# BEP33_6panel_rev1_90Grad.net
KiCad netlist of a schematic drawn in EAGLE
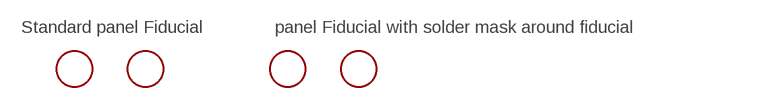
[diagram p0: schematic, sheet 1]
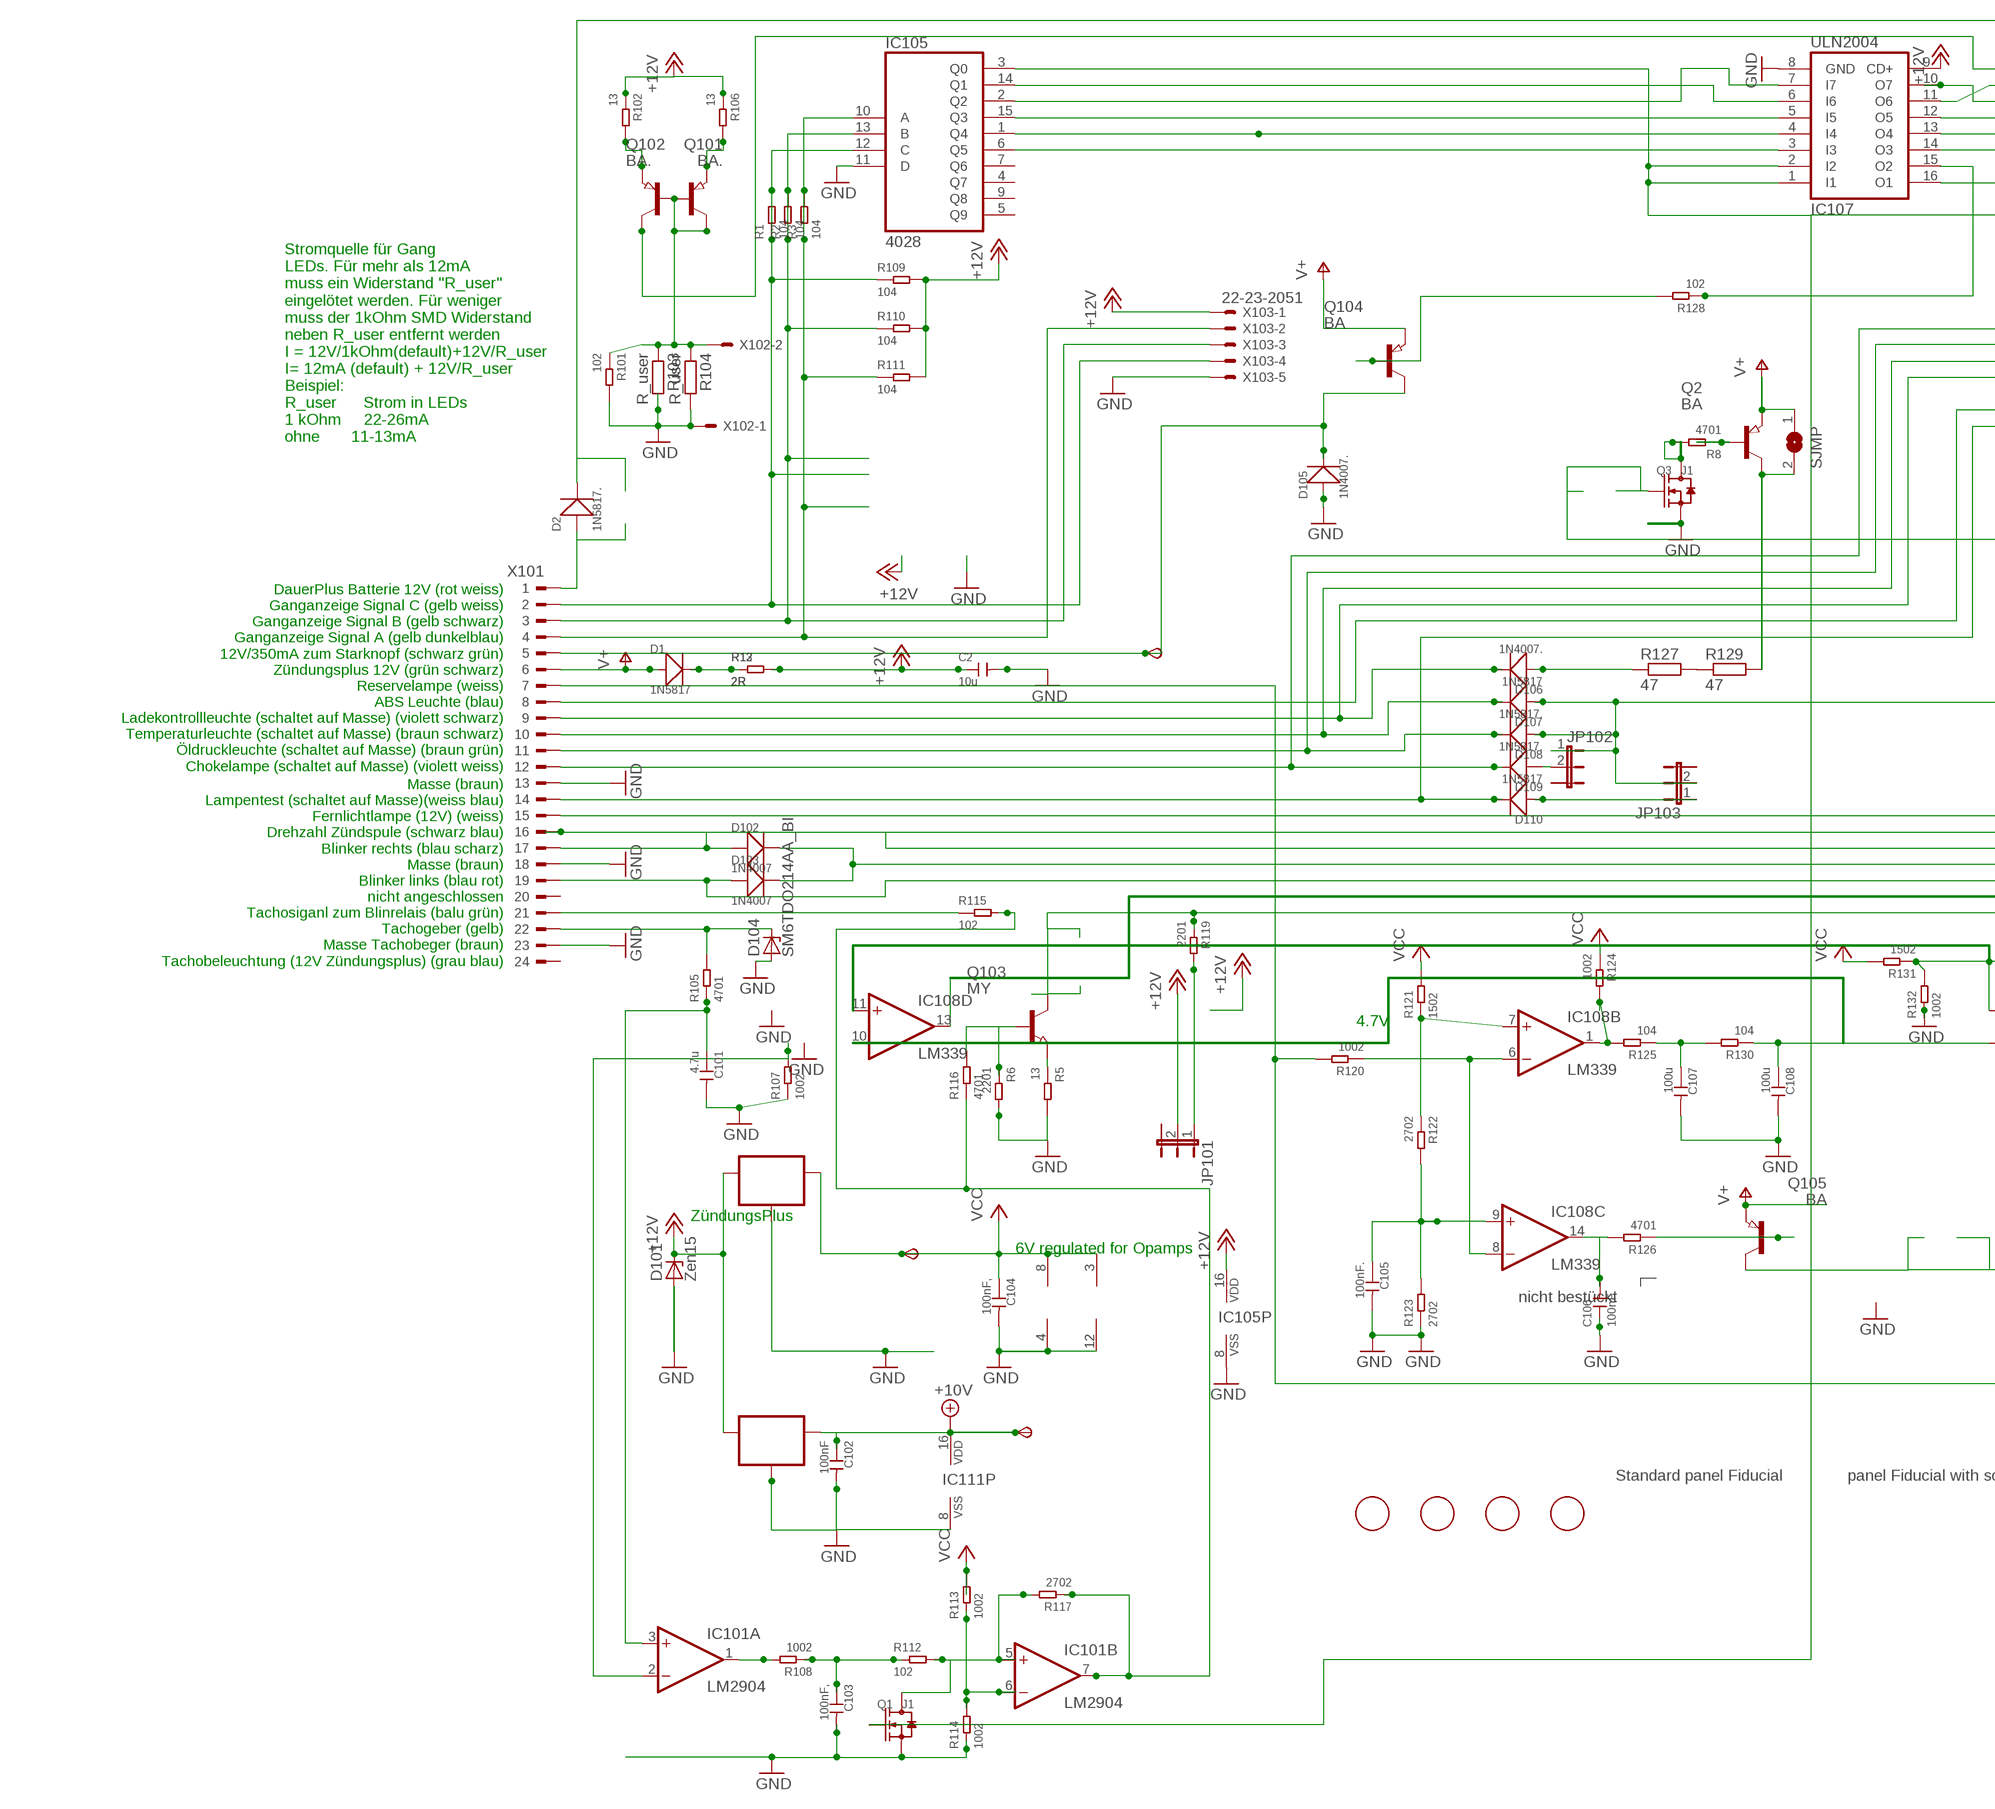
[diagram p1: schematic, sheet 2, part 1 of 2]
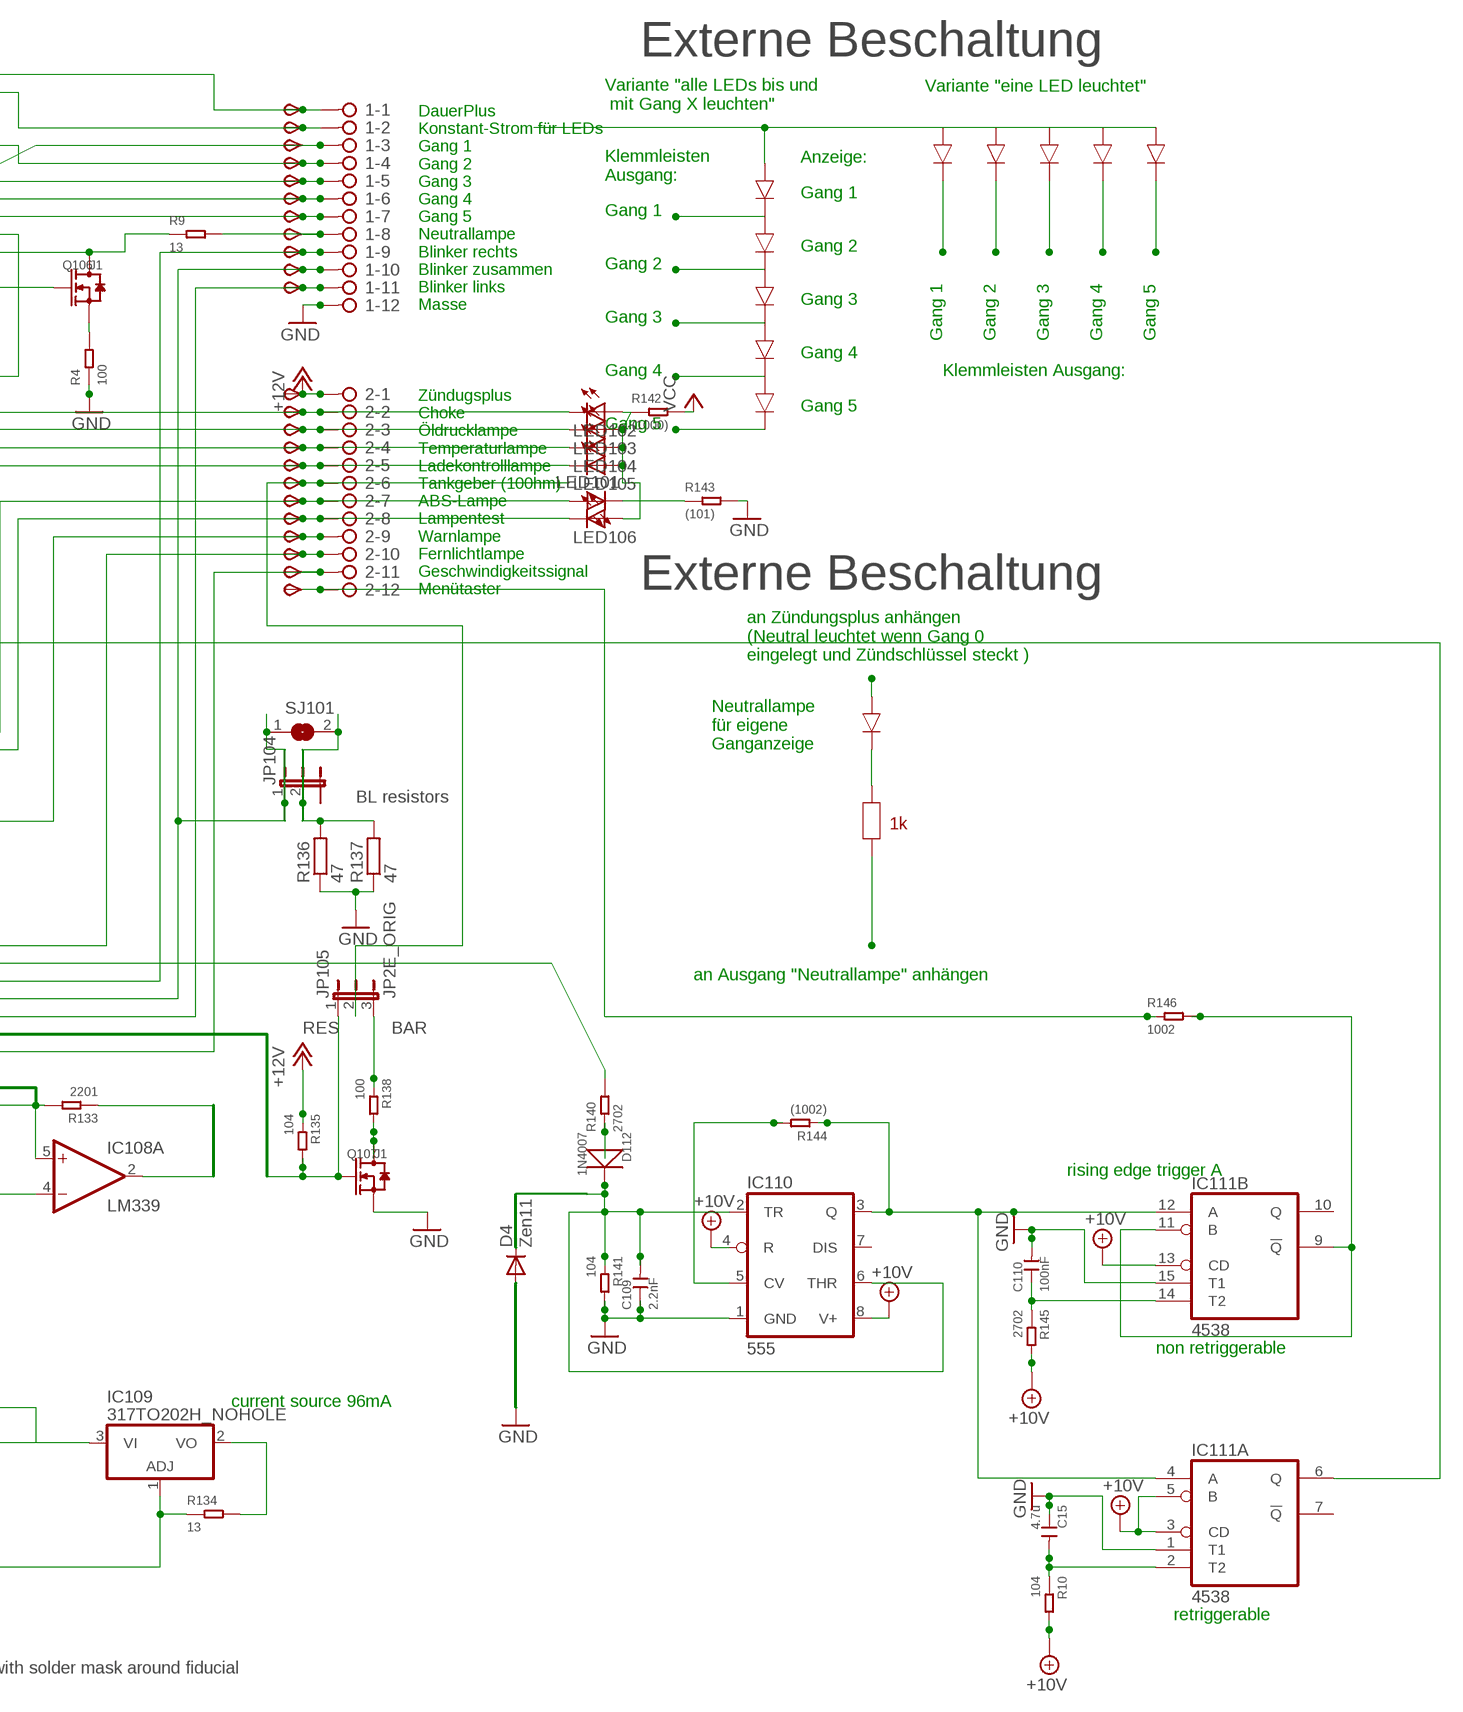
[diagram p2: schematic, sheet 2, part 2 of 2]
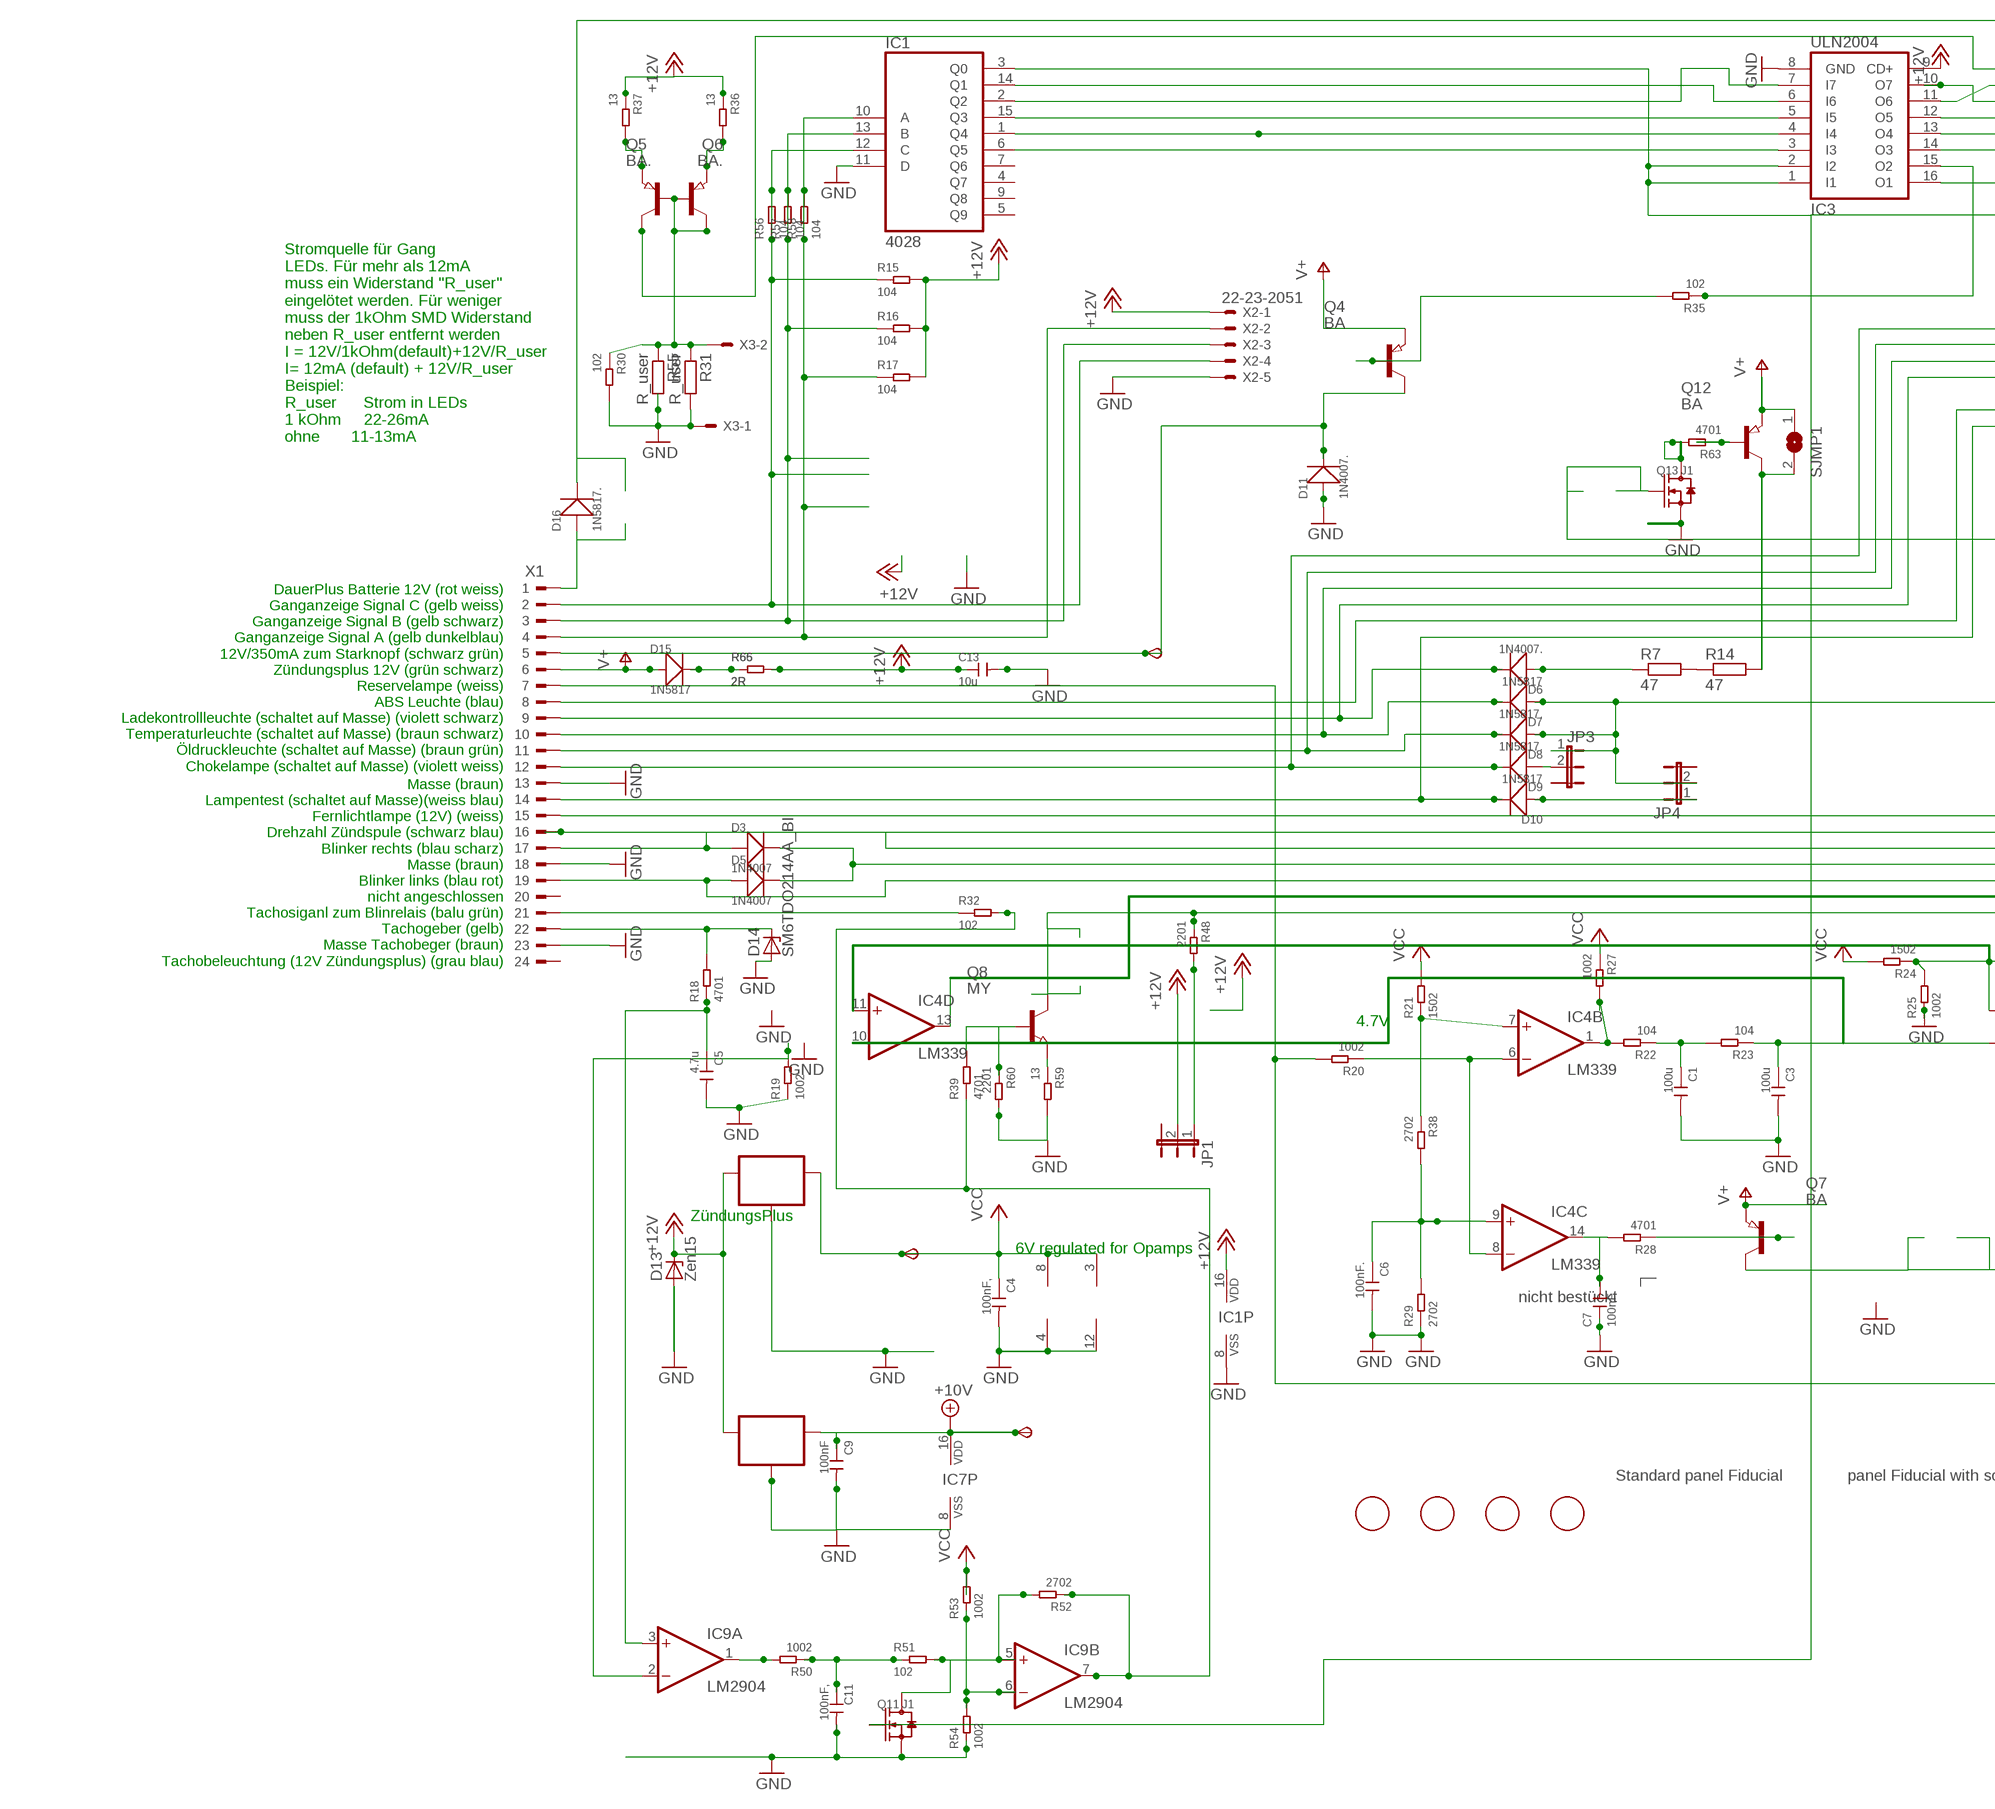
[diagram p3: schematic, sheet 3, part 1 of 2]
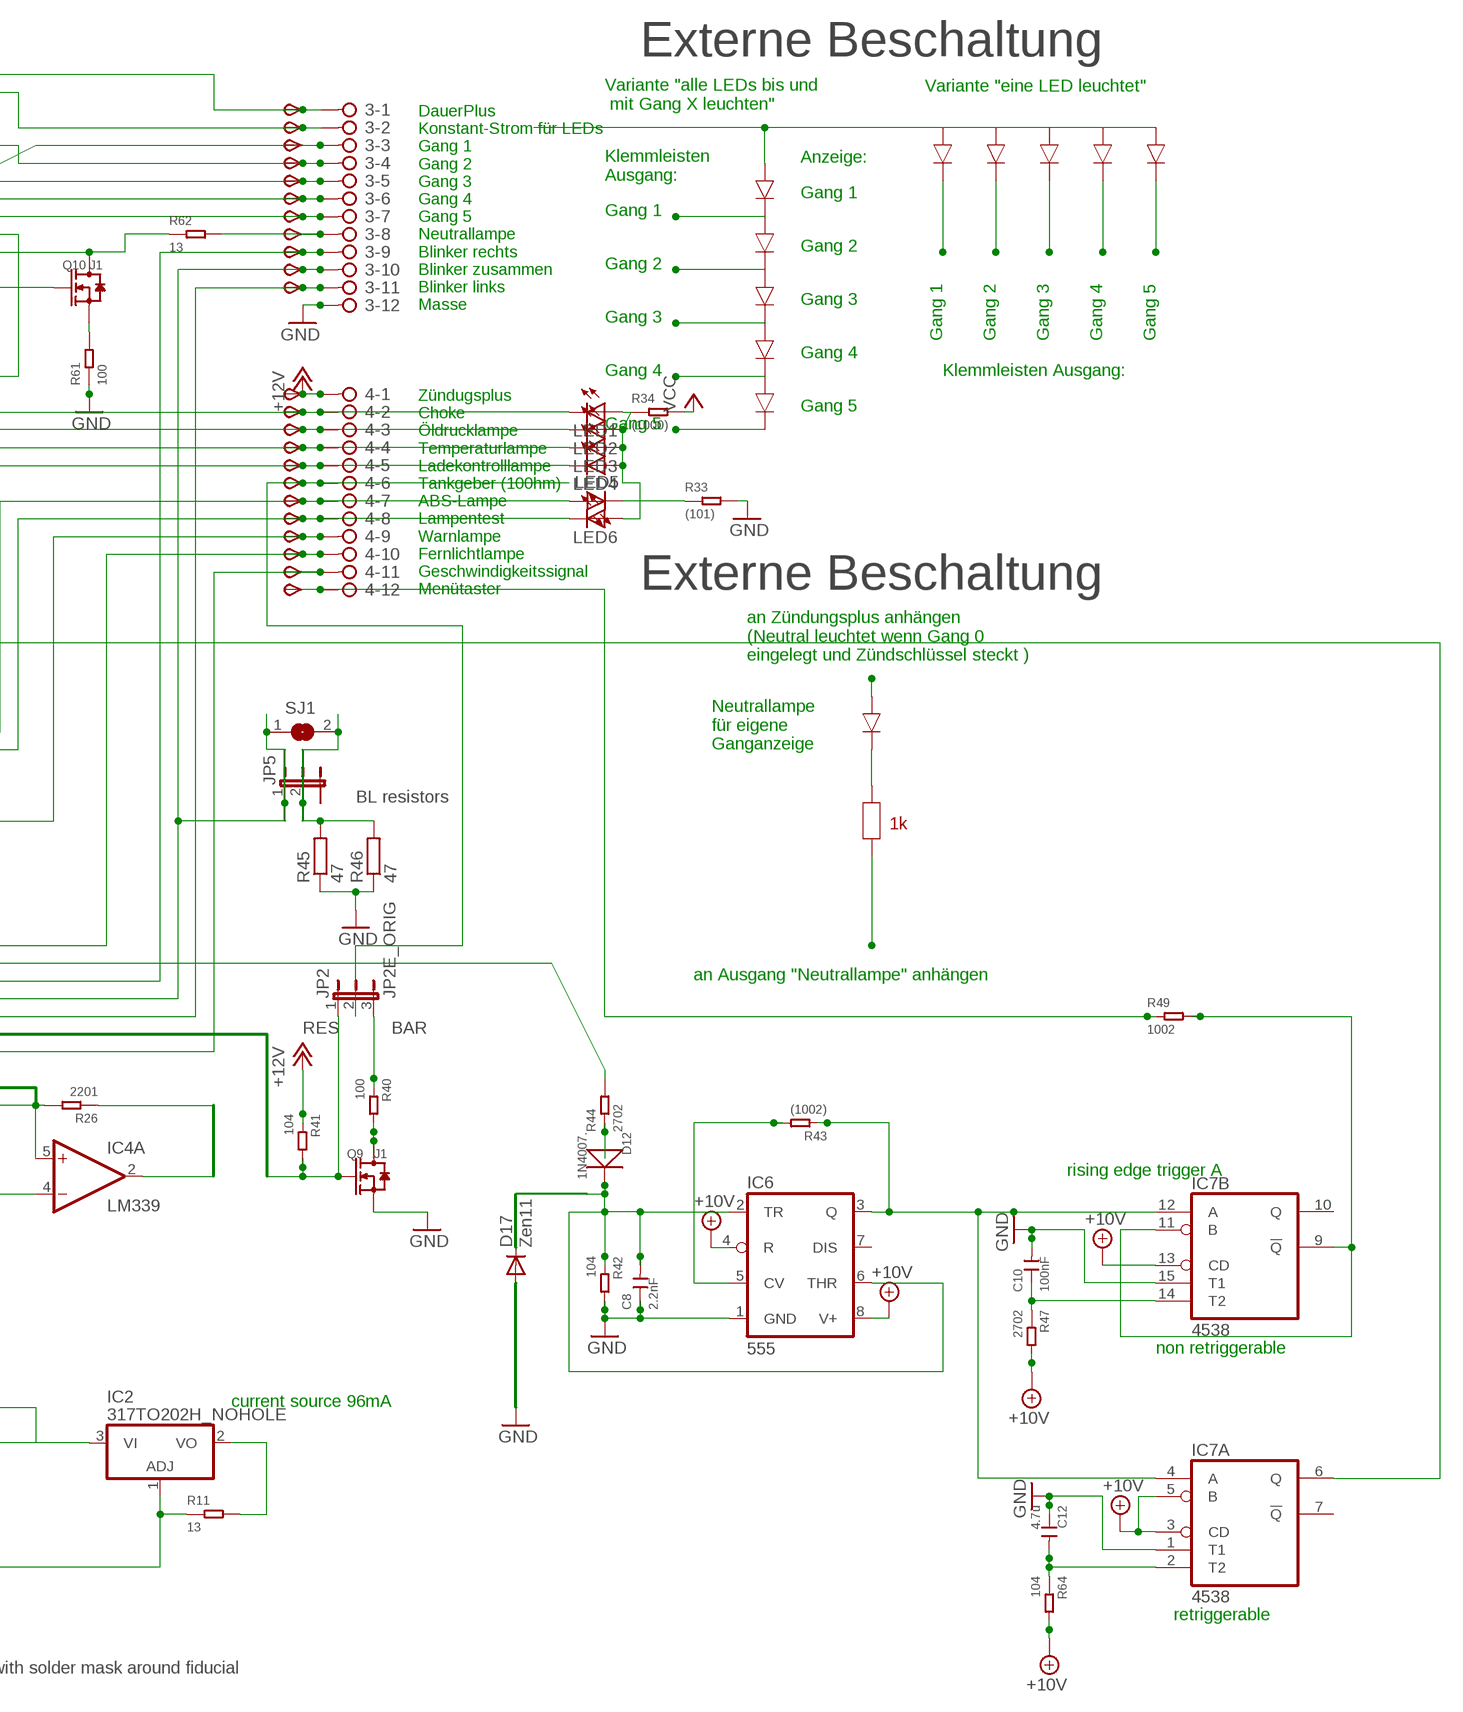
[diagram p4: schematic, sheet 3, part 2 of 2]
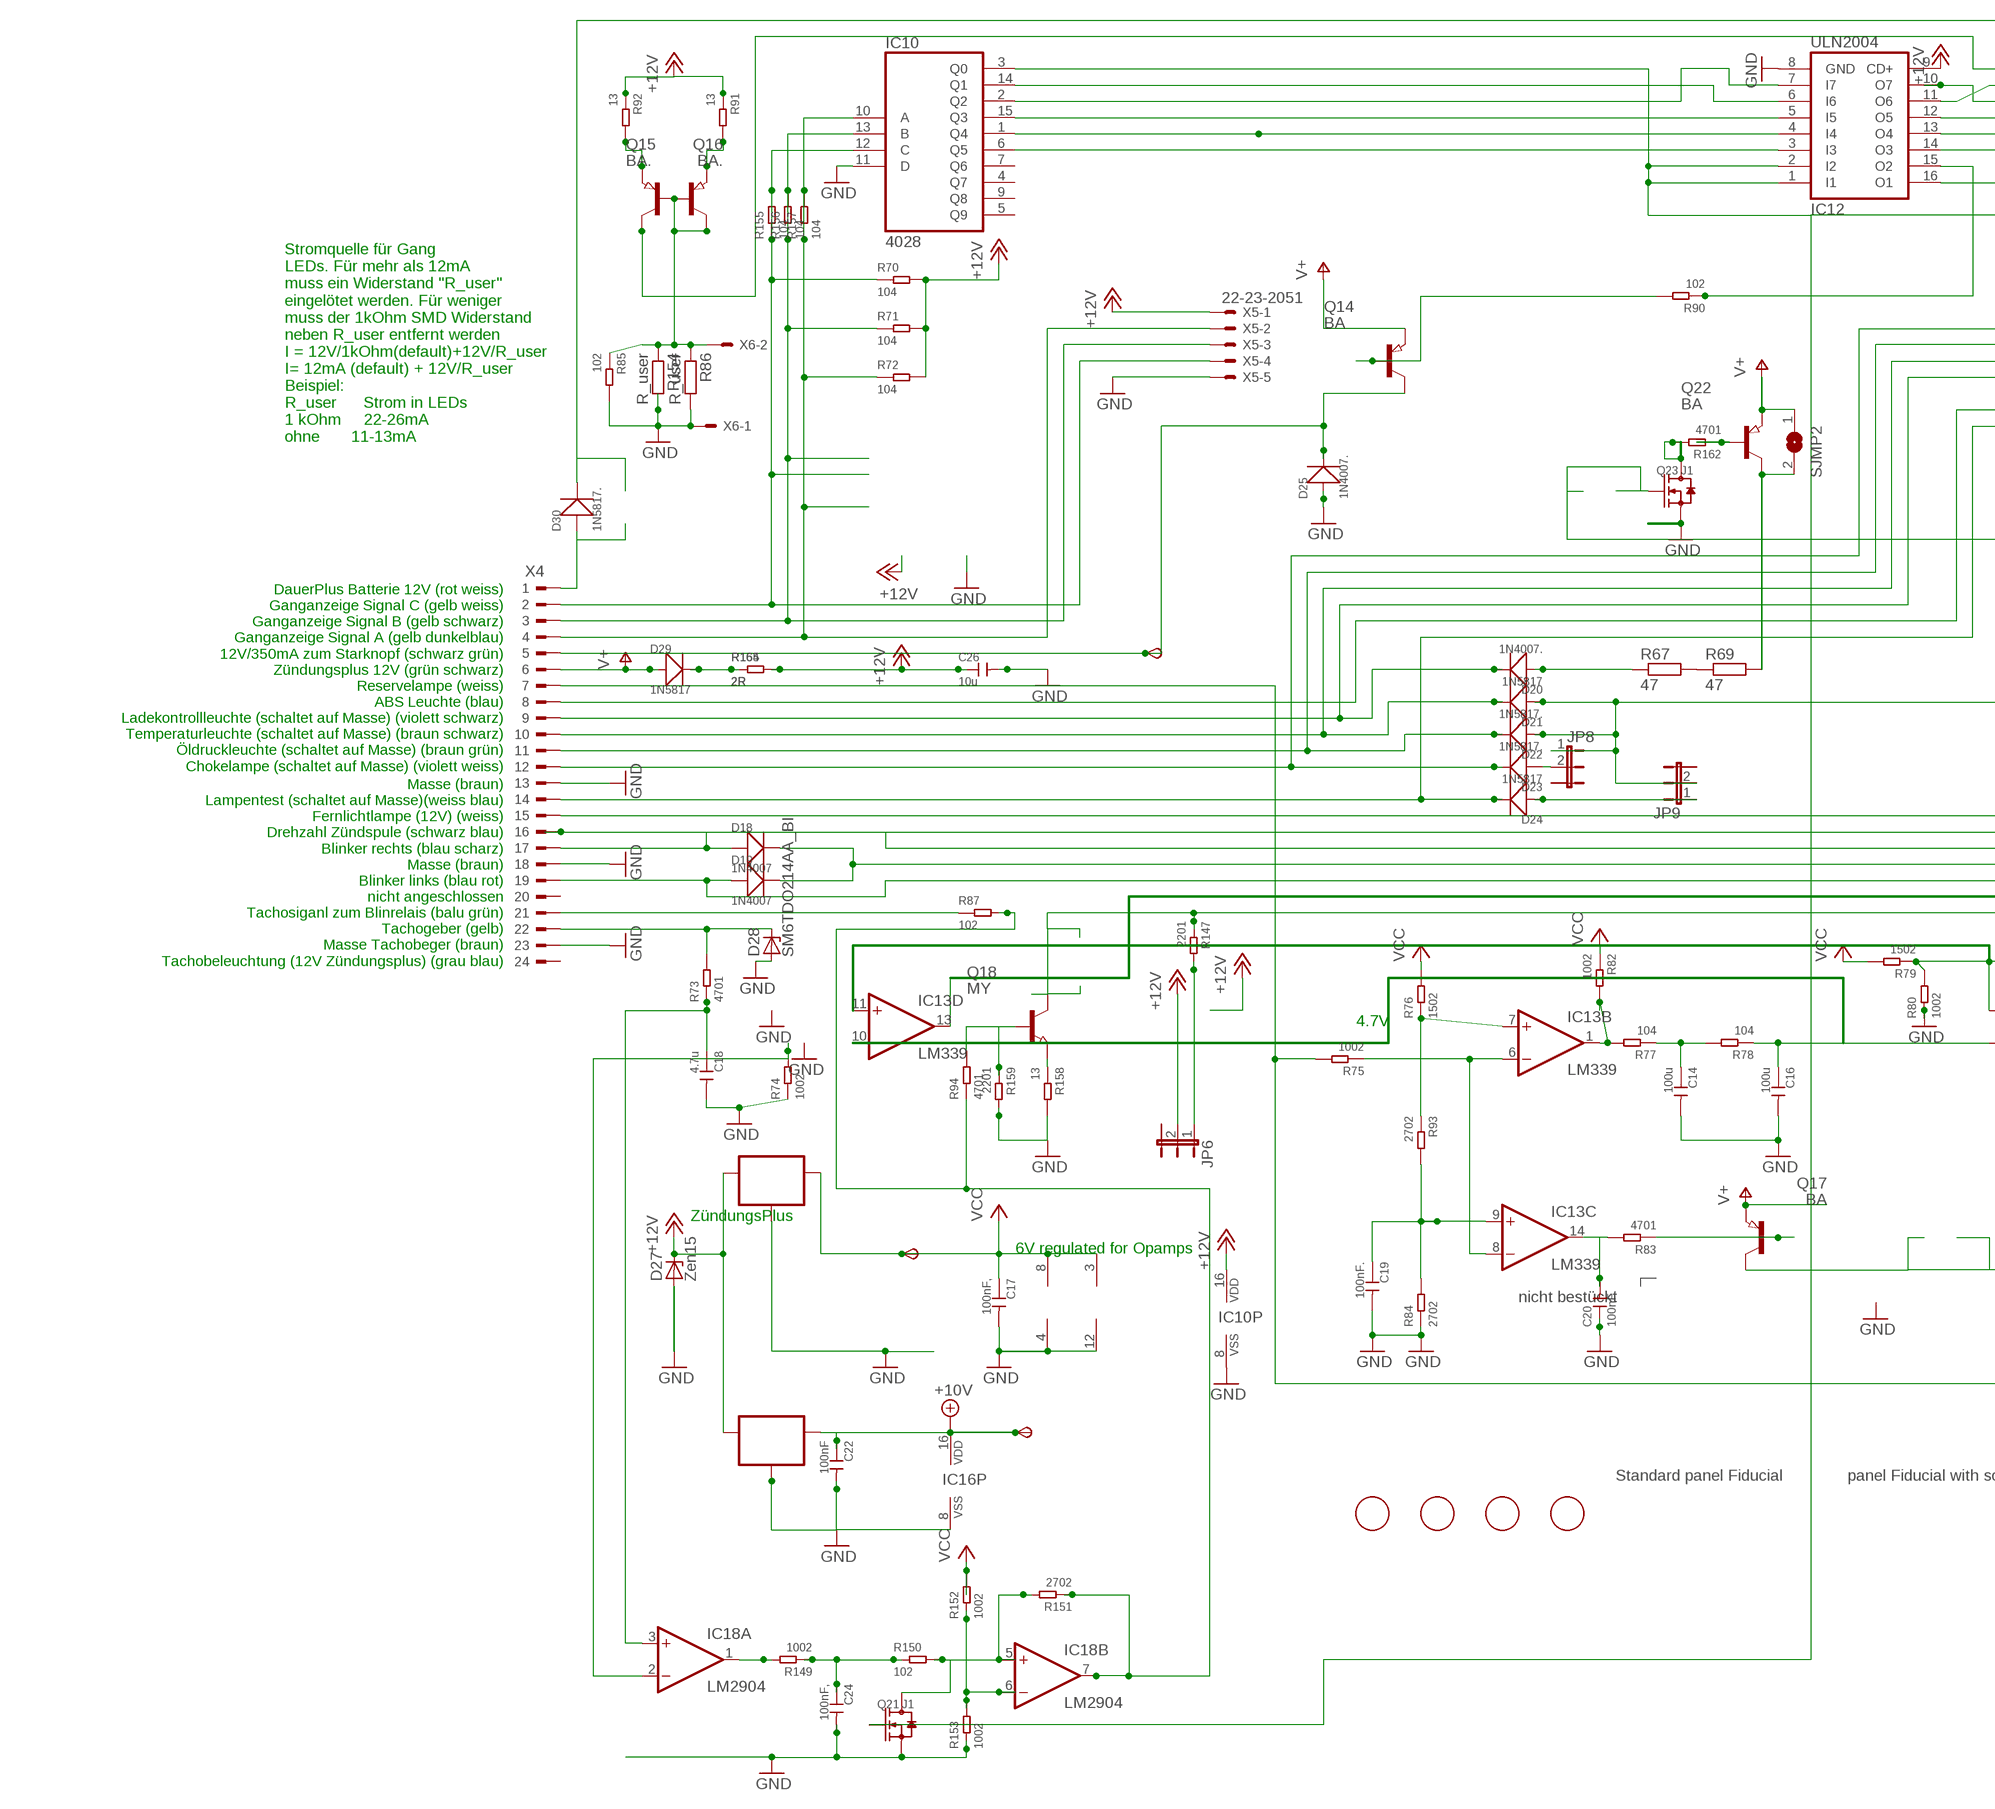
[diagram p5: schematic, sheet 4, part 1 of 2]
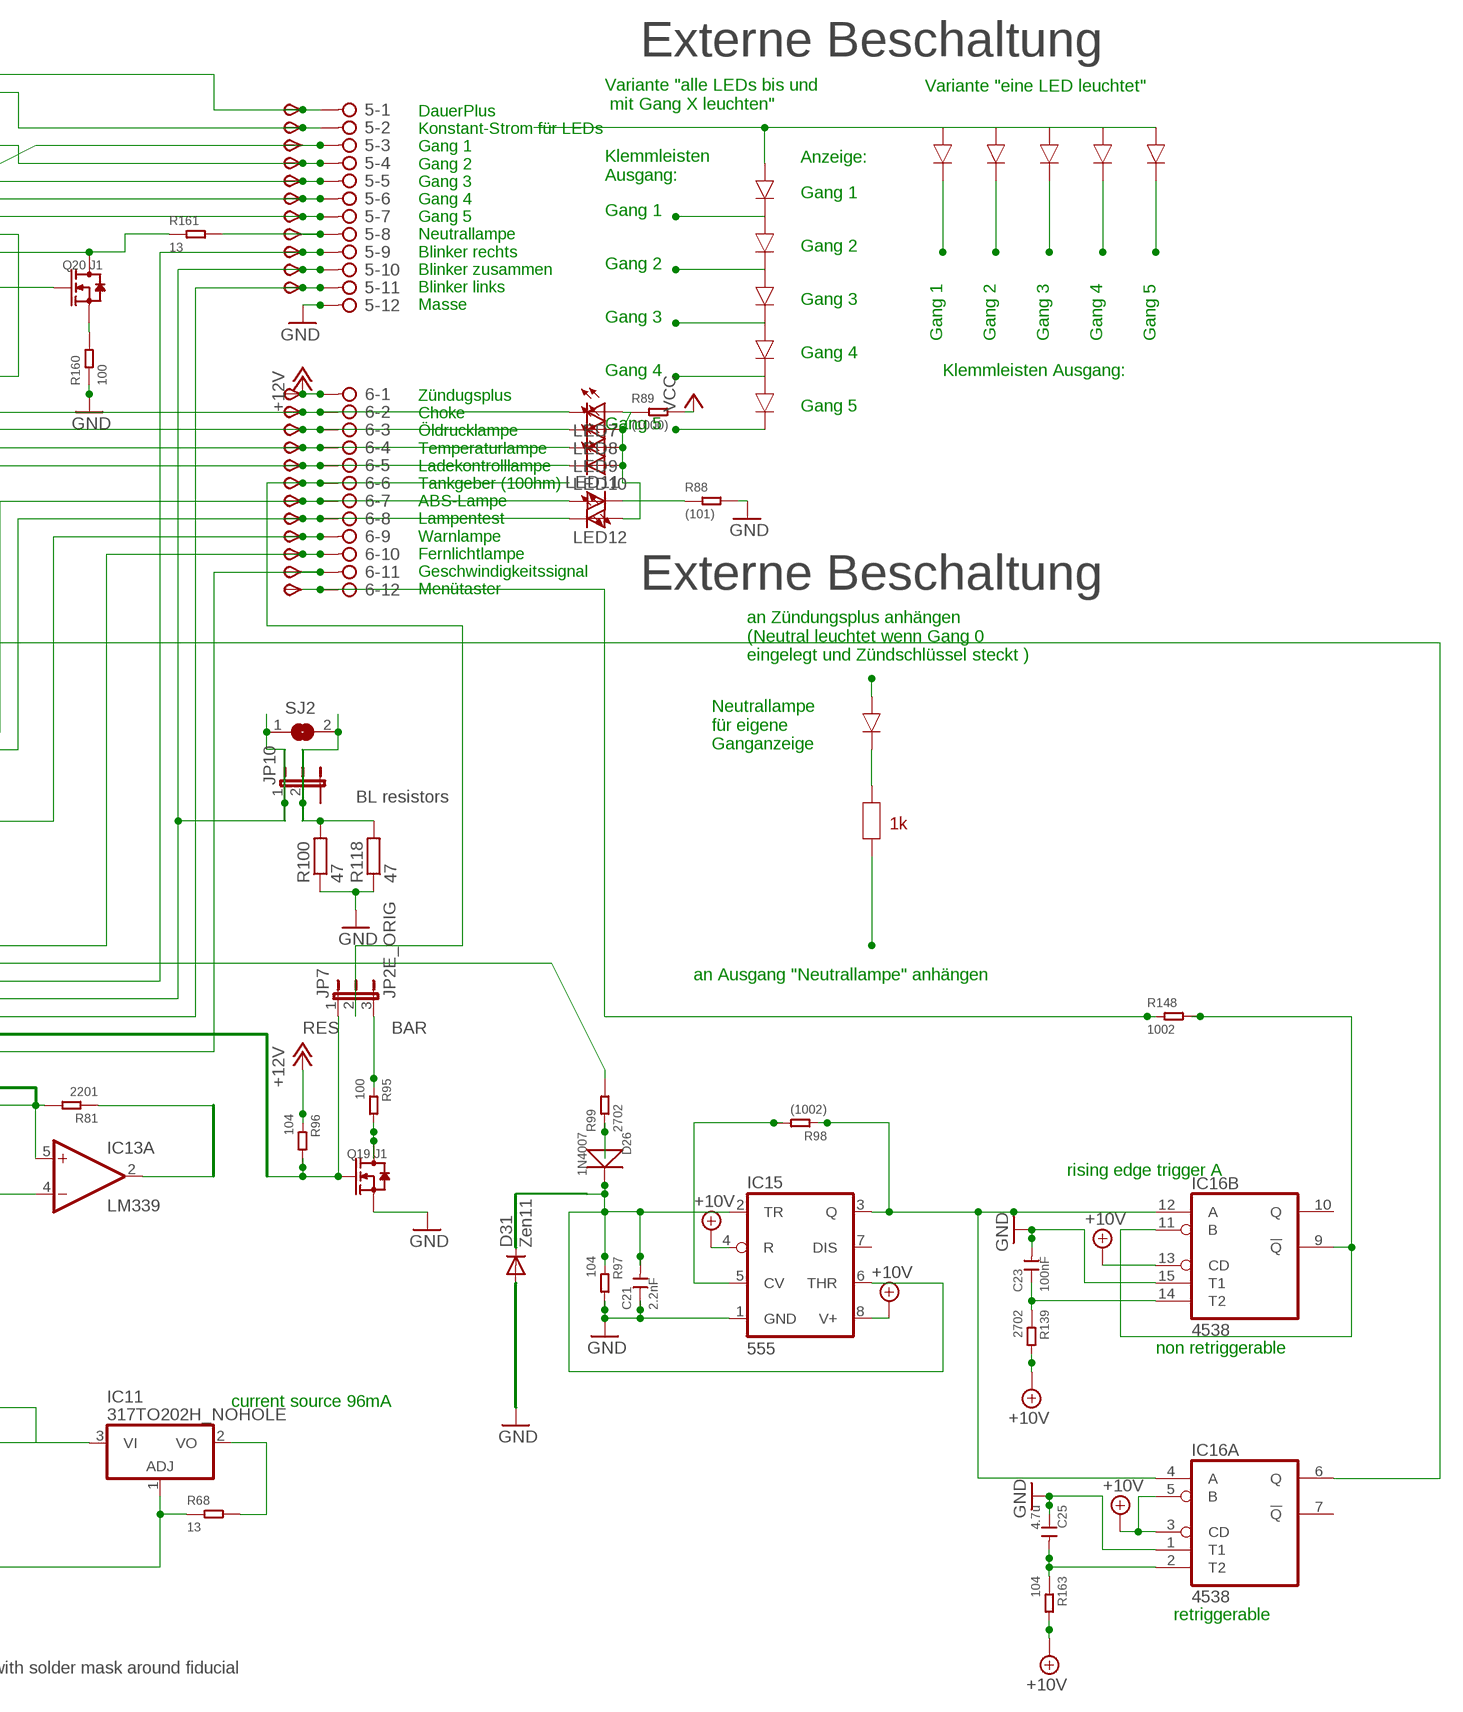
[diagram p6: schematic, sheet 4, part 2 of 2]
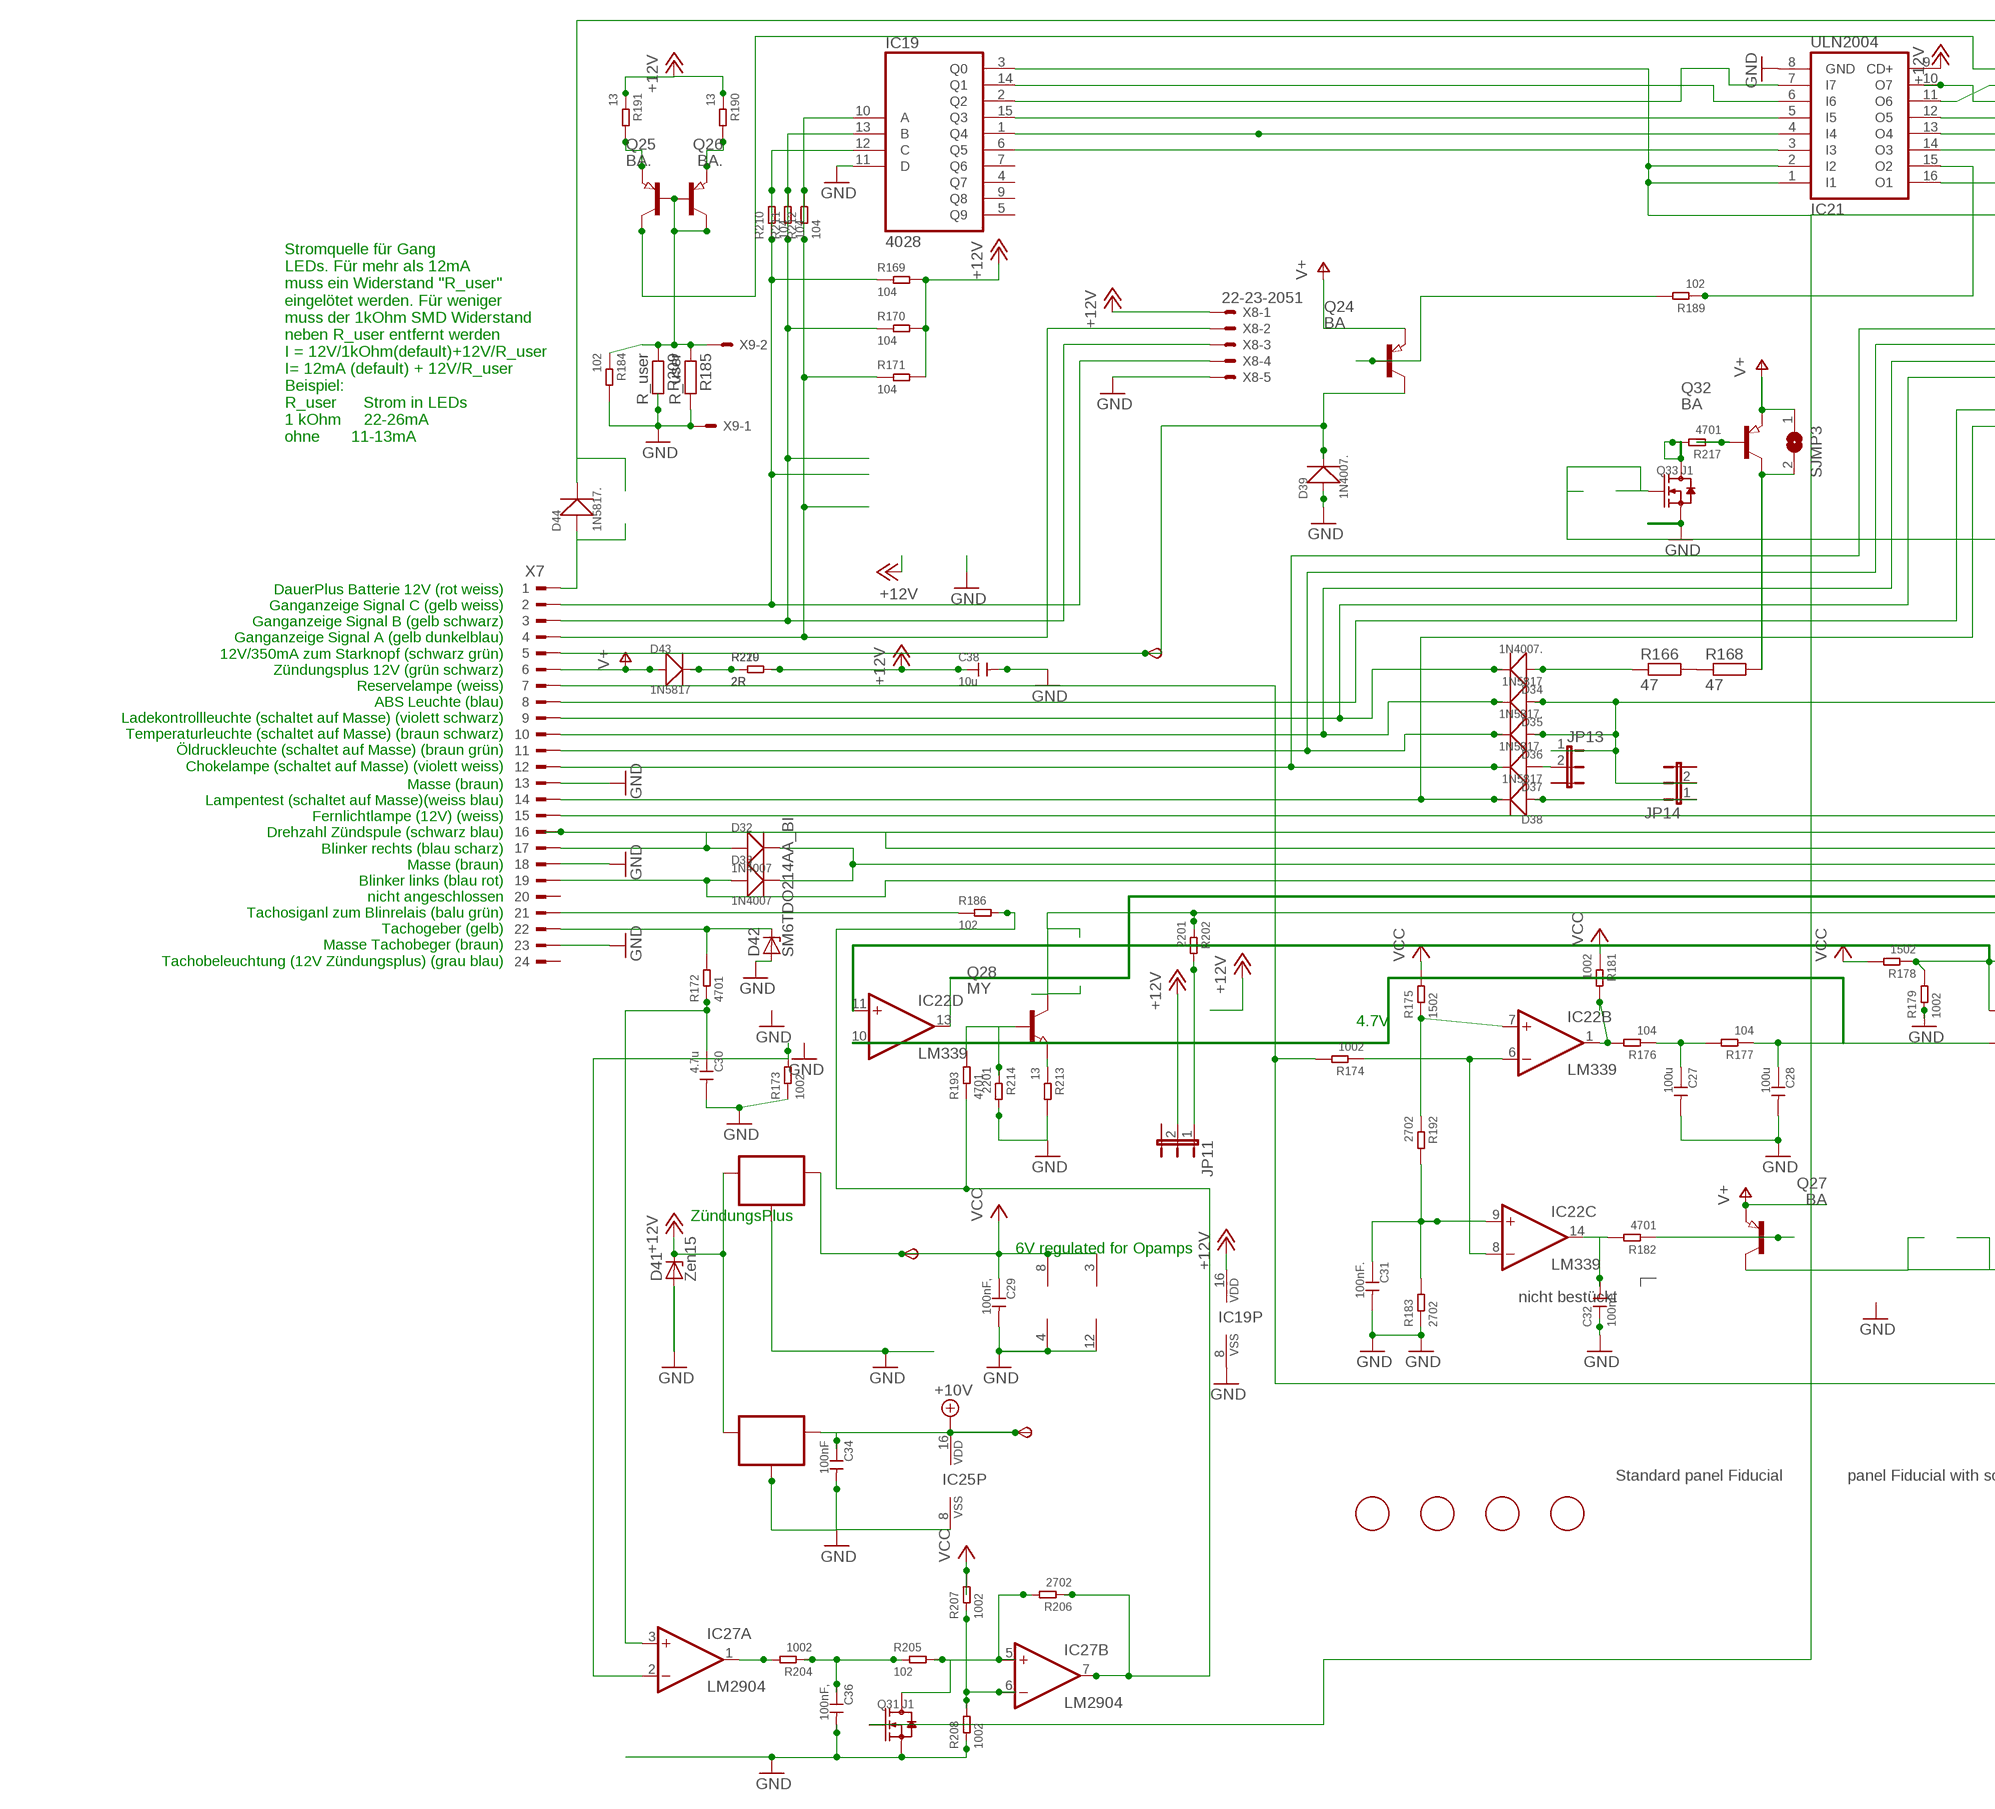
[diagram p7: schematic, sheet 5, part 1 of 2]
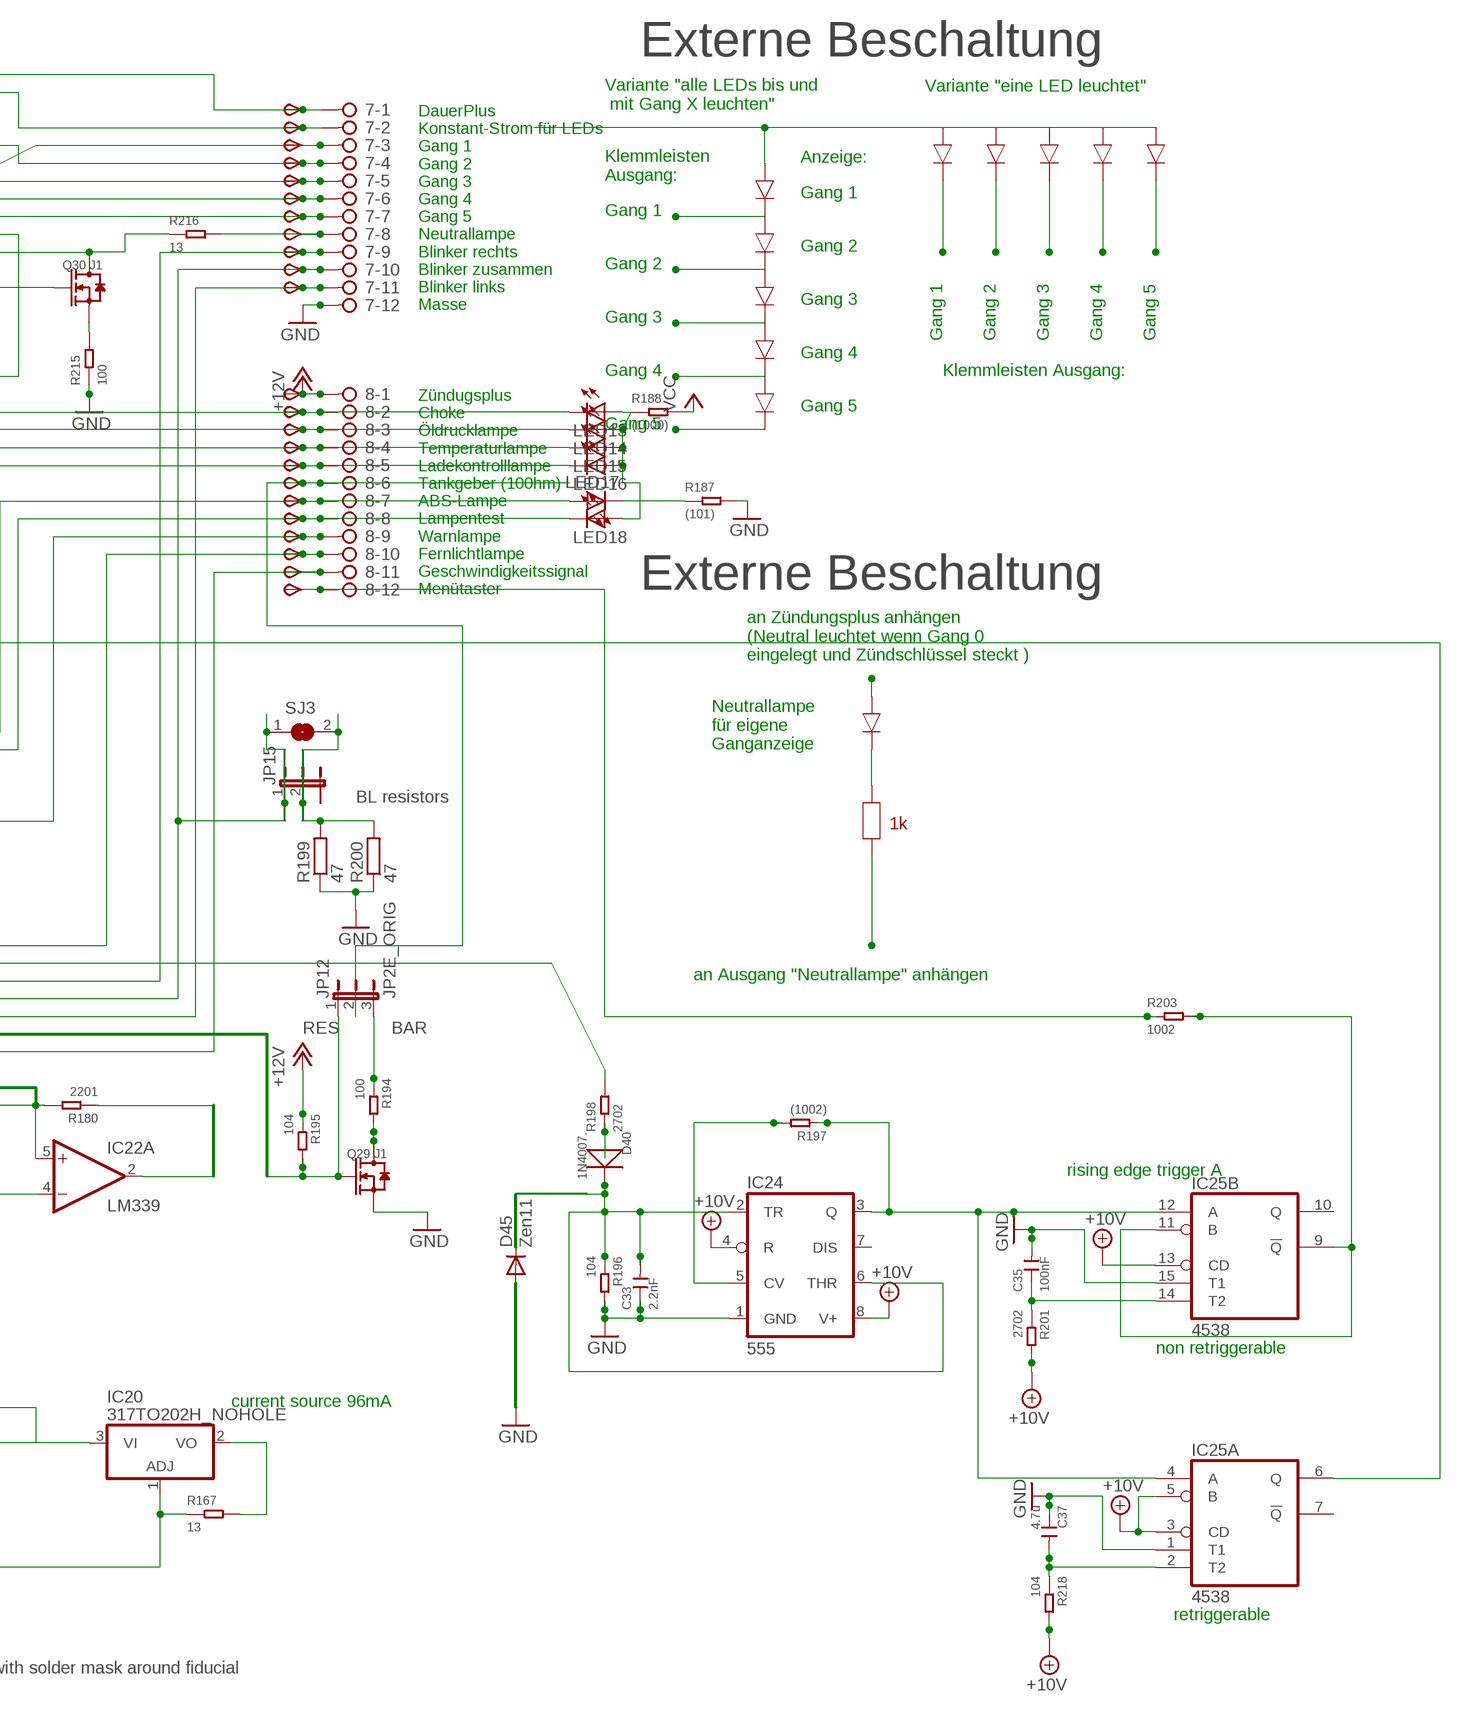
[diagram p8: schematic, sheet 5, part 2 of 2]
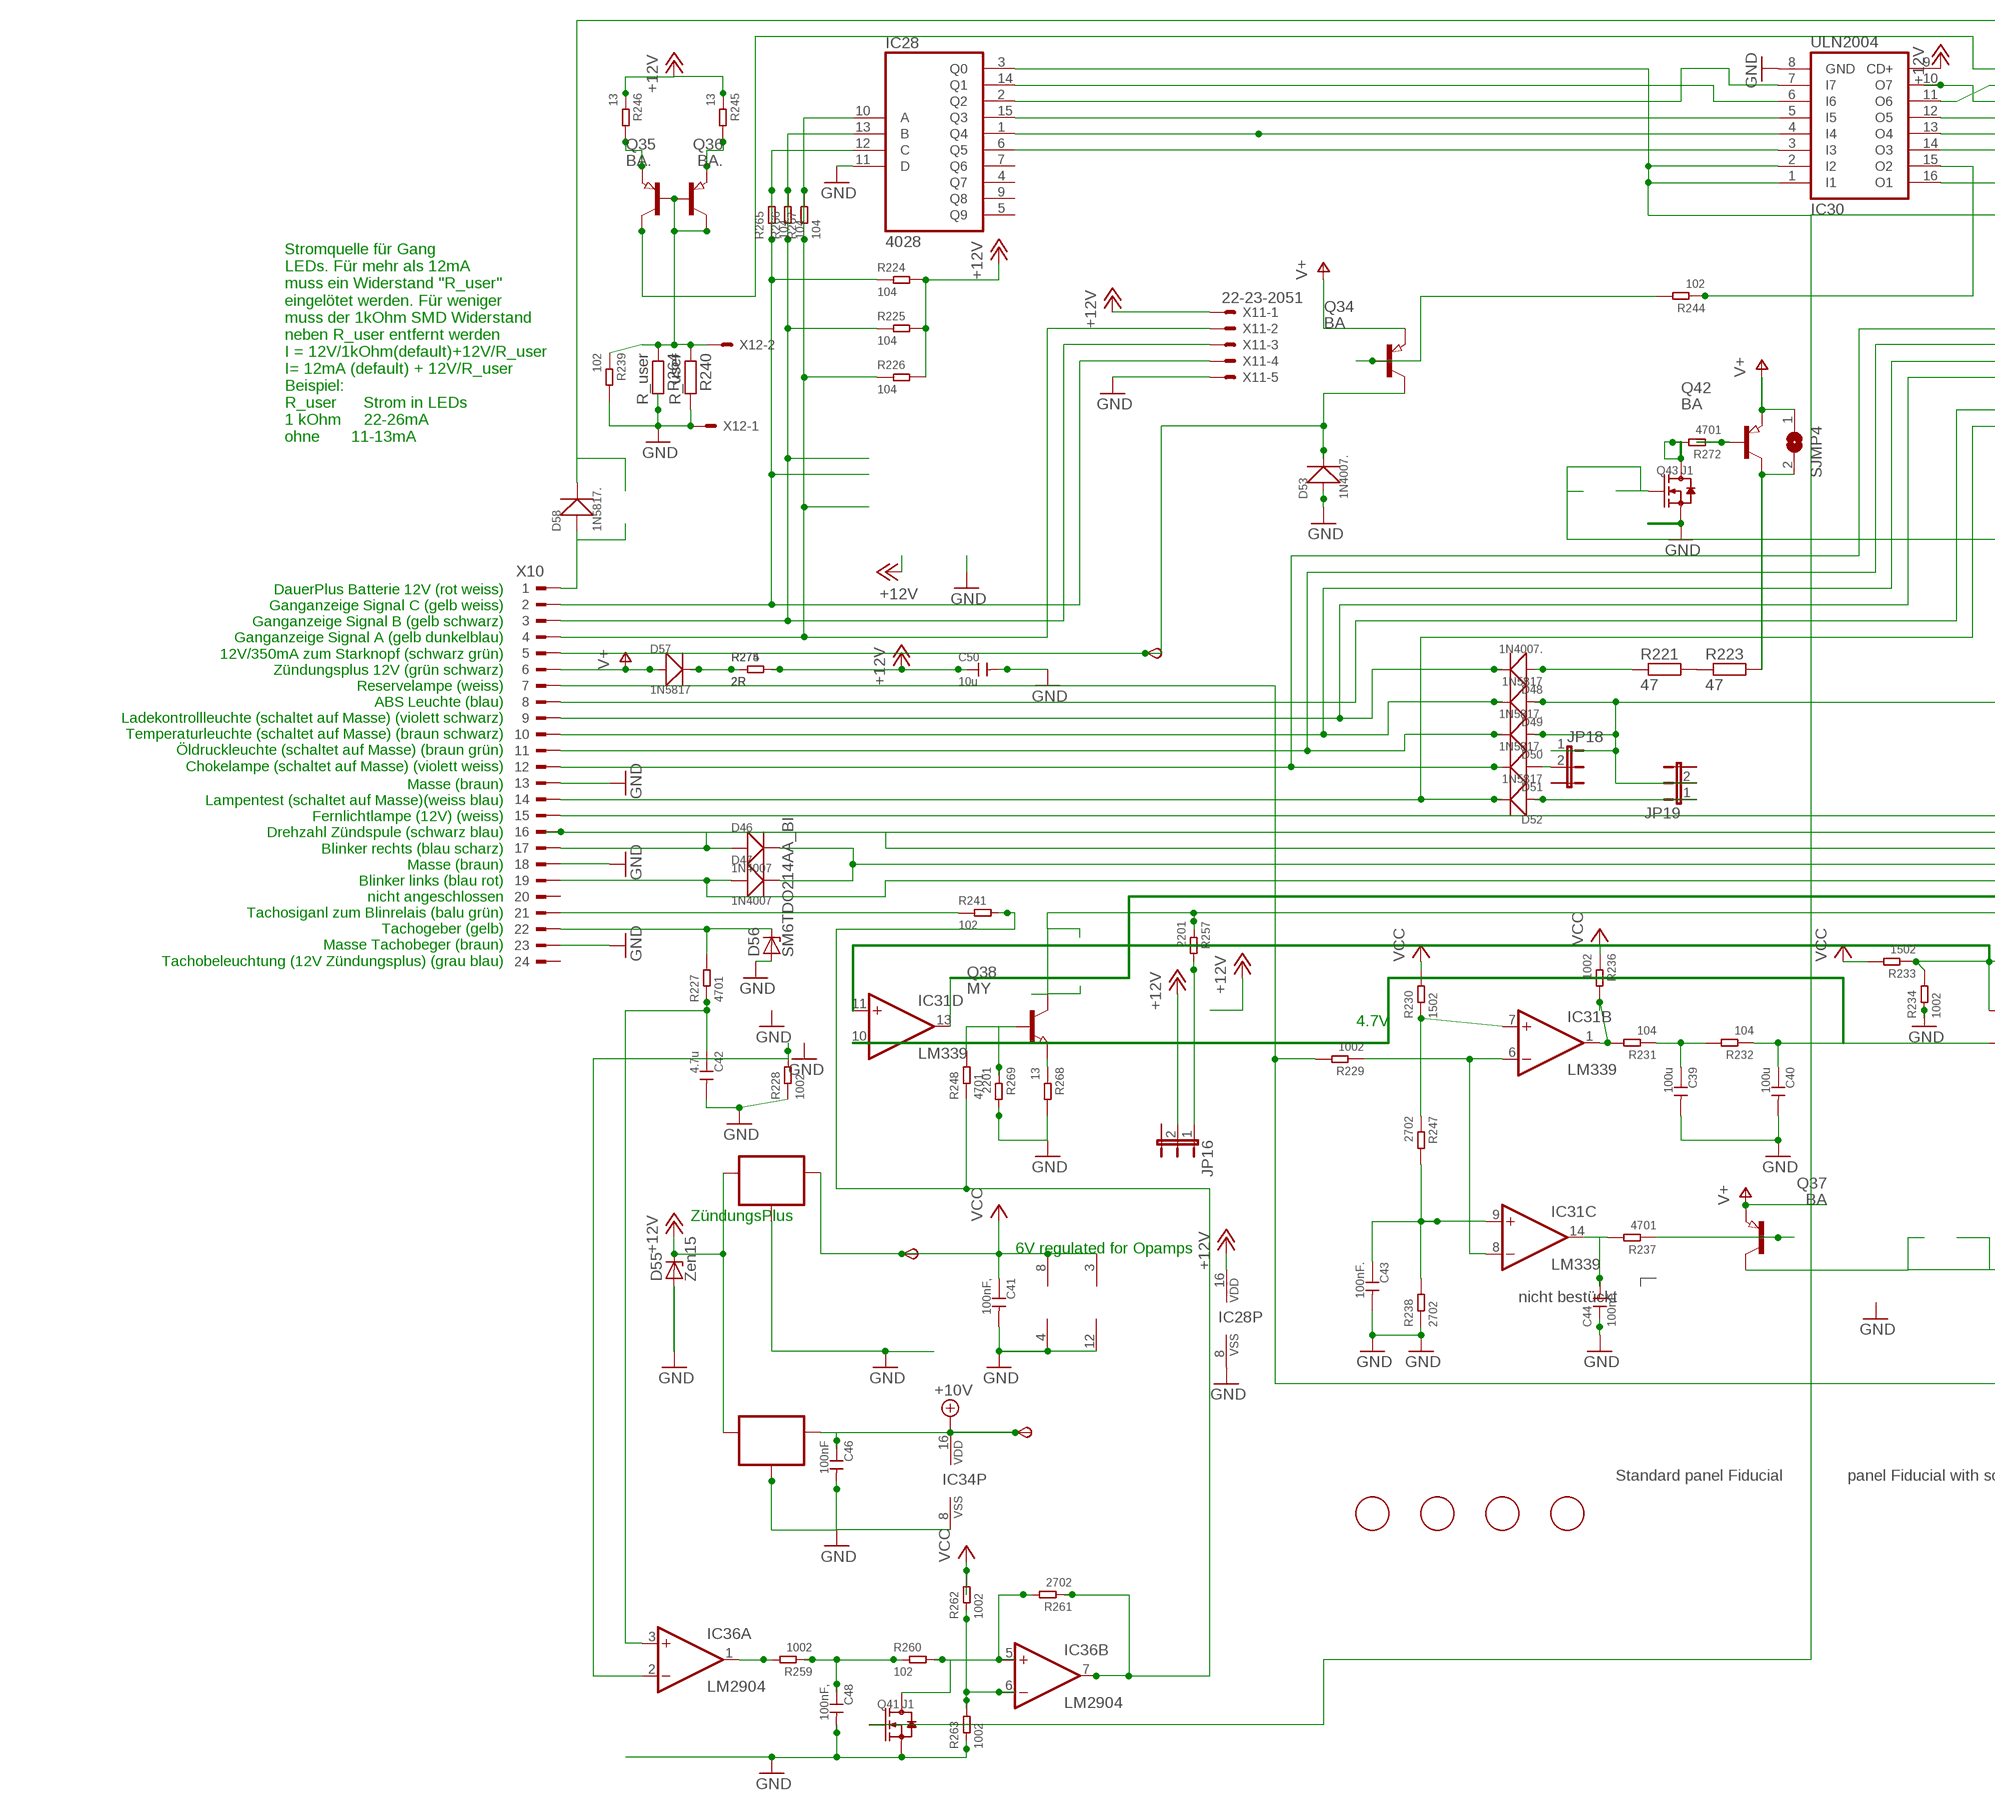
[diagram p9: schematic, sheet 6, part 1 of 2]
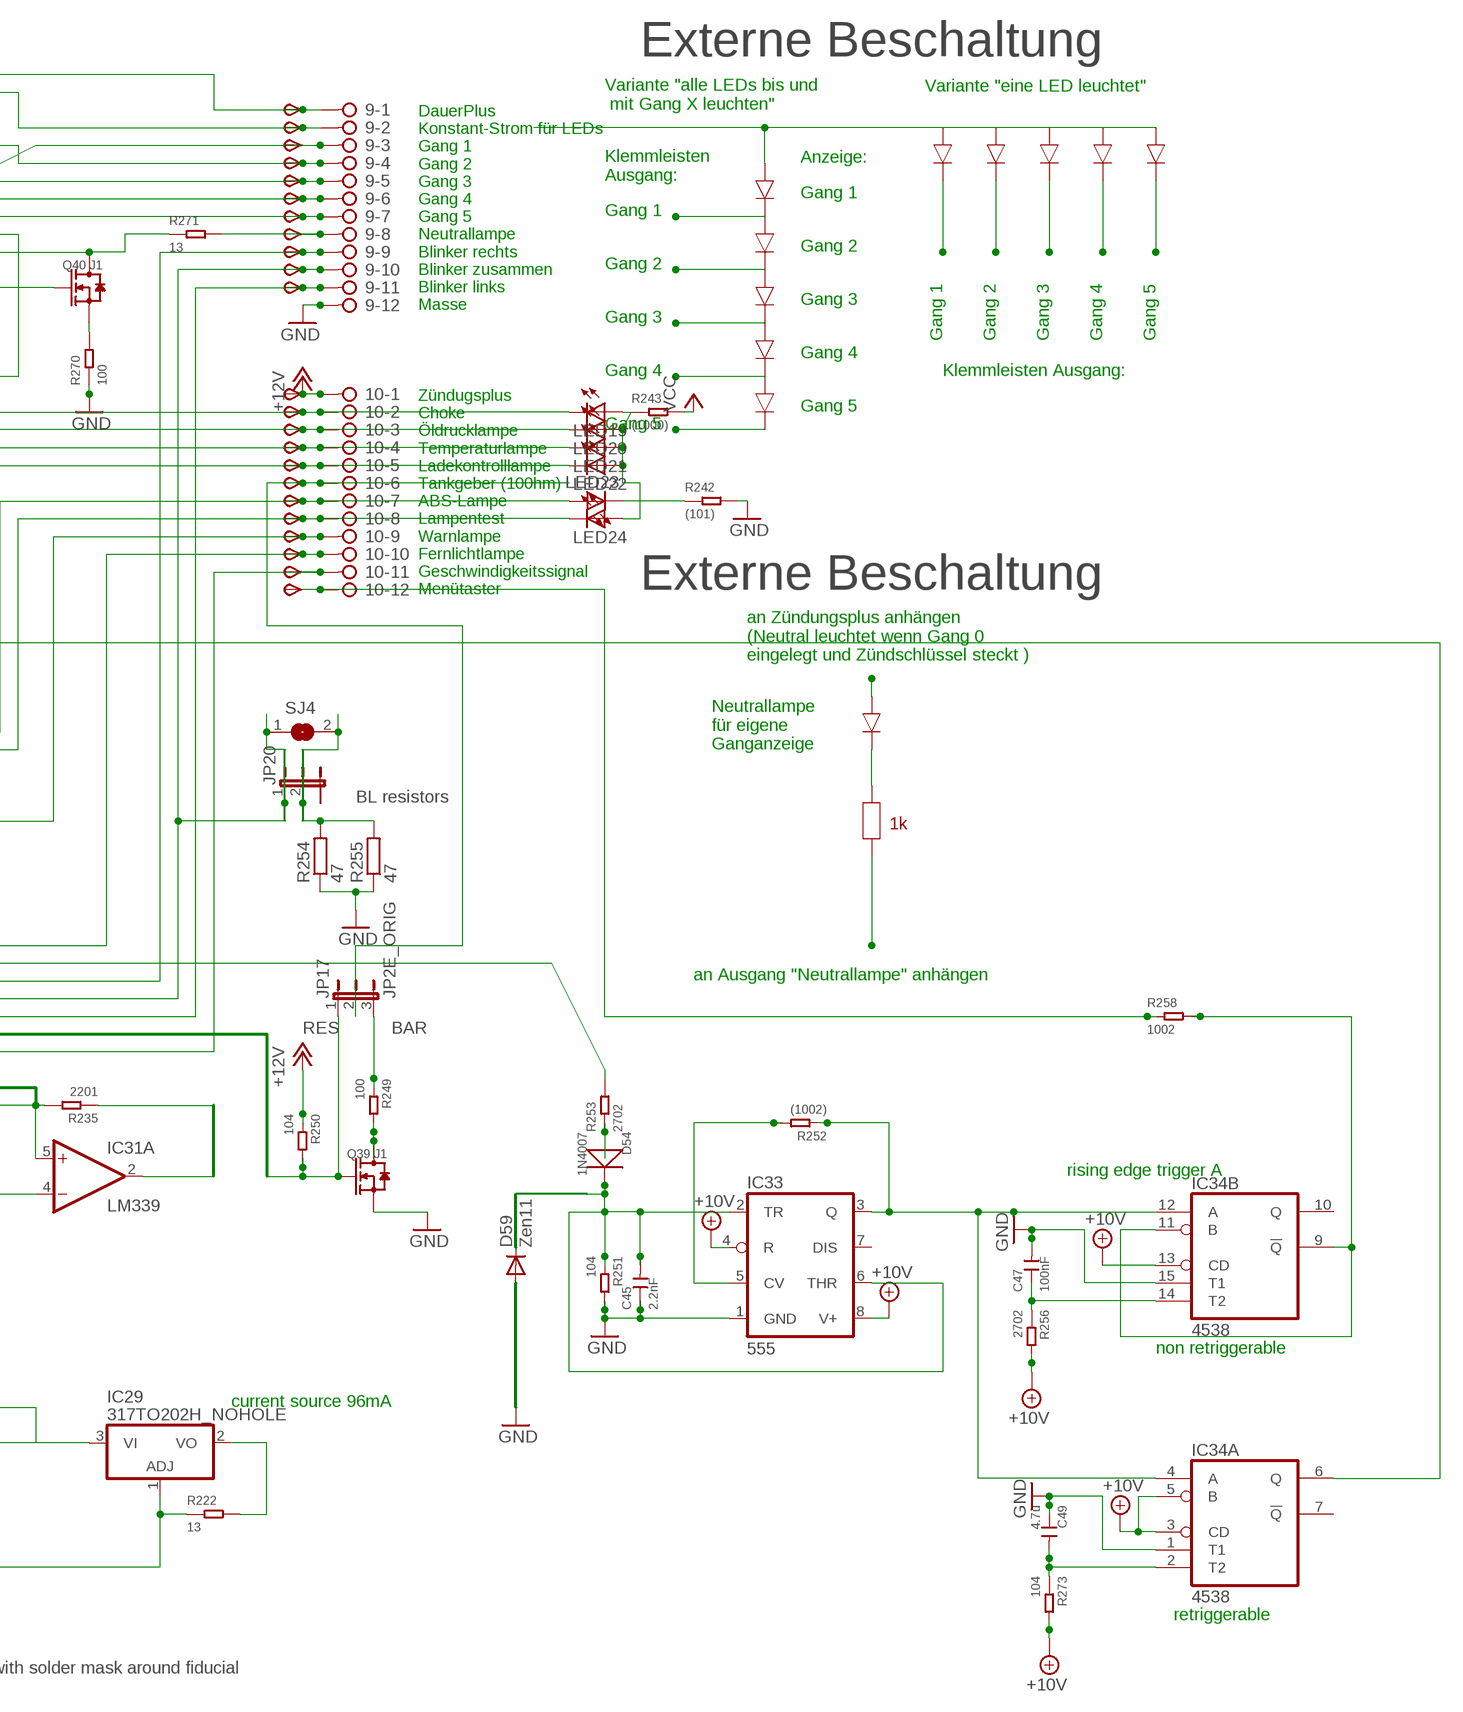
[diagram p10: schematic, sheet 6, part 2 of 2]
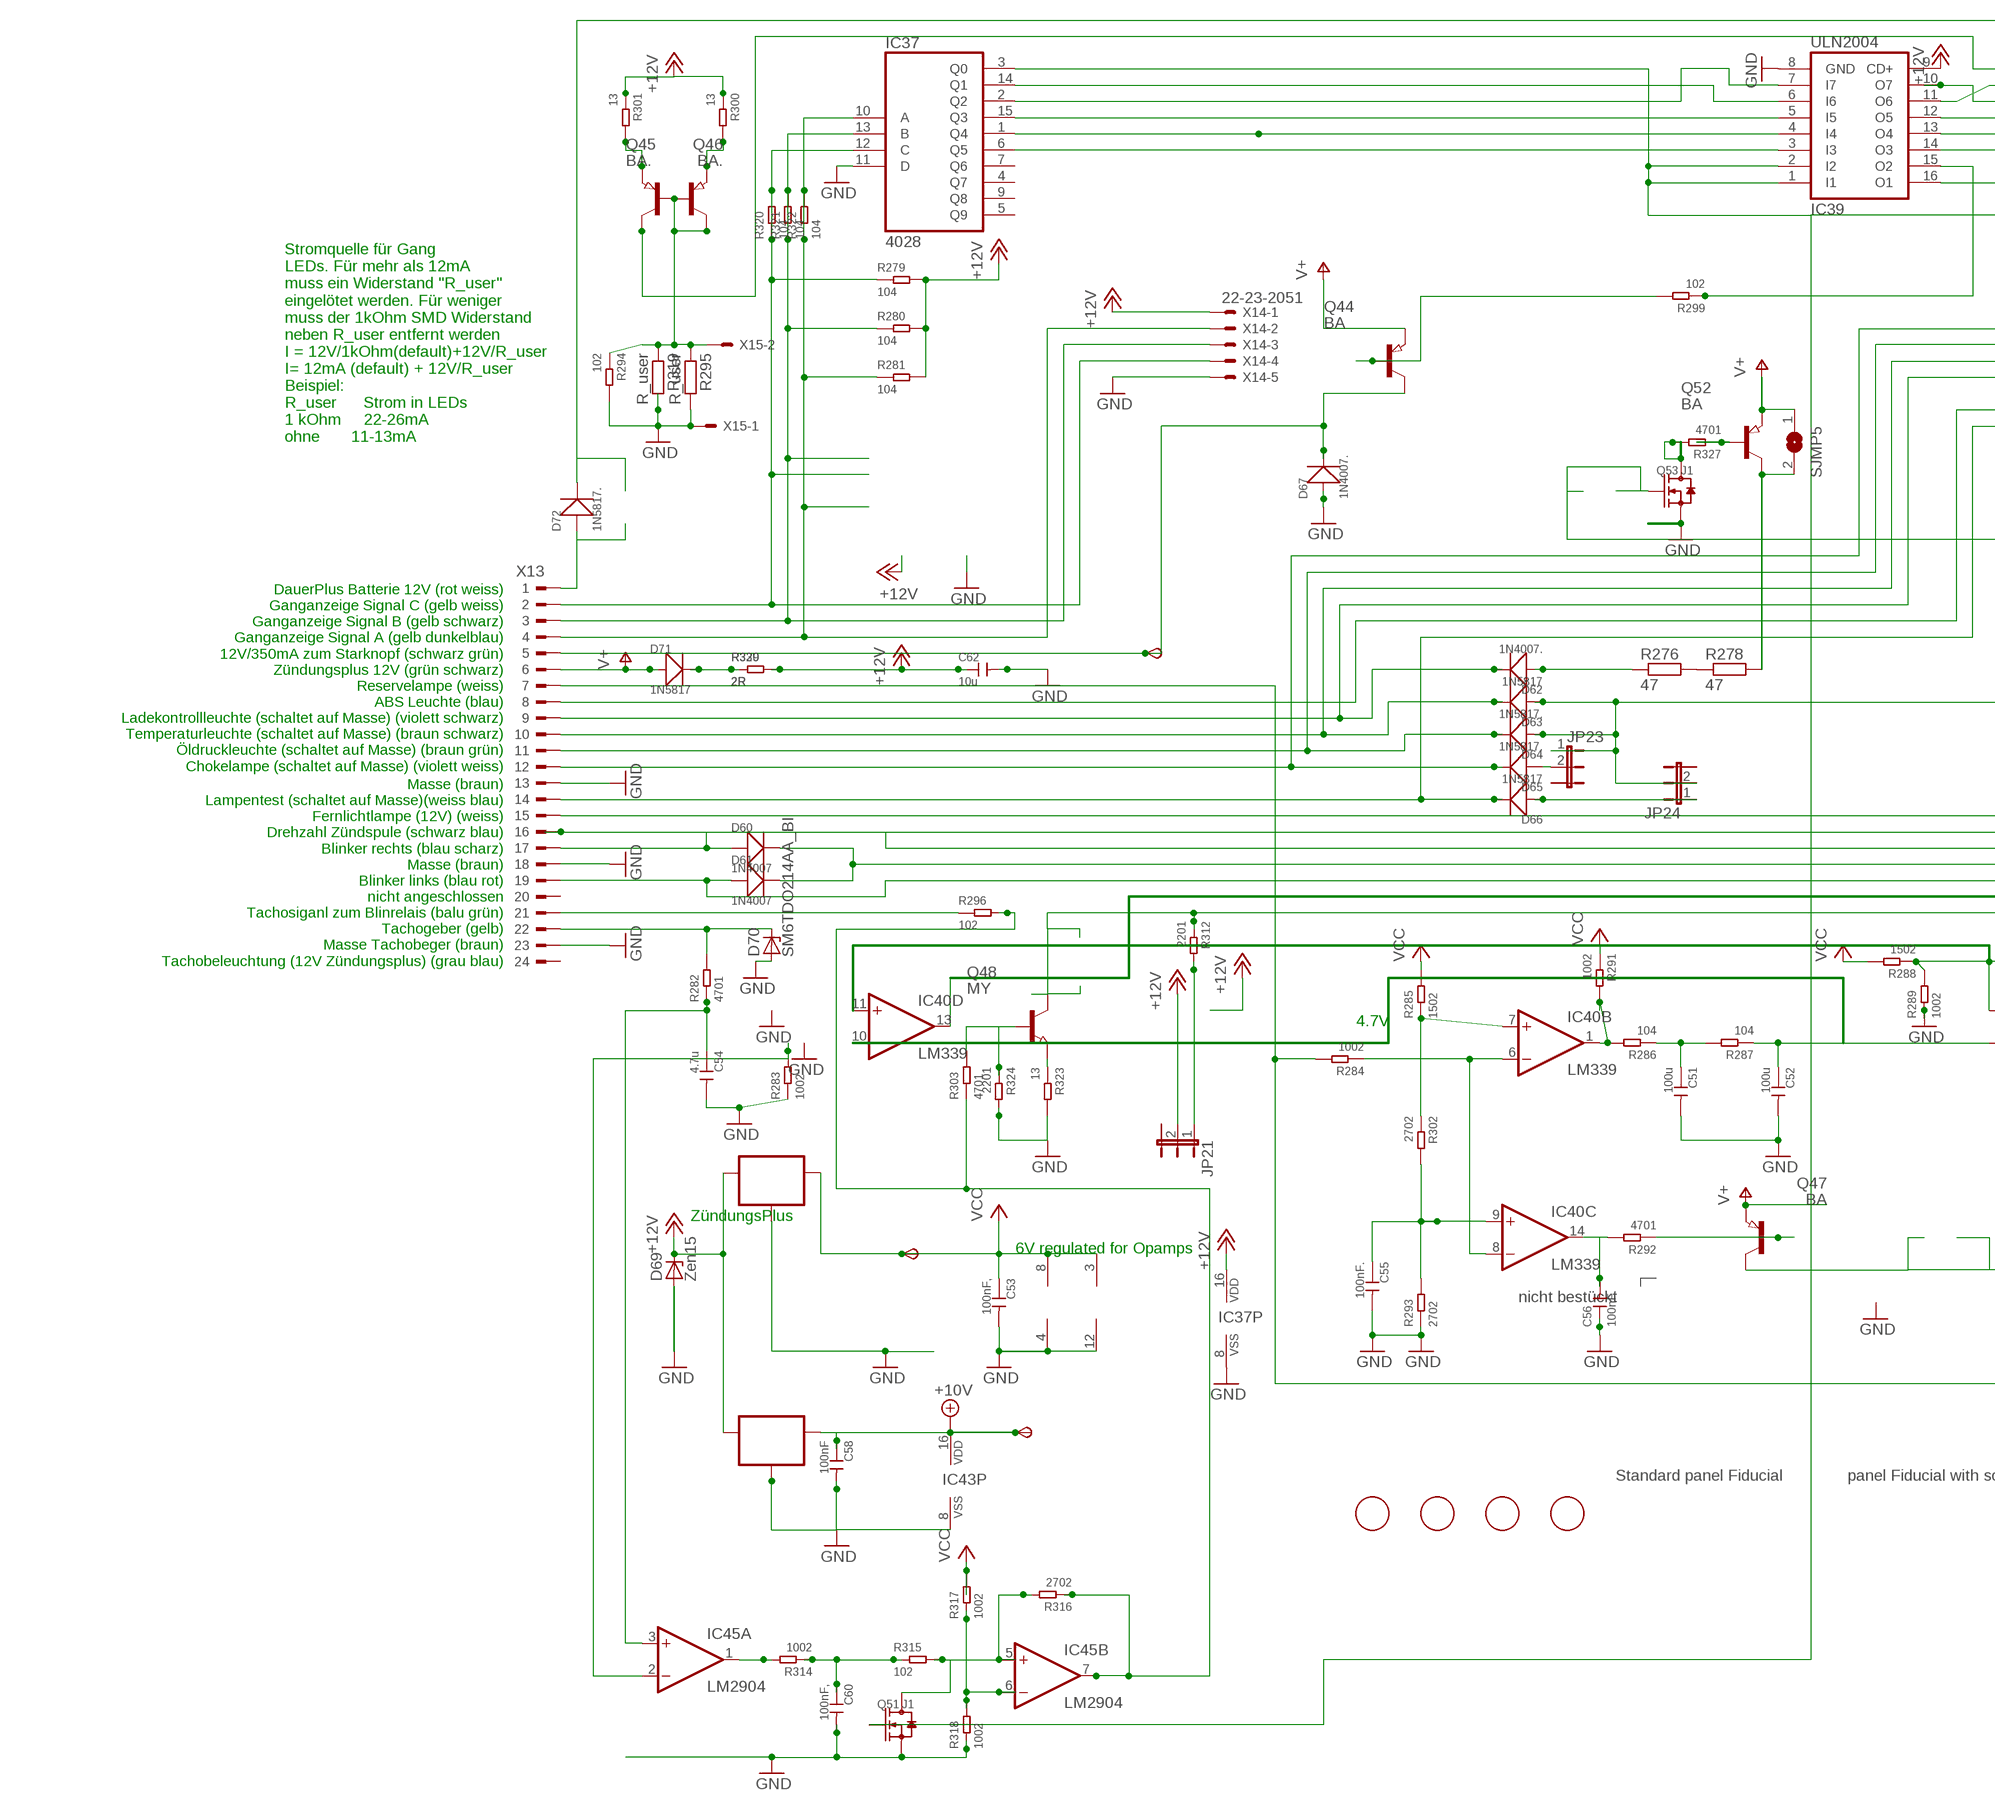
[diagram p11: schematic, sheet 7, part 1 of 2]
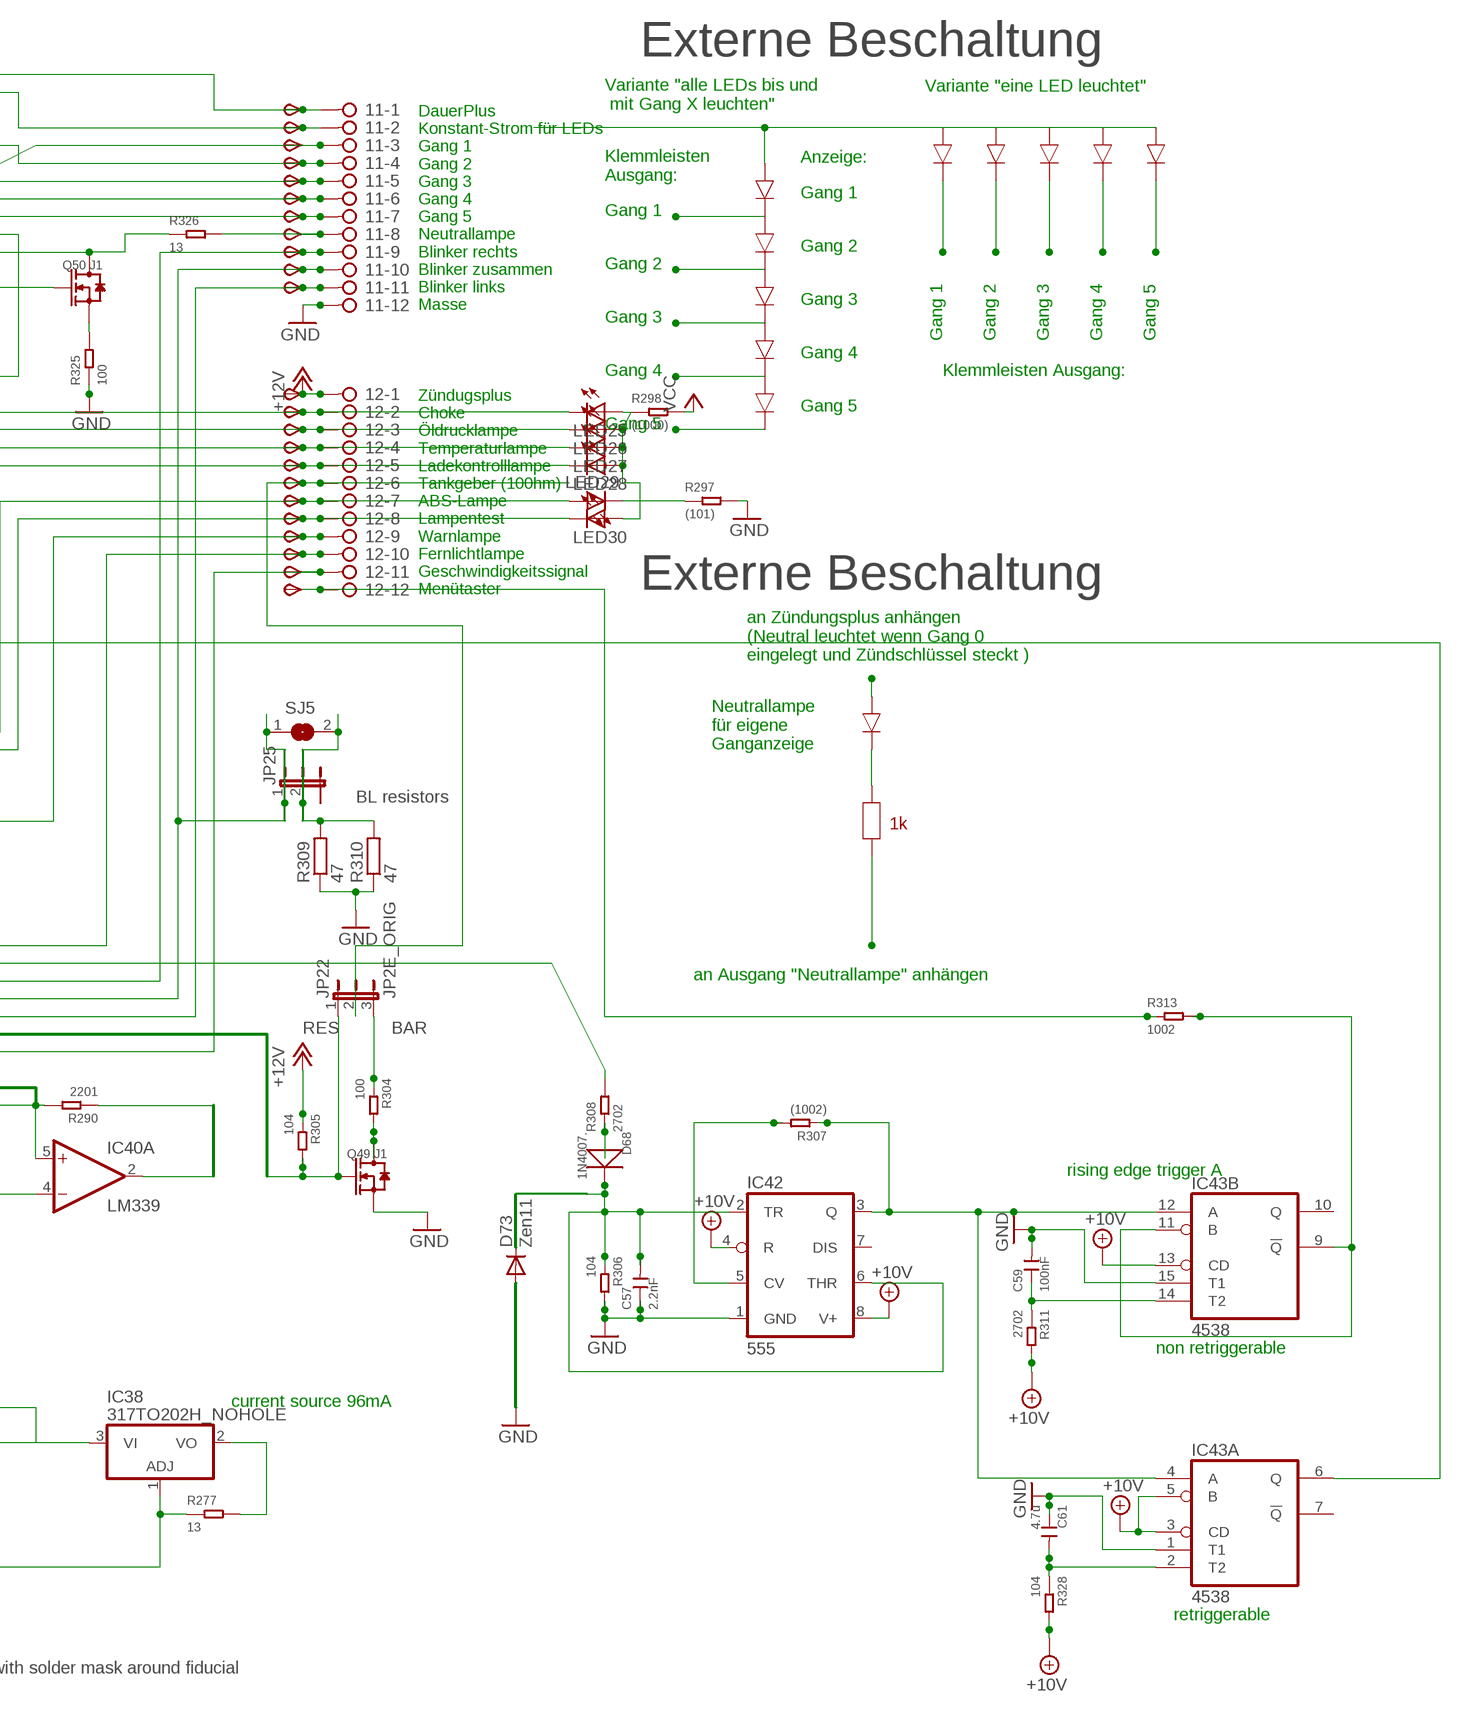
[diagram p12: schematic, sheet 7, part 2 of 2]

(export (version "E")
  (design (tool "Eeschema 10.0.6"))
  (components
    (comp (ref "5")
      (value "2081-1132")
      (footprint "eagle-import:12-PIN")
      (libsource (lib "eagle-import") (part "2081-1132"))
    )
    (comp (ref "6")
      (value "2081-1132")
      (footprint "eagle-import:12-PIN")
      (libsource (lib "eagle-import") (part "2081-1132"))
    )
    (comp (ref "6V2")
      (value "TPSB2.0")
      (footprint "eagle-import:B2.0")
      (libsource (lib "eagle-import") (part "TPSB2.0"))
    )
    (comp (ref "10V2")
      (value "TPSB2.0")
      (footprint "eagle-import:B2.0")
      (libsource (lib "eagle-import") (part "TPSB2.0"))
    )
    (comp (ref "C14")
      (value "100u")
      (footprint "eagle-import:C1206")
      (fields (field (name "MPN") "GRM31CR60J107ME39L"))
      (libsource (lib "eagle-import") (part "CERAMIC-100UF-6.3V-20%-X5R(1206)"))
    )
    (comp (ref "C16")
      (value "100u")
      (footprint "eagle-import:C1206")
      (fields (field (name "MPN") "GRM31CR60J107ME39L"))
      (libsource (lib "eagle-import") (part "CERAMIC-100UF-6.3V-20%-X5R(1206)"))
    )
    (comp (ref "C17")
      (value "100nF,")
      (footprint "eagle-import:C0805")
      (fields (field (name "MPN") "CC0805KRX7R9BB104"))
      (libsource (lib "eagle-import") (part "CERAMIC-100NF-50V-10%-X7R(0805)"))
    )
    (comp (ref "C18")
      (value "4.7u")
      (footprint "eagle-import:C0805")
      (fields (field (name "MPN") "CC0805KKX5R8BB475"))
      (libsource (lib "eagle-import") (part "CERAMIC-4.7UF-25V-10%-X5R(0805)"))
    )
    (comp (ref "C19")
      (value "100nF.")
      (footprint "eagle-import:C0805")
      (fields (field (name "MPN") "CC0805KRX7R9BB104"))
      (libsource (lib "eagle-import") (part "CERAMIC-100NF-50V-10%-X7R(0805)"))
    )
    (comp (ref "C20")
      (value "100nF.")
      (footprint "eagle-import:C0805")
      (fields (field (name "MPN") "CC0805KRX7R9BB104"))
      (libsource (lib "eagle-import") (part "CERAMIC-100NF-50V-10%-X7R(0805)"))
    )
    (comp (ref "C21")
      (value "2.2nF")
      (footprint "eagle-import:C0805")
      (fields (field (name "MPN") "CC0805KRX7R9BB104"))
      (libsource (lib "eagle-import") (part "CERAMIC-100NF-50V-10%-X7R(0805)"))
    )
    (comp (ref "C22")
      (value "100nF")
      (footprint "eagle-import:C0805")
      (fields (field (name "MPN") "CC0805KRX7R9BB104"))
      (libsource (lib "eagle-import") (part "CERAMIC-100NF-50V-10%-X7R(0805)"))
    )
    (comp (ref "C23")
      (value "100nF")
      (footprint "eagle-import:C0805")
      (fields (field (name "MPN") "CC0805KRX7R9BB104"))
      (libsource (lib "eagle-import") (part "CERAMIC-100NF-50V-10%-X7R(0805)"))
    )
    (comp (ref "C24")
      (value "100nF,")
      (footprint "eagle-import:C0805")
      (fields (field (name "MPN") "CC0805KRX7R9BB104"))
      (libsource (lib "eagle-import") (part "CERAMIC-100NF-50V-10%-X7R(0805)"))
    )
    (comp (ref "C25")
      (value "4.7u")
      (footprint "eagle-import:C0805")
      (fields (field (name "MPN") "CC0805KKX5R8BB475"))
      (libsource (lib "eagle-import") (part "CERAMIC-4.7UF-25V-10%-X5R(0805)"))
    )
    (comp (ref "C26")
      (value "10u")
      (footprint "eagle-import:C1206")
      (fields (field (name "MPN") "GRM31CR60J107ME39L"))
      (libsource (lib "eagle-import") (part "CERAMIC-100UF-6.3V-20%-X5R(1206)"))
    )
    (comp (ref "D18")
      (value "1N4007")
      (footprint "eagle-import:DO-214AC")
      (libsource (lib "eagle-import") (part "DIODE-GEN-PURPOSE-1KV-1A(DO-214AC)"))
    )
    (comp (ref "D19")
      (value "1N4007")
      (footprint "eagle-import:DO-214AC")
      (libsource (lib "eagle-import") (part "DIODE-GEN-PURPOSE-1KV-1A(DO-214AC)"))
    )
    (comp (ref "D20")
      (value "1N4007.")
      (footprint "eagle-import:DO-214AC")
      (fields (field (name "MPN") "1N4007"))
      (libsource (lib "eagle-import") (part "DIODE-GEN-PURPOSE-1KV-1A(DO-214AC)"))
    )
    (comp (ref "D21")
      (value "1N5817")
      (footprint "eagle-import:DO-214AC_SLIM")
      (libsource (lib "eagle-import") (part "DIODE-GEN-PURPOSE-1KV-1A(DO-214AC)DO-214AC/1206"))
    )
    (comp (ref "D22")
      (value "1N5817.")
      (footprint "eagle-import:DO-214AC_SLIM")
      (libsource (lib "eagle-import") (part "DIODE-GEN-PURPOSE-1KV-1A(DO-214AC)DO-214AC/1206"))
    )
    (comp (ref "D23")
      (value "1N5817.")
      (footprint "eagle-import:DO-214AC_SLIM")
      (libsource (lib "eagle-import") (part "DIODE-GEN-PURPOSE-1KV-1A(DO-214AC)DO-214AC/1206"))
    )
    (comp (ref "D24")
      (value "1N5817")
      (footprint "eagle-import:DO-214AC_SLIM")
      (libsource (lib "eagle-import") (part "DIODE-GEN-PURPOSE-1KV-1A(DO-214AC)DO-214AC/1206"))
    )
    (comp (ref "D25")
      (value "1N4007.")
      (footprint "eagle-import:DO-214AC")
      (fields (field (name "MPN") "1N4007"))
      (libsource (lib "eagle-import") (part "DIODE-GEN-PURPOSE-1KV-1A(DO-214AC)"))
    )
    (comp (ref "D26")
      (value "1N4007")
      (footprint "eagle-import:DO-214AC")
      (libsource (lib "eagle-import") (part "DIODE-GEN-PURPOSE-1KV-1A(DO-214AC)"))
    )
    (comp (ref "D27")
      (value "Zen15")
      (footprint "eagle-import:DO214AA")
      (libsource (lib "eagle-import") (part "SM6T"))
    )
    (comp (ref "D28")
      (value "SM6TDO214AA_BI")
      (footprint "eagle-import:DO214AA_BI")
      (libsource (lib "eagle-import") (part "SM6TDO214AA_BI"))
    )
    (comp (ref "D29")
      (value "1N5817")
      (footprint "eagle-import:DO-214AC_SLIM")
      (libsource (lib "eagle-import") (part "DIODE-GEN-PURPOSE-1KV-1A(DO-214AC)DO-214AC/1206"))
    )
    (comp (ref "D30")
      (value "1N5817.")
      (footprint "eagle-import:DO-214AC_SLIM")
      (libsource (lib "eagle-import") (part "DIODE-GEN-PURPOSE-1KV-1A(DO-214AC)DO-214AC/1206"))
    )
    (comp (ref "D31")
      (value "Zen11")
      (footprint "eagle-import:SOD-123_MINI-SMA")
      (libsource (lib "eagle-import") (part "CGRM400-G1"))
    )
    (comp (ref "FID7")
      (value "FIDUCIAL")
      (footprint "eagle-import:FIDUCIAL_1MM")
      (libsource (lib "eagle-import") (part "FIDUCIAL"))
    )
    (comp (ref "FID8")
      (value "FIDUCIAL")
      (footprint "eagle-import:FIDUCIAL_1MM")
      (libsource (lib "eagle-import") (part "FIDUCIAL"))
    )
    (comp (ref "FID9")
      (value "FIDUCIAL")
      (footprint "eagle-import:FIDUCIAL_1MM")
      (libsource (lib "eagle-import") (part "FIDUCIAL"))
    )
    (comp (ref "FID10")
      (value "FIDUCIAL")
      (footprint "eagle-import:FIDUCIAL_1MM")
      (libsource (lib "eagle-import") (part "FIDUCIAL"))
    )
    (comp (ref "IC10")
      (value "4028")
      (footprint "eagle-import:SO16")
      (libsource (lib "eagle-import") (part "4028D"))
    )
    (comp (ref "IC11")
      (value "317TO202H_NOHOLE")
      (footprint "eagle-import:TO220H_NOHOLE")
      (libsource (lib "eagle-import") (part "317TO202H_NOHOLE"))
    )
    (comp (ref "IC12")
      (value "ULN2004")
      (footprint "eagle-import:SO16")
      (libsource (lib "eagle-import") (part "ULN2004AD"))
    )
    (comp (ref "IC13")
      (value "LM339")
      (footprint "eagle-import:SO14")
      (libsource (lib "eagle-import") (part "LM339D"))
    )
    (comp (ref "IC14")
      (value "78L06")
      (footprint "eagle-import:SOT89_ROUND")
      (libsource (lib "eagle-import") (part "78LXXSOT89_ROUND"))
    )
    (comp (ref "IC15")
      (value "555")
      (footprint "eagle-import:SO08")
      (libsource (lib "eagle-import") (part "555DNE"))
    )
    (comp (ref "IC16")
      (value "4538")
      (footprint "eagle-import:SO16")
      (libsource (lib "eagle-import") (part "4538D"))
    )
    (comp (ref "IC17")
      (value "78L10")
      (footprint "eagle-import:SOT89_ROUND")
      (libsource (lib "eagle-import") (part "78LXXSOT89_ROUND"))
    )
    (comp (ref "IC18")
      (value "LM2904")
      (footprint "eagle-import:SO08")
      (libsource (lib "eagle-import") (part "LM358D"))
    )
    (comp (ref "JP6")
      (value "JP2EJP2_SMALLPADS")
      (footprint "eagle-import:JP2_SMALLPADS")
      (libsource (lib "eagle-import") (part "JP2EJP2_SMALLPADS"))
    )
    (comp (ref "JP7")
      (value "JP2E_ORIG")
      (footprint "eagle-import:JP2_ORIG_SMALLPADS")
      (libsource (lib "eagle-import") (part "JP2E_ORIG"))
    )
    (comp (ref "JP8")
      (value "JP2EJP2_SMALLPADS")
      (footprint "eagle-import:JP2_SMALLPADS")
      (libsource (lib "eagle-import") (part "JP2EJP2_SMALLPADS"))
    )
    (comp (ref "JP9")
      (value "JP2EJP2_SMALLPADS")
      (footprint "eagle-import:JP2_SMALLPADS")
      (libsource (lib "eagle-import") (part "JP2EJP2_SMALLPADS"))
    )
    (comp (ref "JP10")
      (value "JP2EJP2_SMALLPADS")
      (footprint "eagle-import:JP2_SMALLPADS")
      (libsource (lib "eagle-import") (part "JP2EJP2_SMALLPADS"))
    )
    (comp (ref "LED7")
      (value "LEDLD260")
      (footprint "eagle-import:LD260")
      (libsource (lib "eagle-import") (part "LEDLD260"))
    )
    (comp (ref "LED8")
      (value "LEDLD260")
      (footprint "eagle-import:LD260")
      (libsource (lib "eagle-import") (part "LEDLD260"))
    )
    (comp (ref "LED9")
      (value "LEDLD260")
      (footprint "eagle-import:LD260")
      (libsource (lib "eagle-import") (part "LEDLD260"))
    )
    (comp (ref "LED10")
      (value "LEDLD260")
      (footprint "eagle-import:LD260")
      (libsource (lib "eagle-import") (part "LEDLD260"))
    )
    (comp (ref "LED11")
      (value "LEDLD260")
      (footprint "eagle-import:LD260")
      (libsource (lib "eagle-import") (part "LEDLD260"))
    )
    (comp (ref "LED12")
      (value "LEDLD260")
      (footprint "eagle-import:LD260")
      (libsource (lib "eagle-import") (part "LEDLD260"))
    )
    (comp (ref "Q14")
      (value "BA")
      (footprint "eagle-import:SOT89")
      (libsource (lib "eagle-import") (part "PNP-TRANSISTOR_SOT89"))
    )
    (comp (ref "Q15")
      (value "BA.")
      (footprint "eagle-import:SOT89")
      (libsource (lib "eagle-import") (part "PNP-TRANSISTOR_SOT89"))
    )
    (comp (ref "Q16")
      (value "BA.")
      (footprint "eagle-import:SOT89")
      (libsource (lib "eagle-import") (part "PNP-TRANSISTOR_SOT89"))
    )
    (comp (ref "Q17")
      (value "BA")
      (footprint "eagle-import:SOT89")
      (libsource (lib "eagle-import") (part "PNP-TRANSISTOR_SOT89"))
    )
    (comp (ref "Q18")
      (value "MY")
      (footprint "eagle-import:SOT89")
      (libsource (lib "eagle-import") (part "NPN-TRANSISTOR_SOT89"))
    )
    (comp (ref "Q19")
      (value "J1")
      (footprint "eagle-import:SOT-23")
      (fields (field (name "MPN") "BSS138W-7-F"))
      (libsource (lib "eagle-import") (part "SMD-MOSFET-N-CH-50V-200MA-BSS138W-7-F(SOT-23)"))
    )
    (comp (ref "Q20")
      (value "J1")
      (footprint "eagle-import:SOT-23")
      (fields (field (name "MPN") "BSS138W-7-F"))
      (libsource (lib "eagle-import") (part "SMD-MOSFET-N-CH-50V-200MA-BSS138W-7-F(SOT-23)"))
    )
    (comp (ref "Q21")
      (value "J1")
      (footprint "eagle-import:SOT-23")
      (fields (field (name "MPN") "BSS138W-7-F"))
      (libsource (lib "eagle-import") (part "SMD-MOSFET-N-CH-50V-200MA-BSS138W-7-F(SOT-23)"))
    )
    (comp (ref "Q22")
      (value "BA")
      (footprint "eagle-import:SOT89")
      (libsource (lib "eagle-import") (part "PNP-TRANSISTOR_SOT89"))
    )
    (comp (ref "Q23")
      (value "J1")
      (footprint "eagle-import:SOT-23")
      (fields (field (name "MPN") "BSS138W-7-F"))
      (libsource (lib "eagle-import") (part "SMD-MOSFET-N-CH-50V-200MA-BSS138W-7-F(SOT-23)"))
    )
    (comp (ref "R67")
      (value "47")
      (footprint "eagle-import:V235_17_1MM")
      (libsource (lib "eagle-import") (part "R-EU_V235/17_1MM"))
    )
    (comp (ref "R68")
      (value "13")
      (footprint "eagle-import:R1206")
      (fields (field (name "MPN") "RC1206JR-0713RL"))
      (libsource (lib "eagle-import") (part "SMD-RES-13R-5%-1/4W(1206)"))
    )
    (comp (ref "R69")
      (value "47")
      (footprint "eagle-import:V235_17_1MM")
      (libsource (lib "eagle-import") (part "R-EU_V235/17_1MM"))
    )
    (comp (ref "R70")
      (value "104")
      (footprint "eagle-import:R0805")
      (fields (field (name "MPN") "RC0805FR-0710KL"))
      (libsource (lib "eagle-import") (part "SMD-RES-10K-1%-1/8W(0805)"))
    )
    (comp (ref "R71")
      (value "104")
      (footprint "eagle-import:R0805")
      (fields (field (name "MPN") "RC0805FR-0710KL"))
      (libsource (lib "eagle-import") (part "SMD-RES-10K-1%-1/8W(0805)"))
    )
    (comp (ref "R72")
      (value "104")
      (footprint "eagle-import:R0805")
      (fields (field (name "MPN") "RC0805FR-0710KL"))
      (libsource (lib "eagle-import") (part "SMD-RES-10K-1%-1/8W(0805)"))
    )
    (comp (ref "R73")
      (value "4701")
      (footprint "eagle-import:R0805")
      (fields (field (name "MPN") "RC0805JR-074K7L"))
      (libsource (lib "eagle-import") (part "SMD-RES-4.7K-5%-1/8W(0805)"))
    )
    (comp (ref "R74")
      (value "1002")
      (footprint "eagle-import:R0805")
      (fields (field (name "MPN") "RC0805FR-0710KL"))
      (libsource (lib "eagle-import") (part "SMD-RES-10K-1%-1/8W(0805)"))
    )
    (comp (ref "R75")
      (value "1002")
      (footprint "eagle-import:R0805")
      (fields (field (name "MPN") "RC0805FR-0710KL"))
      (libsource (lib "eagle-import") (part "SMD-RES-10K-1%-1/8W(0805)"))
    )
    (comp (ref "R76")
      (value "1502")
      (footprint "eagle-import:R0805")
      (fields (field (name "MPN") "RC0805FR-0710KL"))
      (libsource (lib "eagle-import") (part "SMD-RES-10K-1%-1/8W(0805)"))
    )
    (comp (ref "R77")
      (value "104")
      (footprint "eagle-import:R0805")
      (fields (field (name "MPN") "RC0805FR-0710KL"))
      (libsource (lib "eagle-import") (part "SMD-RES-10K-1%-1/8W(0805)"))
    )
    (comp (ref "R78")
      (value "104")
      (footprint "eagle-import:R0805")
      (fields (field (name "MPN") "RC0805FR-0710KL"))
      (libsource (lib "eagle-import") (part "SMD-RES-10K-1%-1/8W(0805)"))
    )
    (comp (ref "R79")
      (value "1502")
      (footprint "eagle-import:R0805")
      (fields (field (name "MPN") "RC0805FR-0710KL"))
      (libsource (lib "eagle-import") (part "SMD-RES-10K-1%-1/8W(0805)"))
    )
    (comp (ref "R80")
      (value "1002")
      (footprint "eagle-import:R0805")
      (fields (field (name "MPN") "RC0805FR-0710KL"))
      (libsource (lib "eagle-import") (part "SMD-RES-10K-1%-1/8W(0805)"))
    )
    (comp (ref "R81")
      (value "2201")
      (footprint "eagle-import:R0805")
      (fields (field (name "MPN") "RC0805JR-072K2L"))
      (libsource (lib "eagle-import") (part "SMD-RES-2.2K-5%-1/8W(0805)"))
    )
    (comp (ref "R82")
      (value "1002")
      (footprint "eagle-import:R0805")
      (fields (field (name "MPN") "RC0805FR-0710KL"))
      (libsource (lib "eagle-import") (part "SMD-RES-10K-1%-1/8W(0805)"))
    )
    (comp (ref "R83")
      (value "4701")
      (footprint "eagle-import:R0805")
      (fields (field (name "MPN") "RC0805JR-074K7L"))
      (libsource (lib "eagle-import") (part "SMD-RES-4.7K-5%-1/8W(0805)"))
    )
    (comp (ref "R84")
      (value "2702")
      (footprint "eagle-import:R0805")
      (fields (field (name "MPN") "RC0805JR-074K7L"))
      (libsource (lib "eagle-import") (part "SMD-RES-4.7K-5%-1/8W(0805)"))
    )
    (comp (ref "R85")
      (value "102")
      (footprint "eagle-import:R0805")
      (fields (field (name "MPN") "RC0805JR-071KL"))
      (libsource (lib "eagle-import") (part "SMD-RES-1K-5%-1/8W(0805)"))
    )
    (comp (ref "R86")
      (value "R_user")
      (footprint "eagle-import:R0805")
      (libsource (lib "eagle-import") (part "R-EU_R0805"))
    )
    (comp (ref "R87")
      (value "102")
      (footprint "eagle-import:R0805")
      (fields (field (name "MPN") "RC0805JR-07220RL"))
      (libsource (lib "eagle-import") (part "SMD-RES-220R-5%-1/8W(0805)"))
    )
    (comp (ref "R88")
      (value "(101)")
      (footprint "eagle-import:R0805")
      (fields (field (name "MPN") "RC0805JR-07100RL"))
      (libsource (lib "eagle-import") (part "SMD-RES-100R-5%-1/8W(0805)"))
    )
    (comp (ref "R89")
      (value "(1000)")
      (footprint "eagle-import:R0805")
      (fields (field (name "MPN") "RC0805JR-07100RL"))
      (libsource (lib "eagle-import") (part "SMD-RES-100R-5%-1/8W(0805)"))
    )
    (comp (ref "R90")
      (value "102")
      (footprint "eagle-import:R0805")
      (fields (field (name "MPN") "RC0805JR-071KL"))
      (libsource (lib "eagle-import") (part "SMD-RES-1K-5%-1/8W(0805)"))
    )
    (comp (ref "R91")
      (value "13")
      (footprint "eagle-import:R1206")
      (fields (field (name "MPN") "RC1206JR-0713RL"))
      (libsource (lib "eagle-import") (part "SMD-RES-13R-5%-1/4W(1206)"))
    )
    (comp (ref "R92")
      (value "13")
      (footprint "eagle-import:R1206")
      (fields (field (name "MPN") "RC1206JR-0713RL"))
      (libsource (lib "eagle-import") (part "SMD-RES-13R-5%-1/4W(1206)"))
    )
    (comp (ref "R93")
      (value "2702")
      (footprint "eagle-import:R0805")
      (fields (field (name "MPN") "RC0805JR-074K7L"))
      (libsource (lib "eagle-import") (part "SMD-RES-4.7K-5%-1/8W(0805)"))
    )
    (comp (ref "R94")
      (value "4701")
      (footprint "eagle-import:R0805")
      (fields (field (name "MPN") "RC0805JR-074K7L"))
      (libsource (lib "eagle-import") (part "SMD-RES-4.7K-5%-1/8W(0805)"))
    )
    (comp (ref "R95")
      (value "100")
      (footprint "eagle-import:R0805")
      (fields (field (name "MPN") "RC0805JR-072K2L"))
      (libsource (lib "eagle-import") (part "SMD-RES-2.2K-5%-1/8W(0805)"))
    )
    (comp (ref "R96")
      (value "104")
      (footprint "eagle-import:R0805")
      (fields (field (name "MPN") "RC0805FR-0710KL"))
      (libsource (lib "eagle-import") (part "SMD-RES-10K-1%-1/8W(0805)"))
    )
    (comp (ref "R97")
      (value "104")
      (footprint "eagle-import:R0805")
      (fields (field (name "MPN") "RC0805FR-0710KL"))
      (libsource (lib "eagle-import") (part "SMD-RES-10K-1%-1/8W(0805)"))
    )
    (comp (ref "R98")
      (value "(1002)")
      (footprint "eagle-import:R0805")
      (fields (field (name "MPN") "RC0805FR-0710KL"))
      (libsource (lib "eagle-import") (part "SMD-RES-10K-1%-1/8W(0805)"))
    )
    (comp (ref "R99")
      (value "2702")
      (footprint "eagle-import:R0805")
      (fields (field (name "MPN") "RC0805FR-0710KL"))
      (libsource (lib "eagle-import") (part "SMD-RES-10K-1%-1/8W(0805)"))
    )
    (comp (ref "R100")
      (value "47")
      (footprint "eagle-import:V235_17_1MM")
      (libsource (lib "eagle-import") (part "R-EU_V235/17_1MM"))
    )
    (comp (ref "R118")
      (value "47")
      (footprint "eagle-import:V235_17_1MM")
      (libsource (lib "eagle-import") (part "R-EU_V235/17_1MM"))
    )
    (comp (ref "R139")
      (value "2702")
      (footprint "eagle-import:R0805")
      (fields (field (name "MPN") "RC0805JR-074K7L"))
      (libsource (lib "eagle-import") (part "SMD-RES-4.7K-5%-1/8W(0805)"))
    )
    (comp (ref "R147")
      (value "2201")
      (footprint "eagle-import:R0805")
      (fields (field (name "MPN") "RC0805JR-072K2L"))
      (libsource (lib "eagle-import") (part "SMD-RES-2.2K-5%-1/8W(0805)"))
    )
    (comp (ref "R148")
      (value "1002")
      (footprint "eagle-import:R0805")
      (fields (field (name "MPN") "RC0805JR-074K7L"))
      (libsource (lib "eagle-import") (part "SMD-RES-4.7K-5%-1/8W(0805)"))
    )
    (comp (ref "R149")
      (value "1002")
      (footprint "eagle-import:R0805")
      (fields (field (name "MPN") "RC0805FR-0710KL"))
      (libsource (lib "eagle-import") (part "SMD-RES-10K-1%-1/8W(0805)"))
    )
    (comp (ref "R150")
      (value "102")
      (footprint "eagle-import:R0805")
      (fields (field (name "MPN") "RC0805JR-071KL"))
      (libsource (lib "eagle-import") (part "SMD-RES-1K-5%-1/8W(0805)"))
    )
    (comp (ref "R151")
      (value "2702")
      (footprint "eagle-import:R0805")
      (fields (field (name "MPN") "RC0805JR-074K7L"))
      (libsource (lib "eagle-import") (part "SMD-RES-4.7K-5%-1/8W(0805)"))
    )
    (comp (ref "R152")
      (value "1002")
      (footprint "eagle-import:R0805")
      (fields (field (name "MPN") "RC0805JR-071KL"))
      (libsource (lib "eagle-import") (part "SMD-RES-1K-5%-1/8W(0805)"))
    )
    (comp (ref "R153")
      (value "1002")
      (footprint "eagle-import:R0805")
      (fields (field (name "MPN") "RC0805JR-071KL"))
      (libsource (lib "eagle-import") (part "SMD-RES-1K-5%-1/8W(0805)"))
    )
    (comp (ref "R154")
      (value "R_user")
      (footprint "eagle-import:R0805")
      (libsource (lib "eagle-import") (part "R-EU_R0805"))
    )
    (comp (ref "R155")
      (value "104")
      (footprint "eagle-import:R0805")
      (fields (field (name "MPN") "RC0805FR-0710KL"))
      (libsource (lib "eagle-import") (part "SMD-RES-10K-1%-1/8W(0805)"))
    )
    (comp (ref "R156")
      (value "104")
      (footprint "eagle-import:R0805")
      (fields (field (name "MPN") "RC0805FR-0710KL"))
      (libsource (lib "eagle-import") (part "SMD-RES-10K-1%-1/8W(0805)"))
    )
    (comp (ref "R157")
      (value "104")
      (footprint "eagle-import:R0805")
      (fields (field (name "MPN") "RC0805FR-0710KL"))
      (libsource (lib "eagle-import") (part "SMD-RES-10K-1%-1/8W(0805)"))
    )
    (comp (ref "R158")
      (value "13")
      (footprint "eagle-import:R1206")
      (fields (field (name "MPN") "RC1206JR-0713RL"))
      (libsource (lib "eagle-import") (part "SMD-RES-13R-5%-1/4W(1206)"))
    )
    (comp (ref "R159")
      (value "2201")
      (footprint "eagle-import:R0805")
      (fields (field (name "MPN") "RC0805JR-071KL"))
      (libsource (lib "eagle-import") (part "SMD-RES-1K-5%-1/8W(0805)"))
    )
    (comp (ref "R160")
      (value "100")
      (footprint "eagle-import:R0805")
      (fields (field (name "MPN") "RC0805JR-07220RL"))
      (libsource (lib "eagle-import") (part "SMD-RES-220R-5%-1/8W(0805)"))
    )
    (comp (ref "R161")
      (value "13")
      (footprint "eagle-import:R1206")
      (fields (field (name "MPN") "RC1206JR-0713RL"))
      (libsource (lib "eagle-import") (part "SMD-RES-13R-5%-1/4W(1206)"))
    )
    (comp (ref "R162")
      (value "4701")
      (footprint "eagle-import:R0805")
      (fields (field (name "MPN") "RC0805JR-074K7L"))
      (libsource (lib "eagle-import") (part "SMD-RES-4.7K-5%-1/8W(0805)"))
    )
    (comp (ref "R163")
      (value "104")
      (footprint "eagle-import:R0805")
      (fields (field (name "MPN") "RC0805JR-074K7L"))
      (libsource (lib "eagle-import") (part "SMD-RES-4.7K-5%-1/8W(0805)"))
    )
    (comp (ref "R164")
      (value "2R")
      (footprint "eagle-import:R0805")
      (fields (field (name "MPN") "RC0805JR-072K2L"))
      (libsource (lib "eagle-import") (part "SMD-RES-2.2K-5%-1/8W(0805)"))
    )
    (comp (ref "R165")
      (value "2R")
      (footprint "eagle-import:R0805")
      (fields (field (name "MPN") "RC0805JR-072K2L"))
      (libsource (lib "eagle-import") (part "SMD-RES-2.2K-5%-1/8W(0805)"))
    )
    (comp (ref "SJ2")
      (value "SJ")
      (footprint "eagle-import:SJ")
      (libsource (lib "eagle-import") (part "solder-jumper_SJ"))
    )
    (comp (ref "SJMP2")
      (value "SJ")
      (footprint "eagle-import:SJ")
      (libsource (lib "eagle-import") (part "SJ"))
    )
    (comp (ref "START2")
      (value "TPSB2.0")
      (footprint "eagle-import:B2.0")
      (libsource (lib "eagle-import") (part "TPSB2.0"))
    )
    (comp (ref "TP47")
      (value "TPSB2.0")
      (footprint "eagle-import:B2.0")
      (libsource (lib "eagle-import") (part "TPSB2.0"))
    )
    (comp (ref "TP48")
      (value "TPSB2.0")
      (footprint "eagle-import:B2.0")
      (libsource (lib "eagle-import") (part "TPSB2.0"))
    )
    (comp (ref "TP49")
      (value "TPSB2.0")
      (footprint "eagle-import:B2.0")
      (libsource (lib "eagle-import") (part "TPSB2.0"))
    )
    (comp (ref "TP50")
      (value "TPSB2.0")
      (footprint "eagle-import:B2.0")
      (libsource (lib "eagle-import") (part "TPSB2.0"))
    )
    (comp (ref "TP51")
      (value "TPSB2.0")
      (footprint "eagle-import:B2.0")
      (libsource (lib "eagle-import") (part "TPSB2.0"))
    )
    (comp (ref "TP52")
      (value "TPSB2.0")
      (footprint "eagle-import:B2.0")
      (libsource (lib "eagle-import") (part "TPSB2.0"))
    )
    (comp (ref "TP53")
      (value "TPSB2.0")
      (footprint "eagle-import:B2.0")
      (libsource (lib "eagle-import") (part "TPSB2.0"))
    )
    (comp (ref "TP54")
      (value "TPSB2.0")
      (footprint "eagle-import:B2.0")
      (libsource (lib "eagle-import") (part "TPSB2.0"))
    )
    (comp (ref "TP55")
      (value "TPSB2.0")
      (footprint "eagle-import:B2.0")
      (libsource (lib "eagle-import") (part "TPSB2.0"))
    )
    (comp (ref "TP56")
      (value "TPSB2.0")
      (footprint "eagle-import:B2.0")
      (libsource (lib "eagle-import") (part "TPSB2.0"))
    )
    (comp (ref "TP57")
      (value "TPSB2.0")
      (footprint "eagle-import:B2.0")
      (libsource (lib "eagle-import") (part "TPSB2.0"))
    )
    (comp (ref "TP58")
      (value "TPSB2.0")
      (footprint "eagle-import:B2.0")
      (libsource (lib "eagle-import") (part "TPSB2.0"))
    )
    (comp (ref "TP59")
      (value "TPSB2.0")
      (footprint "eagle-import:B2.0")
      (libsource (lib "eagle-import") (part "TPSB2.0"))
    )
    (comp (ref "TP60")
      (value "TPSB2.0")
      (footprint "eagle-import:B2.0")
      (libsource (lib "eagle-import") (part "TPSB2.0"))
    )
    (comp (ref "TP61")
      (value "TPSB2.0")
      (footprint "eagle-import:B2.0")
      (libsource (lib "eagle-import") (part "TPSB2.0"))
    )
    (comp (ref "TP62")
      (value "TPSB2.0")
      (footprint "eagle-import:B2.0")
      (libsource (lib "eagle-import") (part "TPSB2.0"))
    )
    (comp (ref "TP63")
      (value "TPSB2.0")
      (footprint "eagle-import:B2.0")
      (libsource (lib "eagle-import") (part "TPSB2.0"))
    )
    (comp (ref "TP64")
      (value "TPSB2.0")
      (footprint "eagle-import:B2.0")
      (libsource (lib "eagle-import") (part "TPSB2.0"))
    )
    (comp (ref "TP65")
      (value "TPSB1,27")
      (footprint "eagle-import:B1,27")
      (libsource (lib "eagle-import") (part "TPSB1,27"))
    )
    (comp (ref "TP66")
      (value "TPSB2.0")
      (footprint "eagle-import:B2.0")
      (libsource (lib "eagle-import") (part "TPSB2.0"))
    )
    (comp (ref "TP67")
      (value "TPSB2.0")
      (footprint "eagle-import:B2.0")
      (libsource (lib "eagle-import") (part "TPSB2.0"))
    )
    (comp (ref "TP68")
      (value "TPSB2.0")
      (footprint "eagle-import:B2.0")
      (libsource (lib "eagle-import") (part "TPSB2.0"))
    )
    (comp (ref "TP69")
      (value "TPSB2.0")
      (footprint "eagle-import:B2.0")
      (libsource (lib "eagle-import") (part "TPSB2.0"))
    )
    (comp (ref "X4")
      (value "CON_BMWV2")
      (footprint "eagle-import:24-PIN_V2")
      (libsource (lib "eagle-import") (part "CON_BMWV2"))
    )
    (comp (ref "X5")
      (value "22-23-2051")
      (footprint "eagle-import:22-23-2051")
      (fields (field (name "MF") "MOLEX"))
      (libsource (lib "eagle-import") (part "22-23-2051"))
    )
    (comp (ref "X6")
      (value "22-23-2021")
      (footprint "eagle-import:22-23-2021")
      (fields (field (name "MF") "MOLEX"))
      (libsource (lib "eagle-import") (part "22-23-2021"))
    )
    (comp (ref "6V3")
      (value "TPSB2.0")
      (footprint "eagle-import:B2.0")
      (libsource (lib "eagle-import") (part "TPSB2.0"))
    )
    (comp (ref "7")
      (value "2081-1132")
      (footprint "eagle-import:12-PIN")
      (libsource (lib "eagle-import") (part "2081-1132"))
    )
    (comp (ref "8")
      (value "2081-1132")
      (footprint "eagle-import:12-PIN")
      (libsource (lib "eagle-import") (part "2081-1132"))
    )
    (comp (ref "10V3")
      (value "TPSB2.0")
      (footprint "eagle-import:B2.0")
      (libsource (lib "eagle-import") (part "TPSB2.0"))
    )
    (comp (ref "C27")
      (value "100u")
      (footprint "eagle-import:C1206")
      (fields (field (name "MPN") "GRM31CR60J107ME39L"))
      (libsource (lib "eagle-import") (part "CERAMIC-100UF-6.3V-20%-X5R(1206)"))
    )
    (comp (ref "C28")
      (value "100u")
      (footprint "eagle-import:C1206")
      (fields (field (name "MPN") "GRM31CR60J107ME39L"))
      (libsource (lib "eagle-import") (part "CERAMIC-100UF-6.3V-20%-X5R(1206)"))
    )
    (comp (ref "C29")
      (value "100nF,")
      (footprint "eagle-import:C0805")
      (fields (field (name "MPN") "CC0805KRX7R9BB104"))
      (libsource (lib "eagle-import") (part "CERAMIC-100NF-50V-10%-X7R(0805)"))
    )
    (comp (ref "C30")
      (value "4.7u")
      (footprint "eagle-import:C0805")
      (fields (field (name "MPN") "CC0805KKX5R8BB475"))
      (libsource (lib "eagle-import") (part "CERAMIC-4.7UF-25V-10%-X5R(0805)"))
    )
    (comp (ref "C31")
      (value "100nF.")
      (footprint "eagle-import:C0805")
      (fields (field (name "MPN") "CC0805KRX7R9BB104"))
      (libsource (lib "eagle-import") (part "CERAMIC-100NF-50V-10%-X7R(0805)"))
    )
    (comp (ref "C32")
      (value "100nF.")
      (footprint "eagle-import:C0805")
      (fields (field (name "MPN") "CC0805KRX7R9BB104"))
      (libsource (lib "eagle-import") (part "CERAMIC-100NF-50V-10%-X7R(0805)"))
    )
    (comp (ref "C33")
      (value "2.2nF")
      (footprint "eagle-import:C0805")
      (fields (field (name "MPN") "CC0805KRX7R9BB104"))
      (libsource (lib "eagle-import") (part "CERAMIC-100NF-50V-10%-X7R(0805)"))
    )
    (comp (ref "C34")
      (value "100nF")
      (footprint "eagle-import:C0805")
      (fields (field (name "MPN") "CC0805KRX7R9BB104"))
      (libsource (lib "eagle-import") (part "CERAMIC-100NF-50V-10%-X7R(0805)"))
    )
    (comp (ref "C35")
      (value "100nF")
      (footprint "eagle-import:C0805")
      (fields (field (name "MPN") "CC0805KRX7R9BB104"))
      (libsource (lib "eagle-import") (part "CERAMIC-100NF-50V-10%-X7R(0805)"))
    )
    (comp (ref "C36")
      (value "100nF,")
      (footprint "eagle-import:C0805")
      (fields (field (name "MPN") "CC0805KRX7R9BB104"))
      (libsource (lib "eagle-import") (part "CERAMIC-100NF-50V-10%-X7R(0805)"))
    )
    (comp (ref "C37")
      (value "4.7u")
      (footprint "eagle-import:C0805")
      (fields (field (name "MPN") "CC0805KKX5R8BB475"))
      (libsource (lib "eagle-import") (part "CERAMIC-4.7UF-25V-10%-X5R(0805)"))
    )
    (comp (ref "C38")
      (value "10u")
      (footprint "eagle-import:C1206")
      (fields (field (name "MPN") "GRM31CR60J107ME39L"))
      (libsource (lib "eagle-import") (part "CERAMIC-100UF-6.3V-20%-X5R(1206)"))
    )
    (comp (ref "D32")
      (value "1N4007")
      (footprint "eagle-import:DO-214AC")
      (libsource (lib "eagle-import") (part "DIODE-GEN-PURPOSE-1KV-1A(DO-214AC)"))
    )
    (comp (ref "D33")
      (value "1N4007")
      (footprint "eagle-import:DO-214AC")
      (libsource (lib "eagle-import") (part "DIODE-GEN-PURPOSE-1KV-1A(DO-214AC)"))
    )
    (comp (ref "D34")
      (value "1N4007.")
      (footprint "eagle-import:DO-214AC")
      (fields (field (name "MPN") "1N4007"))
      (libsource (lib "eagle-import") (part "DIODE-GEN-PURPOSE-1KV-1A(DO-214AC)"))
    )
    (comp (ref "D35")
      (value "1N5817")
      (footprint "eagle-import:DO-214AC_SLIM")
      (libsource (lib "eagle-import") (part "DIODE-GEN-PURPOSE-1KV-1A(DO-214AC)DO-214AC/1206"))
    )
    (comp (ref "D36")
      (value "1N5817.")
      (footprint "eagle-import:DO-214AC_SLIM")
      (libsource (lib "eagle-import") (part "DIODE-GEN-PURPOSE-1KV-1A(DO-214AC)DO-214AC/1206"))
    )
    (comp (ref "D37")
      (value "1N5817.")
      (footprint "eagle-import:DO-214AC_SLIM")
      (libsource (lib "eagle-import") (part "DIODE-GEN-PURPOSE-1KV-1A(DO-214AC)DO-214AC/1206"))
    )
    (comp (ref "D38")
      (value "1N5817")
      (footprint "eagle-import:DO-214AC_SLIM")
      (libsource (lib "eagle-import") (part "DIODE-GEN-PURPOSE-1KV-1A(DO-214AC)DO-214AC/1206"))
    )
    (comp (ref "D39")
      (value "1N4007.")
      (footprint "eagle-import:DO-214AC")
      (fields (field (name "MPN") "1N4007"))
      (libsource (lib "eagle-import") (part "DIODE-GEN-PURPOSE-1KV-1A(DO-214AC)"))
    )
    (comp (ref "D40")
      (value "1N4007.")
      (footprint "eagle-import:DO-214AC")
      (fields (field (name "MPN") "1N4007"))
      (libsource (lib "eagle-import") (part "DIODE-GEN-PURPOSE-1KV-1A(DO-214AC)"))
    )
    (comp (ref "D41")
      (value "Zen15")
      (footprint "eagle-import:DO214AA")
      (libsource (lib "eagle-import") (part "SM6T"))
    )
    (comp (ref "D42")
      (value "SM6TDO214AA_BI")
      (footprint "eagle-import:DO214AA_BI")
      (libsource (lib "eagle-import") (part "SM6TDO214AA_BI"))
    )
    (comp (ref "D43")
      (value "1N5817")
      (footprint "eagle-import:DO-214AC_SLIM")
      (libsource (lib "eagle-import") (part "DIODE-GEN-PURPOSE-1KV-1A(DO-214AC)DO-214AC/1206"))
    )
    (comp (ref "D44")
      (value "1N5817.")
      (footprint "eagle-import:DO-214AC_SLIM")
      (libsource (lib "eagle-import") (part "DIODE-GEN-PURPOSE-1KV-1A(DO-214AC)DO-214AC/1206"))
    )
    (comp (ref "D45")
      (value "Zen11")
      (footprint "eagle-import:SOD-123_MINI-SMA")
      (libsource (lib "eagle-import") (part "CGRM400-G1"))
    )
    (comp (ref "FID11")
      (value "FIDUCIAL")
      (footprint "eagle-import:FIDUCIAL_1MM")
      (libsource (lib "eagle-import") (part "FIDUCIAL"))
    )
    (comp (ref "FID12")
      (value "FIDUCIAL")
      (footprint "eagle-import:FIDUCIAL_1MM")
      (libsource (lib "eagle-import") (part "FIDUCIAL"))
    )
    (comp (ref "FID13")
      (value "FIDUCIAL")
      (footprint "eagle-import:FIDUCIAL_1MM")
      (libsource (lib "eagle-import") (part "FIDUCIAL"))
    )
    (comp (ref "FID14")
      (value "FIDUCIAL")
      (footprint "eagle-import:FIDUCIAL_1MM")
      (libsource (lib "eagle-import") (part "FIDUCIAL"))
    )
    (comp (ref "IC19")
      (value "4028")
      (footprint "eagle-import:SO16")
      (libsource (lib "eagle-import") (part "4028D"))
    )
    (comp (ref "IC20")
      (value "317TO202H_NOHOLE")
      (footprint "eagle-import:TO220H_NOHOLE")
      (libsource (lib "eagle-import") (part "317TO202H_NOHOLE"))
    )
    (comp (ref "IC21")
      (value "ULN2004")
      (footprint "eagle-import:SO16")
      (libsource (lib "eagle-import") (part "ULN2004AD"))
    )
    (comp (ref "IC22")
      (value "LM339")
      (footprint "eagle-import:SO14")
      (libsource (lib "eagle-import") (part "LM339D"))
    )
    (comp (ref "IC23")
      (value "78L06")
      (footprint "eagle-import:SOT89_ROUND")
      (libsource (lib "eagle-import") (part "78LXXSOT89_ROUND"))
    )
    (comp (ref "IC24")
      (value "555")
      (footprint "eagle-import:SO08")
      (libsource (lib "eagle-import") (part "555DNE"))
    )
    (comp (ref "IC25")
      (value "4538")
      (footprint "eagle-import:SO16")
      (libsource (lib "eagle-import") (part "4538D"))
    )
    (comp (ref "IC26")
      (value "78L10")
      (footprint "eagle-import:SOT89_ROUND")
      (libsource (lib "eagle-import") (part "78LXXSOT89_ROUND"))
    )
    (comp (ref "IC27")
      (value "LM2904")
      (footprint "eagle-import:SO08")
      (libsource (lib "eagle-import") (part "LM358D"))
    )
    (comp (ref "JP11")
      (value "JP2EJP2_SMALLPADS")
      (footprint "eagle-import:JP2_SMALLPADS")
      (libsource (lib "eagle-import") (part "JP2EJP2_SMALLPADS"))
    )
    (comp (ref "JP12")
      (value "JP2E_ORIG")
      (footprint "eagle-import:JP2_ORIG_SMALLPADS")
      (libsource (lib "eagle-import") (part "JP2E_ORIG"))
    )
    (comp (ref "JP13")
      (value "JP2EJP2_SMALLPADS")
      (footprint "eagle-import:JP2_SMALLPADS")
      (libsource (lib "eagle-import") (part "JP2EJP2_SMALLPADS"))
    )
    (comp (ref "JP14")
      (value "JP2EJP2_SMALLPADS")
      (footprint "eagle-import:JP2_SMALLPADS")
      (libsource (lib "eagle-import") (part "JP2EJP2_SMALLPADS"))
    )
    (comp (ref "JP15")
      (value "JP2EJP2_SMALLPADS")
      (footprint "eagle-import:JP2_SMALLPADS")
      (libsource (lib "eagle-import") (part "JP2EJP2_SMALLPADS"))
    )
    (comp (ref "LED13")
      (value "LEDLD260")
      (footprint "eagle-import:LD260")
      (libsource (lib "eagle-import") (part "LEDLD260"))
    )
    (comp (ref "LED14")
      (value "LEDLD260")
      (footprint "eagle-import:LD260")
      (libsource (lib "eagle-import") (part "LEDLD260"))
    )
    (comp (ref "LED15")
      (value "LEDLD260")
      (footprint "eagle-import:LD260")
      (libsource (lib "eagle-import") (part "LEDLD260"))
    )
    (comp (ref "LED16")
      (value "LEDLD260")
      (footprint "eagle-import:LD260")
      (libsource (lib "eagle-import") (part "LEDLD260"))
    )
    (comp (ref "LED17")
      (value "LEDLD260")
      (footprint "eagle-import:LD260")
      (libsource (lib "eagle-import") (part "LEDLD260"))
    )
    (comp (ref "LED18")
      (value "LEDLD260")
      (footprint "eagle-import:LD260")
      (libsource (lib "eagle-import") (part "LEDLD260"))
    )
    (comp (ref "Q24")
      (value "BA")
      (footprint "eagle-import:SOT89")
      (libsource (lib "eagle-import") (part "PNP-TRANSISTOR_SOT89"))
    )
    (comp (ref "Q25")
      (value "BA.")
      (footprint "eagle-import:SOT89")
      (libsource (lib "eagle-import") (part "PNP-TRANSISTOR_SOT89"))
    )
    (comp (ref "Q26")
      (value "BA.")
      (footprint "eagle-import:SOT89")
      (libsource (lib "eagle-import") (part "PNP-TRANSISTOR_SOT89"))
    )
    (comp (ref "Q27")
      (value "BA")
      (footprint "eagle-import:SOT89")
      (libsource (lib "eagle-import") (part "PNP-TRANSISTOR_SOT89"))
    )
    (comp (ref "Q28")
      (value "MY")
      (footprint "eagle-import:SOT89")
      (libsource (lib "eagle-import") (part "NPN-TRANSISTOR_SOT89"))
    )
    (comp (ref "Q29")
      (value "J1")
      (footprint "eagle-import:SOT-23")
      (fields (field (name "MPN") "BSS138W-7-F"))
      (libsource (lib "eagle-import") (part "SMD-MOSFET-N-CH-50V-200MA-BSS138W-7-F(SOT-23)"))
    )
    (comp (ref "Q30")
      (value "J1")
      (footprint "eagle-import:SOT-23")
      (fields (field (name "MPN") "BSS138W-7-F"))
      (libsource (lib "eagle-import") (part "SMD-MOSFET-N-CH-50V-200MA-BSS138W-7-F(SOT-23)"))
    )
    (comp (ref "Q31")
      (value "J1")
      (footprint "eagle-import:SOT-23")
      (fields (field (name "MPN") "BSS138W-7-F"))
      (libsource (lib "eagle-import") (part "SMD-MOSFET-N-CH-50V-200MA-BSS138W-7-F(SOT-23)"))
    )
    (comp (ref "Q32")
      (value "BA")
      (footprint "eagle-import:SOT89")
      (libsource (lib "eagle-import") (part "PNP-TRANSISTOR_SOT89"))
    )
    (comp (ref "Q33")
      (value "J1")
      (footprint "eagle-import:SOT-23")
      (fields (field (name "MPN") "BSS138W-7-F"))
      (libsource (lib "eagle-import") (part "SMD-MOSFET-N-CH-50V-200MA-BSS138W-7-F(SOT-23)"))
    )
    (comp (ref "R166")
      (value "47")
      (footprint "eagle-import:V235_17_1MM")
      (libsource (lib "eagle-import") (part "R-EU_V235/17_1MM"))
    )
    (comp (ref "R167")
      (value "13")
      (footprint "eagle-import:R1206")
      (fields (field (name "MPN") "RC1206JR-0713RL"))
      (libsource (lib "eagle-import") (part "SMD-RES-13R-5%-1/4W(1206)"))
    )
    (comp (ref "R168")
      (value "47")
      (footprint "eagle-import:V235_17_1MM")
      (libsource (lib "eagle-import") (part "R-EU_V235/17_1MM"))
    )
    (comp (ref "R169")
      (value "104")
      (footprint "eagle-import:R0805")
      (fields (field (name "MPN") "RC0805FR-0710KL"))
      (libsource (lib "eagle-import") (part "SMD-RES-10K-1%-1/8W(0805)"))
    )
    (comp (ref "R170")
      (value "104")
      (footprint "eagle-import:R0805")
      (fields (field (name "MPN") "RC0805FR-0710KL"))
      (libsource (lib "eagle-import") (part "SMD-RES-10K-1%-1/8W(0805)"))
    )
    (comp (ref "R171")
      (value "104")
      (footprint "eagle-import:R0805")
      (fields (field (name "MPN") "RC0805FR-0710KL"))
      (libsource (lib "eagle-import") (part "SMD-RES-10K-1%-1/8W(0805)"))
    )
    (comp (ref "R172")
      (value "4701")
      (footprint "eagle-import:R0805")
      (fields (field (name "MPN") "RC0805JR-074K7L"))
      (libsource (lib "eagle-import") (part "SMD-RES-4.7K-5%-1/8W(0805)"))
    )
    (comp (ref "R173")
      (value "1002")
      (footprint "eagle-import:R0805")
      (fields (field (name "MPN") "RC0805FR-0710KL"))
      (libsource (lib "eagle-import") (part "SMD-RES-10K-1%-1/8W(0805)"))
    )
    (comp (ref "R174")
      (value "1002")
      (footprint "eagle-import:R0805")
      (fields (field (name "MPN") "RC0805FR-0710KL"))
      (libsource (lib "eagle-import") (part "SMD-RES-10K-1%-1/8W(0805)"))
    )
    (comp (ref "R175")
      (value "1502")
      (footprint "eagle-import:R0805")
      (fields (field (name "MPN") "RC0805FR-0710KL"))
      (libsource (lib "eagle-import") (part "SMD-RES-10K-1%-1/8W(0805)"))
    )
    (comp (ref "R176")
      (value "104")
      (footprint "eagle-import:R0805")
      (fields (field (name "MPN") "RC0805FR-0710KL"))
      (libsource (lib "eagle-import") (part "SMD-RES-10K-1%-1/8W(0805)"))
    )
    (comp (ref "R177")
      (value "104")
      (footprint "eagle-import:R0805")
      (fields (field (name "MPN") "RC0805FR-0710KL"))
      (libsource (lib "eagle-import") (part "SMD-RES-10K-1%-1/8W(0805)"))
    )
    (comp (ref "R178")
      (value "1502")
      (footprint "eagle-import:R0805")
      (fields (field (name "MPN") "RC0805FR-0710KL"))
      (libsource (lib "eagle-import") (part "SMD-RES-10K-1%-1/8W(0805)"))
    )
    (comp (ref "R179")
      (value "1002")
      (footprint "eagle-import:R0805")
      (fields (field (name "MPN") "RC0805FR-0710KL"))
      (libsource (lib "eagle-import") (part "SMD-RES-10K-1%-1/8W(0805)"))
    )
    (comp (ref "R180")
      (value "2201")
      (footprint "eagle-import:R0805")
      (fields (field (name "MPN") "RC0805JR-072K2L"))
      (libsource (lib "eagle-import") (part "SMD-RES-2.2K-5%-1/8W(0805)"))
    )
    (comp (ref "R181")
      (value "1002")
      (footprint "eagle-import:R0805")
      (fields (field (name "MPN") "RC0805FR-0710KL"))
      (libsource (lib "eagle-import") (part "SMD-RES-10K-1%-1/8W(0805)"))
    )
    (comp (ref "R182")
      (value "4701")
      (footprint "eagle-import:R0805")
      (fields (field (name "MPN") "RC0805JR-074K7L"))
      (libsource (lib "eagle-import") (part "SMD-RES-4.7K-5%-1/8W(0805)"))
    )
    (comp (ref "R183")
      (value "2702")
      (footprint "eagle-import:R0805")
      (fields (field (name "MPN") "RC0805JR-074K7L"))
      (libsource (lib "eagle-import") (part "SMD-RES-4.7K-5%-1/8W(0805)"))
    )
    (comp (ref "R184")
      (value "102")
      (footprint "eagle-import:R0805")
      (fields (field (name "MPN") "RC0805JR-071KL"))
      (libsource (lib "eagle-import") (part "SMD-RES-1K-5%-1/8W(0805)"))
    )
    (comp (ref "R185")
      (value "R_user")
      (footprint "eagle-import:R0805")
      (libsource (lib "eagle-import") (part "R-EU_R0805"))
    )
    (comp (ref "R186")
      (value "102")
      (footprint "eagle-import:R0805")
      (fields (field (name "MPN") "RC0805JR-07220RL"))
      (libsource (lib "eagle-import") (part "SMD-RES-220R-5%-1/8W(0805)"))
    )
    (comp (ref "R187")
      (value "(101)")
      (footprint "eagle-import:R0805")
      (fields (field (name "MPN") "RC0805JR-07100RL"))
      (libsource (lib "eagle-import") (part "SMD-RES-100R-5%-1/8W(0805)"))
    )
    (comp (ref "R188")
      (value "(1000)")
      (footprint "eagle-import:R0805")
      (fields (field (name "MPN") "RC0805JR-07100RL"))
      (libsource (lib "eagle-import") (part "SMD-RES-100R-5%-1/8W(0805)"))
    )
    (comp (ref "R189")
      (value "102")
      (footprint "eagle-import:R0805")
      (fields (field (name "MPN") "RC0805JR-071KL"))
      (libsource (lib "eagle-import") (part "SMD-RES-1K-5%-1/8W(0805)"))
    )
    (comp (ref "R190")
      (value "13")
      (footprint "eagle-import:R1206")
      (fields (field (name "MPN") "RC1206JR-0713RL"))
      (libsource (lib "eagle-import") (part "SMD-RES-13R-5%-1/4W(1206)"))
    )
    (comp (ref "R191")
      (value "13")
      (footprint "eagle-import:R1206")
      (fields (field (name "MPN") "RC1206JR-0713RL"))
      (libsource (lib "eagle-import") (part "SMD-RES-13R-5%-1/4W(1206)"))
    )
    (comp (ref "R192")
      (value "2702")
      (footprint "eagle-import:R0805")
      (fields (field (name "MPN") "RC0805JR-074K7L"))
      (libsource (lib "eagle-import") (part "SMD-RES-4.7K-5%-1/8W(0805)"))
    )
    (comp (ref "R193")
      (value "4701")
      (footprint "eagle-import:R0805")
      (fields (field (name "MPN") "RC0805JR-074K7L"))
      (libsource (lib "eagle-import") (part "SMD-RES-4.7K-5%-1/8W(0805)"))
    )
    (comp (ref "R194")
      (value "100")
      (footprint "eagle-import:R0805")
      (fields (field (name "MPN") "RC0805JR-072K2L"))
      (libsource (lib "eagle-import") (part "SMD-RES-2.2K-5%-1/8W(0805)"))
    )
    (comp (ref "R195")
      (value "104")
      (footprint "eagle-import:R0805")
      (fields (field (name "MPN") "RC0805FR-0710KL"))
      (libsource (lib "eagle-import") (part "SMD-RES-10K-1%-1/8W(0805)"))
    )
    (comp (ref "R196")
      (value "104")
      (footprint "eagle-import:R0805")
      (fields (field (name "MPN") "RC0805FR-0710KL"))
      (libsource (lib "eagle-import") (part "SMD-RES-10K-1%-1/8W(0805)"))
    )
    (comp (ref "R197")
      (value "(1002)")
      (footprint "eagle-import:R0805")
      (fields (field (name "MPN") "RC0805FR-0710KL"))
      (libsource (lib "eagle-import") (part "SMD-RES-10K-1%-1/8W(0805)"))
    )
    (comp (ref "R198")
      (value "2702")
      (footprint "eagle-import:R0805")
      (fields (field (name "MPN") "RC0805FR-0710KL"))
      (libsource (lib "eagle-import") (part "SMD-RES-10K-1%-1/8W(0805)"))
    )
    (comp (ref "R199")
      (value "47")
      (footprint "eagle-import:V235_17_1MM")
      (libsource (lib "eagle-import") (part "R-EU_V235/17_1MM"))
    )
    (comp (ref "R200")
      (value "47")
      (footprint "eagle-import:V235_17_1MM")
      (libsource (lib "eagle-import") (part "R-EU_V235/17_1MM"))
    )
    (comp (ref "R201")
      (value "2702")
      (footprint "eagle-import:R0805")
      (fields (field (name "MPN") "RC0805JR-074K7L"))
      (libsource (lib "eagle-import") (part "SMD-RES-4.7K-5%-1/8W(0805)"))
    )
    (comp (ref "R202")
      (value "2201")
      (footprint "eagle-import:R0805")
      (fields (field (name "MPN") "RC0805JR-072K2L"))
      (libsource (lib "eagle-import") (part "SMD-RES-2.2K-5%-1/8W(0805)"))
    )
    (comp (ref "R203")
      (value "1002")
      (footprint "eagle-import:R0805")
      (fields (field (name "MPN") "RC0805JR-074K7L"))
      (libsource (lib "eagle-import") (part "SMD-RES-4.7K-5%-1/8W(0805)"))
    )
    (comp (ref "R204")
      (value "1002")
      (footprint "eagle-import:R0805")
      (fields (field (name "MPN") "RC0805FR-0710KL"))
      (libsource (lib "eagle-import") (part "SMD-RES-10K-1%-1/8W(0805)"))
    )
    (comp (ref "R205")
      (value "102")
      (footprint "eagle-import:R0805")
      (fields (field (name "MPN") "RC0805JR-071KL"))
      (libsource (lib "eagle-import") (part "SMD-RES-1K-5%-1/8W(0805)"))
    )
    (comp (ref "R206")
      (value "2702")
      (footprint "eagle-import:R0805")
      (fields (field (name "MPN") "RC0805JR-074K7L"))
      (libsource (lib "eagle-import") (part "SMD-RES-4.7K-5%-1/8W(0805)"))
    )
    (comp (ref "R207")
      (value "1002")
      (footprint "eagle-import:R0805")
      (fields (field (name "MPN") "RC0805JR-071KL"))
      (libsource (lib "eagle-import") (part "SMD-RES-1K-5%-1/8W(0805)"))
    )
    (comp (ref "R208")
      (value "1002")
      (footprint "eagle-import:R0805")
      (fields (field (name "MPN") "RC0805JR-071KL"))
      (libsource (lib "eagle-import") (part "SMD-RES-1K-5%-1/8W(0805)"))
    )
    (comp (ref "R209")
      (value "R_user")
      (footprint "eagle-import:R0805")
      (libsource (lib "eagle-import") (part "R-EU_R0805"))
    )
    (comp (ref "R210")
      (value "104")
      (footprint "eagle-import:R0805")
      (fields (field (name "MPN") "RC0805FR-0710KL"))
      (libsource (lib "eagle-import") (part "SMD-RES-10K-1%-1/8W(0805)"))
    )
    (comp (ref "R211")
      (value "104")
      (footprint "eagle-import:R0805")
      (fields (field (name "MPN") "RC0805FR-0710KL"))
      (libsource (lib "eagle-import") (part "SMD-RES-10K-1%-1/8W(0805)"))
    )
    (comp (ref "R212")
      (value "104")
      (footprint "eagle-import:R0805")
      (fields (field (name "MPN") "RC0805FR-0710KL"))
      (libsource (lib "eagle-import") (part "SMD-RES-10K-1%-1/8W(0805)"))
    )
    (comp (ref "R213")
      (value "13")
      (footprint "eagle-import:R1206")
      (fields (field (name "MPN") "RC1206JR-0713RL"))
      (libsource (lib "eagle-import") (part "SMD-RES-13R-5%-1/4W(1206)"))
    )
    (comp (ref "R214")
      (value "2201")
      (footprint "eagle-import:R0805")
      (fields (field (name "MPN") "RC0805JR-071KL"))
      (libsource (lib "eagle-import") (part "SMD-RES-1K-5%-1/8W(0805)"))
    )
    (comp (ref "R215")
      (value "100")
      (footprint "eagle-import:R0805")
      (fields (field (name "MPN") "RC0805JR-07220RL"))
      (libsource (lib "eagle-import") (part "SMD-RES-220R-5%-1/8W(0805)"))
    )
    (comp (ref "R216")
      (value "13")
      (footprint "eagle-import:R1206")
      (fields (field (name "MPN") "RC1206JR-0713RL"))
      (libsource (lib "eagle-import") (part "SMD-RES-13R-5%-1/4W(1206)"))
    )
    (comp (ref "R217")
      (value "4701")
      (footprint "eagle-import:R0805")
      (fields (field (name "MPN") "RC0805JR-074K7L"))
      (libsource (lib "eagle-import") (part "SMD-RES-4.7K-5%-1/8W(0805)"))
    )
    (comp (ref "R218")
      (value "104")
      (footprint "eagle-import:R0805")
      (fields (field (name "MPN") "RC0805JR-074K7L"))
      (libsource (lib "eagle-import") (part "SMD-RES-4.7K-5%-1/8W(0805)"))
    )
    (comp (ref "R219")
      (value "2R")
      (footprint "eagle-import:R0805")
      (fields (field (name "MPN") "RC0805JR-072K2L"))
      (libsource (lib "eagle-import") (part "SMD-RES-2.2K-5%-1/8W(0805)"))
    )
    (comp (ref "R220")
      (value "2R")
      (footprint "eagle-import:R0805")
      (fields (field (name "MPN") "RC0805JR-072K2L"))
      (libsource (lib "eagle-import") (part "SMD-RES-2.2K-5%-1/8W(0805)"))
    )
    (comp (ref "SJ3")
      (value "SJ")
      (footprint "eagle-import:SJ")
      (libsource (lib "eagle-import") (part "solder-jumper_SJ"))
    )
    (comp (ref "SJMP3")
      (value "SJ")
      (footprint "eagle-import:SJ")
      (libsource (lib "eagle-import") (part "SJ"))
    )
    (comp (ref "START3")
      (value "TPSB2.0")
      (footprint "eagle-import:B2.0")
      (libsource (lib "eagle-import") (part "TPSB2.0"))
    )
    (comp (ref "TP70")
      (value "TPSB2.0")
      (footprint "eagle-import:B2.0")
      (libsource (lib "eagle-import") (part "TPSB2.0"))
    )
    (comp (ref "TP71")
      (value "TPSB2.0")
      (footprint "eagle-import:B2.0")
      (libsource (lib "eagle-import") (part "TPSB2.0"))
    )
    (comp (ref "TP72")
      (value "TPSB2.0")
      (footprint "eagle-import:B2.0")
      (libsource (lib "eagle-import") (part "TPSB2.0"))
    )
    (comp (ref "TP73")
      (value "TPSB2.0")
      (footprint "eagle-import:B2.0")
      (libsource (lib "eagle-import") (part "TPSB2.0"))
    )
    (comp (ref "TP74")
      (value "TPSB2.0")
      (footprint "eagle-import:B2.0")
      (libsource (lib "eagle-import") (part "TPSB2.0"))
    )
    (comp (ref "TP75")
      (value "TPSB2.0")
      (footprint "eagle-import:B2.0")
      (libsource (lib "eagle-import") (part "TPSB2.0"))
    )
    (comp (ref "TP76")
      (value "TPSB2.0")
      (footprint "eagle-import:B2.0")
      (libsource (lib "eagle-import") (part "TPSB2.0"))
    )
    (comp (ref "TP77")
      (value "TPSB2.0")
      (footprint "eagle-import:B2.0")
      (libsource (lib "eagle-import") (part "TPSB2.0"))
    )
    (comp (ref "TP78")
      (value "TPSB2.0")
      (footprint "eagle-import:B2.0")
      (libsource (lib "eagle-import") (part "TPSB2.0"))
    )
    (comp (ref "TP79")
      (value "TPSB2.0")
      (footprint "eagle-import:B2.0")
      (libsource (lib "eagle-import") (part "TPSB2.0"))
    )
    (comp (ref "TP80")
      (value "TPSB2.0")
      (footprint "eagle-import:B2.0")
      (libsource (lib "eagle-import") (part "TPSB2.0"))
    )
    (comp (ref "TP81")
      (value "TPSB2.0")
      (footprint "eagle-import:B2.0")
      (libsource (lib "eagle-import") (part "TPSB2.0"))
    )
    (comp (ref "TP82")
      (value "TPSB2.0")
      (footprint "eagle-import:B2.0")
      (libsource (lib "eagle-import") (part "TPSB2.0"))
    )
    (comp (ref "TP83")
      (value "TPSB2.0")
      (footprint "eagle-import:B2.0")
      (libsource (lib "eagle-import") (part "TPSB2.0"))
    )
    (comp (ref "TP84")
      (value "TPSB2.0")
      (footprint "eagle-import:B2.0")
      (libsource (lib "eagle-import") (part "TPSB2.0"))
    )
    (comp (ref "TP85")
      (value "TPSB2.0")
      (footprint "eagle-import:B2.0")
      (libsource (lib "eagle-import") (part "TPSB2.0"))
    )
    (comp (ref "TP86")
      (value "TPSB2.0")
      (footprint "eagle-import:B2.0")
      (libsource (lib "eagle-import") (part "TPSB2.0"))
    )
    (comp (ref "TP87")
      (value "TPSB2.0")
      (footprint "eagle-import:B2.0")
      (libsource (lib "eagle-import") (part "TPSB2.0"))
    )
    (comp (ref "TP88")
      (value "TPSB1,27")
      (footprint "eagle-import:B1,27")
      (libsource (lib "eagle-import") (part "TPSB1,27"))
    )
    (comp (ref "TP89")
      (value "TPSB2.0")
      (footprint "eagle-import:B2.0")
      (libsource (lib "eagle-import") (part "TPSB2.0"))
    )
    (comp (ref "TP90")
      (value "TPSB2.0")
      (footprint "eagle-import:B2.0")
      (libsource (lib "eagle-import") (part "TPSB2.0"))
    )
    (comp (ref "TP91")
      (value "TPSB2.0")
      (footprint "eagle-import:B2.0")
      (libsource (lib "eagle-import") (part "TPSB2.0"))
    )
    (comp (ref "TP92")
      (value "TPSB2.0")
      (footprint "eagle-import:B2.0")
      (libsource (lib "eagle-import") (part "TPSB2.0"))
    )
    (comp (ref "X7")
      (value "CON_BMWV2")
      (footprint "eagle-import:24-PIN_V2")
      (libsource (lib "eagle-import") (part "CON_BMWV2"))
    )
    (comp (ref "X8")
      (value "22-23-2051")
      (footprint "eagle-import:22-23-2051")
      (fields (field (name "MF") "MOLEX"))
      (libsource (lib "eagle-import") (part "22-23-2051"))
    )
    (comp (ref "X9")
      (value "22-23-2021")
      (footprint "eagle-import:22-23-2021")
      (fields (field (name "MF") "MOLEX"))
      (libsource (lib "eagle-import") (part "22-23-2021"))
    )
    (comp (ref "6V5")
      (value "TPSB2.0")
      (footprint "eagle-import:B2.0")
      (libsource (lib "eagle-import") (part "TPSB2.0"))
    )
    (comp (ref "10V5")
      (value "TPSB2.0")
      (footprint "eagle-import:B2.0")
      (libsource (lib "eagle-import") (part "TPSB2.0"))
    )
    (comp (ref "11")
      (value "2081-1132")
      (footprint "eagle-import:12-PIN")
      (libsource (lib "eagle-import") (part "2081-1132"))
    )
    (comp (ref "12")
      (value "2081-1132")
      (footprint "eagle-import:12-PIN")
      (libsource (lib "eagle-import") (part "2081-1132"))
    )
    (comp (ref "C51")
      (value "100u")
      (footprint "eagle-import:C1206")
      (fields (field (name "MPN") "GRM31CR60J107ME39L"))
      (libsource (lib "eagle-import") (part "CERAMIC-100UF-6.3V-20%-X5R(1206)"))
    )
    (comp (ref "C52")
      (value "100u")
      (footprint "eagle-import:C1206")
      (fields (field (name "MPN") "GRM31CR60J107ME39L"))
      (libsource (lib "eagle-import") (part "CERAMIC-100UF-6.3V-20%-X5R(1206)"))
    )
    (comp (ref "C53")
      (value "100nF,")
      (footprint "eagle-import:C0805")
      (fields (field (name "MPN") "CC0805KRX7R9BB104"))
      (libsource (lib "eagle-import") (part "CERAMIC-100NF-50V-10%-X7R(0805)"))
    )
    (comp (ref "C54")
      (value "4.7u")
      (footprint "eagle-import:C0805")
      (fields (field (name "MPN") "CC0805KKX5R8BB475"))
      (libsource (lib "eagle-import") (part "CERAMIC-4.7UF-25V-10%-X5R(0805)"))
    )
    (comp (ref "C55")
      (value "100nF.")
      (footprint "eagle-import:C0805")
      (fields (field (name "MPN") "CC0805KRX7R9BB104"))
      (libsource (lib "eagle-import") (part "CERAMIC-100NF-50V-10%-X7R(0805)"))
    )
    (comp (ref "C56")
      (value "100nF.")
      (footprint "eagle-import:C0805")
      (fields (field (name "MPN") "CC0805KRX7R9BB104"))
      (libsource (lib "eagle-import") (part "CERAMIC-100NF-50V-10%-X7R(0805)"))
    )
    (comp (ref "C57")
      (value "2.2nF")
      (footprint "eagle-import:C0805")
      (fields (field (name "MPN") "CC0805KRX7R9BB104"))
      (libsource (lib "eagle-import") (part "CERAMIC-100NF-50V-10%-X7R(0805)"))
    )
    (comp (ref "C58")
      (value "100nF")
      (footprint "eagle-import:C0805")
      (fields (field (name "MPN") "CC0805KRX7R9BB104"))
      (libsource (lib "eagle-import") (part "CERAMIC-100NF-50V-10%-X7R(0805)"))
    )
    (comp (ref "C59")
      (value "100nF")
      (footprint "eagle-import:C0805")
      (fields (field (name "MPN") "CC0805KRX7R9BB104"))
      (libsource (lib "eagle-import") (part "CERAMIC-100NF-50V-10%-X7R(0805)"))
    )
    (comp (ref "C60")
      (value "100nF,")
      (footprint "eagle-import:C0805")
      (fields (field (name "MPN") "CC0805KRX7R9BB104"))
      (libsource (lib "eagle-import") (part "CERAMIC-100NF-50V-10%-X7R(0805)"))
    )
    (comp (ref "C61")
      (value "4.7u")
      (footprint "eagle-import:C0805")
      (fields (field (name "MPN") "CC0805KKX5R8BB475"))
      (libsource (lib "eagle-import") (part "CERAMIC-4.7UF-25V-10%-X5R(0805)"))
    )
    (comp (ref "C62")
      (value "10u")
      (footprint "eagle-import:C1206")
      (fields (field (name "MPN") "GRM31CR60J107ME39L"))
      (libsource (lib "eagle-import") (part "CERAMIC-100UF-6.3V-20%-X5R(1206)"))
    )
    (comp (ref "D60")
      (value "1N4007")
      (footprint "eagle-import:DO-214AC")
      (libsource (lib "eagle-import") (part "DIODE-GEN-PURPOSE-1KV-1A(DO-214AC)"))
    )
    (comp (ref "D61")
      (value "1N4007")
      (footprint "eagle-import:DO-214AC")
      (libsource (lib "eagle-import") (part "DIODE-GEN-PURPOSE-1KV-1A(DO-214AC)"))
    )
    (comp (ref "D62")
      (value "1N4007.")
      (footprint "eagle-import:DO-214AC")
      (fields (field (name "MPN") "1N4007"))
      (libsource (lib "eagle-import") (part "DIODE-GEN-PURPOSE-1KV-1A(DO-214AC)"))
    )
    (comp (ref "D63")
      (value "1N5817")
      (footprint "eagle-import:DO-214AC_SLIM")
      (libsource (lib "eagle-import") (part "DIODE-GEN-PURPOSE-1KV-1A(DO-214AC)DO-214AC/1206"))
    )
    (comp (ref "D64")
      (value "1N5817.")
      (footprint "eagle-import:DO-214AC_SLIM")
      (libsource (lib "eagle-import") (part "DIODE-GEN-PURPOSE-1KV-1A(DO-214AC)DO-214AC/1206"))
    )
    (comp (ref "D65")
      (value "1N5817.")
      (footprint "eagle-import:DO-214AC_SLIM")
      (libsource (lib "eagle-import") (part "DIODE-GEN-PURPOSE-1KV-1A(DO-214AC)DO-214AC/1206"))
    )
    (comp (ref "D66")
      (value "1N5817")
      (footprint "eagle-import:DO-214AC_SLIM")
      (libsource (lib "eagle-import") (part "DIODE-GEN-PURPOSE-1KV-1A(DO-214AC)DO-214AC/1206"))
    )
    (comp (ref "D67")
      (value "1N4007.")
      (footprint "eagle-import:DO-214AC")
      (fields (field (name "MPN") "1N4007"))
      (libsource (lib "eagle-import") (part "DIODE-GEN-PURPOSE-1KV-1A(DO-214AC)"))
    )
    (comp (ref "D68")
      (value "1N4007.")
      (footprint "eagle-import:DO-214AC")
      (fields (field (name "MPN") "1N4007"))
      (libsource (lib "eagle-import") (part "DIODE-GEN-PURPOSE-1KV-1A(DO-214AC)"))
    )
    (comp (ref "D69")
      (value "Zen15")
      (footprint "eagle-import:DO214AA")
      (libsource (lib "eagle-import") (part "SM6T"))
    )
    (comp (ref "D70")
      (value "SM6TDO214AA_BI")
      (footprint "eagle-import:DO214AA_BI")
      (libsource (lib "eagle-import") (part "SM6TDO214AA_BI"))
    )
    (comp (ref "D71")
      (value "1N5817")
      (footprint "eagle-import:DO-214AC_SLIM")
      (libsource (lib "eagle-import") (part "DIODE-GEN-PURPOSE-1KV-1A(DO-214AC)DO-214AC/1206"))
    )
    (comp (ref "D72")
      (value "1N5817.")
      (footprint "eagle-import:DO-214AC_SLIM")
      (libsource (lib "eagle-import") (part "DIODE-GEN-PURPOSE-1KV-1A(DO-214AC)DO-214AC/1206"))
    )
    (comp (ref "D73")
      (value "Zen11")
      (footprint "eagle-import:SOD-123_MINI-SMA")
      (libsource (lib "eagle-import") (part "CGRM400-G1"))
    )
    (comp (ref "FID19")
      (value "FIDUCIAL")
      (footprint "eagle-import:FIDUCIAL_1MM")
      (libsource (lib "eagle-import") (part "FIDUCIAL"))
    )
    (comp (ref "FID20")
      (value "FIDUCIAL")
      (footprint "eagle-import:FIDUCIAL_1MM")
      (libsource (lib "eagle-import") (part "FIDUCIAL"))
    )
    (comp (ref "FID21")
      (value "FIDUCIAL")
      (footprint "eagle-import:FIDUCIAL_1MM")
      (libsource (lib "eagle-import") (part "FIDUCIAL"))
    )
    (comp (ref "FID22")
      (value "FIDUCIAL")
      (footprint "eagle-import:FIDUCIAL_1MM")
      (libsource (lib "eagle-import") (part "FIDUCIAL"))
    )
    (comp (ref "IC37")
      (value "4028")
      (footprint "eagle-import:SO16")
      (libsource (lib "eagle-import") (part "4028D"))
    )
    (comp (ref "IC38")
      (value "317TO202H_NOHOLE")
      (footprint "eagle-import:TO220H_NOHOLE")
      (libsource (lib "eagle-import") (part "317TO202H_NOHOLE"))
    )
    (comp (ref "IC39")
      (value "ULN2004")
      (footprint "eagle-import:SO16")
      (libsource (lib "eagle-import") (part "ULN2004AD"))
    )
    (comp (ref "IC40")
      (value "LM339")
      (footprint "eagle-import:SO14")
      (libsource (lib "eagle-import") (part "LM339D"))
    )
    (comp (ref "IC41")
      (value "78L06")
      (footprint "eagle-import:SOT89_ROUND")
      (libsource (lib "eagle-import") (part "78LXXSOT89_ROUND"))
    )
    (comp (ref "IC42")
      (value "555")
      (footprint "eagle-import:SO08")
      (libsource (lib "eagle-import") (part "555DNE"))
    )
    (comp (ref "IC43")
      (value "4538")
      (footprint "eagle-import:SO16")
      (libsource (lib "eagle-import") (part "4538D"))
    )
    (comp (ref "IC44")
      (value "78L10")
      (footprint "eagle-import:SOT89_ROUND")
      (libsource (lib "eagle-import") (part "78LXXSOT89_ROUND"))
    )
    (comp (ref "IC45")
      (value "LM2904")
      (footprint "eagle-import:SO08")
      (libsource (lib "eagle-import") (part "LM358D"))
    )
    (comp (ref "JP21")
      (value "JP2EJP2_SMALLPADS")
      (footprint "eagle-import:JP2_SMALLPADS")
      (libsource (lib "eagle-import") (part "JP2EJP2_SMALLPADS"))
    )
    (comp (ref "JP22")
      (value "JP2E_ORIG")
      (footprint "eagle-import:JP2_ORIG_SMALLPADS")
      (libsource (lib "eagle-import") (part "JP2E_ORIG"))
    )
    (comp (ref "JP23")
      (value "JP2EJP2_SMALLPADS")
      (footprint "eagle-import:JP2_SMALLPADS")
      (libsource (lib "eagle-import") (part "JP2EJP2_SMALLPADS"))
    )
    (comp (ref "JP24")
      (value "JP2EJP2_SMALLPADS")
      (footprint "eagle-import:JP2_SMALLPADS")
      (libsource (lib "eagle-import") (part "JP2EJP2_SMALLPADS"))
    )
    (comp (ref "JP25")
      (value "JP2EJP2_SMALLPADS")
      (footprint "eagle-import:JP2_SMALLPADS")
      (libsource (lib "eagle-import") (part "JP2EJP2_SMALLPADS"))
    )
    (comp (ref "LED25")
      (value "LEDLD260")
      (footprint "eagle-import:LD260")
      (libsource (lib "eagle-import") (part "LEDLD260"))
    )
    (comp (ref "LED26")
      (value "LEDLD260")
      (footprint "eagle-import:LD260")
      (libsource (lib "eagle-import") (part "LEDLD260"))
    )
    (comp (ref "LED27")
      (value "LEDLD260")
      (footprint "eagle-import:LD260")
      (libsource (lib "eagle-import") (part "LEDLD260"))
    )
    (comp (ref "LED28")
      (value "LEDLD260")
      (footprint "eagle-import:LD260")
      (libsource (lib "eagle-import") (part "LEDLD260"))
    )
    (comp (ref "LED29")
      (value "LEDLD260")
      (footprint "eagle-import:LD260")
      (libsource (lib "eagle-import") (part "LEDLD260"))
    )
    (comp (ref "LED30")
      (value "LEDLD260")
      (footprint "eagle-import:LD260")
      (libsource (lib "eagle-import") (part "LEDLD260"))
    )
    (comp (ref "Q44")
      (value "BA")
      (footprint "eagle-import:SOT89")
      (libsource (lib "eagle-import") (part "PNP-TRANSISTOR_SOT89"))
    )
    (comp (ref "Q45")
      (value "BA.")
      (footprint "eagle-import:SOT89")
      (libsource (lib "eagle-import") (part "PNP-TRANSISTOR_SOT89"))
    )
    (comp (ref "Q46")
      (value "BA.")
      (footprint "eagle-import:SOT89")
      (libsource (lib "eagle-import") (part "PNP-TRANSISTOR_SOT89"))
    )
    (comp (ref "Q47")
      (value "BA")
      (footprint "eagle-import:SOT89")
      (libsource (lib "eagle-import") (part "PNP-TRANSISTOR_SOT89"))
    )
    (comp (ref "Q48")
      (value "MY")
      (footprint "eagle-import:SOT89")
      (libsource (lib "eagle-import") (part "NPN-TRANSISTOR_SOT89"))
    )
    (comp (ref "Q49")
      (value "J1")
      (footprint "eagle-import:SOT-23")
      (fields (field (name "MPN") "BSS138W-7-F"))
      (libsource (lib "eagle-import") (part "SMD-MOSFET-N-CH-50V-200MA-BSS138W-7-F(SOT-23)"))
    )
    (comp (ref "Q50")
      (value "J1")
      (footprint "eagle-import:SOT-23")
      (fields (field (name "MPN") "BSS138W-7-F"))
      (libsource (lib "eagle-import") (part "SMD-MOSFET-N-CH-50V-200MA-BSS138W-7-F(SOT-23)"))
    )
    (comp (ref "Q51")
      (value "J1")
      (footprint "eagle-import:SOT-23")
      (fields (field (name "MPN") "BSS138W-7-F"))
      (libsource (lib "eagle-import") (part "SMD-MOSFET-N-CH-50V-200MA-BSS138W-7-F(SOT-23)"))
    )
    (comp (ref "Q52")
      (value "BA")
      (footprint "eagle-import:SOT89")
      (libsource (lib "eagle-import") (part "PNP-TRANSISTOR_SOT89"))
    )
    (comp (ref "Q53")
      (value "J1")
      (footprint "eagle-import:SOT-23")
      (fields (field (name "MPN") "BSS138W-7-F"))
      (libsource (lib "eagle-import") (part "SMD-MOSFET-N-CH-50V-200MA-BSS138W-7-F(SOT-23)"))
    )
    (comp (ref "R276")
      (value "47")
      (footprint "eagle-import:V235_17_1MM")
      (libsource (lib "eagle-import") (part "R-EU_V235/17_1MM"))
    )
    (comp (ref "R277")
      (value "13")
      (footprint "eagle-import:R1206")
      (fields (field (name "MPN") "RC1206JR-0713RL"))
      (libsource (lib "eagle-import") (part "SMD-RES-13R-5%-1/4W(1206)"))
    )
    (comp (ref "R278")
      (value "47")
      (footprint "eagle-import:V235_17_1MM")
      (libsource (lib "eagle-import") (part "R-EU_V235/17_1MM"))
    )
    (comp (ref "R279")
      (value "104")
      (footprint "eagle-import:R0805")
      (fields (field (name "MPN") "RC0805FR-0710KL"))
      (libsource (lib "eagle-import") (part "SMD-RES-10K-1%-1/8W(0805)"))
    )
    (comp (ref "R280")
      (value "104")
      (footprint "eagle-import:R0805")
      (fields (field (name "MPN") "RC0805FR-0710KL"))
      (libsource (lib "eagle-import") (part "SMD-RES-10K-1%-1/8W(0805)"))
    )
    (comp (ref "R281")
      (value "104")
      (footprint "eagle-import:R0805")
      (fields (field (name "MPN") "RC0805FR-0710KL"))
      (libsource (lib "eagle-import") (part "SMD-RES-10K-1%-1/8W(0805)"))
    )
    (comp (ref "R282")
      (value "4701")
      (footprint "eagle-import:R0805")
      (fields (field (name "MPN") "RC0805JR-074K7L"))
      (libsource (lib "eagle-import") (part "SMD-RES-4.7K-5%-1/8W(0805)"))
    )
    (comp (ref "R283")
      (value "1002")
      (footprint "eagle-import:R0805")
      (fields (field (name "MPN") "RC0805FR-0710KL"))
      (libsource (lib "eagle-import") (part "SMD-RES-10K-1%-1/8W(0805)"))
    )
    (comp (ref "R284")
      (value "1002")
      (footprint "eagle-import:R0805")
      (fields (field (name "MPN") "RC0805FR-0710KL"))
      (libsource (lib "eagle-import") (part "SMD-RES-10K-1%-1/8W(0805)"))
    )
    (comp (ref "R285")
      (value "1502")
      (footprint "eagle-import:R0805")
      (fields (field (name "MPN") "RC0805FR-0710KL"))
      (libsource (lib "eagle-import") (part "SMD-RES-10K-1%-1/8W(0805)"))
    )
    (comp (ref "R286")
      (value "104")
      (footprint "eagle-import:R0805")
      (fields (field (name "MPN") "RC0805FR-0710KL"))
      (libsource (lib "eagle-import") (part "SMD-RES-10K-1%-1/8W(0805)"))
    )
    (comp (ref "R287")
      (value "104")
      (footprint "eagle-import:R0805")
      (fields (field (name "MPN") "RC0805FR-0710KL"))
      (libsource (lib "eagle-import") (part "SMD-RES-10K-1%-1/8W(0805)"))
    )
    (comp (ref "R288")
      (value "1502")
      (footprint "eagle-import:R0805")
      (fields (field (name "MPN") "RC0805FR-0710KL"))
      (libsource (lib "eagle-import") (part "SMD-RES-10K-1%-1/8W(0805)"))
    )
    (comp (ref "R289")
      (value "1002")
      (footprint "eagle-import:R0805")
      (fields (field (name "MPN") "RC0805FR-0710KL"))
      (libsource (lib "eagle-import") (part "SMD-RES-10K-1%-1/8W(0805)"))
    )
    (comp (ref "R290")
      (value "2201")
      (footprint "eagle-import:R0805")
      (fields (field (name "MPN") "RC0805JR-072K2L"))
      (libsource (lib "eagle-import") (part "SMD-RES-2.2K-5%-1/8W(0805)"))
    )
    (comp (ref "R291")
      (value "1002")
      (footprint "eagle-import:R0805")
      (fields (field (name "MPN") "RC0805FR-0710KL"))
      (libsource (lib "eagle-import") (part "SMD-RES-10K-1%-1/8W(0805)"))
    )
    (comp (ref "R292")
      (value "4701")
      (footprint "eagle-import:R0805")
      (fields (field (name "MPN") "RC0805JR-074K7L"))
      (libsource (lib "eagle-import") (part "SMD-RES-4.7K-5%-1/8W(0805)"))
    )
    (comp (ref "R293")
      (value "2702")
      (footprint "eagle-import:R0805")
      (fields (field (name "MPN") "RC0805JR-074K7L"))
      (libsource (lib "eagle-import") (part "SMD-RES-4.7K-5%-1/8W(0805)"))
    )
    (comp (ref "R294")
      (value "102")
      (footprint "eagle-import:R0805")
      (fields (field (name "MPN") "RC0805JR-071KL"))
      (libsource (lib "eagle-import") (part "SMD-RES-1K-5%-1/8W(0805)"))
    )
    (comp (ref "R295")
      (value "R_user")
      (footprint "eagle-import:R0805")
      (libsource (lib "eagle-import") (part "R-EU_R0805"))
    )
    (comp (ref "R296")
      (value "102")
      (footprint "eagle-import:R0805")
      (fields (field (name "MPN") "RC0805JR-07220RL"))
      (libsource (lib "eagle-import") (part "SMD-RES-220R-5%-1/8W(0805)"))
    )
    (comp (ref "R297")
      (value "(101)")
      (footprint "eagle-import:R0805")
      (fields (field (name "MPN") "RC0805JR-07100RL"))
      (libsource (lib "eagle-import") (part "SMD-RES-100R-5%-1/8W(0805)"))
    )
    (comp (ref "R298")
      (value "(1000)")
      (footprint "eagle-import:R0805")
      (fields (field (name "MPN") "RC0805JR-07100RL"))
      (libsource (lib "eagle-import") (part "SMD-RES-100R-5%-1/8W(0805)"))
    )
    (comp (ref "R299")
      (value "102")
      (footprint "eagle-import:R0805")
      (fields (field (name "MPN") "RC0805JR-071KL"))
      (libsource (lib "eagle-import") (part "SMD-RES-1K-5%-1/8W(0805)"))
    )
    (comp (ref "R300")
      (value "13")
      (footprint "eagle-import:R1206")
      (fields (field (name "MPN") "RC1206JR-0713RL"))
      (libsource (lib "eagle-import") (part "SMD-RES-13R-5%-1/4W(1206)"))
    )
    (comp (ref "R301")
      (value "13")
      (footprint "eagle-import:R1206")
      (fields (field (name "MPN") "RC1206JR-0713RL"))
      (libsource (lib "eagle-import") (part "SMD-RES-13R-5%-1/4W(1206)"))
    )
    (comp (ref "R302")
      (value "2702")
      (footprint "eagle-import:R0805")
      (fields (field (name "MPN") "RC0805JR-074K7L"))
      (libsource (lib "eagle-import") (part "SMD-RES-4.7K-5%-1/8W(0805)"))
    )
    (comp (ref "R303")
      (value "4701")
      (footprint "eagle-import:R0805")
      (fields (field (name "MPN") "RC0805JR-074K7L"))
      (libsource (lib "eagle-import") (part "SMD-RES-4.7K-5%-1/8W(0805)"))
    )
    (comp (ref "R304")
      (value "100")
      (footprint "eagle-import:R0805")
      (fields (field (name "MPN") "RC0805JR-072K2L"))
      (libsource (lib "eagle-import") (part "SMD-RES-2.2K-5%-1/8W(0805)"))
    )
    (comp (ref "R305")
      (value "104")
      (footprint "eagle-import:R0805")
      (fields (field (name "MPN") "RC0805FR-0710KL"))
      (libsource (lib "eagle-import") (part "SMD-RES-10K-1%-1/8W(0805)"))
    )
    (comp (ref "R306")
      (value "104")
      (footprint "eagle-import:R0805")
      (fields (field (name "MPN") "RC0805FR-0710KL"))
      (libsource (lib "eagle-import") (part "SMD-RES-10K-1%-1/8W(0805)"))
    )
    (comp (ref "R307")
      (value "(1002)")
      (footprint "eagle-import:R0805")
      (fields (field (name "MPN") "RC0805FR-0710KL"))
      (libsource (lib "eagle-import") (part "SMD-RES-10K-1%-1/8W(0805)"))
    )
    (comp (ref "R308")
      (value "2702")
      (footprint "eagle-import:R0805")
      (fields (field (name "MPN") "RC0805FR-0710KL"))
      (libsource (lib "eagle-import") (part "SMD-RES-10K-1%-1/8W(0805)"))
    )
    (comp (ref "R309")
      (value "47")
      (footprint "eagle-import:V235_17_1MM")
      (libsource (lib "eagle-import") (part "R-EU_V235/17_1MM"))
    )
    (comp (ref "R310")
      (value "47")
      (footprint "eagle-import:V235_17_1MM")
      (libsource (lib "eagle-import") (part "R-EU_V235/17_1MM"))
    )
    (comp (ref "R311")
      (value "2702")
      (footprint "eagle-import:R0805")
      (fields (field (name "MPN") "RC0805JR-074K7L"))
      (libsource (lib "eagle-import") (part "SMD-RES-4.7K-5%-1/8W(0805)"))
    )
    (comp (ref "R312")
      (value "2201")
      (footprint "eagle-import:R0805")
      (fields (field (name "MPN") "RC0805JR-072K2L"))
      (libsource (lib "eagle-import") (part "SMD-RES-2.2K-5%-1/8W(0805)"))
    )
    (comp (ref "R313")
      (value "1002")
      (footprint "eagle-import:R0805")
      (fields (field (name "MPN") "RC0805JR-074K7L"))
      (libsource (lib "eagle-import") (part "SMD-RES-4.7K-5%-1/8W(0805)"))
    )
    (comp (ref "R314")
      (value "1002")
      (footprint "eagle-import:R0805")
      (fields (field (name "MPN") "RC0805FR-0710KL"))
      (libsource (lib "eagle-import") (part "SMD-RES-10K-1%-1/8W(0805)"))
    )
    (comp (ref "R315")
      (value "102")
      (footprint "eagle-import:R0805")
      (fields (field (name "MPN") "RC0805JR-071KL"))
      (libsource (lib "eagle-import") (part "SMD-RES-1K-5%-1/8W(0805)"))
    )
    (comp (ref "R316")
      (value "2702")
      (footprint "eagle-import:R0805")
      (fields (field (name "MPN") "RC0805JR-074K7L"))
      (libsource (lib "eagle-import") (part "SMD-RES-4.7K-5%-1/8W(0805)"))
    )
    (comp (ref "R317")
      (value "1002")
      (footprint "eagle-import:R0805")
      (fields (field (name "MPN") "RC0805JR-071KL"))
      (libsource (lib "eagle-import") (part "SMD-RES-1K-5%-1/8W(0805)"))
    )
    (comp (ref "R318")
      (value "1002")
      (footprint "eagle-import:R0805")
      (fields (field (name "MPN") "RC0805JR-071KL"))
      (libsource (lib "eagle-import") (part "SMD-RES-1K-5%-1/8W(0805)"))
    )
    (comp (ref "R319")
      (value "R_user")
      (footprint "eagle-import:R0805")
      (libsource (lib "eagle-import") (part "R-EU_R0805"))
    )
    (comp (ref "R320")
      (value "104")
      (footprint "eagle-import:R0805")
      (fields (field (name "MPN") "RC0805FR-0710KL"))
      (libsource (lib "eagle-import") (part "SMD-RES-10K-1%-1/8W(0805)"))
    )
    (comp (ref "R321")
      (value "104")
      (footprint "eagle-import:R0805")
      (fields (field (name "MPN") "RC0805FR-0710KL"))
      (libsource (lib "eagle-import") (part "SMD-RES-10K-1%-1/8W(0805)"))
    )
    (comp (ref "R322")
      (value "104")
      (footprint "eagle-import:R0805")
      (fields (field (name "MPN") "RC0805FR-0710KL"))
      (libsource (lib "eagle-import") (part "SMD-RES-10K-1%-1/8W(0805)"))
    )
    (comp (ref "R323")
      (value "13")
      (footprint "eagle-import:R1206")
      (fields (field (name "MPN") "RC1206JR-0713RL"))
      (libsource (lib "eagle-import") (part "SMD-RES-13R-5%-1/4W(1206)"))
    )
    (comp (ref "R324")
      (value "2201")
      (footprint "eagle-import:R0805")
      (fields (field (name "MPN") "RC0805JR-071KL"))
      (libsource (lib "eagle-import") (part "SMD-RES-1K-5%-1/8W(0805)"))
    )
    (comp (ref "R325")
      (value "100")
      (footprint "eagle-import:R0805")
      (fields (field (name "MPN") "RC0805JR-07220RL"))
      (libsource (lib "eagle-import") (part "SMD-RES-220R-5%-1/8W(0805)"))
    )
    (comp (ref "R326")
      (value "13")
      (footprint "eagle-import:R1206")
      (fields (field (name "MPN") "RC1206JR-0713RL"))
      (libsource (lib "eagle-import") (part "SMD-RES-13R-5%-1/4W(1206)"))
    )
    (comp (ref "R327")
      (value "4701")
      (footprint "eagle-import:R0805")
      (fields (field (name "MPN") "RC0805JR-074K7L"))
      (libsource (lib "eagle-import") (part "SMD-RES-4.7K-5%-1/8W(0805)"))
    )
    (comp (ref "R328")
      (value "104")
      (footprint "eagle-import:R0805")
      (fields (field (name "MPN") "RC0805JR-074K7L"))
      (libsource (lib "eagle-import") (part "SMD-RES-4.7K-5%-1/8W(0805)"))
    )
    (comp (ref "R329")
      (value "2R")
      (footprint "eagle-import:R0805")
      (fields (field (name "MPN") "RC0805JR-072K2L"))
      (libsource (lib "eagle-import") (part "SMD-RES-2.2K-5%-1/8W(0805)"))
    )
    (comp (ref "R330")
      (value "2R")
      (footprint "eagle-import:R0805")
      (fields (field (name "MPN") "RC0805JR-072K2L"))
      (libsource (lib "eagle-import") (part "SMD-RES-2.2K-5%-1/8W(0805)"))
    )
    (comp (ref "SJ5")
      (value "SJ")
      (footprint "eagle-import:SJ")
      (libsource (lib "eagle-import") (part "solder-jumper_SJ"))
    )
    (comp (ref "SJMP5")
      (value "SJ")
      (footprint "eagle-import:SJ")
      (libsource (lib "eagle-import") (part "SJ"))
    )
    (comp (ref "START5")
      (value "TPSB2.0")
      (footprint "eagle-import:B2.0")
      (libsource (lib "eagle-import") (part "TPSB2.0"))
    )
    (comp (ref "TP116")
      (value "TPSB2.0")
      (footprint "eagle-import:B2.0")
      (libsource (lib "eagle-import") (part "TPSB2.0"))
    )
    (comp (ref "TP117")
      (value "TPSB2.0")
      (footprint "eagle-import:B2.0")
      (libsource (lib "eagle-import") (part "TPSB2.0"))
    )
    (comp (ref "TP118")
      (value "TPSB2.0")
      (footprint "eagle-import:B2.0")
      (libsource (lib "eagle-import") (part "TPSB2.0"))
    )
    (comp (ref "TP119")
      (value "TPSB2.0")
      (footprint "eagle-import:B2.0")
      (libsource (lib "eagle-import") (part "TPSB2.0"))
    )
    (comp (ref "TP120")
      (value "TPSB2.0")
      (footprint "eagle-import:B2.0")
      (libsource (lib "eagle-import") (part "TPSB2.0"))
    )
    (comp (ref "TP121")
      (value "TPSB2.0")
      (footprint "eagle-import:B2.0")
      (libsource (lib "eagle-import") (part "TPSB2.0"))
    )
    (comp (ref "TP122")
      (value "TPSB2.0")
      (footprint "eagle-import:B2.0")
      (libsource (lib "eagle-import") (part "TPSB2.0"))
    )
    (comp (ref "TP123")
      (value "TPSB2.0")
      (footprint "eagle-import:B2.0")
      (libsource (lib "eagle-import") (part "TPSB2.0"))
    )
    (comp (ref "TP124")
      (value "TPSB2.0")
      (footprint "eagle-import:B2.0")
      (libsource (lib "eagle-import") (part "TPSB2.0"))
    )
    (comp (ref "TP125")
      (value "TPSB2.0")
      (footprint "eagle-import:B2.0")
      (libsource (lib "eagle-import") (part "TPSB2.0"))
    )
    (comp (ref "TP126")
      (value "TPSB2.0")
      (footprint "eagle-import:B2.0")
      (libsource (lib "eagle-import") (part "TPSB2.0"))
    )
    (comp (ref "TP127")
      (value "TPSB2.0")
      (footprint "eagle-import:B2.0")
      (libsource (lib "eagle-import") (part "TPSB2.0"))
    )
    (comp (ref "TP128")
      (value "TPSB2.0")
      (footprint "eagle-import:B2.0")
      (libsource (lib "eagle-import") (part "TPSB2.0"))
    )
    (comp (ref "TP129")
      (value "TPSB2.0")
      (footprint "eagle-import:B2.0")
      (libsource (lib "eagle-import") (part "TPSB2.0"))
    )
    (comp (ref "TP130")
      (value "TPSB2.0")
      (footprint "eagle-import:B2.0")
      (libsource (lib "eagle-import") (part "TPSB2.0"))
    )
    (comp (ref "TP131")
      (value "TPSB2.0")
      (footprint "eagle-import:B2.0")
      (libsource (lib "eagle-import") (part "TPSB2.0"))
    )
    (comp (ref "TP132")
      (value "TPSB2.0")
      (footprint "eagle-import:B2.0")
      (libsource (lib "eagle-import") (part "TPSB2.0"))
    )
    (comp (ref "TP133")
      (value "TPSB2.0")
      (footprint "eagle-import:B2.0")
      (libsource (lib "eagle-import") (part "TPSB2.0"))
    )
    (comp (ref "TP134")
      (value "TPSB1,27")
      (footprint "eagle-import:B1,27")
      (libsource (lib "eagle-import") (part "TPSB1,27"))
    )
    (comp (ref "TP135")
      (value "TPSB2.0")
      (footprint "eagle-import:B2.0")
      (libsource (lib "eagle-import") (part "TPSB2.0"))
    )
    (comp (ref "TP136")
      (value "TPSB2.0")
      (footprint "eagle-import:B2.0")
      (libsource (lib "eagle-import") (part "TPSB2.0"))
    )
    (comp (ref "TP137")
      (value "TPSB2.0")
      (footprint "eagle-import:B2.0")
      (libsource (lib "eagle-import") (part "TPSB2.0"))
    )
    (comp (ref "TP138")
      (value "TPSB2.0")
      (footprint "eagle-import:B2.0")
      (libsource (lib "eagle-import") (part "TPSB2.0"))
    )
    (comp (ref "X13")
      (value "CON_BMWV2")
      (footprint "eagle-import:24-PIN_V2")
      (libsource (lib "eagle-import") (part "CON_BMWV2"))
    )
    (comp (ref "X14")
      (value "22-23-2051")
      (footprint "eagle-import:22-23-2051")
      (fields (field (name "MF") "MOLEX"))
      (libsource (lib "eagle-import") (part "22-23-2051"))
    )
    (comp (ref "X15")
      (value "22-23-2021")
      (footprint "eagle-import:22-23-2021")
      (fields (field (name "MF") "MOLEX"))
      (libsource (lib "eagle-import") (part "22-23-2021"))
    )
    (comp (ref "1")
      (value "2081-1132")
      (footprint "eagle-import:12-PIN")
      (libsource (lib "eagle-import") (part "2081-1132"))
    )
    (comp (ref "2")
      (value "2081-1132")
      (footprint "eagle-import:12-PIN")
      (libsource (lib "eagle-import") (part "2081-1132"))
    )
    (comp (ref "6V")
      (value "TPSB2.0")
      (footprint "eagle-import:B2.0")
      (libsource (lib "eagle-import") (part "TPSB2.0"))
    )
    (comp (ref "10V")
      (value "TPSB2.0")
      (footprint "eagle-import:B2.0")
      (libsource (lib "eagle-import") (part "TPSB2.0"))
    )
    (comp (ref "C2")
      (value "10u")
      (footprint "eagle-import:C1206")
      (fields (field (name "MPN") "GRM31CR60J107ME39L"))
      (libsource (lib "eagle-import") (part "CERAMIC-100UF-6.3V-20%-X5R(1206)"))
    )
    (comp (ref "C15")
      (value "4.7u")
      (footprint "eagle-import:C0805")
      (fields (field (name "MPN") "CC0805KKX5R8BB475"))
      (libsource (lib "eagle-import") (part "CERAMIC-4.7UF-25V-10%-X5R(0805)"))
    )
    (comp (ref "C101")
      (value "4.7u")
      (footprint "eagle-import:C0805")
      (fields (field (name "MPN") "CC0805KKX5R8BB475"))
      (libsource (lib "eagle-import") (part "CERAMIC-4.7UF-25V-10%-X5R(0805)"))
    )
    (comp (ref "C102")
      (value "100nF")
      (footprint "eagle-import:C0805")
      (fields (field (name "MPN") "CC0805KRX7R9BB104"))
      (libsource (lib "eagle-import") (part "CERAMIC-100NF-50V-10%-X7R(0805)"))
    )
    (comp (ref "C103")
      (value "100nF,")
      (footprint "eagle-import:C0805")
      (fields (field (name "MPN") "CC0805KRX7R9BB104"))
      (libsource (lib "eagle-import") (part "CERAMIC-100NF-50V-10%-X7R(0805)"))
    )
    (comp (ref "C104")
      (value "100nF,")
      (footprint "eagle-import:C0805")
      (fields (field (name "MPN") "CC0805KRX7R9BB104"))
      (libsource (lib "eagle-import") (part "CERAMIC-100NF-50V-10%-X7R(0805)"))
    )
    (comp (ref "C105")
      (value "100nF.")
      (footprint "eagle-import:C0805")
      (fields (field (name "MPN") "CC0805KRX7R9BB104"))
      (libsource (lib "eagle-import") (part "CERAMIC-100NF-50V-10%-X7R(0805)"))
    )
    (comp (ref "C106")
      (value "100nF.")
      (footprint "eagle-import:C0805")
      (fields (field (name "MPN") "CC0805KRX7R9BB104"))
      (libsource (lib "eagle-import") (part "CERAMIC-100NF-50V-10%-X7R(0805)"))
    )
    (comp (ref "C107")
      (value "100u")
      (footprint "eagle-import:C1206")
      (fields (field (name "MPN") "GRM31CR60J107ME39L"))
      (libsource (lib "eagle-import") (part "CERAMIC-100UF-6.3V-20%-X5R(1206)"))
    )
    (comp (ref "C108")
      (value "100u")
      (footprint "eagle-import:C1206")
      (fields (field (name "MPN") "GRM31CR60J107ME39L"))
      (libsource (lib "eagle-import") (part "CERAMIC-100UF-6.3V-20%-X5R(1206)"))
    )
    (comp (ref "C109")
      (value "2.2nF")
      (footprint "eagle-import:C0805")
      (fields (field (name "MPN") "CC0805KRX7R9BB104"))
      (libsource (lib "eagle-import") (part "CERAMIC-100NF-50V-10%-X7R(0805)"))
    )
    (comp (ref "C110")
      (value "100nF")
      (footprint "eagle-import:C0805")
      (fields (field (name "MPN") "CC0805KRX7R9BB104"))
      (libsource (lib "eagle-import") (part "CERAMIC-100NF-50V-10%-X7R(0805)"))
    )
    (comp (ref "D1")
      (value "1N5817")
      (footprint "eagle-import:DO-214AC_SLIM")
      (libsource (lib "eagle-import") (part "DIODE-GEN-PURPOSE-1KV-1A(DO-214AC)DO-214AC/1206"))
    )
    (comp (ref "D2")
      (value "1N5817.")
      (footprint "eagle-import:DO-214AC_SLIM")
      (libsource (lib "eagle-import") (part "DIODE-GEN-PURPOSE-1KV-1A(DO-214AC)DO-214AC/1206"))
    )
    (comp (ref "D4")
      (value "Zen11")
      (footprint "eagle-import:SOD-123_MINI-SMA")
      (libsource (lib "eagle-import") (part "CGRM400-G1"))
    )
    (comp (ref "D101")
      (value "Zen15")
      (footprint "eagle-import:DO214AA")
      (libsource (lib "eagle-import") (part "SM6T"))
    )
    (comp (ref "D102")
      (value "1N4007")
      (footprint "eagle-import:DO-214AC")
      (libsource (lib "eagle-import") (part "DIODE-GEN-PURPOSE-1KV-1A(DO-214AC)"))
    )
    (comp (ref "D103")
      (value "1N4007")
      (footprint "eagle-import:DO-214AC")
      (libsource (lib "eagle-import") (part "DIODE-GEN-PURPOSE-1KV-1A(DO-214AC)"))
    )
    (comp (ref "D104")
      (value "SM6TDO214AA_BI")
      (footprint "eagle-import:DO214AA_BI")
      (libsource (lib "eagle-import") (part "SM6TDO214AA_BI"))
    )
    (comp (ref "D105")
      (value "1N4007.")
      (footprint "eagle-import:DO-214AC")
      (fields (field (name "MPN") "1N4007"))
      (libsource (lib "eagle-import") (part "DIODE-GEN-PURPOSE-1KV-1A(DO-214AC)"))
    )
    (comp (ref "D106")
      (value "1N4007.")
      (footprint "eagle-import:DO-214AC")
      (fields (field (name "MPN") "1N4007"))
      (libsource (lib "eagle-import") (part "DIODE-GEN-PURPOSE-1KV-1A(DO-214AC)"))
    )
    (comp (ref "D107")
      (value "1N5817")
      (footprint "eagle-import:DO-214AC_SLIM")
      (libsource (lib "eagle-import") (part "DIODE-GEN-PURPOSE-1KV-1A(DO-214AC)DO-214AC/1206"))
    )
    (comp (ref "D108")
      (value "1N5817.")
      (footprint "eagle-import:DO-214AC_SLIM")
      (libsource (lib "eagle-import") (part "DIODE-GEN-PURPOSE-1KV-1A(DO-214AC)DO-214AC/1206"))
    )
    (comp (ref "D109")
      (value "1N5817.")
      (footprint "eagle-import:DO-214AC_SLIM")
      (libsource (lib "eagle-import") (part "DIODE-GEN-PURPOSE-1KV-1A(DO-214AC)DO-214AC/1206"))
    )
    (comp (ref "D110")
      (value "1N5817")
      (footprint "eagle-import:DO-214AC_SLIM")
      (libsource (lib "eagle-import") (part "DIODE-GEN-PURPOSE-1KV-1A(DO-214AC)DO-214AC/1206"))
    )
    (comp (ref "D112")
      (value "1N4007")
      (footprint "eagle-import:DO-214AC")
      (libsource (lib "eagle-import") (part "DIODE-GEN-PURPOSE-1KV-1A(DO-214AC)"))
    )
    (comp (ref "FID101")
      (value "FIDUCIAL")
      (footprint "eagle-import:FIDUCIAL_1MM")
      (libsource (lib "eagle-import") (part "FIDUCIAL"))
    )
    (comp (ref "FID102")
      (value "FIDUCIAL")
      (footprint "eagle-import:FIDUCIAL_1MM")
      (libsource (lib "eagle-import") (part "FIDUCIAL"))
    )
    (comp (ref "FID103")
      (value "FIDUCIAL")
      (footprint "eagle-import:FIDUCIAL_1MM")
      (libsource (lib "eagle-import") (part "FIDUCIAL"))
    )
    (comp (ref "FID104")
      (value "FIDUCIAL")
      (footprint "eagle-import:FIDUCIAL_1MM")
      (libsource (lib "eagle-import") (part "FIDUCIAL"))
    )
    (comp (ref "IC101")
      (value "LM2904")
      (footprint "eagle-import:SO08")
      (libsource (lib "eagle-import") (part "LM358D"))
    )
    (comp (ref "IC102")
      (value "78L06")
      (footprint "eagle-import:SOT89_ROUND")
      (libsource (lib "eagle-import") (part "78LXXSOT89_ROUND"))
    )
    (comp (ref "IC104")
      (value "78L10")
      (footprint "eagle-import:SOT89_ROUND")
      (libsource (lib "eagle-import") (part "78LXXSOT89_ROUND"))
    )
    (comp (ref "IC105")
      (value "4028")
      (footprint "eagle-import:SO16")
      (libsource (lib "eagle-import") (part "4028D"))
    )
    (comp (ref "IC107")
      (value "ULN2004")
      (footprint "eagle-import:SO16")
      (libsource (lib "eagle-import") (part "ULN2004AD"))
    )
    (comp (ref "IC108")
      (value "LM339")
      (footprint "eagle-import:SO14")
      (libsource (lib "eagle-import") (part "LM339D"))
    )
    (comp (ref "IC109")
      (value "317TO202H_NOHOLE")
      (footprint "eagle-import:TO220H_NOHOLE")
      (libsource (lib "eagle-import") (part "317TO202H_NOHOLE"))
    )
    (comp (ref "IC110")
      (value "555")
      (footprint "eagle-import:SO08")
      (libsource (lib "eagle-import") (part "555DNE"))
    )
    (comp (ref "IC111")
      (value "4538")
      (footprint "eagle-import:SO16")
      (libsource (lib "eagle-import") (part "4538D"))
    )
    (comp (ref "JP101")
      (value "JP2EJP2_SMALLPADS")
      (footprint "eagle-import:JP2_SMALLPADS")
      (libsource (lib "eagle-import") (part "JP2EJP2_SMALLPADS"))
    )
    (comp (ref "JP102")
      (value "JP2EJP2_SMALLPADS")
      (footprint "eagle-import:JP2_SMALLPADS")
      (libsource (lib "eagle-import") (part "JP2EJP2_SMALLPADS"))
    )
    (comp (ref "JP103")
      (value "JP2EJP2_SMALLPADS")
      (footprint "eagle-import:JP2_SMALLPADS")
      (libsource (lib "eagle-import") (part "JP2EJP2_SMALLPADS"))
    )
    (comp (ref "JP104")
      (value "JP2EJP2_SMALLPADS")
      (footprint "eagle-import:JP2_SMALLPADS")
      (libsource (lib "eagle-import") (part "JP2EJP2_SMALLPADS"))
    )
    (comp (ref "JP105")
      (value "JP2E_ORIG")
      (footprint "eagle-import:JP2_ORIG_SMALLPADS")
      (libsource (lib "eagle-import") (part "JP2E_ORIG"))
    )
    (comp (ref "LED101")
      (value "LEDLD260")
      (footprint "eagle-import:LD260")
      (libsource (lib "eagle-import") (part "LEDLD260"))
    )
    (comp (ref "LED102")
      (value "LEDLD260")
      (footprint "eagle-import:LD260")
      (libsource (lib "eagle-import") (part "LEDLD260"))
    )
    (comp (ref "LED103")
      (value "LEDLD260")
      (footprint "eagle-import:LD260")
      (libsource (lib "eagle-import") (part "LEDLD260"))
    )
    (comp (ref "LED104")
      (value "LEDLD260")
      (footprint "eagle-import:LD260")
      (libsource (lib "eagle-import") (part "LEDLD260"))
    )
    (comp (ref "LED105")
      (value "LEDLD260")
      (footprint "eagle-import:LD260")
      (libsource (lib "eagle-import") (part "LEDLD260"))
    )
    (comp (ref "LED106")
      (value "LEDLD260")
      (footprint "eagle-import:LD260")
      (libsource (lib "eagle-import") (part "LEDLD260"))
    )
    (comp (ref "Q1")
      (value "J1")
      (footprint "eagle-import:SOT-23")
      (fields (field (name "MPN") "BSS138W-7-F"))
      (libsource (lib "eagle-import") (part "SMD-MOSFET-N-CH-50V-200MA-BSS138W-7-F(SOT-23)"))
    )
    (comp (ref "Q2")
      (value "BA")
      (footprint "eagle-import:SOT89")
      (libsource (lib "eagle-import") (part "PNP-TRANSISTOR_SOT89"))
    )
    (comp (ref "Q3")
      (value "J1")
      (footprint "eagle-import:SOT-23")
      (fields (field (name "MPN") "BSS138W-7-F"))
      (libsource (lib "eagle-import") (part "SMD-MOSFET-N-CH-50V-200MA-BSS138W-7-F(SOT-23)"))
    )
    (comp (ref "Q101")
      (value "BA.")
      (footprint "eagle-import:SOT89")
      (libsource (lib "eagle-import") (part "PNP-TRANSISTOR_SOT89"))
    )
    (comp (ref "Q102")
      (value "BA.")
      (footprint "eagle-import:SOT89")
      (libsource (lib "eagle-import") (part "PNP-TRANSISTOR_SOT89"))
    )
    (comp (ref "Q103")
      (value "MY")
      (footprint "eagle-import:SOT89")
      (libsource (lib "eagle-import") (part "NPN-TRANSISTOR_SOT89"))
    )
    (comp (ref "Q104")
      (value "BA")
      (footprint "eagle-import:SOT89")
      (libsource (lib "eagle-import") (part "PNP-TRANSISTOR_SOT89"))
    )
    (comp (ref "Q105")
      (value "BA")
      (footprint "eagle-import:SOT89")
      (libsource (lib "eagle-import") (part "PNP-TRANSISTOR_SOT89"))
    )
    (comp (ref "Q106")
      (value "J1")
      (footprint "eagle-import:SOT-23")
      (fields (field (name "MPN") "BSS138W-7-F"))
      (libsource (lib "eagle-import") (part "SMD-MOSFET-N-CH-50V-200MA-BSS138W-7-F(SOT-23)"))
    )
    (comp (ref "Q107")
      (value "J1")
      (footprint "eagle-import:SOT-23")
      (fields (field (name "MPN") "BSS138W-7-F"))
      (libsource (lib "eagle-import") (part "SMD-MOSFET-N-CH-50V-200MA-BSS138W-7-F(SOT-23)"))
    )
    (comp (ref "R1")
      (value "104")
      (footprint "eagle-import:R0805")
      (fields (field (name "MPN") "RC0805FR-0710KL"))
      (libsource (lib "eagle-import") (part "SMD-RES-10K-1%-1/8W(0805)"))
    )
    (comp (ref "R2")
      (value "104")
      (footprint "eagle-import:R0805")
      (fields (field (name "MPN") "RC0805FR-0710KL"))
      (libsource (lib "eagle-import") (part "SMD-RES-10K-1%-1/8W(0805)"))
    )
    (comp (ref "R3")
      (value "104")
      (footprint "eagle-import:R0805")
      (fields (field (name "MPN") "RC0805FR-0710KL"))
      (libsource (lib "eagle-import") (part "SMD-RES-10K-1%-1/8W(0805)"))
    )
    (comp (ref "R4")
      (value "100")
      (footprint "eagle-import:R0805")
      (fields (field (name "MPN") "RC0805JR-07220RL"))
      (libsource (lib "eagle-import") (part "SMD-RES-220R-5%-1/8W(0805)"))
    )
    (comp (ref "R5")
      (value "13")
      (footprint "eagle-import:R1206")
      (fields (field (name "MPN") "RC1206JR-0713RL"))
      (libsource (lib "eagle-import") (part "SMD-RES-13R-5%-1/4W(1206)"))
    )
    (comp (ref "R6")
      (value "2201")
      (footprint "eagle-import:R0805")
      (fields (field (name "MPN") "RC0805JR-071KL"))
      (libsource (lib "eagle-import") (part "SMD-RES-1K-5%-1/8W(0805)"))
    )
    (comp (ref "R8")
      (value "4701")
      (footprint "eagle-import:R0805")
      (fields (field (name "MPN") "RC0805JR-074K7L"))
      (libsource (lib "eagle-import") (part "SMD-RES-4.7K-5%-1/8W(0805)"))
    )
    (comp (ref "R9")
      (value "13")
      (footprint "eagle-import:R1206")
      (fields (field (name "MPN") "RC1206JR-0713RL"))
      (libsource (lib "eagle-import") (part "SMD-RES-13R-5%-1/4W(1206)"))
    )
    (comp (ref "R10")
      (value "104")
      (footprint "eagle-import:R0805")
      (fields (field (name "MPN") "RC0805JR-074K7L"))
      (libsource (lib "eagle-import") (part "SMD-RES-4.7K-5%-1/8W(0805)"))
    )
    (comp (ref "R12")
      (value "2R")
      (footprint "eagle-import:R0805")
      (fields (field (name "MPN") "RC0805JR-072K2L"))
      (libsource (lib "eagle-import") (part "SMD-RES-2.2K-5%-1/8W(0805)"))
    )
    (comp (ref "R13")
      (value "2R")
      (footprint "eagle-import:R0805")
      (fields (field (name "MPN") "RC0805JR-072K2L"))
      (libsource (lib "eagle-import") (part "SMD-RES-2.2K-5%-1/8W(0805)"))
    )
    (comp (ref "R101")
      (value "102")
      (footprint "eagle-import:R0805")
      (fields (field (name "MPN") "RC0805JR-071KL"))
      (libsource (lib "eagle-import") (part "SMD-RES-1K-5%-1/8W(0805)"))
    )
    (comp (ref "R102")
      (value "13")
      (footprint "eagle-import:R1206")
      (fields (field (name "MPN") "RC1206JR-0713RL"))
      (libsource (lib "eagle-import") (part "SMD-RES-13R-5%-1/4W(1206)"))
    )
    (comp (ref "R103")
      (value "R_user")
      (footprint "eagle-import:R0805")
      (libsource (lib "eagle-import") (part "R-EU_R0805"))
    )
    (comp (ref "R104")
      (value "R_user")
      (footprint "eagle-import:R0805")
      (libsource (lib "eagle-import") (part "R-EU_R0805"))
    )
    (comp (ref "R105")
      (value "4701")
      (footprint "eagle-import:R0805")
      (fields (field (name "MPN") "RC0805JR-074K7L"))
      (libsource (lib "eagle-import") (part "SMD-RES-4.7K-5%-1/8W(0805)"))
    )
    (comp (ref "R106")
      (value "13")
      (footprint "eagle-import:R1206")
      (fields (field (name "MPN") "RC1206JR-0713RL"))
      (libsource (lib "eagle-import") (part "SMD-RES-13R-5%-1/4W(1206)"))
    )
    (comp (ref "R107")
      (value "1002")
      (footprint "eagle-import:R0805")
      (fields (field (name "MPN") "RC0805FR-0710KL"))
      (libsource (lib "eagle-import") (part "SMD-RES-10K-1%-1/8W(0805)"))
    )
    (comp (ref "R108")
      (value "1002")
      (footprint "eagle-import:R0805")
      (fields (field (name "MPN") "RC0805FR-0710KL"))
      (libsource (lib "eagle-import") (part "SMD-RES-10K-1%-1/8W(0805)"))
    )
    (comp (ref "R109")
      (value "104")
      (footprint "eagle-import:R0805")
      (fields (field (name "MPN") "RC0805FR-0710KL"))
      (libsource (lib "eagle-import") (part "SMD-RES-10K-1%-1/8W(0805)"))
    )
    (comp (ref "R110")
      (value "104")
      (footprint "eagle-import:R0805")
      (fields (field (name "MPN") "RC0805FR-0710KL"))
      (libsource (lib "eagle-import") (part "SMD-RES-10K-1%-1/8W(0805)"))
    )
    (comp (ref "R111")
      (value "104")
      (footprint "eagle-import:R0805")
      (fields (field (name "MPN") "RC0805FR-0710KL"))
      (libsource (lib "eagle-import") (part "SMD-RES-10K-1%-1/8W(0805)"))
    )
    (comp (ref "R112")
      (value "102")
      (footprint "eagle-import:R0805")
      (fields (field (name "MPN") "RC0805JR-071KL"))
      (libsource (lib "eagle-import") (part "SMD-RES-1K-5%-1/8W(0805)"))
    )
    (comp (ref "R113")
      (value "1002")
      (footprint "eagle-import:R0805")
      (fields (field (name "MPN") "RC0805JR-071KL"))
      (libsource (lib "eagle-import") (part "SMD-RES-1K-5%-1/8W(0805)"))
    )
    (comp (ref "R114")
      (value "1002")
      (footprint "eagle-import:R0805")
      (fields (field (name "MPN") "RC0805JR-071KL"))
      (libsource (lib "eagle-import") (part "SMD-RES-1K-5%-1/8W(0805)"))
    )
    (comp (ref "R115")
      (value "102")
      (footprint "eagle-import:R0805")
      (fields (field (name "MPN") "RC0805JR-07220RL"))
      (libsource (lib "eagle-import") (part "SMD-RES-220R-5%-1/8W(0805)"))
    )
    (comp (ref "R116")
      (value "4701")
      (footprint "eagle-import:R0805")
      (fields (field (name "MPN") "RC0805JR-074K7L"))
      (libsource (lib "eagle-import") (part "SMD-RES-4.7K-5%-1/8W(0805)"))
    )
    (comp (ref "R117")
      (value "2702")
      (footprint "eagle-import:R0805")
      (fields (field (name "MPN") "RC0805JR-074K7L"))
      (libsource (lib "eagle-import") (part "SMD-RES-4.7K-5%-1/8W(0805)"))
    )
    (comp (ref "R119")
      (value "2201")
      (footprint "eagle-import:R0805")
      (fields (field (name "MPN") "RC0805JR-072K2L"))
      (libsource (lib "eagle-import") (part "SMD-RES-2.2K-5%-1/8W(0805)"))
    )
    (comp (ref "R120")
      (value "1002")
      (footprint "eagle-import:R0805")
      (fields (field (name "MPN") "RC0805FR-0710KL"))
      (libsource (lib "eagle-import") (part "SMD-RES-10K-1%-1/8W(0805)"))
    )
    (comp (ref "R121")
      (value "1502")
      (footprint "eagle-import:R0805")
      (fields (field (name "MPN") "RC0805FR-0710KL"))
      (libsource (lib "eagle-import") (part "SMD-RES-10K-1%-1/8W(0805)"))
    )
    (comp (ref "R122")
      (value "2702")
      (footprint "eagle-import:R0805")
      (fields (field (name "MPN") "RC0805JR-074K7L"))
      (libsource (lib "eagle-import") (part "SMD-RES-4.7K-5%-1/8W(0805)"))
    )
    (comp (ref "R123")
      (value "2702")
      (footprint "eagle-import:R0805")
      (fields (field (name "MPN") "RC0805JR-074K7L"))
      (libsource (lib "eagle-import") (part "SMD-RES-4.7K-5%-1/8W(0805)"))
    )
    (comp (ref "R124")
      (value "1002")
      (footprint "eagle-import:R0805")
      (fields (field (name "MPN") "RC0805FR-0710KL"))
      (libsource (lib "eagle-import") (part "SMD-RES-10K-1%-1/8W(0805)"))
    )
    (comp (ref "R125")
      (value "104")
      (footprint "eagle-import:R0805")
      (fields (field (name "MPN") "RC0805FR-0710KL"))
      (libsource (lib "eagle-import") (part "SMD-RES-10K-1%-1/8W(0805)"))
    )
    (comp (ref "R126")
      (value "4701")
      (footprint "eagle-import:R0805")
      (fields (field (name "MPN") "RC0805JR-074K7L"))
      (libsource (lib "eagle-import") (part "SMD-RES-4.7K-5%-1/8W(0805)"))
    )
    (comp (ref "R127")
      (value "47")
      (footprint "eagle-import:V235_17_1MM")
      (libsource (lib "eagle-import") (part "R-EU_V235/17_1MM"))
    )
    (comp (ref "R128")
      (value "102")
      (footprint "eagle-import:R0805")
      (fields (field (name "MPN") "RC0805JR-071KL"))
      (libsource (lib "eagle-import") (part "SMD-RES-1K-5%-1/8W(0805)"))
    )
    (comp (ref "R129")
      (value "47")
      (footprint "eagle-import:V235_17_1MM")
      (libsource (lib "eagle-import") (part "R-EU_V235/17_1MM"))
    )
    (comp (ref "R130")
      (value "104")
      (footprint "eagle-import:R0805")
      (fields (field (name "MPN") "RC0805FR-0710KL"))
      (libsource (lib "eagle-import") (part "SMD-RES-10K-1%-1/8W(0805)"))
    )
    (comp (ref "R131")
      (value "1502")
      (footprint "eagle-import:R0805")
      (fields (field (name "MPN") "RC0805FR-0710KL"))
      (libsource (lib "eagle-import") (part "SMD-RES-10K-1%-1/8W(0805)"))
    )
    (comp (ref "R132")
      (value "1002")
      (footprint "eagle-import:R0805")
      (fields (field (name "MPN") "RC0805FR-0710KL"))
      (libsource (lib "eagle-import") (part "SMD-RES-10K-1%-1/8W(0805)"))
    )
    (comp (ref "R133")
      (value "2201")
      (footprint "eagle-import:R0805")
      (fields (field (name "MPN") "RC0805JR-072K2L"))
      (libsource (lib "eagle-import") (part "SMD-RES-2.2K-5%-1/8W(0805)"))
    )
    (comp (ref "R134")
      (value "13")
      (footprint "eagle-import:R1206")
      (fields (field (name "MPN") "RC1206JR-0713RL"))
      (libsource (lib "eagle-import") (part "SMD-RES-13R-5%-1/4W(1206)"))
    )
    (comp (ref "R135")
      (value "104")
      (footprint "eagle-import:R0805")
      (fields (field (name "MPN") "RC0805FR-0710KL"))
      (libsource (lib "eagle-import") (part "SMD-RES-10K-1%-1/8W(0805)"))
    )
    (comp (ref "R136")
      (value "47")
      (footprint "eagle-import:V235_17_1MM")
      (libsource (lib "eagle-import") (part "R-EU_V235/17_1MM"))
    )
    (comp (ref "R137")
      (value "47")
      (footprint "eagle-import:V235_17_1MM")
      (libsource (lib "eagle-import") (part "R-EU_V235/17_1MM"))
    )
    (comp (ref "R138")
      (value "100")
      (footprint "eagle-import:R0805")
      (fields (field (name "MPN") "RC0805JR-072K2L"))
      (libsource (lib "eagle-import") (part "SMD-RES-2.2K-5%-1/8W(0805)"))
    )
    (comp (ref "R140")
      (value "2702")
      (footprint "eagle-import:R0805")
      (fields (field (name "MPN") "RC0805FR-0710KL"))
      (libsource (lib "eagle-import") (part "SMD-RES-10K-1%-1/8W(0805)"))
    )
    (comp (ref "R141")
      (value "104")
      (footprint "eagle-import:R0805")
      (fields (field (name "MPN") "RC0805FR-0710KL"))
      (libsource (lib "eagle-import") (part "SMD-RES-10K-1%-1/8W(0805)"))
    )
    (comp (ref "R142")
      (value "(1000)")
      (footprint "eagle-import:R0805")
      (fields (field (name "MPN") "RC0805JR-07100RL"))
      (libsource (lib "eagle-import") (part "SMD-RES-100R-5%-1/8W(0805)"))
    )
    (comp (ref "R143")
      (value "(101)")
      (footprint "eagle-import:R0805")
      (fields (field (name "MPN") "RC0805JR-07100RL"))
      (libsource (lib "eagle-import") (part "SMD-RES-100R-5%-1/8W(0805)"))
    )
    (comp (ref "R144")
      (value "(1002)")
      (footprint "eagle-import:R0805")
      (fields (field (name "MPN") "RC0805FR-0710KL"))
      (libsource (lib "eagle-import") (part "SMD-RES-10K-1%-1/8W(0805)"))
    )
    (comp (ref "R145")
      (value "2702")
      (footprint "eagle-import:R0805")
      (fields (field (name "MPN") "RC0805JR-074K7L"))
      (libsource (lib "eagle-import") (part "SMD-RES-4.7K-5%-1/8W(0805)"))
    )
    (comp (ref "R146")
      (value "1002")
      (footprint "eagle-import:R0805")
      (fields (field (name "MPN") "RC0805JR-074K7L"))
      (libsource (lib "eagle-import") (part "SMD-RES-4.7K-5%-1/8W(0805)"))
    )
    (comp (ref "SJ101")
      (value "SJ")
      (footprint "eagle-import:SJ")
      (libsource (lib "eagle-import") (part "solder-jumper_SJ"))
    )
    (comp (ref "SJMP")
      (value "SJ")
      (footprint "eagle-import:SJ")
      (libsource (lib "eagle-import") (part "SJ"))
    )
    (comp (ref "START")
      (value "TPSB2.0")
      (footprint "eagle-import:B2.0")
      (libsource (lib "eagle-import") (part "TPSB2.0"))
    )
    (comp (ref "TP1")
      (value "TPSB2.0")
      (footprint "eagle-import:B2.0")
      (libsource (lib "eagle-import") (part "TPSB2.0"))
    )
    (comp (ref "TP2")
      (value "TPSB2.0")
      (footprint "eagle-import:B2.0")
      (libsource (lib "eagle-import") (part "TPSB2.0"))
    )
    (comp (ref "TP3")
      (value "TPSB2.0")
      (footprint "eagle-import:B2.0")
      (libsource (lib "eagle-import") (part "TPSB2.0"))
    )
    (comp (ref "TP4")
      (value "TPSB2.0")
      (footprint "eagle-import:B2.0")
      (libsource (lib "eagle-import") (part "TPSB2.0"))
    )
    (comp (ref "TP5")
      (value "TPSB2.0")
      (footprint "eagle-import:B2.0")
      (libsource (lib "eagle-import") (part "TPSB2.0"))
    )
    (comp (ref "TP6")
      (value "TPSB2.0")
      (footprint "eagle-import:B2.0")
      (libsource (lib "eagle-import") (part "TPSB2.0"))
    )
    (comp (ref "TP7")
      (value "TPSB2.0")
      (footprint "eagle-import:B2.0")
      (libsource (lib "eagle-import") (part "TPSB2.0"))
    )
    (comp (ref "TP8")
      (value "TPSB2.0")
      (footprint "eagle-import:B2.0")
      (libsource (lib "eagle-import") (part "TPSB2.0"))
    )
    (comp (ref "TP9")
      (value "TPSB2.0")
      (footprint "eagle-import:B2.0")
      (libsource (lib "eagle-import") (part "TPSB2.0"))
    )
    (comp (ref "TP10")
      (value "TPSB2.0")
      (footprint "eagle-import:B2.0")
      (libsource (lib "eagle-import") (part "TPSB2.0"))
    )
    (comp (ref "TP11")
      (value "TPSB2.0")
      (footprint "eagle-import:B2.0")
      (libsource (lib "eagle-import") (part "TPSB2.0"))
    )
    (comp (ref "TP12")
      (value "TPSB2.0")
      (footprint "eagle-import:B2.0")
      (libsource (lib "eagle-import") (part "TPSB2.0"))
    )
    (comp (ref "TP13")
      (value "TPSB2.0")
      (footprint "eagle-import:B2.0")
      (libsource (lib "eagle-import") (part "TPSB2.0"))
    )
    (comp (ref "TP16")
      (value "TPSB2.0")
      (footprint "eagle-import:B2.0")
      (libsource (lib "eagle-import") (part "TPSB2.0"))
    )
    (comp (ref "TP17")
      (value "TPSB2.0")
      (footprint "eagle-import:B2.0")
      (libsource (lib "eagle-import") (part "TPSB2.0"))
    )
    (comp (ref "TP18")
      (value "TPSB2.0")
      (footprint "eagle-import:B2.0")
      (libsource (lib "eagle-import") (part "TPSB2.0"))
    )
    (comp (ref "TP19")
      (value "TPSB2.0")
      (footprint "eagle-import:B2.0")
      (libsource (lib "eagle-import") (part "TPSB2.0"))
    )
    (comp (ref "TP21")
      (value "TPSB2.0")
      (footprint "eagle-import:B2.0")
      (libsource (lib "eagle-import") (part "TPSB2.0"))
    )
    (comp (ref "TP22")
      (value "TPSB2.0")
      (footprint "eagle-import:B2.0")
      (libsource (lib "eagle-import") (part "TPSB2.0"))
    )
    (comp (ref "TP23")
      (value "TPSB2.0")
      (footprint "eagle-import:B2.0")
      (libsource (lib "eagle-import") (part "TPSB2.0"))
    )
    (comp (ref "TP24")
      (value "TPSB1,27")
      (footprint "eagle-import:B1,27")
      (libsource (lib "eagle-import") (part "TPSB1,27"))
    )
    (comp (ref "TP25")
      (value "TPSB2.0")
      (footprint "eagle-import:B2.0")
      (libsource (lib "eagle-import") (part "TPSB2.0"))
    )
    (comp (ref "TP26")
      (value "TPSB2.0")
      (footprint "eagle-import:B2.0")
      (libsource (lib "eagle-import") (part "TPSB2.0"))
    )
    (comp (ref "X101")
      (value "CON_BMWV2")
      (footprint "eagle-import:24-PIN_V2")
      (libsource (lib "eagle-import") (part "CON_BMWV2"))
    )
    (comp (ref "X102")
      (value "22-23-2021")
      (footprint "eagle-import:22-23-2021")
      (fields (field (name "MF") "MOLEX"))
      (libsource (lib "eagle-import") (part "22-23-2021"))
    )
    (comp (ref "X103")
      (value "22-23-2051")
      (footprint "eagle-import:22-23-2051")
      (fields (field (name "MF") "MOLEX"))
      (libsource (lib "eagle-import") (part "22-23-2051"))
    )
    (comp (ref "3")
      (value "2081-1132")
      (footprint "eagle-import:12-PIN")
      (libsource (lib "eagle-import") (part "2081-1132"))
    )
    (comp (ref "4")
      (value "2081-1132")
      (footprint "eagle-import:12-PIN")
      (libsource (lib "eagle-import") (part "2081-1132"))
    )
    (comp (ref "6V1")
      (value "TPSB2.0")
      (footprint "eagle-import:B2.0")
      (libsource (lib "eagle-import") (part "TPSB2.0"))
    )
    (comp (ref "10V1")
      (value "TPSB2.0")
      (footprint "eagle-import:B2.0")
      (libsource (lib "eagle-import") (part "TPSB2.0"))
    )
    (comp (ref "C1")
      (value "100u")
      (footprint "eagle-import:C1206")
      (fields (field (name "MPN") "GRM31CR60J107ME39L"))
      (libsource (lib "eagle-import") (part "CERAMIC-100UF-6.3V-20%-X5R(1206)"))
    )
    (comp (ref "C3")
      (value "100u")
      (footprint "eagle-import:C1206")
      (fields (field (name "MPN") "GRM31CR60J107ME39L"))
      (libsource (lib "eagle-import") (part "CERAMIC-100UF-6.3V-20%-X5R(1206)"))
    )
    (comp (ref "C4")
      (value "100nF,")
      (footprint "eagle-import:C0805")
      (fields (field (name "MPN") "CC0805KRX7R9BB104"))
      (libsource (lib "eagle-import") (part "CERAMIC-100NF-50V-10%-X7R(0805)"))
    )
    (comp (ref "C5")
      (value "4.7u")
      (footprint "eagle-import:C0805")
      (fields (field (name "MPN") "CC0805KKX5R8BB475"))
      (libsource (lib "eagle-import") (part "CERAMIC-4.7UF-25V-10%-X5R(0805)"))
    )
    (comp (ref "C6")
      (value "100nF.")
      (footprint "eagle-import:C0805")
      (fields (field (name "MPN") "CC0805KRX7R9BB104"))
      (libsource (lib "eagle-import") (part "CERAMIC-100NF-50V-10%-X7R(0805)"))
    )
    (comp (ref "C7")
      (value "100nF.")
      (footprint "eagle-import:C0805")
      (fields (field (name "MPN") "CC0805KRX7R9BB104"))
      (libsource (lib "eagle-import") (part "CERAMIC-100NF-50V-10%-X7R(0805)"))
    )
    (comp (ref "C8")
      (value "2.2nF")
      (footprint "eagle-import:C0805")
      (fields (field (name "MPN") "CC0805KRX7R9BB104"))
      (libsource (lib "eagle-import") (part "CERAMIC-100NF-50V-10%-X7R(0805)"))
    )
    (comp (ref "C9")
      (value "100nF")
      (footprint "eagle-import:C0805")
      (fields (field (name "MPN") "CC0805KRX7R9BB104"))
      (libsource (lib "eagle-import") (part "CERAMIC-100NF-50V-10%-X7R(0805)"))
    )
    (comp (ref "C10")
      (value "100nF")
      (footprint "eagle-import:C0805")
      (fields (field (name "MPN") "CC0805KRX7R9BB104"))
      (libsource (lib "eagle-import") (part "CERAMIC-100NF-50V-10%-X7R(0805)"))
    )
    (comp (ref "C11")
      (value "100nF,")
      (footprint "eagle-import:C0805")
      (fields (field (name "MPN") "CC0805KRX7R9BB104"))
      (libsource (lib "eagle-import") (part "CERAMIC-100NF-50V-10%-X7R(0805)"))
    )
    (comp (ref "C12")
      (value "4.7u")
      (footprint "eagle-import:C0805")
      (fields (field (name "MPN") "CC0805KKX5R8BB475"))
      (libsource (lib "eagle-import") (part "CERAMIC-4.7UF-25V-10%-X5R(0805)"))
    )
    (comp (ref "C13")
      (value "10u")
      (footprint "eagle-import:C1206")
      (fields (field (name "MPN") "GRM31CR60J107ME39L"))
      (libsource (lib "eagle-import") (part "CERAMIC-100UF-6.3V-20%-X5R(1206)"))
    )
    (comp (ref "D3")
      (value "1N4007")
      (footprint "eagle-import:DO-214AC")
      (libsource (lib "eagle-import") (part "DIODE-GEN-PURPOSE-1KV-1A(DO-214AC)"))
    )
    (comp (ref "D5")
      (value "1N4007")
      (footprint "eagle-import:DO-214AC")
      (libsource (lib "eagle-import") (part "DIODE-GEN-PURPOSE-1KV-1A(DO-214AC)"))
    )
    (comp (ref "D6")
      (value "1N4007.")
      (footprint "eagle-import:DO-214AC")
      (fields (field (name "MPN") "1N4007"))
      (libsource (lib "eagle-import") (part "DIODE-GEN-PURPOSE-1KV-1A(DO-214AC)"))
    )
    (comp (ref "D7")
      (value "1N5817")
      (footprint "eagle-import:DO-214AC_SLIM")
      (libsource (lib "eagle-import") (part "DIODE-GEN-PURPOSE-1KV-1A(DO-214AC)DO-214AC/1206"))
    )
    (comp (ref "D8")
      (value "1N5817.")
      (footprint "eagle-import:DO-214AC_SLIM")
      (libsource (lib "eagle-import") (part "DIODE-GEN-PURPOSE-1KV-1A(DO-214AC)DO-214AC/1206"))
    )
    (comp (ref "D9")
      (value "1N5817.")
      (footprint "eagle-import:DO-214AC_SLIM")
      (libsource (lib "eagle-import") (part "DIODE-GEN-PURPOSE-1KV-1A(DO-214AC)DO-214AC/1206"))
    )
    (comp (ref "D10")
      (value "1N5817")
      (footprint "eagle-import:DO-214AC_SLIM")
      (libsource (lib "eagle-import") (part "DIODE-GEN-PURPOSE-1KV-1A(DO-214AC)DO-214AC/1206"))
    )
    (comp (ref "D11")
      (value "1N4007.")
      (footprint "eagle-import:DO-214AC")
      (fields (field (name "MPN") "1N4007"))
      (libsource (lib "eagle-import") (part "DIODE-GEN-PURPOSE-1KV-1A(DO-214AC)"))
    )
    (comp (ref "D12")
      (value "1N4007.")
      (footprint "eagle-import:DO-214AC")
      (fields (field (name "MPN") "1N4007"))
      (libsource (lib "eagle-import") (part "DIODE-GEN-PURPOSE-1KV-1A(DO-214AC)"))
    )
    (comp (ref "D13")
      (value "Zen15")
      (footprint "eagle-import:DO214AA")
      (libsource (lib "eagle-import") (part "SM6T"))
    )
    (comp (ref "D14")
      (value "SM6TDO214AA_BI")
      (footprint "eagle-import:DO214AA_BI")
      (libsource (lib "eagle-import") (part "SM6TDO214AA_BI"))
    )
    (comp (ref "D15")
      (value "1N5817")
      (footprint "eagle-import:DO-214AC_SLIM")
      (libsource (lib "eagle-import") (part "DIODE-GEN-PURPOSE-1KV-1A(DO-214AC)DO-214AC/1206"))
    )
    (comp (ref "D16")
      (value "1N5817.")
      (footprint "eagle-import:DO-214AC_SLIM")
      (libsource (lib "eagle-import") (part "DIODE-GEN-PURPOSE-1KV-1A(DO-214AC)DO-214AC/1206"))
    )
    (comp (ref "D17")
      (value "Zen11")
      (footprint "eagle-import:SOD-123_MINI-SMA")
      (libsource (lib "eagle-import") (part "CGRM400-G1"))
    )
    (comp (ref "FID3")
      (value "FIDUCIAL")
      (footprint "eagle-import:FIDUCIAL_1MM")
      (libsource (lib "eagle-import") (part "FIDUCIAL"))
    )
    (comp (ref "FID4")
      (value "FIDUCIAL")
      (footprint "eagle-import:FIDUCIAL_1MM")
      (libsource (lib "eagle-import") (part "FIDUCIAL"))
    )
    (comp (ref "FID5")
      (value "FIDUCIAL")
      (footprint "eagle-import:FIDUCIAL_1MM")
      (libsource (lib "eagle-import") (part "FIDUCIAL"))
    )
    (comp (ref "FID6")
      (value "FIDUCIAL")
      (footprint "eagle-import:FIDUCIAL_1MM")
      (libsource (lib "eagle-import") (part "FIDUCIAL"))
    )
    (comp (ref "IC1")
      (value "4028")
      (footprint "eagle-import:SO16")
      (libsource (lib "eagle-import") (part "4028D"))
    )
    (comp (ref "IC2")
      (value "317TO202H_NOHOLE")
      (footprint "eagle-import:TO220H_NOHOLE")
      (libsource (lib "eagle-import") (part "317TO202H_NOHOLE"))
    )
    (comp (ref "IC3")
      (value "ULN2004")
      (footprint "eagle-import:SO16")
      (libsource (lib "eagle-import") (part "ULN2004AD"))
    )
    (comp (ref "IC4")
      (value "LM339")
      (footprint "eagle-import:SO14")
      (libsource (lib "eagle-import") (part "LM339D"))
    )
    (comp (ref "IC5")
      (value "78L06")
      (footprint "eagle-import:SOT89_ROUND")
      (libsource (lib "eagle-import") (part "78LXXSOT89_ROUND"))
    )
    (comp (ref "IC6")
      (value "555")
      (footprint "eagle-import:SO08")
      (libsource (lib "eagle-import") (part "555DNE"))
    )
    (comp (ref "IC7")
      (value "4538")
      (footprint "eagle-import:SO16")
      (libsource (lib "eagle-import") (part "4538D"))
    )
    (comp (ref "IC8")
      (value "78L10")
      (footprint "eagle-import:SOT89_ROUND")
      (libsource (lib "eagle-import") (part "78LXXSOT89_ROUND"))
    )
    (comp (ref "IC9")
      (value "LM2904")
      (footprint "eagle-import:SO08")
      (libsource (lib "eagle-import") (part "LM358D"))
    )
    (comp (ref "JP1")
      (value "JP2EJP2_SMALLPADS")
      (footprint "eagle-import:JP2_SMALLPADS")
      (libsource (lib "eagle-import") (part "JP2EJP2_SMALLPADS"))
    )
    (comp (ref "JP2")
      (value "JP2E_ORIG")
      (footprint "eagle-import:JP2_ORIG_SMALLPADS")
      (libsource (lib "eagle-import") (part "JP2E_ORIG"))
    )
    (comp (ref "JP3")
      (value "JP2EJP2_SMALLPADS")
      (footprint "eagle-import:JP2_SMALLPADS")
      (libsource (lib "eagle-import") (part "JP2EJP2_SMALLPADS"))
    )
    (comp (ref "JP4")
      (value "JP2EJP2_SMALLPADS")
      (footprint "eagle-import:JP2_SMALLPADS")
      (libsource (lib "eagle-import") (part "JP2EJP2_SMALLPADS"))
    )
    (comp (ref "JP5")
      (value "JP2EJP2_SMALLPADS")
      (footprint "eagle-import:JP2_SMALLPADS")
      (libsource (lib "eagle-import") (part "JP2EJP2_SMALLPADS"))
    )
    (comp (ref "LED1")
      (value "LEDLD260")
      (footprint "eagle-import:LD260")
      (libsource (lib "eagle-import") (part "LEDLD260"))
    )
    (comp (ref "LED2")
      (value "LEDLD260")
      (footprint "eagle-import:LD260")
      (libsource (lib "eagle-import") (part "LEDLD260"))
    )
    (comp (ref "LED3")
      (value "LEDLD260")
      (footprint "eagle-import:LD260")
      (libsource (lib "eagle-import") (part "LEDLD260"))
    )
    (comp (ref "LED4")
      (value "LEDLD260")
      (footprint "eagle-import:LD260")
      (libsource (lib "eagle-import") (part "LEDLD260"))
    )
    (comp (ref "LED5")
      (value "LEDLD260")
      (footprint "eagle-import:LD260")
      (libsource (lib "eagle-import") (part "LEDLD260"))
    )
    (comp (ref "LED6")
      (value "LEDLD260")
      (footprint "eagle-import:LD260")
      (libsource (lib "eagle-import") (part "LEDLD260"))
    )
    (comp (ref "Q4")
      (value "BA")
      (footprint "eagle-import:SOT89")
      (libsource (lib "eagle-import") (part "PNP-TRANSISTOR_SOT89"))
    )
    (comp (ref "Q5")
      (value "BA.")
      (footprint "eagle-import:SOT89")
      (libsource (lib "eagle-import") (part "PNP-TRANSISTOR_SOT89"))
    )
    (comp (ref "Q6")
      (value "BA.")
      (footprint "eagle-import:SOT89")
      (libsource (lib "eagle-import") (part "PNP-TRANSISTOR_SOT89"))
    )
    (comp (ref "Q7")
      (value "BA")
      (footprint "eagle-import:SOT89")
      (libsource (lib "eagle-import") (part "PNP-TRANSISTOR_SOT89"))
    )
    (comp (ref "Q8")
      (value "MY")
      (footprint "eagle-import:SOT89")
      (libsource (lib "eagle-import") (part "NPN-TRANSISTOR_SOT89"))
    )
    (comp (ref "Q9")
      (value "J1")
      (footprint "eagle-import:SOT-23")
      (fields (field (name "MPN") "BSS138W-7-F"))
      (libsource (lib "eagle-import") (part "SMD-MOSFET-N-CH-50V-200MA-BSS138W-7-F(SOT-23)"))
    )
    (comp (ref "Q10")
      (value "J1")
      (footprint "eagle-import:SOT-23")
      (fields (field (name "MPN") "BSS138W-7-F"))
      (libsource (lib "eagle-import") (part "SMD-MOSFET-N-CH-50V-200MA-BSS138W-7-F(SOT-23)"))
    )
    (comp (ref "Q11")
      (value "J1")
      (footprint "eagle-import:SOT-23")
      (fields (field (name "MPN") "BSS138W-7-F"))
      (libsource (lib "eagle-import") (part "SMD-MOSFET-N-CH-50V-200MA-BSS138W-7-F(SOT-23)"))
    )
    (comp (ref "Q12")
      (value "BA")
      (footprint "eagle-import:SOT89")
      (libsource (lib "eagle-import") (part "PNP-TRANSISTOR_SOT89"))
    )
    (comp (ref "Q13")
      (value "J1")
      (footprint "eagle-import:SOT-23")
      (fields (field (name "MPN") "BSS138W-7-F"))
      (libsource (lib "eagle-import") (part "SMD-MOSFET-N-CH-50V-200MA-BSS138W-7-F(SOT-23)"))
    )
    (comp (ref "R7")
      (value "47")
      (footprint "eagle-import:V235_17_1MM")
      (libsource (lib "eagle-import") (part "R-EU_V235/17_1MM"))
    )
    (comp (ref "R11")
      (value "13")
      (footprint "eagle-import:R1206")
      (fields (field (name "MPN") "RC1206JR-0713RL"))
      (libsource (lib "eagle-import") (part "SMD-RES-13R-5%-1/4W(1206)"))
    )
    (comp (ref "R14")
      (value "47")
      (footprint "eagle-import:V235_17_1MM")
      (libsource (lib "eagle-import") (part "R-EU_V235/17_1MM"))
    )
    (comp (ref "R15")
      (value "104")
      (footprint "eagle-import:R0805")
      (fields (field (name "MPN") "RC0805FR-0710KL"))
      (libsource (lib "eagle-import") (part "SMD-RES-10K-1%-1/8W(0805)"))
    )
    (comp (ref "R16")
      (value "104")
      (footprint "eagle-import:R0805")
      (fields (field (name "MPN") "RC0805FR-0710KL"))
      (libsource (lib "eagle-import") (part "SMD-RES-10K-1%-1/8W(0805)"))
    )
    (comp (ref "R17")
      (value "104")
      (footprint "eagle-import:R0805")
      (fields (field (name "MPN") "RC0805FR-0710KL"))
      (libsource (lib "eagle-import") (part "SMD-RES-10K-1%-1/8W(0805)"))
    )
    (comp (ref "R18")
      (value "4701")
      (footprint "eagle-import:R0805")
      (fields (field (name "MPN") "RC0805JR-074K7L"))
      (libsource (lib "eagle-import") (part "SMD-RES-4.7K-5%-1/8W(0805)"))
    )
    (comp (ref "R19")
      (value "1002")
      (footprint "eagle-import:R0805")
      (fields (field (name "MPN") "RC0805FR-0710KL"))
      (libsource (lib "eagle-import") (part "SMD-RES-10K-1%-1/8W(0805)"))
    )
    (comp (ref "R20")
      (value "1002")
      (footprint "eagle-import:R0805")
      (fields (field (name "MPN") "RC0805FR-0710KL"))
      (libsource (lib "eagle-import") (part "SMD-RES-10K-1%-1/8W(0805)"))
    )
    (comp (ref "R21")
      (value "1502")
      (footprint "eagle-import:R0805")
      (fields (field (name "MPN") "RC0805FR-0710KL"))
      (libsource (lib "eagle-import") (part "SMD-RES-10K-1%-1/8W(0805)"))
    )
    (comp (ref "R22")
      (value "104")
      (footprint "eagle-import:R0805")
      (fields (field (name "MPN") "RC0805FR-0710KL"))
      (libsource (lib "eagle-import") (part "SMD-RES-10K-1%-1/8W(0805)"))
    )
    (comp (ref "R23")
      (value "104")
      (footprint "eagle-import:R0805")
      (fields (field (name "MPN") "RC0805FR-0710KL"))
      (libsource (lib "eagle-import") (part "SMD-RES-10K-1%-1/8W(0805)"))
    )
    (comp (ref "R24")
      (value "1502")
      (footprint "eagle-import:R0805")
      (fields (field (name "MPN") "RC0805FR-0710KL"))
      (libsource (lib "eagle-import") (part "SMD-RES-10K-1%-1/8W(0805)"))
    )
    (comp (ref "R25")
      (value "1002")
      (footprint "eagle-import:R0805")
      (fields (field (name "MPN") "RC0805FR-0710KL"))
      (libsource (lib "eagle-import") (part "SMD-RES-10K-1%-1/8W(0805)"))
    )
    (comp (ref "R26")
      (value "2201")
      (footprint "eagle-import:R0805")
      (fields (field (name "MPN") "RC0805JR-072K2L"))
      (libsource (lib "eagle-import") (part "SMD-RES-2.2K-5%-1/8W(0805)"))
    )
    (comp (ref "R27")
      (value "1002")
      (footprint "eagle-import:R0805")
      (fields (field (name "MPN") "RC0805FR-0710KL"))
      (libsource (lib "eagle-import") (part "SMD-RES-10K-1%-1/8W(0805)"))
    )
    (comp (ref "R28")
      (value "4701")
      (footprint "eagle-import:R0805")
      (fields (field (name "MPN") "RC0805JR-074K7L"))
      (libsource (lib "eagle-import") (part "SMD-RES-4.7K-5%-1/8W(0805)"))
    )
    (comp (ref "R29")
      (value "2702")
      (footprint "eagle-import:R0805")
      (fields (field (name "MPN") "RC0805JR-074K7L"))
      (libsource (lib "eagle-import") (part "SMD-RES-4.7K-5%-1/8W(0805)"))
    )
    (comp (ref "R30")
      (value "102")
      (footprint "eagle-import:R0805")
      (fields (field (name "MPN") "RC0805JR-071KL"))
      (libsource (lib "eagle-import") (part "SMD-RES-1K-5%-1/8W(0805)"))
    )
    (comp (ref "R31")
      (value "R_user")
      (footprint "eagle-import:R0805")
      (libsource (lib "eagle-import") (part "R-EU_R0805"))
    )
    (comp (ref "R32")
      (value "102")
      (footprint "eagle-import:R0805")
      (fields (field (name "MPN") "RC0805JR-07220RL"))
      (libsource (lib "eagle-import") (part "SMD-RES-220R-5%-1/8W(0805)"))
    )
    (comp (ref "R33")
      (value "(101)")
      (footprint "eagle-import:R0805")
      (fields (field (name "MPN") "RC0805JR-07100RL"))
      (libsource (lib "eagle-import") (part "SMD-RES-100R-5%-1/8W(0805)"))
    )
    (comp (ref "R34")
      (value "(1000)")
      (footprint "eagle-import:R0805")
      (fields (field (name "MPN") "RC0805JR-07100RL"))
      (libsource (lib "eagle-import") (part "SMD-RES-100R-5%-1/8W(0805)"))
    )
    (comp (ref "R35")
      (value "102")
      (footprint "eagle-import:R0805")
      (fields (field (name "MPN") "RC0805JR-071KL"))
      (libsource (lib "eagle-import") (part "SMD-RES-1K-5%-1/8W(0805)"))
    )
    (comp (ref "R36")
      (value "13")
      (footprint "eagle-import:R1206")
      (fields (field (name "MPN") "RC1206JR-0713RL"))
      (libsource (lib "eagle-import") (part "SMD-RES-13R-5%-1/4W(1206)"))
    )
    (comp (ref "R37")
      (value "13")
      (footprint "eagle-import:R1206")
      (fields (field (name "MPN") "RC1206JR-0713RL"))
      (libsource (lib "eagle-import") (part "SMD-RES-13R-5%-1/4W(1206)"))
    )
    (comp (ref "R38")
      (value "2702")
      (footprint "eagle-import:R0805")
      (fields (field (name "MPN") "RC0805JR-074K7L"))
      (libsource (lib "eagle-import") (part "SMD-RES-4.7K-5%-1/8W(0805)"))
    )
    (comp (ref "R39")
      (value "4701")
      (footprint "eagle-import:R0805")
      (fields (field (name "MPN") "RC0805JR-074K7L"))
      (libsource (lib "eagle-import") (part "SMD-RES-4.7K-5%-1/8W(0805)"))
    )
    (comp (ref "R40")
      (value "100")
      (footprint "eagle-import:R0805")
      (fields (field (name "MPN") "RC0805JR-072K2L"))
      (libsource (lib "eagle-import") (part "SMD-RES-2.2K-5%-1/8W(0805)"))
    )
    (comp (ref "R41")
      (value "104")
      (footprint "eagle-import:R0805")
      (fields (field (name "MPN") "RC0805FR-0710KL"))
      (libsource (lib "eagle-import") (part "SMD-RES-10K-1%-1/8W(0805)"))
    )
    (comp (ref "R42")
      (value "104")
      (footprint "eagle-import:R0805")
      (fields (field (name "MPN") "RC0805FR-0710KL"))
      (libsource (lib "eagle-import") (part "SMD-RES-10K-1%-1/8W(0805)"))
    )
    (comp (ref "R43")
      (value "(1002)")
      (footprint "eagle-import:R0805")
      (fields (field (name "MPN") "RC0805FR-0710KL"))
      (libsource (lib "eagle-import") (part "SMD-RES-10K-1%-1/8W(0805)"))
    )
    (comp (ref "R44")
      (value "2702")
      (footprint "eagle-import:R0805")
      (fields (field (name "MPN") "RC0805FR-0710KL"))
      (libsource (lib "eagle-import") (part "SMD-RES-10K-1%-1/8W(0805)"))
    )
    (comp (ref "R45")
      (value "47")
      (footprint "eagle-import:V235_17_1MM")
      (libsource (lib "eagle-import") (part "R-EU_V235/17_1MM"))
    )
    (comp (ref "R46")
      (value "47")
      (footprint "eagle-import:V235_17_1MM")
      (libsource (lib "eagle-import") (part "R-EU_V235/17_1MM"))
    )
    (comp (ref "R47")
      (value "2702")
      (footprint "eagle-import:R0805")
      (fields (field (name "MPN") "RC0805JR-074K7L"))
      (libsource (lib "eagle-import") (part "SMD-RES-4.7K-5%-1/8W(0805)"))
    )
    (comp (ref "R48")
      (value "2201")
      (footprint "eagle-import:R0805")
      (fields (field (name "MPN") "RC0805JR-072K2L"))
      (libsource (lib "eagle-import") (part "SMD-RES-2.2K-5%-1/8W(0805)"))
    )
    (comp (ref "R49")
      (value "1002")
      (footprint "eagle-import:R0805")
      (fields (field (name "MPN") "RC0805JR-074K7L"))
      (libsource (lib "eagle-import") (part "SMD-RES-4.7K-5%-1/8W(0805)"))
    )
    (comp (ref "R50")
      (value "1002")
      (footprint "eagle-import:R0805")
      (fields (field (name "MPN") "RC0805FR-0710KL"))
      (libsource (lib "eagle-import") (part "SMD-RES-10K-1%-1/8W(0805)"))
    )
    (comp (ref "R51")
      (value "102")
      (footprint "eagle-import:R0805")
      (fields (field (name "MPN") "RC0805JR-071KL"))
      (libsource (lib "eagle-import") (part "SMD-RES-1K-5%-1/8W(0805)"))
    )
    (comp (ref "R52")
      (value "2702")
      (footprint "eagle-import:R0805")
      (fields (field (name "MPN") "RC0805JR-074K7L"))
      (libsource (lib "eagle-import") (part "SMD-RES-4.7K-5%-1/8W(0805)"))
    )
    (comp (ref "R53")
      (value "1002")
      (footprint "eagle-import:R0805")
      (fields (field (name "MPN") "RC0805JR-071KL"))
      (libsource (lib "eagle-import") (part "SMD-RES-1K-5%-1/8W(0805)"))
    )
    (comp (ref "R54")
      (value "1002")
      (footprint "eagle-import:R0805")
      (fields (field (name "MPN") "RC0805JR-071KL"))
      (libsource (lib "eagle-import") (part "SMD-RES-1K-5%-1/8W(0805)"))
    )
    (comp (ref "R55")
      (value "R_user")
      (footprint "eagle-import:R0805")
      (libsource (lib "eagle-import") (part "R-EU_R0805"))
    )
    (comp (ref "R56")
      (value "104")
      (footprint "eagle-import:R0805")
      (fields (field (name "MPN") "RC0805FR-0710KL"))
      (libsource (lib "eagle-import") (part "SMD-RES-10K-1%-1/8W(0805)"))
    )
    (comp (ref "R57")
      (value "104")
      (footprint "eagle-import:R0805")
      (fields (field (name "MPN") "RC0805FR-0710KL"))
      (libsource (lib "eagle-import") (part "SMD-RES-10K-1%-1/8W(0805)"))
    )
    (comp (ref "R58")
      (value "104")
      (footprint "eagle-import:R0805")
      (fields (field (name "MPN") "RC0805FR-0710KL"))
      (libsource (lib "eagle-import") (part "SMD-RES-10K-1%-1/8W(0805)"))
    )
    (comp (ref "R59")
      (value "13")
      (footprint "eagle-import:R1206")
      (fields (field (name "MPN") "RC1206JR-0713RL"))
      (libsource (lib "eagle-import") (part "SMD-RES-13R-5%-1/4W(1206)"))
    )
    (comp (ref "R60")
      (value "2201")
      (footprint "eagle-import:R0805")
      (fields (field (name "MPN") "RC0805JR-071KL"))
      (libsource (lib "eagle-import") (part "SMD-RES-1K-5%-1/8W(0805)"))
    )
    (comp (ref "R61")
      (value "100")
      (footprint "eagle-import:R0805")
      (fields (field (name "MPN") "RC0805JR-07220RL"))
      (libsource (lib "eagle-import") (part "SMD-RES-220R-5%-1/8W(0805)"))
    )
    (comp (ref "R62")
      (value "13")
      (footprint "eagle-import:R1206")
      (fields (field (name "MPN") "RC1206JR-0713RL"))
      (libsource (lib "eagle-import") (part "SMD-RES-13R-5%-1/4W(1206)"))
    )
    (comp (ref "R63")
      (value "4701")
      (footprint "eagle-import:R0805")
      (fields (field (name "MPN") "RC0805JR-074K7L"))
      (libsource (lib "eagle-import") (part "SMD-RES-4.7K-5%-1/8W(0805)"))
    )
    (comp (ref "R64")
      (value "104")
      (footprint "eagle-import:R0805")
      (fields (field (name "MPN") "RC0805JR-074K7L"))
      (libsource (lib "eagle-import") (part "SMD-RES-4.7K-5%-1/8W(0805)"))
    )
    (comp (ref "R65")
      (value "2R")
      (footprint "eagle-import:R0805")
      (fields (field (name "MPN") "RC0805JR-072K2L"))
      (libsource (lib "eagle-import") (part "SMD-RES-2.2K-5%-1/8W(0805)"))
    )
    (comp (ref "R66")
      (value "2R")
      (footprint "eagle-import:R0805")
      (fields (field (name "MPN") "RC0805JR-072K2L"))
      (libsource (lib "eagle-import") (part "SMD-RES-2.2K-5%-1/8W(0805)"))
    )
    (comp (ref "SJ1")
      (value "SJ")
      (footprint "eagle-import:SJ")
      (libsource (lib "eagle-import") (part "solder-jumper_SJ"))
    )
    (comp (ref "SJMP1")
      (value "SJ")
      (footprint "eagle-import:SJ")
      (libsource (lib "eagle-import") (part "SJ"))
    )
    (comp (ref "START1")
      (value "TPSB2.0")
      (footprint "eagle-import:B2.0")
      (libsource (lib "eagle-import") (part "TPSB2.0"))
    )
    (comp (ref "TP14")
      (value "TPSB2.0")
      (footprint "eagle-import:B2.0")
      (libsource (lib "eagle-import") (part "TPSB2.0"))
    )
    (comp (ref "TP15")
      (value "TPSB2.0")
      (footprint "eagle-import:B2.0")
      (libsource (lib "eagle-import") (part "TPSB2.0"))
    )
    (comp (ref "TP20")
      (value "TPSB2.0")
      (footprint "eagle-import:B2.0")
      (libsource (lib "eagle-import") (part "TPSB2.0"))
    )
    (comp (ref "TP27")
      (value "TPSB2.0")
      (footprint "eagle-import:B2.0")
      (libsource (lib "eagle-import") (part "TPSB2.0"))
    )
    (comp (ref "TP28")
      (value "TPSB2.0")
      (footprint "eagle-import:B2.0")
      (libsource (lib "eagle-import") (part "TPSB2.0"))
    )
    (comp (ref "TP29")
      (value "TPSB2.0")
      (footprint "eagle-import:B2.0")
      (libsource (lib "eagle-import") (part "TPSB2.0"))
    )
    (comp (ref "TP30")
      (value "TPSB2.0")
      (footprint "eagle-import:B2.0")
      (libsource (lib "eagle-import") (part "TPSB2.0"))
    )
    (comp (ref "TP31")
      (value "TPSB2.0")
      (footprint "eagle-import:B2.0")
      (libsource (lib "eagle-import") (part "TPSB2.0"))
    )
    (comp (ref "TP32")
      (value "TPSB2.0")
      (footprint "eagle-import:B2.0")
      (libsource (lib "eagle-import") (part "TPSB2.0"))
    )
    (comp (ref "TP33")
      (value "TPSB2.0")
      (footprint "eagle-import:B2.0")
      (libsource (lib "eagle-import") (part "TPSB2.0"))
    )
    (comp (ref "TP34")
      (value "TPSB2.0")
      (footprint "eagle-import:B2.0")
      (libsource (lib "eagle-import") (part "TPSB2.0"))
    )
    (comp (ref "TP35")
      (value "TPSB2.0")
      (footprint "eagle-import:B2.0")
      (libsource (lib "eagle-import") (part "TPSB2.0"))
    )
    (comp (ref "TP36")
      (value "TPSB2.0")
      (footprint "eagle-import:B2.0")
      (libsource (lib "eagle-import") (part "TPSB2.0"))
    )
    (comp (ref "TP37")
      (value "TPSB2.0")
      (footprint "eagle-import:B2.0")
      (libsource (lib "eagle-import") (part "TPSB2.0"))
    )
    (comp (ref "TP38")
      (value "TPSB2.0")
      (footprint "eagle-import:B2.0")
      (libsource (lib "eagle-import") (part "TPSB2.0"))
    )
    (comp (ref "TP39")
      (value "TPSB2.0")
      (footprint "eagle-import:B2.0")
      (libsource (lib "eagle-import") (part "TPSB2.0"))
    )
    (comp (ref "TP40")
      (value "TPSB2.0")
      (footprint "eagle-import:B2.0")
      (libsource (lib "eagle-import") (part "TPSB2.0"))
    )
    (comp (ref "TP41")
      (value "TPSB2.0")
      (footprint "eagle-import:B2.0")
      (libsource (lib "eagle-import") (part "TPSB2.0"))
    )
    (comp (ref "TP42")
      (value "TPSB1,27")
      (footprint "eagle-import:B1,27")
      (libsource (lib "eagle-import") (part "TPSB1,27"))
    )
    (comp (ref "TP43")
      (value "TPSB2.0")
      (footprint "eagle-import:B2.0")
      (libsource (lib "eagle-import") (part "TPSB2.0"))
    )
    (comp (ref "TP44")
      (value "TPSB2.0")
      (footprint "eagle-import:B2.0")
      (libsource (lib "eagle-import") (part "TPSB2.0"))
    )
    (comp (ref "TP45")
      (value "TPSB2.0")
      (footprint "eagle-import:B2.0")
      (libsource (lib "eagle-import") (part "TPSB2.0"))
    )
    (comp (ref "TP46")
      (value "TPSB2.0")
      (footprint "eagle-import:B2.0")
      (libsource (lib "eagle-import") (part "TPSB2.0"))
    )
    (comp (ref "X1")
      (value "CON_BMWV2")
      (footprint "eagle-import:24-PIN_V2")
      (libsource (lib "eagle-import") (part "CON_BMWV2"))
    )
    (comp (ref "X2")
      (value "22-23-2051")
      (footprint "eagle-import:22-23-2051")
      (fields (field (name "MF") "MOLEX"))
      (libsource (lib "eagle-import") (part "22-23-2051"))
    )
    (comp (ref "X3")
      (value "22-23-2021")
      (footprint "eagle-import:22-23-2021")
      (fields (field (name "MF") "MOLEX"))
      (libsource (lib "eagle-import") (part "22-23-2021"))
    )
    (comp (ref "FID1")
      (value "FIDUCIAL")
      (footprint "eagle-import:FIDUCIAL_1MM")
      (libsource (lib "eagle-import") (part "FIDUCIAL"))
    )
    (comp (ref "FID1B")
      (value "FIDUCIALFIDUCIAL_1MM_WITH_SOLDERMASK")
      (footprint "eagle-import:FIDUCIAL_1MM_WITH_SOLDERMASK")
      (libsource (lib "eagle-import") (part "FIDUCIALFIDUCIAL_1MM_WITH_SOLDERMASK"))
    )
    (comp (ref "FID2")
      (value "FIDUCIAL")
      (footprint "eagle-import:FIDUCIAL_1MM")
      (libsource (lib "eagle-import") (part "FIDUCIAL"))
    )
    (comp (ref "FID2B")
      (value "FIDUCIALFIDUCIAL_1MM_WITH_SOLDERMASK")
      (footprint "eagle-import:FIDUCIAL_1MM_WITH_SOLDERMASK")
      (libsource (lib "eagle-import") (part "FIDUCIALFIDUCIAL_1MM_WITH_SOLDERMASK"))
    )
    (comp (ref "6V4")
      (value "TPSB2.0")
      (footprint "eagle-import:B2.0")
      (libsource (lib "eagle-import") (part "TPSB2.0"))
    )
    (comp (ref "9")
      (value "2081-1132")
      (footprint "eagle-import:12-PIN")
      (libsource (lib "eagle-import") (part "2081-1132"))
    )
    (comp (ref "10")
      (value "2081-1132")
      (footprint "eagle-import:12-PIN")
      (libsource (lib "eagle-import") (part "2081-1132"))
    )
    (comp (ref "10V4")
      (value "TPSB2.0")
      (footprint "eagle-import:B2.0")
      (libsource (lib "eagle-import") (part "TPSB2.0"))
    )
    (comp (ref "C39")
      (value "100u")
      (footprint "eagle-import:C1206")
      (fields (field (name "MPN") "GRM31CR60J107ME39L"))
      (libsource (lib "eagle-import") (part "CERAMIC-100UF-6.3V-20%-X5R(1206)"))
    )
    (comp (ref "C40")
      (value "100u")
      (footprint "eagle-import:C1206")
      (fields (field (name "MPN") "GRM31CR60J107ME39L"))
      (libsource (lib "eagle-import") (part "CERAMIC-100UF-6.3V-20%-X5R(1206)"))
    )
    (comp (ref "C41")
      (value "100nF,")
      (footprint "eagle-import:C0805")
      (fields (field (name "MPN") "CC0805KRX7R9BB104"))
      (libsource (lib "eagle-import") (part "CERAMIC-100NF-50V-10%-X7R(0805)"))
    )
    (comp (ref "C42")
      (value "4.7u")
      (footprint "eagle-import:C0805")
      (fields (field (name "MPN") "CC0805KKX5R8BB475"))
      (libsource (lib "eagle-import") (part "CERAMIC-4.7UF-25V-10%-X5R(0805)"))
    )
    (comp (ref "C43")
      (value "100nF.")
      (footprint "eagle-import:C0805")
      (fields (field (name "MPN") "CC0805KRX7R9BB104"))
      (libsource (lib "eagle-import") (part "CERAMIC-100NF-50V-10%-X7R(0805)"))
    )
    (comp (ref "C44")
      (value "100nF.")
      (footprint "eagle-import:C0805")
      (fields (field (name "MPN") "CC0805KRX7R9BB104"))
      (libsource (lib "eagle-import") (part "CERAMIC-100NF-50V-10%-X7R(0805)"))
    )
    (comp (ref "C45")
      (value "2.2nF")
      (footprint "eagle-import:C0805")
      (fields (field (name "MPN") "CC0805KRX7R9BB104"))
      (libsource (lib "eagle-import") (part "CERAMIC-100NF-50V-10%-X7R(0805)"))
    )
    (comp (ref "C46")
      (value "100nF")
      (footprint "eagle-import:C0805")
      (fields (field (name "MPN") "CC0805KRX7R9BB104"))
      (libsource (lib "eagle-import") (part "CERAMIC-100NF-50V-10%-X7R(0805)"))
    )
    (comp (ref "C47")
      (value "100nF")
      (footprint "eagle-import:C0805")
      (fields (field (name "MPN") "CC0805KRX7R9BB104"))
      (libsource (lib "eagle-import") (part "CERAMIC-100NF-50V-10%-X7R(0805)"))
    )
    (comp (ref "C48")
      (value "100nF,")
      (footprint "eagle-import:C0805")
      (fields (field (name "MPN") "CC0805KRX7R9BB104"))
      (libsource (lib "eagle-import") (part "CERAMIC-100NF-50V-10%-X7R(0805)"))
    )
    (comp (ref "C49")
      (value "4.7u")
      (footprint "eagle-import:C0805")
      (fields (field (name "MPN") "CC0805KKX5R8BB475"))
      (libsource (lib "eagle-import") (part "CERAMIC-4.7UF-25V-10%-X5R(0805)"))
    )
    (comp (ref "C50")
      (value "10u")
      (footprint "eagle-import:C1206")
      (fields (field (name "MPN") "GRM31CR60J107ME39L"))
      (libsource (lib "eagle-import") (part "CERAMIC-100UF-6.3V-20%-X5R(1206)"))
    )
    (comp (ref "D46")
      (value "1N4007")
      (footprint "eagle-import:DO-214AC")
      (libsource (lib "eagle-import") (part "DIODE-GEN-PURPOSE-1KV-1A(DO-214AC)"))
    )
    (comp (ref "D47")
      (value "1N4007")
      (footprint "eagle-import:DO-214AC")
      (libsource (lib "eagle-import") (part "DIODE-GEN-PURPOSE-1KV-1A(DO-214AC)"))
    )
    (comp (ref "D48")
      (value "1N4007.")
      (footprint "eagle-import:DO-214AC")
      (fields (field (name "MPN") "1N4007"))
      (libsource (lib "eagle-import") (part "DIODE-GEN-PURPOSE-1KV-1A(DO-214AC)"))
    )
    (comp (ref "D49")
      (value "1N5817")
      (footprint "eagle-import:DO-214AC_SLIM")
      (libsource (lib "eagle-import") (part "DIODE-GEN-PURPOSE-1KV-1A(DO-214AC)DO-214AC/1206"))
    )
    (comp (ref "D50")
      (value "1N5817.")
      (footprint "eagle-import:DO-214AC_SLIM")
      (libsource (lib "eagle-import") (part "DIODE-GEN-PURPOSE-1KV-1A(DO-214AC)DO-214AC/1206"))
    )
    (comp (ref "D51")
      (value "1N5817.")
      (footprint "eagle-import:DO-214AC_SLIM")
      (libsource (lib "eagle-import") (part "DIODE-GEN-PURPOSE-1KV-1A(DO-214AC)DO-214AC/1206"))
    )
    (comp (ref "D52")
      (value "1N5817")
      (footprint "eagle-import:DO-214AC_SLIM")
      (libsource (lib "eagle-import") (part "DIODE-GEN-PURPOSE-1KV-1A(DO-214AC)DO-214AC/1206"))
    )
    (comp (ref "D53")
      (value "1N4007.")
      (footprint "eagle-import:DO-214AC")
      (fields (field (name "MPN") "1N4007"))
      (libsource (lib "eagle-import") (part "DIODE-GEN-PURPOSE-1KV-1A(DO-214AC)"))
    )
    (comp (ref "D54")
      (value "1N4007")
      (footprint "eagle-import:DO-214AC")
      (libsource (lib "eagle-import") (part "DIODE-GEN-PURPOSE-1KV-1A(DO-214AC)"))
    )
    (comp (ref "D55")
      (value "Zen15")
      (footprint "eagle-import:DO214AA")
      (libsource (lib "eagle-import") (part "SM6T"))
    )
    (comp (ref "D56")
      (value "SM6TDO214AA_BI")
      (footprint "eagle-import:DO214AA_BI")
      (libsource (lib "eagle-import") (part "SM6TDO214AA_BI"))
    )
    (comp (ref "D57")
      (value "1N5817")
      (footprint "eagle-import:DO-214AC_SLIM")
      (libsource (lib "eagle-import") (part "DIODE-GEN-PURPOSE-1KV-1A(DO-214AC)DO-214AC/1206"))
    )
    (comp (ref "D58")
      (value "1N5817.")
      (footprint "eagle-import:DO-214AC_SLIM")
      (libsource (lib "eagle-import") (part "DIODE-GEN-PURPOSE-1KV-1A(DO-214AC)DO-214AC/1206"))
    )
    (comp (ref "D59")
      (value "Zen11")
      (footprint "eagle-import:SOD-123_MINI-SMA")
      (libsource (lib "eagle-import") (part "CGRM400-G1"))
    )
    (comp (ref "FID15")
      (value "FIDUCIAL")
      (footprint "eagle-import:FIDUCIAL_1MM")
      (libsource (lib "eagle-import") (part "FIDUCIAL"))
    )
    (comp (ref "FID16")
      (value "FIDUCIAL")
      (footprint "eagle-import:FIDUCIAL_1MM")
      (libsource (lib "eagle-import") (part "FIDUCIAL"))
    )
    (comp (ref "FID17")
      (value "FIDUCIAL")
      (footprint "eagle-import:FIDUCIAL_1MM")
      (libsource (lib "eagle-import") (part "FIDUCIAL"))
    )
    (comp (ref "FID18")
      (value "FIDUCIAL")
      (footprint "eagle-import:FIDUCIAL_1MM")
      (libsource (lib "eagle-import") (part "FIDUCIAL"))
    )
    (comp (ref "IC28")
      (value "4028")
      (footprint "eagle-import:SO16")
      (libsource (lib "eagle-import") (part "4028D"))
    )
    (comp (ref "IC29")
      (value "317TO202H_NOHOLE")
      (footprint "eagle-import:TO220H_NOHOLE")
      (libsource (lib "eagle-import") (part "317TO202H_NOHOLE"))
    )
    (comp (ref "IC30")
      (value "ULN2004")
      (footprint "eagle-import:SO16")
      (libsource (lib "eagle-import") (part "ULN2004AD"))
    )
    (comp (ref "IC31")
      (value "LM339")
      (footprint "eagle-import:SO14")
      (libsource (lib "eagle-import") (part "LM339D"))
    )
    (comp (ref "IC32")
      (value "78L06")
      (footprint "eagle-import:SOT89_ROUND")
      (libsource (lib "eagle-import") (part "78LXXSOT89_ROUND"))
    )
    (comp (ref "IC33")
      (value "555")
      (footprint "eagle-import:SO08")
      (libsource (lib "eagle-import") (part "555DNE"))
    )
    (comp (ref "IC34")
      (value "4538")
      (footprint "eagle-import:SO16")
      (libsource (lib "eagle-import") (part "4538D"))
    )
    (comp (ref "IC35")
      (value "78L10")
      (footprint "eagle-import:SOT89_ROUND")
      (libsource (lib "eagle-import") (part "78LXXSOT89_ROUND"))
    )
    (comp (ref "IC36")
      (value "LM2904")
      (footprint "eagle-import:SO08")
      (libsource (lib "eagle-import") (part "LM358D"))
    )
    (comp (ref "JP16")
      (value "JP2EJP2_SMALLPADS")
      (footprint "eagle-import:JP2_SMALLPADS")
      (libsource (lib "eagle-import") (part "JP2EJP2_SMALLPADS"))
    )
    (comp (ref "JP17")
      (value "JP2E_ORIG")
      (footprint "eagle-import:JP2_ORIG_SMALLPADS")
      (libsource (lib "eagle-import") (part "JP2E_ORIG"))
    )
    (comp (ref "JP18")
      (value "JP2EJP2_SMALLPADS")
      (footprint "eagle-import:JP2_SMALLPADS")
      (libsource (lib "eagle-import") (part "JP2EJP2_SMALLPADS"))
    )
    (comp (ref "JP19")
      (value "JP2EJP2_SMALLPADS")
      (footprint "eagle-import:JP2_SMALLPADS")
      (libsource (lib "eagle-import") (part "JP2EJP2_SMALLPADS"))
    )
    (comp (ref "JP20")
      (value "JP2EJP2_SMALLPADS")
      (footprint "eagle-import:JP2_SMALLPADS")
      (libsource (lib "eagle-import") (part "JP2EJP2_SMALLPADS"))
    )
    (comp (ref "LED19")
      (value "LEDLD260")
      (footprint "eagle-import:LD260")
      (libsource (lib "eagle-import") (part "LEDLD260"))
    )
    (comp (ref "LED20")
      (value "LEDLD260")
      (footprint "eagle-import:LD260")
      (libsource (lib "eagle-import") (part "LEDLD260"))
    )
    (comp (ref "LED21")
      (value "LEDLD260")
      (footprint "eagle-import:LD260")
      (libsource (lib "eagle-import") (part "LEDLD260"))
    )
    (comp (ref "LED22")
      (value "LEDLD260")
      (footprint "eagle-import:LD260")
      (libsource (lib "eagle-import") (part "LEDLD260"))
    )
    (comp (ref "LED23")
      (value "LEDLD260")
      (footprint "eagle-import:LD260")
      (libsource (lib "eagle-import") (part "LEDLD260"))
    )
    (comp (ref "LED24")
      (value "LEDLD260")
      (footprint "eagle-import:LD260")
      (libsource (lib "eagle-import") (part "LEDLD260"))
    )
    (comp (ref "Q34")
      (value "BA")
      (footprint "eagle-import:SOT89")
      (libsource (lib "eagle-import") (part "PNP-TRANSISTOR_SOT89"))
    )
    (comp (ref "Q35")
      (value "BA.")
      (footprint "eagle-import:SOT89")
      (libsource (lib "eagle-import") (part "PNP-TRANSISTOR_SOT89"))
    )
    (comp (ref "Q36")
      (value "BA.")
      (footprint "eagle-import:SOT89")
      (libsource (lib "eagle-import") (part "PNP-TRANSISTOR_SOT89"))
    )
    (comp (ref "Q37")
      (value "BA")
      (footprint "eagle-import:SOT89")
      (libsource (lib "eagle-import") (part "PNP-TRANSISTOR_SOT89"))
    )
    (comp (ref "Q38")
      (value "MY")
      (footprint "eagle-import:SOT89")
      (libsource (lib "eagle-import") (part "NPN-TRANSISTOR_SOT89"))
    )
    (comp (ref "Q39")
      (value "J1")
      (footprint "eagle-import:SOT-23")
      (fields (field (name "MPN") "BSS138W-7-F"))
      (libsource (lib "eagle-import") (part "SMD-MOSFET-N-CH-50V-200MA-BSS138W-7-F(SOT-23)"))
    )
    (comp (ref "Q40")
      (value "J1")
      (footprint "eagle-import:SOT-23")
      (fields (field (name "MPN") "BSS138W-7-F"))
      (libsource (lib "eagle-import") (part "SMD-MOSFET-N-CH-50V-200MA-BSS138W-7-F(SOT-23)"))
    )
    (comp (ref "Q41")
      (value "J1")
      (footprint "eagle-import:SOT-23")
      (fields (field (name "MPN") "BSS138W-7-F"))
      (libsource (lib "eagle-import") (part "SMD-MOSFET-N-CH-50V-200MA-BSS138W-7-F(SOT-23)"))
    )
    (comp (ref "Q42")
      (value "BA")
      (footprint "eagle-import:SOT89")
      (libsource (lib "eagle-import") (part "PNP-TRANSISTOR_SOT89"))
    )
    (comp (ref "Q43")
      (value "J1")
      (footprint "eagle-import:SOT-23")
      (fields (field (name "MPN") "BSS138W-7-F"))
      (libsource (lib "eagle-import") (part "SMD-MOSFET-N-CH-50V-200MA-BSS138W-7-F(SOT-23)"))
    )
    (comp (ref "R221")
      (value "47")
      (footprint "eagle-import:V235_17_1MM")
      (libsource (lib "eagle-import") (part "R-EU_V235/17_1MM"))
    )
    (comp (ref "R222")
      (value "13")
      (footprint "eagle-import:R1206")
      (fields (field (name "MPN") "RC1206JR-0713RL"))
      (libsource (lib "eagle-import") (part "SMD-RES-13R-5%-1/4W(1206)"))
    )
    (comp (ref "R223")
      (value "47")
      (footprint "eagle-import:V235_17_1MM")
      (libsource (lib "eagle-import") (part "R-EU_V235/17_1MM"))
    )
    (comp (ref "R224")
      (value "104")
      (footprint "eagle-import:R0805")
      (fields (field (name "MPN") "RC0805FR-0710KL"))
      (libsource (lib "eagle-import") (part "SMD-RES-10K-1%-1/8W(0805)"))
    )
    (comp (ref "R225")
      (value "104")
      (footprint "eagle-import:R0805")
      (fields (field (name "MPN") "RC0805FR-0710KL"))
      (libsource (lib "eagle-import") (part "SMD-RES-10K-1%-1/8W(0805)"))
    )
    (comp (ref "R226")
      (value "104")
      (footprint "eagle-import:R0805")
      (fields (field (name "MPN") "RC0805FR-0710KL"))
      (libsource (lib "eagle-import") (part "SMD-RES-10K-1%-1/8W(0805)"))
    )
    (comp (ref "R227")
      (value "4701")
      (footprint "eagle-import:R0805")
      (fields (field (name "MPN") "RC0805JR-074K7L"))
      (libsource (lib "eagle-import") (part "SMD-RES-4.7K-5%-1/8W(0805)"))
    )
    (comp (ref "R228")
      (value "1002")
      (footprint "eagle-import:R0805")
      (fields (field (name "MPN") "RC0805FR-0710KL"))
      (libsource (lib "eagle-import") (part "SMD-RES-10K-1%-1/8W(0805)"))
    )
    (comp (ref "R229")
      (value "1002")
      (footprint "eagle-import:R0805")
      (fields (field (name "MPN") "RC0805FR-0710KL"))
      (libsource (lib "eagle-import") (part "SMD-RES-10K-1%-1/8W(0805)"))
    )
    (comp (ref "R230")
      (value "1502")
      (footprint "eagle-import:R0805")
      (fields (field (name "MPN") "RC0805FR-0710KL"))
      (libsource (lib "eagle-import") (part "SMD-RES-10K-1%-1/8W(0805)"))
    )
    (comp (ref "R231")
      (value "104")
      (footprint "eagle-import:R0805")
      (fields (field (name "MPN") "RC0805FR-0710KL"))
      (libsource (lib "eagle-import") (part "SMD-RES-10K-1%-1/8W(0805)"))
    )
    (comp (ref "R232")
      (value "104")
      (footprint "eagle-import:R0805")
      (fields (field (name "MPN") "RC0805FR-0710KL"))
      (libsource (lib "eagle-import") (part "SMD-RES-10K-1%-1/8W(0805)"))
    )
    (comp (ref "R233")
      (value "1502")
      (footprint "eagle-import:R0805")
      (fields (field (name "MPN") "RC0805FR-0710KL"))
      (libsource (lib "eagle-import") (part "SMD-RES-10K-1%-1/8W(0805)"))
    )
    (comp (ref "R234")
      (value "1002")
      (footprint "eagle-import:R0805")
      (fields (field (name "MPN") "RC0805FR-0710KL"))
      (libsource (lib "eagle-import") (part "SMD-RES-10K-1%-1/8W(0805)"))
    )
    (comp (ref "R235")
      (value "2201")
      (footprint "eagle-import:R0805")
      (fields (field (name "MPN") "RC0805JR-072K2L"))
      (libsource (lib "eagle-import") (part "SMD-RES-2.2K-5%-1/8W(0805)"))
    )
    (comp (ref "R236")
      (value "1002")
      (footprint "eagle-import:R0805")
      (fields (field (name "MPN") "RC0805FR-0710KL"))
      (libsource (lib "eagle-import") (part "SMD-RES-10K-1%-1/8W(0805)"))
    )
    (comp (ref "R237")
      (value "4701")
      (footprint "eagle-import:R0805")
      (fields (field (name "MPN") "RC0805JR-074K7L"))
      (libsource (lib "eagle-import") (part "SMD-RES-4.7K-5%-1/8W(0805)"))
    )
    (comp (ref "R238")
      (value "2702")
      (footprint "eagle-import:R0805")
      (fields (field (name "MPN") "RC0805JR-074K7L"))
      (libsource (lib "eagle-import") (part "SMD-RES-4.7K-5%-1/8W(0805)"))
    )
    (comp (ref "R239")
      (value "102")
      (footprint "eagle-import:R0805")
      (fields (field (name "MPN") "RC0805JR-071KL"))
      (libsource (lib "eagle-import") (part "SMD-RES-1K-5%-1/8W(0805)"))
    )
    (comp (ref "R240")
      (value "R_user")
      (footprint "eagle-import:R0805")
      (libsource (lib "eagle-import") (part "R-EU_R0805"))
    )
    (comp (ref "R241")
      (value "102")
      (footprint "eagle-import:R0805")
      (fields (field (name "MPN") "RC0805JR-07220RL"))
      (libsource (lib "eagle-import") (part "SMD-RES-220R-5%-1/8W(0805)"))
    )
    (comp (ref "R242")
      (value "(101)")
      (footprint "eagle-import:R0805")
      (fields (field (name "MPN") "RC0805JR-07100RL"))
      (libsource (lib "eagle-import") (part "SMD-RES-100R-5%-1/8W(0805)"))
    )
    (comp (ref "R243")
      (value "(1000)")
      (footprint "eagle-import:R0805")
      (fields (field (name "MPN") "RC0805JR-07100RL"))
      (libsource (lib "eagle-import") (part "SMD-RES-100R-5%-1/8W(0805)"))
    )
    (comp (ref "R244")
      (value "102")
      (footprint "eagle-import:R0805")
      (fields (field (name "MPN") "RC0805JR-071KL"))
      (libsource (lib "eagle-import") (part "SMD-RES-1K-5%-1/8W(0805)"))
    )
    (comp (ref "R245")
      (value "13")
      (footprint "eagle-import:R1206")
      (fields (field (name "MPN") "RC1206JR-0713RL"))
      (libsource (lib "eagle-import") (part "SMD-RES-13R-5%-1/4W(1206)"))
    )
    (comp (ref "R246")
      (value "13")
      (footprint "eagle-import:R1206")
      (fields (field (name "MPN") "RC1206JR-0713RL"))
      (libsource (lib "eagle-import") (part "SMD-RES-13R-5%-1/4W(1206)"))
    )
    (comp (ref "R247")
      (value "2702")
      (footprint "eagle-import:R0805")
      (fields (field (name "MPN") "RC0805JR-074K7L"))
      (libsource (lib "eagle-import") (part "SMD-RES-4.7K-5%-1/8W(0805)"))
    )
    (comp (ref "R248")
      (value "4701")
      (footprint "eagle-import:R0805")
      (fields (field (name "MPN") "RC0805JR-074K7L"))
      (libsource (lib "eagle-import") (part "SMD-RES-4.7K-5%-1/8W(0805)"))
    )
    (comp (ref "R249")
      (value "100")
      (footprint "eagle-import:R0805")
      (fields (field (name "MPN") "RC0805JR-072K2L"))
      (libsource (lib "eagle-import") (part "SMD-RES-2.2K-5%-1/8W(0805)"))
    )
    (comp (ref "R250")
      (value "104")
      (footprint "eagle-import:R0805")
      (fields (field (name "MPN") "RC0805FR-0710KL"))
      (libsource (lib "eagle-import") (part "SMD-RES-10K-1%-1/8W(0805)"))
    )
    (comp (ref "R251")
      (value "104")
      (footprint "eagle-import:R0805")
      (fields (field (name "MPN") "RC0805FR-0710KL"))
      (libsource (lib "eagle-import") (part "SMD-RES-10K-1%-1/8W(0805)"))
    )
    (comp (ref "R252")
      (value "(1002)")
      (footprint "eagle-import:R0805")
      (fields (field (name "MPN") "RC0805FR-0710KL"))
      (libsource (lib "eagle-import") (part "SMD-RES-10K-1%-1/8W(0805)"))
    )
    (comp (ref "R253")
      (value "2702")
      (footprint "eagle-import:R0805")
      (fields (field (name "MPN") "RC0805FR-0710KL"))
      (libsource (lib "eagle-import") (part "SMD-RES-10K-1%-1/8W(0805)"))
    )
    (comp (ref "R254")
      (value "47")
      (footprint "eagle-import:V235_17_1MM")
      (libsource (lib "eagle-import") (part "R-EU_V235/17_1MM"))
    )
    (comp (ref "R255")
      (value "47")
      (footprint "eagle-import:V235_17_1MM")
      (libsource (lib "eagle-import") (part "R-EU_V235/17_1MM"))
    )
    (comp (ref "R256")
      (value "2702")
      (footprint "eagle-import:R0805")
      (fields (field (name "MPN") "RC0805JR-074K7L"))
      (libsource (lib "eagle-import") (part "SMD-RES-4.7K-5%-1/8W(0805)"))
    )
    (comp (ref "R257")
      (value "2201")
      (footprint "eagle-import:R0805")
      (fields (field (name "MPN") "RC0805JR-072K2L"))
      (libsource (lib "eagle-import") (part "SMD-RES-2.2K-5%-1/8W(0805)"))
    )
    (comp (ref "R258")
      (value "1002")
      (footprint "eagle-import:R0805")
      (fields (field (name "MPN") "RC0805JR-074K7L"))
      (libsource (lib "eagle-import") (part "SMD-RES-4.7K-5%-1/8W(0805)"))
    )
    (comp (ref "R259")
      (value "1002")
      (footprint "eagle-import:R0805")
      (fields (field (name "MPN") "RC0805FR-0710KL"))
      (libsource (lib "eagle-import") (part "SMD-RES-10K-1%-1/8W(0805)"))
    )
    (comp (ref "R260")
      (value "102")
      (footprint "eagle-import:R0805")
      (fields (field (name "MPN") "RC0805JR-071KL"))
      (libsource (lib "eagle-import") (part "SMD-RES-1K-5%-1/8W(0805)"))
    )
    (comp (ref "R261")
      (value "2702")
      (footprint "eagle-import:R0805")
      (fields (field (name "MPN") "RC0805JR-074K7L"))
      (libsource (lib "eagle-import") (part "SMD-RES-4.7K-5%-1/8W(0805)"))
    )
    (comp (ref "R262")
      (value "1002")
      (footprint "eagle-import:R0805")
      (fields (field (name "MPN") "RC0805JR-071KL"))
      (libsource (lib "eagle-import") (part "SMD-RES-1K-5%-1/8W(0805)"))
    )
    (comp (ref "R263")
      (value "1002")
      (footprint "eagle-import:R0805")
      (fields (field (name "MPN") "RC0805JR-071KL"))
      (libsource (lib "eagle-import") (part "SMD-RES-1K-5%-1/8W(0805)"))
    )
    (comp (ref "R264")
      (value "R_user")
      (footprint "eagle-import:R0805")
      (libsource (lib "eagle-import") (part "R-EU_R0805"))
    )
    (comp (ref "R265")
      (value "104")
      (footprint "eagle-import:R0805")
      (fields (field (name "MPN") "RC0805FR-0710KL"))
      (libsource (lib "eagle-import") (part "SMD-RES-10K-1%-1/8W(0805)"))
    )
    (comp (ref "R266")
      (value "104")
      (footprint "eagle-import:R0805")
      (fields (field (name "MPN") "RC0805FR-0710KL"))
      (libsource (lib "eagle-import") (part "SMD-RES-10K-1%-1/8W(0805)"))
    )
    (comp (ref "R267")
      (value "104")
      (footprint "eagle-import:R0805")
      (fields (field (name "MPN") "RC0805FR-0710KL"))
      (libsource (lib "eagle-import") (part "SMD-RES-10K-1%-1/8W(0805)"))
    )
    (comp (ref "R268")
      (value "13")
      (footprint "eagle-import:R1206")
      (fields (field (name "MPN") "RC1206JR-0713RL"))
      (libsource (lib "eagle-import") (part "SMD-RES-13R-5%-1/4W(1206)"))
    )
    (comp (ref "R269")
      (value "2201")
      (footprint "eagle-import:R0805")
      (fields (field (name "MPN") "RC0805JR-071KL"))
      (libsource (lib "eagle-import") (part "SMD-RES-1K-5%-1/8W(0805)"))
    )
    (comp (ref "R270")
      (value "100")
      (footprint "eagle-import:R0805")
      (fields (field (name "MPN") "RC0805JR-07220RL"))
      (libsource (lib "eagle-import") (part "SMD-RES-220R-5%-1/8W(0805)"))
    )
    (comp (ref "R271")
      (value "13")
      (footprint "eagle-import:R1206")
      (fields (field (name "MPN") "RC1206JR-0713RL"))
      (libsource (lib "eagle-import") (part "SMD-RES-13R-5%-1/4W(1206)"))
    )
    (comp (ref "R272")
      (value "4701")
      (footprint "eagle-import:R0805")
      (fields (field (name "MPN") "RC0805JR-074K7L"))
      (libsource (lib "eagle-import") (part "SMD-RES-4.7K-5%-1/8W(0805)"))
    )
    (comp (ref "R273")
      (value "104")
      (footprint "eagle-import:R0805")
      (fields (field (name "MPN") "RC0805JR-074K7L"))
      (libsource (lib "eagle-import") (part "SMD-RES-4.7K-5%-1/8W(0805)"))
    )
    (comp (ref "R274")
      (value "2R")
      (footprint "eagle-import:R0805")
      (fields (field (name "MPN") "RC0805JR-072K2L"))
      (libsource (lib "eagle-import") (part "SMD-RES-2.2K-5%-1/8W(0805)"))
    )
    (comp (ref "R275")
      (value "2R")
      (footprint "eagle-import:R0805")
      (fields (field (name "MPN") "RC0805JR-072K2L"))
      (libsource (lib "eagle-import") (part "SMD-RES-2.2K-5%-1/8W(0805)"))
    )
    (comp (ref "SJ4")
      (value "SJ")
      (footprint "eagle-import:SJ")
      (libsource (lib "eagle-import") (part "solder-jumper_SJ"))
    )
    (comp (ref "SJMP4")
      (value "SJ")
      (footprint "eagle-import:SJ")
      (libsource (lib "eagle-import") (part "SJ"))
    )
    (comp (ref "START4")
      (value "TPSB2.0")
      (footprint "eagle-import:B2.0")
      (libsource (lib "eagle-import") (part "TPSB2.0"))
    )
    (comp (ref "TP93")
      (value "TPSB2.0")
      (footprint "eagle-import:B2.0")
      (libsource (lib "eagle-import") (part "TPSB2.0"))
    )
    (comp (ref "TP94")
      (value "TPSB2.0")
      (footprint "eagle-import:B2.0")
      (libsource (lib "eagle-import") (part "TPSB2.0"))
    )
    (comp (ref "TP95")
      (value "TPSB2.0")
      (footprint "eagle-import:B2.0")
      (libsource (lib "eagle-import") (part "TPSB2.0"))
    )
    (comp (ref "TP96")
      (value "TPSB2.0")
      (footprint "eagle-import:B2.0")
      (libsource (lib "eagle-import") (part "TPSB2.0"))
    )
    (comp (ref "TP97")
      (value "TPSB2.0")
      (footprint "eagle-import:B2.0")
      (libsource (lib "eagle-import") (part "TPSB2.0"))
    )
    (comp (ref "TP98")
      (value "TPSB2.0")
      (footprint "eagle-import:B2.0")
      (libsource (lib "eagle-import") (part "TPSB2.0"))
    )
    (comp (ref "TP99")
      (value "TPSB2.0")
      (footprint "eagle-import:B2.0")
      (libsource (lib "eagle-import") (part "TPSB2.0"))
    )
    (comp (ref "TP100")
      (value "TPSB2.0")
      (footprint "eagle-import:B2.0")
      (libsource (lib "eagle-import") (part "TPSB2.0"))
    )
    (comp (ref "TP101")
      (value "TPSB2.0")
      (footprint "eagle-import:B2.0")
      (libsource (lib "eagle-import") (part "TPSB2.0"))
    )
    (comp (ref "TP102")
      (value "TPSB2.0")
      (footprint "eagle-import:B2.0")
      (libsource (lib "eagle-import") (part "TPSB2.0"))
    )
    (comp (ref "TP103")
      (value "TPSB2.0")
      (footprint "eagle-import:B2.0")
      (libsource (lib "eagle-import") (part "TPSB2.0"))
    )
    (comp (ref "TP104")
      (value "TPSB2.0")
      (footprint "eagle-import:B2.0")
      (libsource (lib "eagle-import") (part "TPSB2.0"))
    )
    (comp (ref "TP105")
      (value "TPSB2.0")
      (footprint "eagle-import:B2.0")
      (libsource (lib "eagle-import") (part "TPSB2.0"))
    )
    (comp (ref "TP106")
      (value "TPSB2.0")
      (footprint "eagle-import:B2.0")
      (libsource (lib "eagle-import") (part "TPSB2.0"))
    )
    (comp (ref "TP107")
      (value "TPSB2.0")
      (footprint "eagle-import:B2.0")
      (libsource (lib "eagle-import") (part "TPSB2.0"))
    )
    (comp (ref "TP108")
      (value "TPSB2.0")
      (footprint "eagle-import:B2.0")
      (libsource (lib "eagle-import") (part "TPSB2.0"))
    )
    (comp (ref "TP109")
      (value "TPSB2.0")
      (footprint "eagle-import:B2.0")
      (libsource (lib "eagle-import") (part "TPSB2.0"))
    )
    (comp (ref "TP110")
      (value "TPSB2.0")
      (footprint "eagle-import:B2.0")
      (libsource (lib "eagle-import") (part "TPSB2.0"))
    )
    (comp (ref "TP111")
      (value "TPSB1,27")
      (footprint "eagle-import:B1,27")
      (libsource (lib "eagle-import") (part "TPSB1,27"))
    )
    (comp (ref "TP112")
      (value "TPSB2.0")
      (footprint "eagle-import:B2.0")
      (libsource (lib "eagle-import") (part "TPSB2.0"))
    )
    (comp (ref "TP113")
      (value "TPSB2.0")
      (footprint "eagle-import:B2.0")
      (libsource (lib "eagle-import") (part "TPSB2.0"))
    )
    (comp (ref "TP114")
      (value "TPSB2.0")
      (footprint "eagle-import:B2.0")
      (libsource (lib "eagle-import") (part "TPSB2.0"))
    )
    (comp (ref "TP115")
      (value "TPSB2.0")
      (footprint "eagle-import:B2.0")
      (libsource (lib "eagle-import") (part "TPSB2.0"))
    )
    (comp (ref "X10")
      (value "CON_BMWV2")
      (footprint "eagle-import:24-PIN_V2")
      (libsource (lib "eagle-import") (part "CON_BMWV2"))
    )
    (comp (ref "X11")
      (value "22-23-2051")
      (footprint "eagle-import:22-23-2051")
      (fields (field (name "MF") "MOLEX"))
      (libsource (lib "eagle-import") (part "22-23-2051"))
    )
    (comp (ref "X12")
      (value "22-23-2021")
      (footprint "eagle-import:22-23-2021")
      (fields (field (name "MF") "MOLEX"))
      (libsource (lib "eagle-import") (part "22-23-2021"))
    )
  )
  (nets
    (net (code "1") (name "+10V") (class "Default")
      (node (ref "10V") (pin "TP") (pinfunction "PP_TP") (pintype "input"))
      (node (ref "10V1") (pin "TP") (pinfunction "PP_TP") (pintype "input"))
      (node (ref "10V2") (pin "TP") (pinfunction "PP_TP") (pintype "input"))
      (node (ref "10V3") (pin "TP") (pinfunction "PP_TP") (pintype "input"))
      (node (ref "10V4") (pin "TP") (pinfunction "PP_TP") (pintype "input"))
      (node (ref "10V5") (pin "TP") (pinfunction "PP_TP") (pintype "input"))
      (node (ref "C102") (pin "1") (pinfunction "1_1") (pintype "passive"))
      (node (ref "C22") (pin "1") (pinfunction "1_1") (pintype "passive"))
      (node (ref "C34") (pin "1") (pinfunction "1_1") (pintype "passive"))
      (node (ref "C46") (pin "1") (pinfunction "1_1") (pintype "passive"))
      (node (ref "C58") (pin "1") (pinfunction "1_1") (pintype "passive"))
      (node (ref "C9") (pin "1") (pinfunction "1_1") (pintype "passive"))
      (node (ref "IC104") (pin "1") (pinfunction "OUT_1") (pintype "passive"))
      (node (ref "IC110") (pin "4") (pinfunction "R_4") (pintype "input"))
      (node (ref "IC110") (pin "8") (pinfunction "V+_8") (pintype "power_in"))
      (node (ref "IC111") (pin "13") (pinfunction "CD_13") (pintype "input"))
      (node (ref "IC111") (pin "16") (pinfunction "VDD_16") (pintype "power_in"))
      (node (ref "IC111") (pin "3") (pinfunction "CD_3") (pintype "input"))
      (node (ref "IC111") (pin "5") (pinfunction "B_5") (pintype "input"))
      (node (ref "IC15") (pin "4") (pinfunction "R_4") (pintype "input"))
      (node (ref "IC15") (pin "8") (pinfunction "V+_8") (pintype "power_in"))
      (node (ref "IC16") (pin "13") (pinfunction "CD_13") (pintype "input"))
      (node (ref "IC16") (pin "16") (pinfunction "VDD_16") (pintype "power_in"))
      (node (ref "IC16") (pin "3") (pinfunction "CD_3") (pintype "input"))
      (node (ref "IC16") (pin "5") (pinfunction "B_5") (pintype "input"))
      (node (ref "IC17") (pin "1") (pinfunction "OUT_1") (pintype "passive"))
      (node (ref "IC24") (pin "4") (pinfunction "R_4") (pintype "input"))
      (node (ref "IC24") (pin "8") (pinfunction "V+_8") (pintype "power_in"))
      (node (ref "IC25") (pin "13") (pinfunction "CD_13") (pintype "input"))
      (node (ref "IC25") (pin "16") (pinfunction "VDD_16") (pintype "power_in"))
      (node (ref "IC25") (pin "3") (pinfunction "CD_3") (pintype "input"))
      (node (ref "IC25") (pin "5") (pinfunction "B_5") (pintype "input"))
      (node (ref "IC26") (pin "1") (pinfunction "OUT_1") (pintype "passive"))
      (node (ref "IC33") (pin "4") (pinfunction "R_4") (pintype "input"))
      (node (ref "IC33") (pin "8") (pinfunction "V+_8") (pintype "power_in"))
      (node (ref "IC34") (pin "13") (pinfunction "CD_13") (pintype "input"))
      (node (ref "IC34") (pin "16") (pinfunction "VDD_16") (pintype "power_in"))
      (node (ref "IC34") (pin "3") (pinfunction "CD_3") (pintype "input"))
      (node (ref "IC34") (pin "5") (pinfunction "B_5") (pintype "input"))
      (node (ref "IC35") (pin "1") (pinfunction "OUT_1") (pintype "passive"))
      (node (ref "IC42") (pin "4") (pinfunction "R_4") (pintype "input"))
      (node (ref "IC42") (pin "8") (pinfunction "V+_8") (pintype "power_in"))
      (node (ref "IC43") (pin "13") (pinfunction "CD_13") (pintype "input"))
      (node (ref "IC43") (pin "16") (pinfunction "VDD_16") (pintype "power_in"))
      (node (ref "IC43") (pin "3") (pinfunction "CD_3") (pintype "input"))
      (node (ref "IC43") (pin "5") (pinfunction "B_5") (pintype "input"))
      (node (ref "IC44") (pin "1") (pinfunction "OUT_1") (pintype "passive"))
      (node (ref "IC6") (pin "4") (pinfunction "R_4") (pintype "input"))
      (node (ref "IC6") (pin "8") (pinfunction "V+_8") (pintype "power_in"))
      (node (ref "IC7") (pin "13") (pinfunction "CD_13") (pintype "input"))
      (node (ref "IC7") (pin "16") (pinfunction "VDD_16") (pintype "power_in"))
      (node (ref "IC7") (pin "3") (pinfunction "CD_3") (pintype "input"))
      (node (ref "IC7") (pin "5") (pinfunction "B_5") (pintype "input"))
      (node (ref "IC8") (pin "1") (pinfunction "OUT_1") (pintype "passive"))
      (node (ref "R10") (pin "2") (pinfunction "2_2") (pintype "passive"))
      (node (ref "R139") (pin "2") (pinfunction "2_2") (pintype "passive"))
      (node (ref "R145") (pin "2") (pinfunction "2_2") (pintype "passive"))
      (node (ref "R163") (pin "2") (pinfunction "2_2") (pintype "passive"))
      (node (ref "R201") (pin "2") (pinfunction "2_2") (pintype "passive"))
      (node (ref "R218") (pin "2") (pinfunction "2_2") (pintype "passive"))
      (node (ref "R256") (pin "2") (pinfunction "2_2") (pintype "passive"))
      (node (ref "R273") (pin "2") (pinfunction "2_2") (pintype "passive"))
      (node (ref "R311") (pin "2") (pinfunction "2_2") (pintype "passive"))
      (node (ref "R328") (pin "2") (pinfunction "2_2") (pintype "passive"))
      (node (ref "R47") (pin "2") (pinfunction "2_2") (pintype "passive"))
      (node (ref "R64") (pin "2") (pinfunction "2_2") (pintype "passive"))
    )
    (net (code "2") (name "+12V") (class "Default")
      (node (ref "10") (pin "1") (pinfunction "KL_1") (pintype "passive"))
      (node (ref "12") (pin "1") (pinfunction "KL_1") (pintype "passive"))
      (node (ref "2") (pin "1") (pinfunction "KL_1") (pintype "passive"))
      (node (ref "4") (pin "1") (pinfunction "KL_1") (pintype "passive"))
      (node (ref "6") (pin "1") (pinfunction "KL_1") (pintype "passive"))
      (node (ref "8") (pin "1") (pinfunction "KL_1") (pintype "passive"))
      (node (ref "C13") (pin "1") (pinfunction "1_1") (pintype "passive"))
      (node (ref "C2") (pin "1") (pinfunction "1_1") (pintype "passive"))
      (node (ref "C26") (pin "1") (pinfunction "1_1") (pintype "passive"))
      (node (ref "C38") (pin "1") (pinfunction "1_1") (pintype "passive"))
      (node (ref "C50") (pin "1") (pinfunction "1_1") (pintype "passive"))
      (node (ref "C62") (pin "1") (pinfunction "1_1") (pintype "passive"))
      (node (ref "D101") (pin "C") (pinfunction "C_C") (pintype "passive"))
      (node (ref "D13") (pin "C") (pinfunction "C_C") (pintype "passive"))
      (node (ref "D27") (pin "C") (pinfunction "C_C") (pintype "passive"))
      (node (ref "D41") (pin "C") (pinfunction "C_C") (pintype "passive"))
      (node (ref "D55") (pin "C") (pinfunction "C_C") (pintype "passive"))
      (node (ref "D69") (pin "C") (pinfunction "C_C") (pintype "passive"))
      (node (ref "IC1") (pin "16") (pinfunction "VDD_16") (pintype "power_in"))
      (node (ref "IC10") (pin "16") (pinfunction "VDD_16") (pintype "power_in"))
      (node (ref "IC102") (pin "3") (pinfunction "IN_3") (pintype "input"))
      (node (ref "IC104") (pin "3") (pinfunction "IN_3") (pintype "input"))
      (node (ref "IC105") (pin "16") (pinfunction "VDD_16") (pintype "power_in"))
      (node (ref "IC107") (pin "9") (pinfunction "CD+_9") (pintype "passive"))
      (node (ref "IC12") (pin "9") (pinfunction "CD+_9") (pintype "passive"))
      (node (ref "IC14") (pin "3") (pinfunction "IN_3") (pintype "input"))
      (node (ref "IC17") (pin "3") (pinfunction "IN_3") (pintype "input"))
      (node (ref "IC19") (pin "16") (pinfunction "VDD_16") (pintype "power_in"))
      (node (ref "IC21") (pin "9") (pinfunction "CD+_9") (pintype "passive"))
      (node (ref "IC23") (pin "3") (pinfunction "IN_3") (pintype "input"))
      (node (ref "IC26") (pin "3") (pinfunction "IN_3") (pintype "input"))
      (node (ref "IC28") (pin "16") (pinfunction "VDD_16") (pintype "power_in"))
      (node (ref "IC3") (pin "9") (pinfunction "CD+_9") (pintype "passive"))
      (node (ref "IC30") (pin "9") (pinfunction "CD+_9") (pintype "passive"))
      (node (ref "IC32") (pin "3") (pinfunction "IN_3") (pintype "input"))
      (node (ref "IC35") (pin "3") (pinfunction "IN_3") (pintype "input"))
      (node (ref "IC37") (pin "16") (pinfunction "VDD_16") (pintype "power_in"))
      (node (ref "IC39") (pin "9") (pinfunction "CD+_9") (pintype "passive"))
      (node (ref "IC41") (pin "3") (pinfunction "IN_3") (pintype "input"))
      (node (ref "IC44") (pin "3") (pinfunction "IN_3") (pintype "input"))
      (node (ref "IC5") (pin "3") (pinfunction "IN_3") (pintype "input"))
      (node (ref "IC8") (pin "3") (pinfunction "IN_3") (pintype "input"))
      (node (ref "JP1") (pin "2") (pinfunction "2_2") (pintype "passive"))
      (node (ref "JP101") (pin "2") (pinfunction "2_2") (pintype "passive"))
      (node (ref "JP11") (pin "2") (pinfunction "2_2") (pintype "passive"))
      (node (ref "JP16") (pin "2") (pinfunction "2_2") (pintype "passive"))
      (node (ref "JP21") (pin "2") (pinfunction "2_2") (pintype "passive"))
      (node (ref "JP6") (pin "2") (pinfunction "2_2") (pintype "passive"))
      (node (ref "R102") (pin "1") (pinfunction "1_1") (pintype "passive"))
      (node (ref "R106") (pin "1") (pinfunction "1_1") (pintype "passive"))
      (node (ref "R109") (pin "2") (pinfunction "2_2") (pintype "passive"))
      (node (ref "R110") (pin "2") (pinfunction "2_2") (pintype "passive"))
      (node (ref "R111") (pin "2") (pinfunction "2_2") (pintype "passive"))
      (node (ref "R12") (pin "2") (pinfunction "2_2") (pintype "passive"))
      (node (ref "R13") (pin "2") (pinfunction "2_2") (pintype "passive"))
      (node (ref "R135") (pin "1") (pinfunction "1_1") (pintype "passive"))
      (node (ref "R15") (pin "2") (pinfunction "2_2") (pintype "passive"))
      (node (ref "R16") (pin "2") (pinfunction "2_2") (pintype "passive"))
      (node (ref "R164") (pin "2") (pinfunction "2_2") (pintype "passive"))
      (node (ref "R165") (pin "2") (pinfunction "2_2") (pintype "passive"))
      (node (ref "R169") (pin "2") (pinfunction "2_2") (pintype "passive"))
      (node (ref "R17") (pin "2") (pinfunction "2_2") (pintype "passive"))
      (node (ref "R170") (pin "2") (pinfunction "2_2") (pintype "passive"))
      (node (ref "R171") (pin "2") (pinfunction "2_2") (pintype "passive"))
      (node (ref "R190") (pin "1") (pinfunction "1_1") (pintype "passive"))
      (node (ref "R191") (pin "1") (pinfunction "1_1") (pintype "passive"))
      (node (ref "R195") (pin "1") (pinfunction "1_1") (pintype "passive"))
      (node (ref "R219") (pin "2") (pinfunction "2_2") (pintype "passive"))
      (node (ref "R220") (pin "2") (pinfunction "2_2") (pintype "passive"))
      (node (ref "R224") (pin "2") (pinfunction "2_2") (pintype "passive"))
      (node (ref "R225") (pin "2") (pinfunction "2_2") (pintype "passive"))
      (node (ref "R226") (pin "2") (pinfunction "2_2") (pintype "passive"))
      (node (ref "R245") (pin "1") (pinfunction "1_1") (pintype "passive"))
      (node (ref "R246") (pin "1") (pinfunction "1_1") (pintype "passive"))
      (node (ref "R250") (pin "1") (pinfunction "1_1") (pintype "passive"))
      (node (ref "R274") (pin "2") (pinfunction "2_2") (pintype "passive"))
      (node (ref "R275") (pin "2") (pinfunction "2_2") (pintype "passive"))
      (node (ref "R279") (pin "2") (pinfunction "2_2") (pintype "passive"))
      (node (ref "R280") (pin "2") (pinfunction "2_2") (pintype "passive"))
      (node (ref "R281") (pin "2") (pinfunction "2_2") (pintype "passive"))
      (node (ref "R300") (pin "1") (pinfunction "1_1") (pintype "passive"))
      (node (ref "R301") (pin "1") (pinfunction "1_1") (pintype "passive"))
      (node (ref "R305") (pin "1") (pinfunction "1_1") (pintype "passive"))
      (node (ref "R329") (pin "2") (pinfunction "2_2") (pintype "passive"))
      (node (ref "R330") (pin "2") (pinfunction "2_2") (pintype "passive"))
      (node (ref "R36") (pin "1") (pinfunction "1_1") (pintype "passive"))
      (node (ref "R37") (pin "1") (pinfunction "1_1") (pintype "passive"))
      (node (ref "R41") (pin "1") (pinfunction "1_1") (pintype "passive"))
      (node (ref "R65") (pin "2") (pinfunction "2_2") (pintype "passive"))
      (node (ref "R66") (pin "2") (pinfunction "2_2") (pintype "passive"))
      (node (ref "R70") (pin "2") (pinfunction "2_2") (pintype "passive"))
      (node (ref "R71") (pin "2") (pinfunction "2_2") (pintype "passive"))
      (node (ref "R72") (pin "2") (pinfunction "2_2") (pintype "passive"))
      (node (ref "R91") (pin "1") (pinfunction "1_1") (pintype "passive"))
      (node (ref "R92") (pin "1") (pinfunction "1_1") (pintype "passive"))
      (node (ref "R96") (pin "1") (pinfunction "1_1") (pintype "passive"))
      (node (ref "TP114") (pin "TP") (pinfunction "PP_TP") (pintype "input"))
      (node (ref "TP12") (pin "TP") (pinfunction "PP_TP") (pintype "input"))
      (node (ref "TP137") (pin "TP") (pinfunction "PP_TP") (pintype "input"))
      (node (ref "TP45") (pin "TP") (pinfunction "PP_TP") (pintype "input"))
      (node (ref "TP68") (pin "TP") (pinfunction "PP_TP") (pintype "input"))
      (node (ref "TP91") (pin "TP") (pinfunction "PP_TP") (pintype "input"))
      (node (ref "X103") (pin "1") (pinfunction "S_1") (pintype "passive"))
      (node (ref "X11") (pin "1") (pinfunction "S_1") (pintype "passive"))
      (node (ref "X14") (pin "1") (pinfunction "S_1") (pintype "passive"))
      (node (ref "X2") (pin "1") (pinfunction "S_1") (pintype "passive"))
      (node (ref "X5") (pin "1") (pinfunction "S_1") (pintype "passive"))
      (node (ref "X8") (pin "1") (pinfunction "S_1") (pintype "passive"))
    )
    (net (code "3") (name "GND") (class "Default")
      (node (ref "1") (pin "12") (pinfunction "KL_12") (pintype "passive"))
      (node (ref "11") (pin "12") (pinfunction "KL_12") (pintype "passive"))
      (node (ref "3") (pin "12") (pinfunction "KL_12") (pintype "passive"))
      (node (ref "5") (pin "12") (pinfunction "KL_12") (pintype "passive"))
      (node (ref "7") (pin "12") (pinfunction "KL_12") (pintype "passive"))
      (node (ref "9") (pin "12") (pinfunction "KL_12") (pintype "passive"))
      (node (ref "C1") (pin "2") (pinfunction "2_2") (pintype "passive"))
      (node (ref "C10") (pin "2") (pinfunction "2_2") (pintype "passive"))
      (node (ref "C101") (pin "2") (pinfunction "2_2") (pintype "passive"))
      (node (ref "C102") (pin "2") (pinfunction "2_2") (pintype "passive"))
      (node (ref "C103") (pin "2") (pinfunction "2_2") (pintype "passive"))
      (node (ref "C104") (pin "2") (pinfunction "2_2") (pintype "passive"))
      (node (ref "C105") (pin "2") (pinfunction "2_2") (pintype "passive"))
      (node (ref "C106") (pin "1") (pinfunction "1_1") (pintype "passive"))
      (node (ref "C107") (pin "2") (pinfunction "2_2") (pintype "passive"))
      (node (ref "C108") (pin "2") (pinfunction "2_2") (pintype "passive"))
      (node (ref "C109") (pin "1") (pinfunction "1_1") (pintype "passive"))
      (node (ref "C11") (pin "2") (pinfunction "2_2") (pintype "passive"))
      (node (ref "C110") (pin "2") (pinfunction "2_2") (pintype "passive"))
      (node (ref "C12") (pin "1") (pinfunction "1_1") (pintype "passive"))
      (node (ref "C13") (pin "2") (pinfunction "2_2") (pintype "passive"))
      (node (ref "C14") (pin "2") (pinfunction "2_2") (pintype "passive"))
      (node (ref "C15") (pin "1") (pinfunction "1_1") (pintype "passive"))
      (node (ref "C16") (pin "2") (pinfunction "2_2") (pintype "passive"))
      (node (ref "C17") (pin "2") (pinfunction "2_2") (pintype "passive"))
      (node (ref "C18") (pin "2") (pinfunction "2_2") (pintype "passive"))
      (node (ref "C19") (pin "2") (pinfunction "2_2") (pintype "passive"))
      (node (ref "C2") (pin "2") (pinfunction "2_2") (pintype "passive"))
      (node (ref "C20") (pin "1") (pinfunction "1_1") (pintype "passive"))
      (node (ref "C21") (pin "1") (pinfunction "1_1") (pintype "passive"))
      (node (ref "C22") (pin "2") (pinfunction "2_2") (pintype "passive"))
      (node (ref "C23") (pin "2") (pinfunction "2_2") (pintype "passive"))
      (node (ref "C24") (pin "2") (pinfunction "2_2") (pintype "passive"))
      (node (ref "C25") (pin "1") (pinfunction "1_1") (pintype "passive"))
      (node (ref "C26") (pin "2") (pinfunction "2_2") (pintype "passive"))
      (node (ref "C27") (pin "2") (pinfunction "2_2") (pintype "passive"))
      (node (ref "C28") (pin "2") (pinfunction "2_2") (pintype "passive"))
      (node (ref "C29") (pin "2") (pinfunction "2_2") (pintype "passive"))
      (node (ref "C3") (pin "2") (pinfunction "2_2") (pintype "passive"))
      (node (ref "C30") (pin "2") (pinfunction "2_2") (pintype "passive"))
      (node (ref "C31") (pin "2") (pinfunction "2_2") (pintype "passive"))
      (node (ref "C32") (pin "1") (pinfunction "1_1") (pintype "passive"))
      (node (ref "C33") (pin "1") (pinfunction "1_1") (pintype "passive"))
      (node (ref "C34") (pin "2") (pinfunction "2_2") (pintype "passive"))
      (node (ref "C35") (pin "2") (pinfunction "2_2") (pintype "passive"))
      (node (ref "C36") (pin "2") (pinfunction "2_2") (pintype "passive"))
      (node (ref "C37") (pin "1") (pinfunction "1_1") (pintype "passive"))
      (node (ref "C38") (pin "2") (pinfunction "2_2") (pintype "passive"))
      (node (ref "C39") (pin "2") (pinfunction "2_2") (pintype "passive"))
      (node (ref "C4") (pin "2") (pinfunction "2_2") (pintype "passive"))
      (node (ref "C40") (pin "2") (pinfunction "2_2") (pintype "passive"))
      (node (ref "C41") (pin "2") (pinfunction "2_2") (pintype "passive"))
      (node (ref "C42") (pin "2") (pinfunction "2_2") (pintype "passive"))
      (node (ref "C43") (pin "2") (pinfunction "2_2") (pintype "passive"))
      (node (ref "C44") (pin "1") (pinfunction "1_1") (pintype "passive"))
      (node (ref "C45") (pin "1") (pinfunction "1_1") (pintype "passive"))
      (node (ref "C46") (pin "2") (pinfunction "2_2") (pintype "passive"))
      (node (ref "C47") (pin "2") (pinfunction "2_2") (pintype "passive"))
      (node (ref "C48") (pin "2") (pinfunction "2_2") (pintype "passive"))
      (node (ref "C49") (pin "1") (pinfunction "1_1") (pintype "passive"))
      (node (ref "C5") (pin "2") (pinfunction "2_2") (pintype "passive"))
      (node (ref "C50") (pin "2") (pinfunction "2_2") (pintype "passive"))
      (node (ref "C51") (pin "2") (pinfunction "2_2") (pintype "passive"))
      (node (ref "C52") (pin "2") (pinfunction "2_2") (pintype "passive"))
      (node (ref "C53") (pin "2") (pinfunction "2_2") (pintype "passive"))
      (node (ref "C54") (pin "2") (pinfunction "2_2") (pintype "passive"))
      (node (ref "C55") (pin "2") (pinfunction "2_2") (pintype "passive"))
      (node (ref "C56") (pin "1") (pinfunction "1_1") (pintype "passive"))
      (node (ref "C57") (pin "1") (pinfunction "1_1") (pintype "passive"))
      (node (ref "C58") (pin "2") (pinfunction "2_2") (pintype "passive"))
      (node (ref "C59") (pin "2") (pinfunction "2_2") (pintype "passive"))
      (node (ref "C6") (pin "2") (pinfunction "2_2") (pintype "passive"))
      (node (ref "C60") (pin "2") (pinfunction "2_2") (pintype "passive"))
      (node (ref "C61") (pin "1") (pinfunction "1_1") (pintype "passive"))
      (node (ref "C62") (pin "2") (pinfunction "2_2") (pintype "passive"))
      (node (ref "C7") (pin "1") (pinfunction "1_1") (pintype "passive"))
      (node (ref "C8") (pin "1") (pinfunction "1_1") (pintype "passive"))
      (node (ref "C9") (pin "2") (pinfunction "2_2") (pintype "passive"))
      (node (ref "D101") (pin "A") (pinfunction "A_A") (pintype "passive"))
      (node (ref "D104") (pin "A") (pinfunction "A_A") (pintype "passive"))
      (node (ref "D105") (pin "1") (pinfunction "+_1") (pintype "passive"))
      (node (ref "D11") (pin "1") (pinfunction "+_1") (pintype "passive"))
      (node (ref "D13") (pin "A") (pinfunction "A_A") (pintype "passive"))
      (node (ref "D14") (pin "A") (pinfunction "A_A") (pintype "passive"))
      (node (ref "D17") (pin "A") (pinfunction "A_A") (pintype "passive"))
      (node (ref "D25") (pin "1") (pinfunction "+_1") (pintype "passive"))
      (node (ref "D27") (pin "A") (pinfunction "A_A") (pintype "passive"))
      (node (ref "D28") (pin "A") (pinfunction "A_A") (pintype "passive"))
      (node (ref "D31") (pin "A") (pinfunction "A_A") (pintype "passive"))
      (node (ref "D39") (pin "1") (pinfunction "+_1") (pintype "passive"))
      (node (ref "D4") (pin "A") (pinfunction "A_A") (pintype "passive"))
      (node (ref "D41") (pin "A") (pinfunction "A_A") (pintype "passive"))
      (node (ref "D42") (pin "A") (pinfunction "A_A") (pintype "passive"))
      (node (ref "D45") (pin "A") (pinfunction "A_A") (pintype "passive"))
      (node (ref "D53") (pin "1") (pinfunction "+_1") (pintype "passive"))
      (node (ref "D55") (pin "A") (pinfunction "A_A") (pintype "passive"))
      (node (ref "D56") (pin "A") (pinfunction "A_A") (pintype "passive"))
      (node (ref "D59") (pin "A") (pinfunction "A_A") (pintype "passive"))
      (node (ref "D67") (pin "1") (pinfunction "+_1") (pintype "passive"))
      (node (ref "D69") (pin "A") (pinfunction "A_A") (pintype "passive"))
      (node (ref "D70") (pin "A") (pinfunction "A_A") (pintype "passive"))
      (node (ref "D73") (pin "A") (pinfunction "A_A") (pintype "passive"))
      (node (ref "IC1") (pin "11") (pinfunction "D_11") (pintype "input"))
      (node (ref "IC1") (pin "8") (pinfunction "VSS_8") (pintype "power_in"))
      (node (ref "IC10") (pin "11") (pinfunction "D_11") (pintype "input"))
      (node (ref "IC10") (pin "8") (pinfunction "VSS_8") (pintype "power_in"))
      (node (ref "IC101") (pin "4") (pinfunction "V-_4") (pintype "power_in"))
      (node (ref "IC102") (pin "2") (pinfunction "GND_2") (pintype "input"))
      (node (ref "IC102") (pin "2@1") (pinfunction "GND_2@1") (pintype "input"))
      (node (ref "IC104") (pin "2") (pinfunction "GND_2") (pintype "input"))
      (node (ref "IC104") (pin "2@1") (pinfunction "GND_2@1") (pintype "input"))
      (node (ref "IC105") (pin "11") (pinfunction "D_11") (pintype "input"))
      (node (ref "IC105") (pin "8") (pinfunction "VSS_8") (pintype "power_in"))
      (node (ref "IC107") (pin "8") (pinfunction "GND_8") (pintype "power_in"))
      (node (ref "IC108") (pin "12") (pinfunction "GND_12") (pintype "power_in"))
      (node (ref "IC110") (pin "1") (pinfunction "GND_1") (pintype "power_in"))
      (node (ref "IC111") (pin "1") (pinfunction "T1_1") (pintype "input"))
      (node (ref "IC111") (pin "15") (pinfunction "T1_15") (pintype "input"))
      (node (ref "IC111") (pin "8") (pinfunction "VSS_8") (pintype "power_in"))
      (node (ref "IC12") (pin "8") (pinfunction "GND_8") (pintype "power_in"))
      (node (ref "IC13") (pin "12") (pinfunction "GND_12") (pintype "power_in"))
      (node (ref "IC14") (pin "2") (pinfunction "GND_2") (pintype "input"))
      (node (ref "IC14") (pin "2@1") (pinfunction "GND_2@1") (pintype "input"))
      (node (ref "IC15") (pin "1") (pinfunction "GND_1") (pintype "power_in"))
      (node (ref "IC16") (pin "1") (pinfunction "T1_1") (pintype "input"))
      (node (ref "IC16") (pin "15") (pinfunction "T1_15") (pintype "input"))
      (node (ref "IC16") (pin "8") (pinfunction "VSS_8") (pintype "power_in"))
      (node (ref "IC17") (pin "2") (pinfunction "GND_2") (pintype "input"))
      (node (ref "IC17") (pin "2@1") (pinfunction "GND_2@1") (pintype "input"))
      (node (ref "IC18") (pin "4") (pinfunction "V-_4") (pintype "power_in"))
      (node (ref "IC19") (pin "11") (pinfunction "D_11") (pintype "input"))
      (node (ref "IC19") (pin "8") (pinfunction "VSS_8") (pintype "power_in"))
      (node (ref "IC21") (pin "8") (pinfunction "GND_8") (pintype "power_in"))
      (node (ref "IC22") (pin "12") (pinfunction "GND_12") (pintype "power_in"))
      (node (ref "IC23") (pin "2") (pinfunction "GND_2") (pintype "input"))
      (node (ref "IC23") (pin "2@1") (pinfunction "GND_2@1") (pintype "input"))
      (node (ref "IC24") (pin "1") (pinfunction "GND_1") (pintype "power_in"))
      (node (ref "IC25") (pin "1") (pinfunction "T1_1") (pintype "input"))
      (node (ref "IC25") (pin "15") (pinfunction "T1_15") (pintype "input"))
      (node (ref "IC25") (pin "8") (pinfunction "VSS_8") (pintype "power_in"))
      (node (ref "IC26") (pin "2") (pinfunction "GND_2") (pintype "input"))
      (node (ref "IC26") (pin "2@1") (pinfunction "GND_2@1") (pintype "input"))
      (node (ref "IC27") (pin "4") (pinfunction "V-_4") (pintype "power_in"))
      (node (ref "IC28") (pin "11") (pinfunction "D_11") (pintype "input"))
      (node (ref "IC28") (pin "8") (pinfunction "VSS_8") (pintype "power_in"))
      (node (ref "IC3") (pin "8") (pinfunction "GND_8") (pintype "power_in"))
      (node (ref "IC30") (pin "8") (pinfunction "GND_8") (pintype "power_in"))
      (node (ref "IC31") (pin "12") (pinfunction "GND_12") (pintype "power_in"))
      (node (ref "IC32") (pin "2") (pinfunction "GND_2") (pintype "input"))
      (node (ref "IC32") (pin "2@1") (pinfunction "GND_2@1") (pintype "input"))
      (node (ref "IC33") (pin "1") (pinfunction "GND_1") (pintype "power_in"))
      (node (ref "IC34") (pin "1") (pinfunction "T1_1") (pintype "input"))
      (node (ref "IC34") (pin "15") (pinfunction "T1_15") (pintype "input"))
      (node (ref "IC34") (pin "8") (pinfunction "VSS_8") (pintype "power_in"))
      (node (ref "IC35") (pin "2") (pinfunction "GND_2") (pintype "input"))
      (node (ref "IC35") (pin "2@1") (pinfunction "GND_2@1") (pintype "input"))
      (node (ref "IC36") (pin "4") (pinfunction "V-_4") (pintype "power_in"))
      (node (ref "IC37") (pin "11") (pinfunction "D_11") (pintype "input"))
      (node (ref "IC37") (pin "8") (pinfunction "VSS_8") (pintype "power_in"))
      (node (ref "IC39") (pin "8") (pinfunction "GND_8") (pintype "power_in"))
      (node (ref "IC4") (pin "12") (pinfunction "GND_12") (pintype "power_in"))
      (node (ref "IC40") (pin "12") (pinfunction "GND_12") (pintype "power_in"))
      (node (ref "IC41") (pin "2") (pinfunction "GND_2") (pintype "input"))
      (node (ref "IC41") (pin "2@1") (pinfunction "GND_2@1") (pintype "input"))
      (node (ref "IC42") (pin "1") (pinfunction "GND_1") (pintype "power_in"))
      (node (ref "IC43") (pin "1") (pinfunction "T1_1") (pintype "input"))
      (node (ref "IC43") (pin "15") (pinfunction "T1_15") (pintype "input"))
      (node (ref "IC43") (pin "8") (pinfunction "VSS_8") (pintype "power_in"))
      (node (ref "IC44") (pin "2") (pinfunction "GND_2") (pintype "input"))
      (node (ref "IC44") (pin "2@1") (pinfunction "GND_2@1") (pintype "input"))
      (node (ref "IC45") (pin "4") (pinfunction "V-_4") (pintype "power_in"))
      (node (ref "IC5") (pin "2") (pinfunction "GND_2") (pintype "input"))
      (node (ref "IC5") (pin "2@1") (pinfunction "GND_2@1") (pintype "input"))
      (node (ref "IC6") (pin "1") (pinfunction "GND_1") (pintype "power_in"))
      (node (ref "IC7") (pin "1") (pinfunction "T1_1") (pintype "input"))
      (node (ref "IC7") (pin "15") (pinfunction "T1_15") (pintype "input"))
      (node (ref "IC7") (pin "8") (pinfunction "VSS_8") (pintype "power_in"))
      (node (ref "IC8") (pin "2") (pinfunction "GND_2") (pintype "input"))
      (node (ref "IC8") (pin "2@1") (pinfunction "GND_2@1") (pintype "input"))
      (node (ref "IC9") (pin "4") (pinfunction "V-_4") (pintype "power_in"))
      (node (ref "Q1") (pin "2") (pinfunction "S_2") (pintype "passive"))
      (node (ref "Q107") (pin "2") (pinfunction "S_2") (pintype "passive"))
      (node (ref "Q11") (pin "2") (pinfunction "S_2") (pintype "passive"))
      (node (ref "Q13") (pin "2") (pinfunction "S_2") (pintype "passive"))
      (node (ref "Q19") (pin "2") (pinfunction "S_2") (pintype "passive"))
      (node (ref "Q21") (pin "2") (pinfunction "S_2") (pintype "passive"))
      (node (ref "Q23") (pin "2") (pinfunction "S_2") (pintype "passive"))
      (node (ref "Q29") (pin "2") (pinfunction "S_2") (pintype "passive"))
      (node (ref "Q3") (pin "2") (pinfunction "S_2") (pintype "passive"))
      (node (ref "Q31") (pin "2") (pinfunction "S_2") (pintype "passive"))
      (node (ref "Q33") (pin "2") (pinfunction "S_2") (pintype "passive"))
      (node (ref "Q39") (pin "2") (pinfunction "S_2") (pintype "passive"))
      (node (ref "Q41") (pin "2") (pinfunction "S_2") (pintype "passive"))
      (node (ref "Q43") (pin "2") (pinfunction "S_2") (pintype "passive"))
      (node (ref "Q49") (pin "2") (pinfunction "S_2") (pintype "passive"))
      (node (ref "Q51") (pin "2") (pinfunction "S_2") (pintype "passive"))
      (node (ref "Q53") (pin "2") (pinfunction "S_2") (pintype "passive"))
      (node (ref "Q9") (pin "2") (pinfunction "S_2") (pintype "passive"))
      (node (ref "R100") (pin "1") (pinfunction "1_1") (pintype "passive"))
      (node (ref "R101") (pin "2") (pinfunction "2_2") (pintype "passive"))
      (node (ref "R103") (pin "2") (pinfunction "2_2") (pintype "passive"))
      (node (ref "R104") (pin "2") (pinfunction "2_2") (pintype "passive"))
      (node (ref "R107") (pin "1") (pinfunction "1_1") (pintype "passive"))
      (node (ref "R114") (pin "1") (pinfunction "1_1") (pintype "passive"))
      (node (ref "R118") (pin "1") (pinfunction "1_1") (pintype "passive"))
      (node (ref "R123") (pin "1") (pinfunction "1_1") (pintype "passive"))
      (node (ref "R132") (pin "1") (pinfunction "1_1") (pintype "passive"))
      (node (ref "R136") (pin "1") (pinfunction "1_1") (pintype "passive"))
      (node (ref "R137") (pin "1") (pinfunction "1_1") (pintype "passive"))
      (node (ref "R141") (pin "2") (pinfunction "2_2") (pintype "passive"))
      (node (ref "R143") (pin "2") (pinfunction "2_2") (pintype "passive"))
      (node (ref "R153") (pin "1") (pinfunction "1_1") (pintype "passive"))
      (node (ref "R154") (pin "2") (pinfunction "2_2") (pintype "passive"))
      (node (ref "R158") (pin "2") (pinfunction "2_2") (pintype "passive"))
      (node (ref "R159") (pin "2") (pinfunction "2_2") (pintype "passive"))
      (node (ref "R160") (pin "1") (pinfunction "1_1") (pintype "passive"))
      (node (ref "R173") (pin "1") (pinfunction "1_1") (pintype "passive"))
      (node (ref "R179") (pin "1") (pinfunction "1_1") (pintype "passive"))
      (node (ref "R183") (pin "1") (pinfunction "1_1") (pintype "passive"))
      (node (ref "R184") (pin "2") (pinfunction "2_2") (pintype "passive"))
      (node (ref "R185") (pin "2") (pinfunction "2_2") (pintype "passive"))
      (node (ref "R187") (pin "2") (pinfunction "2_2") (pintype "passive"))
      (node (ref "R19") (pin "1") (pinfunction "1_1") (pintype "passive"))
      (node (ref "R196") (pin "2") (pinfunction "2_2") (pintype "passive"))
      (node (ref "R199") (pin "1") (pinfunction "1_1") (pintype "passive"))
      (node (ref "R200") (pin "1") (pinfunction "1_1") (pintype "passive"))
      (node (ref "R208") (pin "1") (pinfunction "1_1") (pintype "passive"))
      (node (ref "R209") (pin "2") (pinfunction "2_2") (pintype "passive"))
      (node (ref "R213") (pin "2") (pinfunction "2_2") (pintype "passive"))
      (node (ref "R214") (pin "2") (pinfunction "2_2") (pintype "passive"))
      (node (ref "R215") (pin "1") (pinfunction "1_1") (pintype "passive"))
      (node (ref "R228") (pin "1") (pinfunction "1_1") (pintype "passive"))
      (node (ref "R234") (pin "1") (pinfunction "1_1") (pintype "passive"))
      (node (ref "R238") (pin "1") (pinfunction "1_1") (pintype "passive"))
      (node (ref "R239") (pin "2") (pinfunction "2_2") (pintype "passive"))
      (node (ref "R240") (pin "2") (pinfunction "2_2") (pintype "passive"))
      (node (ref "R242") (pin "2") (pinfunction "2_2") (pintype "passive"))
      (node (ref "R25") (pin "1") (pinfunction "1_1") (pintype "passive"))
      (node (ref "R251") (pin "2") (pinfunction "2_2") (pintype "passive"))
      (node (ref "R254") (pin "1") (pinfunction "1_1") (pintype "passive"))
      (node (ref "R255") (pin "1") (pinfunction "1_1") (pintype "passive"))
      (node (ref "R263") (pin "1") (pinfunction "1_1") (pintype "passive"))
      (node (ref "R264") (pin "2") (pinfunction "2_2") (pintype "passive"))
      (node (ref "R268") (pin "2") (pinfunction "2_2") (pintype "passive"))
      (node (ref "R269") (pin "2") (pinfunction "2_2") (pintype "passive"))
      (node (ref "R270") (pin "1") (pinfunction "1_1") (pintype "passive"))
      (node (ref "R283") (pin "1") (pinfunction "1_1") (pintype "passive"))
      (node (ref "R289") (pin "1") (pinfunction "1_1") (pintype "passive"))
      (node (ref "R29") (pin "1") (pinfunction "1_1") (pintype "passive"))
      (node (ref "R293") (pin "1") (pinfunction "1_1") (pintype "passive"))
      (node (ref "R294") (pin "2") (pinfunction "2_2") (pintype "passive"))
      (node (ref "R295") (pin "2") (pinfunction "2_2") (pintype "passive"))
      (node (ref "R297") (pin "2") (pinfunction "2_2") (pintype "passive"))
      (node (ref "R30") (pin "2") (pinfunction "2_2") (pintype "passive"))
      (node (ref "R306") (pin "2") (pinfunction "2_2") (pintype "passive"))
      (node (ref "R309") (pin "1") (pinfunction "1_1") (pintype "passive"))
      (node (ref "R31") (pin "2") (pinfunction "2_2") (pintype "passive"))
      (node (ref "R310") (pin "1") (pinfunction "1_1") (pintype "passive"))
      (node (ref "R318") (pin "1") (pinfunction "1_1") (pintype "passive"))
      (node (ref "R319") (pin "2") (pinfunction "2_2") (pintype "passive"))
      (node (ref "R323") (pin "2") (pinfunction "2_2") (pintype "passive"))
      (node (ref "R324") (pin "2") (pinfunction "2_2") (pintype "passive"))
      (node (ref "R325") (pin "1") (pinfunction "1_1") (pintype "passive"))
      (node (ref "R33") (pin "2") (pinfunction "2_2") (pintype "passive"))
      (node (ref "R4") (pin "1") (pinfunction "1_1") (pintype "passive"))
      (node (ref "R42") (pin "2") (pinfunction "2_2") (pintype "passive"))
      (node (ref "R45") (pin "1") (pinfunction "1_1") (pintype "passive"))
      (node (ref "R46") (pin "1") (pinfunction "1_1") (pintype "passive"))
      (node (ref "R5") (pin "2") (pinfunction "2_2") (pintype "passive"))
      (node (ref "R54") (pin "1") (pinfunction "1_1") (pintype "passive"))
      (node (ref "R55") (pin "2") (pinfunction "2_2") (pintype "passive"))
      (node (ref "R59") (pin "2") (pinfunction "2_2") (pintype "passive"))
      (node (ref "R6") (pin "2") (pinfunction "2_2") (pintype "passive"))
      (node (ref "R60") (pin "2") (pinfunction "2_2") (pintype "passive"))
      (node (ref "R61") (pin "1") (pinfunction "1_1") (pintype "passive"))
      (node (ref "R74") (pin "1") (pinfunction "1_1") (pintype "passive"))
      (node (ref "R80") (pin "1") (pinfunction "1_1") (pintype "passive"))
      (node (ref "R84") (pin "1") (pinfunction "1_1") (pintype "passive"))
      (node (ref "R85") (pin "2") (pinfunction "2_2") (pintype "passive"))
      (node (ref "R86") (pin "2") (pinfunction "2_2") (pintype "passive"))
      (node (ref "R88") (pin "2") (pinfunction "2_2") (pintype "passive"))
      (node (ref "R97") (pin "2") (pinfunction "2_2") (pintype "passive"))
      (node (ref "X1") (pin "13") (pinfunction "13_13") (pintype "passive"))
      (node (ref "X1") (pin "18") (pinfunction "18_18") (pintype "passive"))
      (node (ref "X1") (pin "23") (pinfunction "23_23") (pintype "passive"))
      (node (ref "X10") (pin "13") (pinfunction "13_13") (pintype "passive"))
      (node (ref "X10") (pin "18") (pinfunction "18_18") (pintype "passive"))
      (node (ref "X10") (pin "23") (pinfunction "23_23") (pintype "passive"))
      (node (ref "X101") (pin "13") (pinfunction "13_13") (pintype "passive"))
      (node (ref "X101") (pin "18") (pinfunction "18_18") (pintype "passive"))
      (node (ref "X101") (pin "23") (pinfunction "23_23") (pintype "passive"))
      (node (ref "X102") (pin "1") (pinfunction "S_1") (pintype "passive"))
      (node (ref "X103") (pin "5") (pinfunction "S_5") (pintype "passive"))
      (node (ref "X11") (pin "5") (pinfunction "S_5") (pintype "passive"))
      (node (ref "X12") (pin "1") (pinfunction "S_1") (pintype "passive"))
      (node (ref "X13") (pin "13") (pinfunction "13_13") (pintype "passive"))
      (node (ref "X13") (pin "18") (pinfunction "18_18") (pintype "passive"))
      (node (ref "X13") (pin "23") (pinfunction "23_23") (pintype "passive"))
      (node (ref "X14") (pin "5") (pinfunction "S_5") (pintype "passive"))
      (node (ref "X15") (pin "1") (pinfunction "S_1") (pintype "passive"))
      (node (ref "X2") (pin "5") (pinfunction "S_5") (pintype "passive"))
      (node (ref "X3") (pin "1") (pinfunction "S_1") (pintype "passive"))
      (node (ref "X4") (pin "13") (pinfunction "13_13") (pintype "passive"))
      (node (ref "X4") (pin "18") (pinfunction "18_18") (pintype "passive"))
      (node (ref "X4") (pin "23") (pinfunction "23_23") (pintype "passive"))
      (node (ref "X5") (pin "5") (pinfunction "S_5") (pintype "passive"))
      (node (ref "X6") (pin "1") (pinfunction "S_1") (pintype "passive"))
      (node (ref "X7") (pin "13") (pinfunction "13_13") (pintype "passive"))
      (node (ref "X7") (pin "18") (pinfunction "18_18") (pintype "passive"))
      (node (ref "X7") (pin "23") (pinfunction "23_23") (pintype "passive"))
      (node (ref "X8") (pin "5") (pinfunction "S_5") (pintype "passive"))
      (node (ref "X9") (pin "1") (pinfunction "S_1") (pintype "passive"))
    )
    (net (code "4") (name "Net-(1A-KL)") (class "Default")
      (node (ref "1") (pin "1") (pinfunction "KL_1") (pintype "passive"))
      (node (ref "D2") (pin "2") (pinfunction "-_2") (pintype "passive"))
      (node (ref "TP1") (pin "TP") (pinfunction "PP_TP") (pintype "input"))
    )
    (net (code "5") (name "Net-(1B-KL)") (class "Default")
      (node (ref "1") (pin "10") (pinfunction "KL_10") (pintype "passive"))
      (node (ref "D102") (pin "2") (pinfunction "-_2") (pintype "passive"))
      (node (ref "D103") (pin "2") (pinfunction "-_2") (pintype "passive"))
      (node (ref "JP104") (pin "1") (pinfunction "1_1") (pintype "passive"))
      (node (ref "SJ101") (pin "1") (pinfunction "1_1") (pintype "passive"))
      (node (ref "TP10") (pin "TP") (pinfunction "PP_TP") (pintype "input"))
    )
    (net (code "6") (name "Net-(1C-KL)") (class "Default")
      (node (ref "1") (pin "11") (pinfunction "KL_11") (pintype "passive"))
      (node (ref "D103") (pin "1") (pinfunction "+_1") (pintype "passive"))
      (node (ref "TP11") (pin "TP") (pinfunction "PP_TP") (pintype "input"))
      (node (ref "X101") (pin "19") (pinfunction "19_19") (pintype "passive"))
    )
    (net (code "7") (name "Net-(1E-KL)") (class "Default")
      (node (ref "1") (pin "2") (pinfunction "KL_2") (pintype "passive"))
      (node (ref "Q101") (pin "2") (pinfunction "C_2") (pintype "passive"))
      (node (ref "TP2") (pin "TP") (pinfunction "PP_TP") (pintype "input"))
    )
    (net (code "8") (name "Net-(1F-KL)") (class "Default")
      (node (ref "1") (pin "3") (pinfunction "KL_3") (pintype "passive"))
      (node (ref "IC107") (pin "11") (pinfunction "O6_11") (pintype "open_collector"))
      (node (ref "TP3") (pin "TP") (pinfunction "PP_TP") (pintype "input"))
    )
    (net (code "9") (name "Net-(1G-KL)") (class "Default")
      (node (ref "1") (pin "4") (pinfunction "KL_4") (pintype "passive"))
      (node (ref "IC107") (pin "10") (pinfunction "O7_10") (pintype "open_collector"))
      (node (ref "TP4") (pin "TP") (pinfunction "PP_TP") (pintype "input"))
    )
    (net (code "10") (name "Net-(1H-KL)") (class "Default")
      (node (ref "1") (pin "5") (pinfunction "KL_5") (pintype "passive"))
      (node (ref "IC107") (pin "12") (pinfunction "O5_12") (pintype "open_collector"))
      (node (ref "TP5") (pin "TP") (pinfunction "PP_TP") (pintype "input"))
    )
    (net (code "11") (name "Net-(1I-KL)") (class "Default")
      (node (ref "1") (pin "6") (pinfunction "KL_6") (pintype "passive"))
      (node (ref "IC107") (pin "13") (pinfunction "O4_13") (pintype "open_collector"))
      (node (ref "TP6") (pin "TP") (pinfunction "PP_TP") (pintype "input"))
    )
    (net (code "12") (name "Net-(1J-KL)") (class "Default")
      (node (ref "1") (pin "7") (pinfunction "KL_7") (pintype "passive"))
      (node (ref "IC107") (pin "14") (pinfunction "O3_14") (pintype "open_collector"))
      (node (ref "TP7") (pin "TP") (pinfunction "PP_TP") (pintype "input"))
    )
    (net (code "13") (name "Net-(1K-KL)") (class "Default")
      (node (ref "1") (pin "8") (pinfunction "KL_8") (pintype "passive"))
      (node (ref "R9") (pin "2") (pinfunction "2_2") (pintype "passive"))
      (node (ref "TP8") (pin "TP") (pinfunction "PP_TP") (pintype "input"))
    )
    (net (code "14") (name "Net-(1L-KL)") (class "Default")
      (node (ref "1") (pin "9") (pinfunction "KL_9") (pintype "passive"))
      (node (ref "D102") (pin "1") (pinfunction "+_1") (pintype "passive"))
      (node (ref "TP9") (pin "TP") (pinfunction "PP_TP") (pintype "input"))
      (node (ref "X101") (pin "17") (pinfunction "17_17") (pintype "passive"))
    )
    (net (code "15") (name "Net-(2B-KL)") (class "Default")
      (node (ref "2") (pin "10") (pinfunction "KL_10") (pintype "passive"))
      (node (ref "TP25") (pin "TP") (pinfunction "PP_TP") (pintype "input"))
      (node (ref "X101") (pin "15") (pinfunction "15_15") (pintype "passive"))
    )
    (net (code "16") (name "Net-(2C-KL)") (class "Default")
      (node (ref "2") (pin "11") (pinfunction "KL_11") (pintype "passive"))
      (node (ref "Q103") (pin "2") (pinfunction "C_2") (pintype "passive"))
      (node (ref "R119") (pin "1") (pinfunction "1_1") (pintype "passive"))
      (node (ref "TP26") (pin "TP") (pinfunction "PP_TP") (pintype "input"))
    )
    (net (code "17") (name "Net-(2D-KL)") (class "Default")
      (node (ref "2") (pin "12") (pinfunction "KL_12") (pintype "passive"))
      (node (ref "R146") (pin "1") (pinfunction "1_1") (pintype "passive"))
      (node (ref "TP13") (pin "TP") (pinfunction "PP_TP") (pintype "input"))
    )
    (net (code "18") (name "Net-(2E-KL)") (class "Default")
      (node (ref "2") (pin "2") (pinfunction "KL_2") (pintype "passive"))
      (node (ref "D109") (pin "2") (pinfunction "-_2") (pintype "passive"))
      (node (ref "LED102") (pin "K") (pinfunction "C_K") (pintype "passive"))
      (node (ref "TP16") (pin "TP") (pinfunction "PP_TP") (pintype "input"))
      (node (ref "X101") (pin "12") (pinfunction "12_12") (pintype "passive"))
    )
    (net (code "19") (name "Net-(2F-KL)") (class "Default")
      (node (ref "2") (pin "3") (pinfunction "KL_3") (pintype "passive"))
      (node (ref "D108") (pin "2") (pinfunction "-_2") (pintype "passive"))
      (node (ref "LED103") (pin "K") (pinfunction "C_K") (pintype "passive"))
      (node (ref "TP17") (pin "TP") (pinfunction "PP_TP") (pintype "input"))
      (node (ref "X101") (pin "11") (pinfunction "11_11") (pintype "passive"))
    )
    (net (code "20") (name "Net-(2G-KL)") (class "Default")
      (node (ref "2") (pin "4") (pinfunction "KL_4") (pintype "passive"))
      (node (ref "D107") (pin "2") (pinfunction "-_2") (pintype "passive"))
      (node (ref "LED104") (pin "K") (pinfunction "C_K") (pintype "passive"))
      (node (ref "TP18") (pin "TP") (pinfunction "PP_TP") (pintype "input"))
      (node (ref "X101") (pin "10") (pinfunction "10_10") (pintype "passive"))
    )
    (net (code "21") (name "Net-(2H-KL)") (class "Default")
      (node (ref "2") (pin "5") (pinfunction "KL_5") (pintype "passive"))
      (node (ref "D106") (pin "2") (pinfunction "-_2") (pintype "passive"))
      (node (ref "LED105") (pin "K") (pinfunction "C_K") (pintype "passive"))
      (node (ref "TP19") (pin "TP") (pinfunction "PP_TP") (pintype "input"))
      (node (ref "X101") (pin "9") (pinfunction "9_9") (pintype "passive"))
    )
    (net (code "22") (name "Net-(2I-KL)") (class "Default")
      (node (ref "2") (pin "6") (pinfunction "KL_6") (pintype "passive"))
      (node (ref "JP105") (pin "2") (pinfunction "2_2") (pintype "passive"))
      (node (ref "TP21") (pin "TP") (pinfunction "PP_TP") (pintype "input"))
    )
    (net (code "23") (name "Net-(2J-KL)") (class "Default")
      (node (ref "2") (pin "7") (pinfunction "KL_7") (pintype "passive"))
      (node (ref "LED101") (pin "A") (pinfunction "A_A") (pintype "passive"))
      (node (ref "TP22") (pin "TP") (pinfunction "PP_TP") (pintype "input"))
      (node (ref "X101") (pin "8") (pinfunction "8_8") (pintype "passive"))
    )
    (net (code "24") (name "Net-(2K-KL)") (class "Default")
      (node (ref "2") (pin "8") (pinfunction "KL_8") (pintype "passive"))
      (node (ref "D110") (pin "2") (pinfunction "-_2") (pintype "passive"))
      (node (ref "LED106") (pin "K") (pinfunction "C_K") (pintype "passive"))
      (node (ref "TP23") (pin "TP") (pinfunction "PP_TP") (pintype "input"))
      (node (ref "X101") (pin "14") (pinfunction "14_14") (pintype "passive"))
    )
    (net (code "25") (name "Net-(2L-KL)") (class "Default")
      (node (ref "2") (pin "9") (pinfunction "KL_9") (pintype "passive"))
      (node (ref "D107") (pin "1") (pinfunction "+_1") (pintype "passive"))
      (node (ref "D108") (pin "1") (pinfunction "+_1") (pintype "passive"))
      (node (ref "JP102") (pin "1") (pinfunction "1_1") (pintype "passive"))
      (node (ref "JP103") (pin "2") (pinfunction "2_2") (pintype "passive"))
      (node (ref "TP24") (pin "TP") (pinfunction "PP_TP") (pintype "input"))
    )
    (net (code "26") (name "Net-(3A-KL)") (class "Default")
      (node (ref "3") (pin "1") (pinfunction "KL_1") (pintype "passive"))
      (node (ref "D16") (pin "2") (pinfunction "-_2") (pintype "passive"))
      (node (ref "TP14") (pin "TP") (pinfunction "PP_TP") (pintype "input"))
    )
    (net (code "27") (name "Net-(3B-KL)") (class "Default")
      (node (ref "3") (pin "10") (pinfunction "KL_10") (pintype "passive"))
      (node (ref "D3") (pin "2") (pinfunction "-_2") (pintype "passive"))
      (node (ref "D5") (pin "2") (pinfunction "-_2") (pintype "passive"))
      (node (ref "JP5") (pin "1") (pinfunction "1_1") (pintype "passive"))
      (node (ref "SJ1") (pin "1") (pinfunction "1_1") (pintype "passive"))
      (node (ref "TP33") (pin "TP") (pinfunction "PP_TP") (pintype "input"))
    )
    (net (code "28") (name "Net-(3C-KL)") (class "Default")
      (node (ref "3") (pin "11") (pinfunction "KL_11") (pintype "passive"))
      (node (ref "D5") (pin "1") (pinfunction "+_1") (pintype "passive"))
      (node (ref "TP34") (pin "TP") (pinfunction "PP_TP") (pintype "input"))
      (node (ref "X1") (pin "19") (pinfunction "19_19") (pintype "passive"))
    )
    (net (code "29") (name "Net-(3E-KL)") (class "Default")
      (node (ref "3") (pin "2") (pinfunction "KL_2") (pintype "passive"))
      (node (ref "Q6") (pin "2") (pinfunction "C_2") (pintype "passive"))
      (node (ref "TP15") (pin "TP") (pinfunction "PP_TP") (pintype "input"))
    )
    (net (code "30") (name "Net-(3F-KL)") (class "Default")
      (node (ref "3") (pin "3") (pinfunction "KL_3") (pintype "passive"))
      (node (ref "IC3") (pin "11") (pinfunction "O6_11") (pintype "open_collector"))
      (node (ref "TP20") (pin "TP") (pinfunction "PP_TP") (pintype "input"))
    )
    (net (code "31") (name "Net-(3G-KL)") (class "Default")
      (node (ref "3") (pin "4") (pinfunction "KL_4") (pintype "passive"))
      (node (ref "IC3") (pin "10") (pinfunction "O7_10") (pintype "open_collector"))
      (node (ref "TP27") (pin "TP") (pinfunction "PP_TP") (pintype "input"))
    )
    (net (code "32") (name "Net-(3H-KL)") (class "Default")
      (node (ref "3") (pin "5") (pinfunction "KL_5") (pintype "passive"))
      (node (ref "IC3") (pin "12") (pinfunction "O5_12") (pintype "open_collector"))
      (node (ref "TP28") (pin "TP") (pinfunction "PP_TP") (pintype "input"))
    )
    (net (code "33") (name "Net-(3I-KL)") (class "Default")
      (node (ref "3") (pin "6") (pinfunction "KL_6") (pintype "passive"))
      (node (ref "IC3") (pin "13") (pinfunction "O4_13") (pintype "open_collector"))
      (node (ref "TP29") (pin "TP") (pinfunction "PP_TP") (pintype "input"))
    )
    (net (code "34") (name "Net-(3J-KL)") (class "Default")
      (node (ref "3") (pin "7") (pinfunction "KL_7") (pintype "passive"))
      (node (ref "IC3") (pin "14") (pinfunction "O3_14") (pintype "open_collector"))
      (node (ref "TP30") (pin "TP") (pinfunction "PP_TP") (pintype "input"))
    )
    (net (code "35") (name "Net-(3K-KL)") (class "Default")
      (node (ref "3") (pin "8") (pinfunction "KL_8") (pintype "passive"))
      (node (ref "R62") (pin "2") (pinfunction "2_2") (pintype "passive"))
      (node (ref "TP31") (pin "TP") (pinfunction "PP_TP") (pintype "input"))
    )
    (net (code "36") (name "Net-(3L-KL)") (class "Default")
      (node (ref "3") (pin "9") (pinfunction "KL_9") (pintype "passive"))
      (node (ref "D3") (pin "1") (pinfunction "+_1") (pintype "passive"))
      (node (ref "TP32") (pin "TP") (pinfunction "PP_TP") (pintype "input"))
      (node (ref "X1") (pin "17") (pinfunction "17_17") (pintype "passive"))
    )
    (net (code "37") (name "Net-(4B-KL)") (class "Default")
      (node (ref "4") (pin "10") (pinfunction "KL_10") (pintype "passive"))
      (node (ref "TP43") (pin "TP") (pinfunction "PP_TP") (pintype "input"))
      (node (ref "X1") (pin "15") (pinfunction "15_15") (pintype "passive"))
    )
    (net (code "38") (name "Net-(4C-KL)") (class "Default")
      (node (ref "4") (pin "11") (pinfunction "KL_11") (pintype "passive"))
      (node (ref "Q8") (pin "2") (pinfunction "C_2") (pintype "passive"))
      (node (ref "R48") (pin "1") (pinfunction "1_1") (pintype "passive"))
      (node (ref "TP44") (pin "TP") (pinfunction "PP_TP") (pintype "input"))
    )
    (net (code "39") (name "Net-(4D-KL)") (class "Default")
      (node (ref "4") (pin "12") (pinfunction "KL_12") (pintype "passive"))
      (node (ref "R49") (pin "1") (pinfunction "1_1") (pintype "passive"))
      (node (ref "TP46") (pin "TP") (pinfunction "PP_TP") (pintype "input"))
    )
    (net (code "40") (name "Net-(4E-KL)") (class "Default")
      (node (ref "4") (pin "2") (pinfunction "KL_2") (pintype "passive"))
      (node (ref "D9") (pin "2") (pinfunction "-_2") (pintype "passive"))
      (node (ref "LED1") (pin "K") (pinfunction "C_K") (pintype "passive"))
      (node (ref "TP35") (pin "TP") (pinfunction "PP_TP") (pintype "input"))
      (node (ref "X1") (pin "12") (pinfunction "12_12") (pintype "passive"))
    )
    (net (code "41") (name "Net-(4F-KL)") (class "Default")
      (node (ref "4") (pin "3") (pinfunction "KL_3") (pintype "passive"))
      (node (ref "D8") (pin "2") (pinfunction "-_2") (pintype "passive"))
      (node (ref "LED2") (pin "K") (pinfunction "C_K") (pintype "passive"))
      (node (ref "TP36") (pin "TP") (pinfunction "PP_TP") (pintype "input"))
      (node (ref "X1") (pin "11") (pinfunction "11_11") (pintype "passive"))
    )
    (net (code "42") (name "Net-(4G-KL)") (class "Default")
      (node (ref "4") (pin "4") (pinfunction "KL_4") (pintype "passive"))
      (node (ref "D7") (pin "2") (pinfunction "-_2") (pintype "passive"))
      (node (ref "LED3") (pin "K") (pinfunction "C_K") (pintype "passive"))
      (node (ref "TP37") (pin "TP") (pinfunction "PP_TP") (pintype "input"))
      (node (ref "X1") (pin "10") (pinfunction "10_10") (pintype "passive"))
    )
    (net (code "43") (name "Net-(4H-KL)") (class "Default")
      (node (ref "4") (pin "5") (pinfunction "KL_5") (pintype "passive"))
      (node (ref "D6") (pin "2") (pinfunction "-_2") (pintype "passive"))
      (node (ref "LED4") (pin "K") (pinfunction "C_K") (pintype "passive"))
      (node (ref "TP38") (pin "TP") (pinfunction "PP_TP") (pintype "input"))
      (node (ref "X1") (pin "9") (pinfunction "9_9") (pintype "passive"))
    )
    (net (code "44") (name "Net-(4I-KL)") (class "Default")
      (node (ref "4") (pin "6") (pinfunction "KL_6") (pintype "passive"))
      (node (ref "JP2") (pin "2") (pinfunction "2_2") (pintype "passive"))
      (node (ref "TP39") (pin "TP") (pinfunction "PP_TP") (pintype "input"))
    )
    (net (code "45") (name "Net-(4J-KL)") (class "Default")
      (node (ref "4") (pin "7") (pinfunction "KL_7") (pintype "passive"))
      (node (ref "LED5") (pin "A") (pinfunction "A_A") (pintype "passive"))
      (node (ref "TP40") (pin "TP") (pinfunction "PP_TP") (pintype "input"))
      (node (ref "X1") (pin "8") (pinfunction "8_8") (pintype "passive"))
    )
    (net (code "46") (name "Net-(4K-KL)") (class "Default")
      (node (ref "4") (pin "8") (pinfunction "KL_8") (pintype "passive"))
      (node (ref "D10") (pin "2") (pinfunction "-_2") (pintype "passive"))
      (node (ref "LED6") (pin "K") (pinfunction "C_K") (pintype "passive"))
      (node (ref "TP41") (pin "TP") (pinfunction "PP_TP") (pintype "input"))
      (node (ref "X1") (pin "14") (pinfunction "14_14") (pintype "passive"))
    )
    (net (code "47") (name "Net-(4L-KL)") (class "Default")
      (node (ref "4") (pin "9") (pinfunction "KL_9") (pintype "passive"))
      (node (ref "D7") (pin "1") (pinfunction "+_1") (pintype "passive"))
      (node (ref "D8") (pin "1") (pinfunction "+_1") (pintype "passive"))
      (node (ref "JP3") (pin "1") (pinfunction "1_1") (pintype "passive"))
      (node (ref "JP4") (pin "2") (pinfunction "2_2") (pintype "passive"))
      (node (ref "TP42") (pin "TP") (pinfunction "PP_TP") (pintype "input"))
    )
    (net (code "48") (name "Net-(5A-KL)") (class "Default")
      (node (ref "5") (pin "1") (pinfunction "KL_1") (pintype "passive"))
      (node (ref "D30") (pin "2") (pinfunction "-_2") (pintype "passive"))
      (node (ref "TP47") (pin "TP") (pinfunction "PP_TP") (pintype "input"))
    )
    (net (code "49") (name "Net-(5B-KL)") (class "Default")
      (node (ref "5") (pin "10") (pinfunction "KL_10") (pintype "passive"))
      (node (ref "D18") (pin "2") (pinfunction "-_2") (pintype "passive"))
      (node (ref "D19") (pin "2") (pinfunction "-_2") (pintype "passive"))
      (node (ref "JP10") (pin "1") (pinfunction "1_1") (pintype "passive"))
      (node (ref "SJ2") (pin "1") (pinfunction "1_1") (pintype "passive"))
      (node (ref "TP56") (pin "TP") (pinfunction "PP_TP") (pintype "input"))
    )
    (net (code "50") (name "Net-(5C-KL)") (class "Default")
      (node (ref "5") (pin "11") (pinfunction "KL_11") (pintype "passive"))
      (node (ref "D19") (pin "1") (pinfunction "+_1") (pintype "passive"))
      (node (ref "TP57") (pin "TP") (pinfunction "PP_TP") (pintype "input"))
      (node (ref "X4") (pin "19") (pinfunction "19_19") (pintype "passive"))
    )
    (net (code "51") (name "Net-(5E-KL)") (class "Default")
      (node (ref "5") (pin "2") (pinfunction "KL_2") (pintype "passive"))
      (node (ref "Q16") (pin "2") (pinfunction "C_2") (pintype "passive"))
      (node (ref "TP48") (pin "TP") (pinfunction "PP_TP") (pintype "input"))
    )
    (net (code "52") (name "Net-(5F-KL)") (class "Default")
      (node (ref "5") (pin "3") (pinfunction "KL_3") (pintype "passive"))
      (node (ref "IC12") (pin "11") (pinfunction "O6_11") (pintype "open_collector"))
      (node (ref "TP49") (pin "TP") (pinfunction "PP_TP") (pintype "input"))
    )
    (net (code "53") (name "Net-(5G-KL)") (class "Default")
      (node (ref "5") (pin "4") (pinfunction "KL_4") (pintype "passive"))
      (node (ref "IC12") (pin "10") (pinfunction "O7_10") (pintype "open_collector"))
      (node (ref "TP50") (pin "TP") (pinfunction "PP_TP") (pintype "input"))
    )
    (net (code "54") (name "Net-(5H-KL)") (class "Default")
      (node (ref "5") (pin "5") (pinfunction "KL_5") (pintype "passive"))
      (node (ref "IC12") (pin "12") (pinfunction "O5_12") (pintype "open_collector"))
      (node (ref "TP51") (pin "TP") (pinfunction "PP_TP") (pintype "input"))
    )
    (net (code "55") (name "Net-(5I-KL)") (class "Default")
      (node (ref "5") (pin "6") (pinfunction "KL_6") (pintype "passive"))
      (node (ref "IC12") (pin "13") (pinfunction "O4_13") (pintype "open_collector"))
      (node (ref "TP52") (pin "TP") (pinfunction "PP_TP") (pintype "input"))
    )
    (net (code "56") (name "Net-(5J-KL)") (class "Default")
      (node (ref "5") (pin "7") (pinfunction "KL_7") (pintype "passive"))
      (node (ref "IC12") (pin "14") (pinfunction "O3_14") (pintype "open_collector"))
      (node (ref "TP53") (pin "TP") (pinfunction "PP_TP") (pintype "input"))
    )
    (net (code "57") (name "Net-(5K-KL)") (class "Default")
      (node (ref "5") (pin "8") (pinfunction "KL_8") (pintype "passive"))
      (node (ref "R161") (pin "2") (pinfunction "2_2") (pintype "passive"))
      (node (ref "TP54") (pin "TP") (pinfunction "PP_TP") (pintype "input"))
    )
    (net (code "58") (name "Net-(5L-KL)") (class "Default")
      (node (ref "5") (pin "9") (pinfunction "KL_9") (pintype "passive"))
      (node (ref "D18") (pin "1") (pinfunction "+_1") (pintype "passive"))
      (node (ref "TP55") (pin "TP") (pinfunction "PP_TP") (pintype "input"))
      (node (ref "X4") (pin "17") (pinfunction "17_17") (pintype "passive"))
    )
    (net (code "59") (name "Net-(6B-KL)") (class "Default")
      (node (ref "6") (pin "10") (pinfunction "KL_10") (pintype "passive"))
      (node (ref "TP66") (pin "TP") (pinfunction "PP_TP") (pintype "input"))
      (node (ref "X4") (pin "15") (pinfunction "15_15") (pintype "passive"))
    )
    (net (code "60") (name "Net-(6C-KL)") (class "Default")
      (node (ref "6") (pin "11") (pinfunction "KL_11") (pintype "passive"))
      (node (ref "Q18") (pin "2") (pinfunction "C_2") (pintype "passive"))
      (node (ref "R147") (pin "1") (pinfunction "1_1") (pintype "passive"))
      (node (ref "TP67") (pin "TP") (pinfunction "PP_TP") (pintype "input"))
    )
    (net (code "61") (name "Net-(6D-KL)") (class "Default")
      (node (ref "6") (pin "12") (pinfunction "KL_12") (pintype "passive"))
      (node (ref "R148") (pin "1") (pinfunction "1_1") (pintype "passive"))
      (node (ref "TP69") (pin "TP") (pinfunction "PP_TP") (pintype "input"))
    )
    (net (code "62") (name "Net-(6E-KL)") (class "Default")
      (node (ref "6") (pin "2") (pinfunction "KL_2") (pintype "passive"))
      (node (ref "D23") (pin "2") (pinfunction "-_2") (pintype "passive"))
      (node (ref "LED7") (pin "K") (pinfunction "C_K") (pintype "passive"))
      (node (ref "TP58") (pin "TP") (pinfunction "PP_TP") (pintype "input"))
      (node (ref "X4") (pin "12") (pinfunction "12_12") (pintype "passive"))
    )
    (net (code "63") (name "Net-(6F-KL)") (class "Default")
      (node (ref "6") (pin "3") (pinfunction "KL_3") (pintype "passive"))
      (node (ref "D22") (pin "2") (pinfunction "-_2") (pintype "passive"))
      (node (ref "LED8") (pin "K") (pinfunction "C_K") (pintype "passive"))
      (node (ref "TP59") (pin "TP") (pinfunction "PP_TP") (pintype "input"))
      (node (ref "X4") (pin "11") (pinfunction "11_11") (pintype "passive"))
    )
    (net (code "64") (name "Net-(6G-KL)") (class "Default")
      (node (ref "6") (pin "4") (pinfunction "KL_4") (pintype "passive"))
      (node (ref "D21") (pin "2") (pinfunction "-_2") (pintype "passive"))
      (node (ref "LED9") (pin "K") (pinfunction "C_K") (pintype "passive"))
      (node (ref "TP60") (pin "TP") (pinfunction "PP_TP") (pintype "input"))
      (node (ref "X4") (pin "10") (pinfunction "10_10") (pintype "passive"))
    )
    (net (code "65") (name "Net-(6H-KL)") (class "Default")
      (node (ref "6") (pin "5") (pinfunction "KL_5") (pintype "passive"))
      (node (ref "D20") (pin "2") (pinfunction "-_2") (pintype "passive"))
      (node (ref "LED10") (pin "K") (pinfunction "C_K") (pintype "passive"))
      (node (ref "TP61") (pin "TP") (pinfunction "PP_TP") (pintype "input"))
      (node (ref "X4") (pin "9") (pinfunction "9_9") (pintype "passive"))
    )
    (net (code "66") (name "Net-(6I-KL)") (class "Default")
      (node (ref "6") (pin "6") (pinfunction "KL_6") (pintype "passive"))
      (node (ref "JP7") (pin "2") (pinfunction "2_2") (pintype "passive"))
      (node (ref "TP62") (pin "TP") (pinfunction "PP_TP") (pintype "input"))
    )
    (net (code "67") (name "Net-(6J-KL)") (class "Default")
      (node (ref "6") (pin "7") (pinfunction "KL_7") (pintype "passive"))
      (node (ref "LED11") (pin "A") (pinfunction "A_A") (pintype "passive"))
      (node (ref "TP63") (pin "TP") (pinfunction "PP_TP") (pintype "input"))
      (node (ref "X4") (pin "8") (pinfunction "8_8") (pintype "passive"))
    )
    (net (code "68") (name "Net-(6K-KL)") (class "Default")
      (node (ref "6") (pin "8") (pinfunction "KL_8") (pintype "passive"))
      (node (ref "D24") (pin "2") (pinfunction "-_2") (pintype "passive"))
      (node (ref "LED12") (pin "K") (pinfunction "C_K") (pintype "passive"))
      (node (ref "TP64") (pin "TP") (pinfunction "PP_TP") (pintype "input"))
      (node (ref "X4") (pin "14") (pinfunction "14_14") (pintype "passive"))
    )
    (net (code "69") (name "Net-(6L-KL)") (class "Default")
      (node (ref "6") (pin "9") (pinfunction "KL_9") (pintype "passive"))
      (node (ref "D21") (pin "1") (pinfunction "+_1") (pintype "passive"))
      (node (ref "D22") (pin "1") (pinfunction "+_1") (pintype "passive"))
      (node (ref "JP8") (pin "1") (pinfunction "1_1") (pintype "passive"))
      (node (ref "JP9") (pin "2") (pinfunction "2_2") (pintype "passive"))
      (node (ref "TP65") (pin "TP") (pinfunction "PP_TP") (pintype "input"))
    )
    (net (code "70") (name "Net-(7A-KL)") (class "Default")
      (node (ref "7") (pin "1") (pinfunction "KL_1") (pintype "passive"))
      (node (ref "D44") (pin "2") (pinfunction "-_2") (pintype "passive"))
      (node (ref "TP70") (pin "TP") (pinfunction "PP_TP") (pintype "input"))
    )
    (net (code "71") (name "Net-(7B-KL)") (class "Default")
      (node (ref "7") (pin "10") (pinfunction "KL_10") (pintype "passive"))
      (node (ref "D32") (pin "2") (pinfunction "-_2") (pintype "passive"))
      (node (ref "D33") (pin "2") (pinfunction "-_2") (pintype "passive"))
      (node (ref "JP15") (pin "1") (pinfunction "1_1") (pintype "passive"))
      (node (ref "SJ3") (pin "1") (pinfunction "1_1") (pintype "passive"))
      (node (ref "TP79") (pin "TP") (pinfunction "PP_TP") (pintype "input"))
    )
    (net (code "72") (name "Net-(7C-KL)") (class "Default")
      (node (ref "7") (pin "11") (pinfunction "KL_11") (pintype "passive"))
      (node (ref "D33") (pin "1") (pinfunction "+_1") (pintype "passive"))
      (node (ref "TP80") (pin "TP") (pinfunction "PP_TP") (pintype "input"))
      (node (ref "X7") (pin "19") (pinfunction "19_19") (pintype "passive"))
    )
    (net (code "73") (name "Net-(7E-KL)") (class "Default")
      (node (ref "7") (pin "2") (pinfunction "KL_2") (pintype "passive"))
      (node (ref "Q26") (pin "2") (pinfunction "C_2") (pintype "passive"))
      (node (ref "TP71") (pin "TP") (pinfunction "PP_TP") (pintype "input"))
    )
    (net (code "74") (name "Net-(7F-KL)") (class "Default")
      (node (ref "7") (pin "3") (pinfunction "KL_3") (pintype "passive"))
      (node (ref "IC21") (pin "11") (pinfunction "O6_11") (pintype "open_collector"))
      (node (ref "TP72") (pin "TP") (pinfunction "PP_TP") (pintype "input"))
    )
    (net (code "75") (name "Net-(7G-KL)") (class "Default")
      (node (ref "7") (pin "4") (pinfunction "KL_4") (pintype "passive"))
      (node (ref "IC21") (pin "10") (pinfunction "O7_10") (pintype "open_collector"))
      (node (ref "TP73") (pin "TP") (pinfunction "PP_TP") (pintype "input"))
    )
    (net (code "76") (name "Net-(7H-KL)") (class "Default")
      (node (ref "7") (pin "5") (pinfunction "KL_5") (pintype "passive"))
      (node (ref "IC21") (pin "12") (pinfunction "O5_12") (pintype "open_collector"))
      (node (ref "TP74") (pin "TP") (pinfunction "PP_TP") (pintype "input"))
    )
    (net (code "77") (name "Net-(7I-KL)") (class "Default")
      (node (ref "7") (pin "6") (pinfunction "KL_6") (pintype "passive"))
      (node (ref "IC21") (pin "13") (pinfunction "O4_13") (pintype "open_collector"))
      (node (ref "TP75") (pin "TP") (pinfunction "PP_TP") (pintype "input"))
    )
    (net (code "78") (name "Net-(7J-KL)") (class "Default")
      (node (ref "7") (pin "7") (pinfunction "KL_7") (pintype "passive"))
      (node (ref "IC21") (pin "14") (pinfunction "O3_14") (pintype "open_collector"))
      (node (ref "TP76") (pin "TP") (pinfunction "PP_TP") (pintype "input"))
    )
    (net (code "79") (name "Net-(7K-KL)") (class "Default")
      (node (ref "7") (pin "8") (pinfunction "KL_8") (pintype "passive"))
      (node (ref "R216") (pin "2") (pinfunction "2_2") (pintype "passive"))
      (node (ref "TP77") (pin "TP") (pinfunction "PP_TP") (pintype "input"))
    )
    (net (code "80") (name "Net-(7L-KL)") (class "Default")
      (node (ref "7") (pin "9") (pinfunction "KL_9") (pintype "passive"))
      (node (ref "D32") (pin "1") (pinfunction "+_1") (pintype "passive"))
      (node (ref "TP78") (pin "TP") (pinfunction "PP_TP") (pintype "input"))
      (node (ref "X7") (pin "17") (pinfunction "17_17") (pintype "passive"))
    )
    (net (code "81") (name "Net-(8B-KL)") (class "Default")
      (node (ref "8") (pin "10") (pinfunction "KL_10") (pintype "passive"))
      (node (ref "TP89") (pin "TP") (pinfunction "PP_TP") (pintype "input"))
      (node (ref "X7") (pin "15") (pinfunction "15_15") (pintype "passive"))
    )
    (net (code "82") (name "Net-(8C-KL)") (class "Default")
      (node (ref "8") (pin "11") (pinfunction "KL_11") (pintype "passive"))
      (node (ref "Q28") (pin "2") (pinfunction "C_2") (pintype "passive"))
      (node (ref "R202") (pin "1") (pinfunction "1_1") (pintype "passive"))
      (node (ref "TP90") (pin "TP") (pinfunction "PP_TP") (pintype "input"))
    )
    (net (code "83") (name "Net-(8D-KL)") (class "Default")
      (node (ref "8") (pin "12") (pinfunction "KL_12") (pintype "passive"))
      (node (ref "R203") (pin "1") (pinfunction "1_1") (pintype "passive"))
      (node (ref "TP92") (pin "TP") (pinfunction "PP_TP") (pintype "input"))
    )
    (net (code "84") (name "Net-(8E-KL)") (class "Default")
      (node (ref "8") (pin "2") (pinfunction "KL_2") (pintype "passive"))
      (node (ref "D37") (pin "2") (pinfunction "-_2") (pintype "passive"))
      (node (ref "LED13") (pin "K") (pinfunction "C_K") (pintype "passive"))
      (node (ref "TP81") (pin "TP") (pinfunction "PP_TP") (pintype "input"))
      (node (ref "X7") (pin "12") (pinfunction "12_12") (pintype "passive"))
    )
    (net (code "85") (name "Net-(8F-KL)") (class "Default")
      (node (ref "8") (pin "3") (pinfunction "KL_3") (pintype "passive"))
      (node (ref "D36") (pin "2") (pinfunction "-_2") (pintype "passive"))
      (node (ref "LED14") (pin "K") (pinfunction "C_K") (pintype "passive"))
      (node (ref "TP82") (pin "TP") (pinfunction "PP_TP") (pintype "input"))
      (node (ref "X7") (pin "11") (pinfunction "11_11") (pintype "passive"))
    )
    (net (code "86") (name "Net-(8G-KL)") (class "Default")
      (node (ref "8") (pin "4") (pinfunction "KL_4") (pintype "passive"))
      (node (ref "D35") (pin "2") (pinfunction "-_2") (pintype "passive"))
      (node (ref "LED15") (pin "K") (pinfunction "C_K") (pintype "passive"))
      (node (ref "TP83") (pin "TP") (pinfunction "PP_TP") (pintype "input"))
      (node (ref "X7") (pin "10") (pinfunction "10_10") (pintype "passive"))
    )
    (net (code "87") (name "Net-(8H-KL)") (class "Default")
      (node (ref "8") (pin "5") (pinfunction "KL_5") (pintype "passive"))
      (node (ref "D34") (pin "2") (pinfunction "-_2") (pintype "passive"))
      (node (ref "LED16") (pin "K") (pinfunction "C_K") (pintype "passive"))
      (node (ref "TP84") (pin "TP") (pinfunction "PP_TP") (pintype "input"))
      (node (ref "X7") (pin "9") (pinfunction "9_9") (pintype "passive"))
    )
    (net (code "88") (name "Net-(8I-KL)") (class "Default")
      (node (ref "8") (pin "6") (pinfunction "KL_6") (pintype "passive"))
      (node (ref "JP12") (pin "2") (pinfunction "2_2") (pintype "passive"))
      (node (ref "TP85") (pin "TP") (pinfunction "PP_TP") (pintype "input"))
    )
    (net (code "89") (name "Net-(8J-KL)") (class "Default")
      (node (ref "8") (pin "7") (pinfunction "KL_7") (pintype "passive"))
      (node (ref "LED17") (pin "A") (pinfunction "A_A") (pintype "passive"))
      (node (ref "TP86") (pin "TP") (pinfunction "PP_TP") (pintype "input"))
      (node (ref "X7") (pin "8") (pinfunction "8_8") (pintype "passive"))
    )
    (net (code "90") (name "Net-(8K-KL)") (class "Default")
      (node (ref "8") (pin "8") (pinfunction "KL_8") (pintype "passive"))
      (node (ref "D38") (pin "2") (pinfunction "-_2") (pintype "passive"))
      (node (ref "LED18") (pin "K") (pinfunction "C_K") (pintype "passive"))
      (node (ref "TP87") (pin "TP") (pinfunction "PP_TP") (pintype "input"))
      (node (ref "X7") (pin "14") (pinfunction "14_14") (pintype "passive"))
    )
    (net (code "91") (name "Net-(8L-KL)") (class "Default")
      (node (ref "8") (pin "9") (pinfunction "KL_9") (pintype "passive"))
      (node (ref "D35") (pin "1") (pinfunction "+_1") (pintype "passive"))
      (node (ref "D36") (pin "1") (pinfunction "+_1") (pintype "passive"))
      (node (ref "JP13") (pin "1") (pinfunction "1_1") (pintype "passive"))
      (node (ref "JP14") (pin "2") (pinfunction "2_2") (pintype "passive"))
      (node (ref "TP88") (pin "TP") (pinfunction "PP_TP") (pintype "input"))
    )
    (net (code "92") (name "Net-(9A-KL)") (class "Default")
      (node (ref "9") (pin "1") (pinfunction "KL_1") (pintype "passive"))
      (node (ref "D58") (pin "2") (pinfunction "-_2") (pintype "passive"))
      (node (ref "TP93") (pin "TP") (pinfunction "PP_TP") (pintype "input"))
    )
    (net (code "93") (name "Net-(9B-KL)") (class "Default")
      (node (ref "9") (pin "10") (pinfunction "KL_10") (pintype "passive"))
      (node (ref "D46") (pin "2") (pinfunction "-_2") (pintype "passive"))
      (node (ref "D47") (pin "2") (pinfunction "-_2") (pintype "passive"))
      (node (ref "JP20") (pin "1") (pinfunction "1_1") (pintype "passive"))
      (node (ref "SJ4") (pin "1") (pinfunction "1_1") (pintype "passive"))
      (node (ref "TP102") (pin "TP") (pinfunction "PP_TP") (pintype "input"))
    )
    (net (code "94") (name "Net-(9C-KL)") (class "Default")
      (node (ref "9") (pin "11") (pinfunction "KL_11") (pintype "passive"))
      (node (ref "D47") (pin "1") (pinfunction "+_1") (pintype "passive"))
      (node (ref "TP103") (pin "TP") (pinfunction "PP_TP") (pintype "input"))
      (node (ref "X10") (pin "19") (pinfunction "19_19") (pintype "passive"))
    )
    (net (code "95") (name "Net-(9E-KL)") (class "Default")
      (node (ref "9") (pin "2") (pinfunction "KL_2") (pintype "passive"))
      (node (ref "Q36") (pin "2") (pinfunction "C_2") (pintype "passive"))
      (node (ref "TP94") (pin "TP") (pinfunction "PP_TP") (pintype "input"))
    )
    (net (code "96") (name "Net-(9F-KL)") (class "Default")
      (node (ref "9") (pin "3") (pinfunction "KL_3") (pintype "passive"))
      (node (ref "IC30") (pin "11") (pinfunction "O6_11") (pintype "open_collector"))
      (node (ref "TP95") (pin "TP") (pinfunction "PP_TP") (pintype "input"))
    )
    (net (code "97") (name "Net-(9G-KL)") (class "Default")
      (node (ref "9") (pin "4") (pinfunction "KL_4") (pintype "passive"))
      (node (ref "IC30") (pin "10") (pinfunction "O7_10") (pintype "open_collector"))
      (node (ref "TP96") (pin "TP") (pinfunction "PP_TP") (pintype "input"))
    )
    (net (code "98") (name "Net-(9H-KL)") (class "Default")
      (node (ref "9") (pin "5") (pinfunction "KL_5") (pintype "passive"))
      (node (ref "IC30") (pin "12") (pinfunction "O5_12") (pintype "open_collector"))
      (node (ref "TP97") (pin "TP") (pinfunction "PP_TP") (pintype "input"))
    )
    (net (code "99") (name "Net-(9I-KL)") (class "Default")
      (node (ref "9") (pin "6") (pinfunction "KL_6") (pintype "passive"))
      (node (ref "IC30") (pin "13") (pinfunction "O4_13") (pintype "open_collector"))
      (node (ref "TP98") (pin "TP") (pinfunction "PP_TP") (pintype "input"))
    )
    (net (code "100") (name "Net-(9J-KL)") (class "Default")
      (node (ref "9") (pin "7") (pinfunction "KL_7") (pintype "passive"))
      (node (ref "IC30") (pin "14") (pinfunction "O3_14") (pintype "open_collector"))
      (node (ref "TP99") (pin "TP") (pinfunction "PP_TP") (pintype "input"))
    )
    (net (code "101") (name "Net-(9K-KL)") (class "Default")
      (node (ref "9") (pin "8") (pinfunction "KL_8") (pintype "passive"))
      (node (ref "R271") (pin "2") (pinfunction "2_2") (pintype "passive"))
      (node (ref "TP100") (pin "TP") (pinfunction "PP_TP") (pintype "input"))
    )
    (net (code "102") (name "Net-(9L-KL)") (class "Default")
      (node (ref "9") (pin "9") (pinfunction "KL_9") (pintype "passive"))
      (node (ref "D46") (pin "1") (pinfunction "+_1") (pintype "passive"))
      (node (ref "TP101") (pin "TP") (pinfunction "PP_TP") (pintype "input"))
      (node (ref "X10") (pin "17") (pinfunction "17_17") (pintype "passive"))
    )
    (net (code "103") (name "Net-(10B-KL)") (class "Default")
      (node (ref "10") (pin "10") (pinfunction "KL_10") (pintype "passive"))
      (node (ref "TP112") (pin "TP") (pinfunction "PP_TP") (pintype "input"))
      (node (ref "X10") (pin "15") (pinfunction "15_15") (pintype "passive"))
    )
    (net (code "104") (name "Net-(10C-KL)") (class "Default")
      (node (ref "10") (pin "11") (pinfunction "KL_11") (pintype "passive"))
      (node (ref "Q38") (pin "2") (pinfunction "C_2") (pintype "passive"))
      (node (ref "R257") (pin "1") (pinfunction "1_1") (pintype "passive"))
      (node (ref "TP113") (pin "TP") (pinfunction "PP_TP") (pintype "input"))
    )
    (net (code "105") (name "Net-(10D-KL)") (class "Default")
      (node (ref "10") (pin "12") (pinfunction "KL_12") (pintype "passive"))
      (node (ref "R258") (pin "1") (pinfunction "1_1") (pintype "passive"))
      (node (ref "TP115") (pin "TP") (pinfunction "PP_TP") (pintype "input"))
    )
    (net (code "106") (name "Net-(10E-KL)") (class "Default")
      (node (ref "10") (pin "2") (pinfunction "KL_2") (pintype "passive"))
      (node (ref "D51") (pin "2") (pinfunction "-_2") (pintype "passive"))
      (node (ref "LED19") (pin "K") (pinfunction "C_K") (pintype "passive"))
      (node (ref "TP104") (pin "TP") (pinfunction "PP_TP") (pintype "input"))
      (node (ref "X10") (pin "12") (pinfunction "12_12") (pintype "passive"))
    )
    (net (code "107") (name "Net-(10F-KL)") (class "Default")
      (node (ref "10") (pin "3") (pinfunction "KL_3") (pintype "passive"))
      (node (ref "D50") (pin "2") (pinfunction "-_2") (pintype "passive"))
      (node (ref "LED20") (pin "K") (pinfunction "C_K") (pintype "passive"))
      (node (ref "TP105") (pin "TP") (pinfunction "PP_TP") (pintype "input"))
      (node (ref "X10") (pin "11") (pinfunction "11_11") (pintype "passive"))
    )
    (net (code "108") (name "Net-(10G-KL)") (class "Default")
      (node (ref "10") (pin "4") (pinfunction "KL_4") (pintype "passive"))
      (node (ref "D49") (pin "2") (pinfunction "-_2") (pintype "passive"))
      (node (ref "LED21") (pin "K") (pinfunction "C_K") (pintype "passive"))
      (node (ref "TP106") (pin "TP") (pinfunction "PP_TP") (pintype "input"))
      (node (ref "X10") (pin "10") (pinfunction "10_10") (pintype "passive"))
    )
    (net (code "109") (name "Net-(10H-KL)") (class "Default")
      (node (ref "10") (pin "5") (pinfunction "KL_5") (pintype "passive"))
      (node (ref "D48") (pin "2") (pinfunction "-_2") (pintype "passive"))
      (node (ref "LED22") (pin "K") (pinfunction "C_K") (pintype "passive"))
      (node (ref "TP107") (pin "TP") (pinfunction "PP_TP") (pintype "input"))
      (node (ref "X10") (pin "9") (pinfunction "9_9") (pintype "passive"))
    )
    (net (code "110") (name "Net-(10I-KL)") (class "Default")
      (node (ref "10") (pin "6") (pinfunction "KL_6") (pintype "passive"))
      (node (ref "JP17") (pin "2") (pinfunction "2_2") (pintype "passive"))
      (node (ref "TP108") (pin "TP") (pinfunction "PP_TP") (pintype "input"))
    )
    (net (code "111") (name "Net-(10J-KL)") (class "Default")
      (node (ref "10") (pin "7") (pinfunction "KL_7") (pintype "passive"))
      (node (ref "LED23") (pin "A") (pinfunction "A_A") (pintype "passive"))
      (node (ref "TP109") (pin "TP") (pinfunction "PP_TP") (pintype "input"))
      (node (ref "X10") (pin "8") (pinfunction "8_8") (pintype "passive"))
    )
    (net (code "112") (name "Net-(10K-KL)") (class "Default")
      (node (ref "10") (pin "8") (pinfunction "KL_8") (pintype "passive"))
      (node (ref "D52") (pin "2") (pinfunction "-_2") (pintype "passive"))
      (node (ref "LED24") (pin "K") (pinfunction "C_K") (pintype "passive"))
      (node (ref "TP110") (pin "TP") (pinfunction "PP_TP") (pintype "input"))
      (node (ref "X10") (pin "14") (pinfunction "14_14") (pintype "passive"))
    )
    (net (code "113") (name "Net-(10L-KL)") (class "Default")
      (node (ref "10") (pin "9") (pinfunction "KL_9") (pintype "passive"))
      (node (ref "D49") (pin "1") (pinfunction "+_1") (pintype "passive"))
      (node (ref "D50") (pin "1") (pinfunction "+_1") (pintype "passive"))
      (node (ref "JP18") (pin "1") (pinfunction "1_1") (pintype "passive"))
      (node (ref "JP19") (pin "2") (pinfunction "2_2") (pintype "passive"))
      (node (ref "TP111") (pin "TP") (pinfunction "PP_TP") (pintype "input"))
    )
    (net (code "114") (name "Net-(11A-KL)") (class "Default")
      (node (ref "11") (pin "1") (pinfunction "KL_1") (pintype "passive"))
      (node (ref "D72") (pin "2") (pinfunction "-_2") (pintype "passive"))
      (node (ref "TP116") (pin "TP") (pinfunction "PP_TP") (pintype "input"))
    )
    (net (code "115") (name "Net-(11B-KL)") (class "Default")
      (node (ref "11") (pin "10") (pinfunction "KL_10") (pintype "passive"))
      (node (ref "D60") (pin "2") (pinfunction "-_2") (pintype "passive"))
      (node (ref "D61") (pin "2") (pinfunction "-_2") (pintype "passive"))
      (node (ref "JP25") (pin "1") (pinfunction "1_1") (pintype "passive"))
      (node (ref "SJ5") (pin "1") (pinfunction "1_1") (pintype "passive"))
      (node (ref "TP125") (pin "TP") (pinfunction "PP_TP") (pintype "input"))
    )
    (net (code "116") (name "Net-(11C-KL)") (class "Default")
      (node (ref "11") (pin "11") (pinfunction "KL_11") (pintype "passive"))
      (node (ref "D61") (pin "1") (pinfunction "+_1") (pintype "passive"))
      (node (ref "TP126") (pin "TP") (pinfunction "PP_TP") (pintype "input"))
      (node (ref "X13") (pin "19") (pinfunction "19_19") (pintype "passive"))
    )
    (net (code "117") (name "Net-(11E-KL)") (class "Default")
      (node (ref "11") (pin "2") (pinfunction "KL_2") (pintype "passive"))
      (node (ref "Q46") (pin "2") (pinfunction "C_2") (pintype "passive"))
      (node (ref "TP117") (pin "TP") (pinfunction "PP_TP") (pintype "input"))
    )
    (net (code "118") (name "Net-(11F-KL)") (class "Default")
      (node (ref "11") (pin "3") (pinfunction "KL_3") (pintype "passive"))
      (node (ref "IC39") (pin "11") (pinfunction "O6_11") (pintype "open_collector"))
      (node (ref "TP118") (pin "TP") (pinfunction "PP_TP") (pintype "input"))
    )
    (net (code "119") (name "Net-(11G-KL)") (class "Default")
      (node (ref "11") (pin "4") (pinfunction "KL_4") (pintype "passive"))
      (node (ref "IC39") (pin "10") (pinfunction "O7_10") (pintype "open_collector"))
      (node (ref "TP119") (pin "TP") (pinfunction "PP_TP") (pintype "input"))
    )
    (net (code "120") (name "Net-(11H-KL)") (class "Default")
      (node (ref "11") (pin "5") (pinfunction "KL_5") (pintype "passive"))
      (node (ref "IC39") (pin "12") (pinfunction "O5_12") (pintype "open_collector"))
      (node (ref "TP120") (pin "TP") (pinfunction "PP_TP") (pintype "input"))
    )
    (net (code "121") (name "Net-(11I-KL)") (class "Default")
      (node (ref "11") (pin "6") (pinfunction "KL_6") (pintype "passive"))
      (node (ref "IC39") (pin "13") (pinfunction "O4_13") (pintype "open_collector"))
      (node (ref "TP121") (pin "TP") (pinfunction "PP_TP") (pintype "input"))
    )
    (net (code "122") (name "Net-(11J-KL)") (class "Default")
      (node (ref "11") (pin "7") (pinfunction "KL_7") (pintype "passive"))
      (node (ref "IC39") (pin "14") (pinfunction "O3_14") (pintype "open_collector"))
      (node (ref "TP122") (pin "TP") (pinfunction "PP_TP") (pintype "input"))
    )
    (net (code "123") (name "Net-(11K-KL)") (class "Default")
      (node (ref "11") (pin "8") (pinfunction "KL_8") (pintype "passive"))
      (node (ref "R326") (pin "2") (pinfunction "2_2") (pintype "passive"))
      (node (ref "TP123") (pin "TP") (pinfunction "PP_TP") (pintype "input"))
    )
    (net (code "124") (name "Net-(11L-KL)") (class "Default")
      (node (ref "11") (pin "9") (pinfunction "KL_9") (pintype "passive"))
      (node (ref "D60") (pin "1") (pinfunction "+_1") (pintype "passive"))
      (node (ref "TP124") (pin "TP") (pinfunction "PP_TP") (pintype "input"))
      (node (ref "X13") (pin "17") (pinfunction "17_17") (pintype "passive"))
    )
    (net (code "125") (name "Net-(12B-KL)") (class "Default")
      (node (ref "12") (pin "10") (pinfunction "KL_10") (pintype "passive"))
      (node (ref "TP135") (pin "TP") (pinfunction "PP_TP") (pintype "input"))
      (node (ref "X13") (pin "15") (pinfunction "15_15") (pintype "passive"))
    )
    (net (code "126") (name "Net-(12C-KL)") (class "Default")
      (node (ref "12") (pin "11") (pinfunction "KL_11") (pintype "passive"))
      (node (ref "Q48") (pin "2") (pinfunction "C_2") (pintype "passive"))
      (node (ref "R312") (pin "1") (pinfunction "1_1") (pintype "passive"))
      (node (ref "TP136") (pin "TP") (pinfunction "PP_TP") (pintype "input"))
    )
    (net (code "127") (name "Net-(12D-KL)") (class "Default")
      (node (ref "12") (pin "12") (pinfunction "KL_12") (pintype "passive"))
      (node (ref "R313") (pin "1") (pinfunction "1_1") (pintype "passive"))
      (node (ref "TP138") (pin "TP") (pinfunction "PP_TP") (pintype "input"))
    )
    (net (code "128") (name "Net-(12E-KL)") (class "Default")
      (node (ref "12") (pin "2") (pinfunction "KL_2") (pintype "passive"))
      (node (ref "D65") (pin "2") (pinfunction "-_2") (pintype "passive"))
      (node (ref "LED25") (pin "K") (pinfunction "C_K") (pintype "passive"))
      (node (ref "TP127") (pin "TP") (pinfunction "PP_TP") (pintype "input"))
      (node (ref "X13") (pin "12") (pinfunction "12_12") (pintype "passive"))
    )
    (net (code "129") (name "Net-(12F-KL)") (class "Default")
      (node (ref "12") (pin "3") (pinfunction "KL_3") (pintype "passive"))
      (node (ref "D64") (pin "2") (pinfunction "-_2") (pintype "passive"))
      (node (ref "LED26") (pin "K") (pinfunction "C_K") (pintype "passive"))
      (node (ref "TP128") (pin "TP") (pinfunction "PP_TP") (pintype "input"))
      (node (ref "X13") (pin "11") (pinfunction "11_11") (pintype "passive"))
    )
    (net (code "130") (name "Net-(12G-KL)") (class "Default")
      (node (ref "12") (pin "4") (pinfunction "KL_4") (pintype "passive"))
      (node (ref "D63") (pin "2") (pinfunction "-_2") (pintype "passive"))
      (node (ref "LED27") (pin "K") (pinfunction "C_K") (pintype "passive"))
      (node (ref "TP129") (pin "TP") (pinfunction "PP_TP") (pintype "input"))
      (node (ref "X13") (pin "10") (pinfunction "10_10") (pintype "passive"))
    )
    (net (code "131") (name "Net-(12H-KL)") (class "Default")
      (node (ref "12") (pin "5") (pinfunction "KL_5") (pintype "passive"))
      (node (ref "D62") (pin "2") (pinfunction "-_2") (pintype "passive"))
      (node (ref "LED28") (pin "K") (pinfunction "C_K") (pintype "passive"))
      (node (ref "TP130") (pin "TP") (pinfunction "PP_TP") (pintype "input"))
      (node (ref "X13") (pin "9") (pinfunction "9_9") (pintype "passive"))
    )
    (net (code "132") (name "Net-(12I-KL)") (class "Default")
      (node (ref "12") (pin "6") (pinfunction "KL_6") (pintype "passive"))
      (node (ref "JP22") (pin "2") (pinfunction "2_2") (pintype "passive"))
      (node (ref "TP131") (pin "TP") (pinfunction "PP_TP") (pintype "input"))
    )
    (net (code "133") (name "Net-(12J-KL)") (class "Default")
      (node (ref "12") (pin "7") (pinfunction "KL_7") (pintype "passive"))
      (node (ref "LED29") (pin "A") (pinfunction "A_A") (pintype "passive"))
      (node (ref "TP132") (pin "TP") (pinfunction "PP_TP") (pintype "input"))
      (node (ref "X13") (pin "8") (pinfunction "8_8") (pintype "passive"))
    )
    (net (code "134") (name "Net-(12K-KL)") (class "Default")
      (node (ref "12") (pin "8") (pinfunction "KL_8") (pintype "passive"))
      (node (ref "D66") (pin "2") (pinfunction "-_2") (pintype "passive"))
      (node (ref "LED30") (pin "K") (pinfunction "C_K") (pintype "passive"))
      (node (ref "TP133") (pin "TP") (pinfunction "PP_TP") (pintype "input"))
      (node (ref "X13") (pin "14") (pinfunction "14_14") (pintype "passive"))
    )
    (net (code "135") (name "Net-(12L-KL)") (class "Default")
      (node (ref "12") (pin "9") (pinfunction "KL_9") (pintype "passive"))
      (node (ref "D63") (pin "1") (pinfunction "+_1") (pintype "passive"))
      (node (ref "D64") (pin "1") (pinfunction "+_1") (pintype "passive"))
      (node (ref "JP23") (pin "1") (pinfunction "1_1") (pintype "passive"))
      (node (ref "JP24") (pin "2") (pinfunction "2_2") (pintype "passive"))
      (node (ref "TP134") (pin "TP") (pinfunction "PP_TP") (pintype "input"))
    )
    (net (code "136") (name "Net-(C1-Pad1)") (class "Default")
      (node (ref "C1") (pin "1") (pinfunction "1_1") (pintype "passive"))
      (node (ref "R22") (pin "1") (pinfunction "1_1") (pintype "passive"))
      (node (ref "R23") (pin "2") (pinfunction "2_2") (pintype "passive"))
    )
    (net (code "137") (name "Net-(C11-Pad1)") (class "Default")
      (node (ref "C11") (pin "1") (pinfunction "1_1") (pintype "passive"))
      (node (ref "R50") (pin "1") (pinfunction "1_1") (pintype "passive"))
      (node (ref "R51") (pin "1") (pinfunction "1_1") (pintype "passive"))
    )
    (net (code "138") (name "Net-(C14-Pad1)") (class "Default")
      (node (ref "C14") (pin "1") (pinfunction "1_1") (pintype "passive"))
      (node (ref "R77") (pin "1") (pinfunction "1_1") (pintype "passive"))
      (node (ref "R78") (pin "2") (pinfunction "2_2") (pintype "passive"))
    )
    (net (code "139") (name "Net-(C24-Pad1)") (class "Default")
      (node (ref "C24") (pin "1") (pinfunction "1_1") (pintype "passive"))
      (node (ref "R149") (pin "1") (pinfunction "1_1") (pintype "passive"))
      (node (ref "R150") (pin "1") (pinfunction "1_1") (pintype "passive"))
    )
    (net (code "140") (name "Net-(C27-Pad1)") (class "Default")
      (node (ref "C27") (pin "1") (pinfunction "1_1") (pintype "passive"))
      (node (ref "R176") (pin "1") (pinfunction "1_1") (pintype "passive"))
      (node (ref "R177") (pin "2") (pinfunction "2_2") (pintype "passive"))
    )
    (net (code "141") (name "Net-(C36-Pad1)") (class "Default")
      (node (ref "C36") (pin "1") (pinfunction "1_1") (pintype "passive"))
      (node (ref "R204") (pin "1") (pinfunction "1_1") (pintype "passive"))
      (node (ref "R205") (pin "1") (pinfunction "1_1") (pintype "passive"))
    )
    (net (code "142") (name "Net-(C39-Pad1)") (class "Default")
      (node (ref "C39") (pin "1") (pinfunction "1_1") (pintype "passive"))
      (node (ref "R231") (pin "1") (pinfunction "1_1") (pintype "passive"))
      (node (ref "R232") (pin "2") (pinfunction "2_2") (pintype "passive"))
    )
    (net (code "143") (name "Net-(C48-Pad1)") (class "Default")
      (node (ref "C48") (pin "1") (pinfunction "1_1") (pintype "passive"))
      (node (ref "R259") (pin "1") (pinfunction "1_1") (pintype "passive"))
      (node (ref "R260") (pin "1") (pinfunction "1_1") (pintype "passive"))
    )
    (net (code "144") (name "Net-(C51-Pad1)") (class "Default")
      (node (ref "C51") (pin "1") (pinfunction "1_1") (pintype "passive"))
      (node (ref "R286") (pin "1") (pinfunction "1_1") (pintype "passive"))
      (node (ref "R287") (pin "2") (pinfunction "2_2") (pintype "passive"))
    )
    (net (code "145") (name "Net-(C60-Pad1)") (class "Default")
      (node (ref "C60") (pin "1") (pinfunction "1_1") (pintype "passive"))
      (node (ref "R314") (pin "1") (pinfunction "1_1") (pintype "passive"))
      (node (ref "R315") (pin "1") (pinfunction "1_1") (pintype "passive"))
    )
    (net (code "146") (name "Net-(C103-Pad1)") (class "Default")
      (node (ref "C103") (pin "1") (pinfunction "1_1") (pintype "passive"))
      (node (ref "R108") (pin "1") (pinfunction "1_1") (pintype "passive"))
      (node (ref "R112") (pin "1") (pinfunction "1_1") (pintype "passive"))
    )
    (net (code "147") (name "Net-(C107-Pad1)") (class "Default")
      (node (ref "C107") (pin "1") (pinfunction "1_1") (pintype "passive"))
      (node (ref "R125") (pin "1") (pinfunction "1_1") (pintype "passive"))
      (node (ref "R130") (pin "2") (pinfunction "2_2") (pintype "passive"))
    )
    (net (code "148") (name "Net-(D1--)") (class "Default")
      (node (ref "D1") (pin "2") (pinfunction "-_2") (pintype "passive"))
      (node (ref "R12") (pin "1") (pinfunction "1_1") (pintype "passive"))
      (node (ref "R13") (pin "1") (pinfunction "1_1") (pintype "passive"))
    )
    (net (code "149") (name "Net-(D2-+)") (class "Default")
      (node (ref "D2") (pin "1") (pinfunction "+_1") (pintype "passive"))
      (node (ref "X101") (pin "1") (pinfunction "1_1") (pintype "passive"))
    )
    (net (code "150") (name "Net-(D6-+)") (class "Default")
      (node (ref "D6") (pin "1") (pinfunction "+_1") (pintype "passive"))
      (node (ref "R7") (pin "1") (pinfunction "1_1") (pintype "passive"))
    )
    (net (code "151") (name "Net-(D9-+)") (class "Default")
      (node (ref "D9") (pin "1") (pinfunction "+_1") (pintype "passive"))
      (node (ref "JP3") (pin "2") (pinfunction "2_2") (pintype "passive"))
    )
    (net (code "152") (name "Net-(D10-+)") (class "Default")
      (node (ref "D10") (pin "1") (pinfunction "+_1") (pintype "passive"))
      (node (ref "JP4") (pin "1") (pinfunction "1_1") (pintype "passive"))
    )
    (net (code "153") (name "Net-(D11--)") (class "Default")
      (node (ref "D11") (pin "2") (pinfunction "-_2") (pintype "passive"))
      (node (ref "Q4") (pin "2") (pinfunction "C_2") (pintype "passive"))
      (node (ref "START1") (pin "TP") (pinfunction "PP_TP") (pintype "input"))
      (node (ref "X1") (pin "5") (pinfunction "5_5") (pintype "passive"))
    )
    (net (code "154") (name "Net-(D12-+)") (class "Default")
      (node (ref "D12") (pin "1") (pinfunction "+_1") (pintype "passive"))
      (node (ref "R44") (pin "1") (pinfunction "1_1") (pintype "passive"))
    )
    (net (code "155") (name "Net-(D12--)") (class "Default")
      (node (ref "C8") (pin "2") (pinfunction "2_2") (pintype "passive"))
      (node (ref "D12") (pin "2") (pinfunction "-_2") (pintype "passive"))
      (node (ref "D17") (pin "C") (pinfunction "C_C") (pintype "passive"))
      (node (ref "IC6") (pin "2") (pinfunction "TR_2") (pintype "input"))
      (node (ref "IC6") (pin "6") (pinfunction "THR_6") (pintype "input"))
      (node (ref "R42") (pin "1") (pinfunction "1_1") (pintype "passive"))
    )
    (net (code "156") (name "Net-(D14-PadC)") (class "Default")
      (node (ref "D14") (pin "C") (pinfunction "C_C") (pintype "passive"))
      (node (ref "R18") (pin "2") (pinfunction "2_2") (pintype "passive"))
      (node (ref "X1") (pin "22") (pinfunction "22_22") (pintype "passive"))
    )
    (net (code "157") (name "Net-(D15--)") (class "Default")
      (node (ref "D15") (pin "2") (pinfunction "-_2") (pintype "passive"))
      (node (ref "R65") (pin "1") (pinfunction "1_1") (pintype "passive"))
      (node (ref "R66") (pin "1") (pinfunction "1_1") (pintype "passive"))
    )
    (net (code "158") (name "Net-(D16-+)") (class "Default")
      (node (ref "D16") (pin "1") (pinfunction "+_1") (pintype "passive"))
      (node (ref "X1") (pin "1") (pinfunction "1_1") (pintype "passive"))
    )
    (net (code "159") (name "Net-(D20-+)") (class "Default")
      (node (ref "D20") (pin "1") (pinfunction "+_1") (pintype "passive"))
      (node (ref "R67") (pin "1") (pinfunction "1_1") (pintype "passive"))
    )
    (net (code "160") (name "Net-(D23-+)") (class "Default")
      (node (ref "D23") (pin "1") (pinfunction "+_1") (pintype "passive"))
      (node (ref "JP8") (pin "2") (pinfunction "2_2") (pintype "passive"))
    )
    (net (code "161") (name "Net-(D24-+)") (class "Default")
      (node (ref "D24") (pin "1") (pinfunction "+_1") (pintype "passive"))
      (node (ref "JP9") (pin "1") (pinfunction "1_1") (pintype "passive"))
    )
    (net (code "162") (name "Net-(D25--)") (class "Default")
      (node (ref "D25") (pin "2") (pinfunction "-_2") (pintype "passive"))
      (node (ref "Q14") (pin "2") (pinfunction "C_2") (pintype "passive"))
      (node (ref "START2") (pin "TP") (pinfunction "PP_TP") (pintype "input"))
      (node (ref "X4") (pin "5") (pinfunction "5_5") (pintype "passive"))
    )
    (net (code "163") (name "Net-(D26-+)") (class "Default")
      (node (ref "D26") (pin "1") (pinfunction "+_1") (pintype "passive"))
      (node (ref "R99") (pin "1") (pinfunction "1_1") (pintype "passive"))
    )
    (net (code "164") (name "Net-(D26--)") (class "Default")
      (node (ref "C21") (pin "2") (pinfunction "2_2") (pintype "passive"))
      (node (ref "D26") (pin "2") (pinfunction "-_2") (pintype "passive"))
      (node (ref "D31") (pin "C") (pinfunction "C_C") (pintype "passive"))
      (node (ref "IC15") (pin "2") (pinfunction "TR_2") (pintype "input"))
      (node (ref "IC15") (pin "6") (pinfunction "THR_6") (pintype "input"))
      (node (ref "R97") (pin "1") (pinfunction "1_1") (pintype "passive"))
    )
    (net (code "165") (name "Net-(D28-PadC)") (class "Default")
      (node (ref "D28") (pin "C") (pinfunction "C_C") (pintype "passive"))
      (node (ref "R73") (pin "2") (pinfunction "2_2") (pintype "passive"))
      (node (ref "X4") (pin "22") (pinfunction "22_22") (pintype "passive"))
    )
    (net (code "166") (name "Net-(D29--)") (class "Default")
      (node (ref "D29") (pin "2") (pinfunction "-_2") (pintype "passive"))
      (node (ref "R164") (pin "1") (pinfunction "1_1") (pintype "passive"))
      (node (ref "R165") (pin "1") (pinfunction "1_1") (pintype "passive"))
    )
    (net (code "167") (name "Net-(D30-+)") (class "Default")
      (node (ref "D30") (pin "1") (pinfunction "+_1") (pintype "passive"))
      (node (ref "X4") (pin "1") (pinfunction "1_1") (pintype "passive"))
    )
    (net (code "168") (name "Net-(D34-+)") (class "Default")
      (node (ref "D34") (pin "1") (pinfunction "+_1") (pintype "passive"))
      (node (ref "R166") (pin "1") (pinfunction "1_1") (pintype "passive"))
    )
    (net (code "169") (name "Net-(D37-+)") (class "Default")
      (node (ref "D37") (pin "1") (pinfunction "+_1") (pintype "passive"))
      (node (ref "JP13") (pin "2") (pinfunction "2_2") (pintype "passive"))
    )
    (net (code "170") (name "Net-(D38-+)") (class "Default")
      (node (ref "D38") (pin "1") (pinfunction "+_1") (pintype "passive"))
      (node (ref "JP14") (pin "1") (pinfunction "1_1") (pintype "passive"))
    )
    (net (code "171") (name "Net-(D39--)") (class "Default")
      (node (ref "D39") (pin "2") (pinfunction "-_2") (pintype "passive"))
      (node (ref "Q24") (pin "2") (pinfunction "C_2") (pintype "passive"))
      (node (ref "START3") (pin "TP") (pinfunction "PP_TP") (pintype "input"))
      (node (ref "X7") (pin "5") (pinfunction "5_5") (pintype "passive"))
    )
    (net (code "172") (name "Net-(D40-+)") (class "Default")
      (node (ref "D40") (pin "1") (pinfunction "+_1") (pintype "passive"))
      (node (ref "R198") (pin "1") (pinfunction "1_1") (pintype "passive"))
    )
    (net (code "173") (name "Net-(D40--)") (class "Default")
      (node (ref "C33") (pin "2") (pinfunction "2_2") (pintype "passive"))
      (node (ref "D40") (pin "2") (pinfunction "-_2") (pintype "passive"))
      (node (ref "D45") (pin "C") (pinfunction "C_C") (pintype "passive"))
      (node (ref "IC24") (pin "2") (pinfunction "TR_2") (pintype "input"))
      (node (ref "IC24") (pin "6") (pinfunction "THR_6") (pintype "input"))
      (node (ref "R196") (pin "1") (pinfunction "1_1") (pintype "passive"))
    )
    (net (code "174") (name "Net-(D42-PadC)") (class "Default")
      (node (ref "D42") (pin "C") (pinfunction "C_C") (pintype "passive"))
      (node (ref "R172") (pin "2") (pinfunction "2_2") (pintype "passive"))
      (node (ref "X7") (pin "22") (pinfunction "22_22") (pintype "passive"))
    )
    (net (code "175") (name "Net-(D43--)") (class "Default")
      (node (ref "D43") (pin "2") (pinfunction "-_2") (pintype "passive"))
      (node (ref "R219") (pin "1") (pinfunction "1_1") (pintype "passive"))
      (node (ref "R220") (pin "1") (pinfunction "1_1") (pintype "passive"))
    )
    (net (code "176") (name "Net-(D44-+)") (class "Default")
      (node (ref "D44") (pin "1") (pinfunction "+_1") (pintype "passive"))
      (node (ref "X7") (pin "1") (pinfunction "1_1") (pintype "passive"))
    )
    (net (code "177") (name "Net-(D48-+)") (class "Default")
      (node (ref "D48") (pin "1") (pinfunction "+_1") (pintype "passive"))
      (node (ref "R221") (pin "1") (pinfunction "1_1") (pintype "passive"))
    )
    (net (code "178") (name "Net-(D51-+)") (class "Default")
      (node (ref "D51") (pin "1") (pinfunction "+_1") (pintype "passive"))
      (node (ref "JP18") (pin "2") (pinfunction "2_2") (pintype "passive"))
    )
    (net (code "179") (name "Net-(D52-+)") (class "Default")
      (node (ref "D52") (pin "1") (pinfunction "+_1") (pintype "passive"))
      (node (ref "JP19") (pin "1") (pinfunction "1_1") (pintype "passive"))
    )
    (net (code "180") (name "Net-(D53--)") (class "Default")
      (node (ref "D53") (pin "2") (pinfunction "-_2") (pintype "passive"))
      (node (ref "Q34") (pin "2") (pinfunction "C_2") (pintype "passive"))
      (node (ref "START4") (pin "TP") (pinfunction "PP_TP") (pintype "input"))
      (node (ref "X10") (pin "5") (pinfunction "5_5") (pintype "passive"))
    )
    (net (code "181") (name "Net-(D54-+)") (class "Default")
      (node (ref "D54") (pin "1") (pinfunction "+_1") (pintype "passive"))
      (node (ref "R253") (pin "1") (pinfunction "1_1") (pintype "passive"))
    )
    (net (code "182") (name "Net-(D54--)") (class "Default")
      (node (ref "C45") (pin "2") (pinfunction "2_2") (pintype "passive"))
      (node (ref "D54") (pin "2") (pinfunction "-_2") (pintype "passive"))
      (node (ref "D59") (pin "C") (pinfunction "C_C") (pintype "passive"))
      (node (ref "IC33") (pin "2") (pinfunction "TR_2") (pintype "input"))
      (node (ref "IC33") (pin "6") (pinfunction "THR_6") (pintype "input"))
      (node (ref "R251") (pin "1") (pinfunction "1_1") (pintype "passive"))
    )
    (net (code "183") (name "Net-(D56-PadC)") (class "Default")
      (node (ref "D56") (pin "C") (pinfunction "C_C") (pintype "passive"))
      (node (ref "R227") (pin "2") (pinfunction "2_2") (pintype "passive"))
      (node (ref "X10") (pin "22") (pinfunction "22_22") (pintype "passive"))
    )
    (net (code "184") (name "Net-(D57--)") (class "Default")
      (node (ref "D57") (pin "2") (pinfunction "-_2") (pintype "passive"))
      (node (ref "R274") (pin "1") (pinfunction "1_1") (pintype "passive"))
      (node (ref "R275") (pin "1") (pinfunction "1_1") (pintype "passive"))
    )
    (net (code "185") (name "Net-(D58-+)") (class "Default")
      (node (ref "D58") (pin "1") (pinfunction "+_1") (pintype "passive"))
      (node (ref "X10") (pin "1") (pinfunction "1_1") (pintype "passive"))
    )
    (net (code "186") (name "Net-(D62-+)") (class "Default")
      (node (ref "D62") (pin "1") (pinfunction "+_1") (pintype "passive"))
      (node (ref "R276") (pin "1") (pinfunction "1_1") (pintype "passive"))
    )
    (net (code "187") (name "Net-(D65-+)") (class "Default")
      (node (ref "D65") (pin "1") (pinfunction "+_1") (pintype "passive"))
      (node (ref "JP23") (pin "2") (pinfunction "2_2") (pintype "passive"))
    )
    (net (code "188") (name "Net-(D66-+)") (class "Default")
      (node (ref "D66") (pin "1") (pinfunction "+_1") (pintype "passive"))
      (node (ref "JP24") (pin "1") (pinfunction "1_1") (pintype "passive"))
    )
    (net (code "189") (name "Net-(D67--)") (class "Default")
      (node (ref "D67") (pin "2") (pinfunction "-_2") (pintype "passive"))
      (node (ref "Q44") (pin "2") (pinfunction "C_2") (pintype "passive"))
      (node (ref "START5") (pin "TP") (pinfunction "PP_TP") (pintype "input"))
      (node (ref "X13") (pin "5") (pinfunction "5_5") (pintype "passive"))
    )
    (net (code "190") (name "Net-(D68-+)") (class "Default")
      (node (ref "D68") (pin "1") (pinfunction "+_1") (pintype "passive"))
      (node (ref "R308") (pin "1") (pinfunction "1_1") (pintype "passive"))
    )
    (net (code "191") (name "Net-(D68--)") (class "Default")
      (node (ref "C57") (pin "2") (pinfunction "2_2") (pintype "passive"))
      (node (ref "D68") (pin "2") (pinfunction "-_2") (pintype "passive"))
      (node (ref "D73") (pin "C") (pinfunction "C_C") (pintype "passive"))
      (node (ref "IC42") (pin "2") (pinfunction "TR_2") (pintype "input"))
      (node (ref "IC42") (pin "6") (pinfunction "THR_6") (pintype "input"))
      (node (ref "R306") (pin "1") (pinfunction "1_1") (pintype "passive"))
    )
    (net (code "192") (name "Net-(D70-PadC)") (class "Default")
      (node (ref "D70") (pin "C") (pinfunction "C_C") (pintype "passive"))
      (node (ref "R282") (pin "2") (pinfunction "2_2") (pintype "passive"))
      (node (ref "X13") (pin "22") (pinfunction "22_22") (pintype "passive"))
    )
    (net (code "193") (name "Net-(D71--)") (class "Default")
      (node (ref "D71") (pin "2") (pinfunction "-_2") (pintype "passive"))
      (node (ref "R329") (pin "1") (pinfunction "1_1") (pintype "passive"))
      (node (ref "R330") (pin "1") (pinfunction "1_1") (pintype "passive"))
    )
    (net (code "194") (name "Net-(D72-+)") (class "Default")
      (node (ref "D72") (pin "1") (pinfunction "+_1") (pintype "passive"))
      (node (ref "X13") (pin "1") (pinfunction "1_1") (pintype "passive"))
    )
    (net (code "195") (name "Net-(D104-PadC)") (class "Default")
      (node (ref "D104") (pin "C") (pinfunction "C_C") (pintype "passive"))
      (node (ref "R105") (pin "2") (pinfunction "2_2") (pintype "passive"))
      (node (ref "X101") (pin "22") (pinfunction "22_22") (pintype "passive"))
    )
    (net (code "196") (name "Net-(D105--)") (class "Default")
      (node (ref "D105") (pin "2") (pinfunction "-_2") (pintype "passive"))
      (node (ref "Q104") (pin "2") (pinfunction "C_2") (pintype "passive"))
      (node (ref "START") (pin "TP") (pinfunction "PP_TP") (pintype "input"))
      (node (ref "X101") (pin "5") (pinfunction "5_5") (pintype "passive"))
    )
    (net (code "197") (name "Net-(D106-+)") (class "Default")
      (node (ref "D106") (pin "1") (pinfunction "+_1") (pintype "passive"))
      (node (ref "R127") (pin "1") (pinfunction "1_1") (pintype "passive"))
    )
    (net (code "198") (name "Net-(D109-+)") (class "Default")
      (node (ref "D109") (pin "1") (pinfunction "+_1") (pintype "passive"))
      (node (ref "JP102") (pin "2") (pinfunction "2_2") (pintype "passive"))
    )
    (net (code "199") (name "Net-(D110-+)") (class "Default")
      (node (ref "D110") (pin "1") (pinfunction "+_1") (pintype "passive"))
      (node (ref "JP103") (pin "1") (pinfunction "1_1") (pintype "passive"))
    )
    (net (code "200") (name "Net-(D112-+)") (class "Default")
      (node (ref "D112") (pin "1") (pinfunction "+_1") (pintype "passive"))
      (node (ref "R140") (pin "1") (pinfunction "1_1") (pintype "passive"))
    )
    (net (code "201") (name "Net-(D112--)") (class "Default")
      (node (ref "C109") (pin "2") (pinfunction "2_2") (pintype "passive"))
      (node (ref "D112") (pin "2") (pinfunction "-_2") (pintype "passive"))
      (node (ref "D4") (pin "C") (pinfunction "C_C") (pintype "passive"))
      (node (ref "IC110") (pin "2") (pinfunction "TR_2") (pintype "input"))
      (node (ref "IC110") (pin "6") (pinfunction "THR_6") (pintype "input"))
      (node (ref "R141") (pin "1") (pinfunction "1_1") (pintype "passive"))
    )
    (net (code "202") (name "Net-(IC1A-A)") (class "Default")
      (node (ref "IC1") (pin "10") (pinfunction "A_10") (pintype "input"))
      (node (ref "R17") (pin "1") (pinfunction "1_1") (pintype "passive"))
      (node (ref "R58") (pin "1") (pinfunction "1_1") (pintype "passive"))
      (node (ref "R58") (pin "2") (pinfunction "2_2") (pintype "passive"))
      (node (ref "X1") (pin "4") (pinfunction "4_4") (pintype "passive"))
      (node (ref "X2") (pin "2") (pinfunction "S_2") (pintype "passive"))
    )
    (net (code "203") (name "Net-(IC1A-B)") (class "Default")
      (node (ref "IC1") (pin "13") (pinfunction "B_13") (pintype "input"))
      (node (ref "R16") (pin "1") (pinfunction "1_1") (pintype "passive"))
      (node (ref "R57") (pin "1") (pinfunction "1_1") (pintype "passive"))
      (node (ref "R57") (pin "2") (pinfunction "2_2") (pintype "passive"))
      (node (ref "X1") (pin "3") (pinfunction "3_3") (pintype "passive"))
      (node (ref "X2") (pin "3") (pinfunction "S_3") (pintype "passive"))
    )
    (net (code "204") (name "Net-(IC1A-C)") (class "Default")
      (node (ref "IC1") (pin "12") (pinfunction "C_12") (pintype "input"))
      (node (ref "R15") (pin "1") (pinfunction "1_1") (pintype "passive"))
      (node (ref "R56") (pin "1") (pinfunction "1_1") (pintype "passive"))
      (node (ref "R56") (pin "2") (pinfunction "2_2") (pintype "passive"))
      (node (ref "X1") (pin "2") (pinfunction "2_2") (pintype "passive"))
      (node (ref "X2") (pin "4") (pinfunction "S_4") (pintype "passive"))
    )
    (net (code "205") (name "Net-(IC1A-Q0)") (class "Default")
      (node (ref "IC1") (pin "3") (pinfunction "Q0_3") (pintype "output"))
      (node (ref "IC3") (pin "1") (pinfunction "I1_1") (pintype "input"))
      (node (ref "IC3") (pin "2") (pinfunction "I2_2") (pintype "input"))
      (node (ref "Q10") (pin "1") (pinfunction "G_1") (pintype "passive"))
      (node (ref "Q11") (pin "1") (pinfunction "G_1") (pintype "passive"))
    )
    (net (code "206") (name "Net-(IC1A-Q1)") (class "Default")
      (node (ref "IC1") (pin "14") (pinfunction "Q1_14") (pintype "output"))
      (node (ref "IC3") (pin "6") (pinfunction "I6_6") (pintype "input"))
    )
    (net (code "207") (name "Net-(IC1A-Q2)") (class "Default")
      (node (ref "IC1") (pin "2") (pinfunction "Q2_2") (pintype "output"))
      (node (ref "IC3") (pin "7") (pinfunction "I7_7") (pintype "input"))
    )
    (net (code "208") (name "Net-(IC1A-Q3)") (class "Default")
      (node (ref "IC1") (pin "15") (pinfunction "Q3_15") (pintype "output"))
      (node (ref "IC3") (pin "5") (pinfunction "I5_5") (pintype "input"))
    )
    (net (code "209") (name "Net-(IC1A-Q4)") (class "Default")
      (node (ref "IC1") (pin "1") (pinfunction "Q4_1") (pintype "output"))
      (node (ref "IC3") (pin "4") (pinfunction "I4_4") (pintype "input"))
    )
    (net (code "210") (name "Net-(IC1A-Q5)") (class "Default")
      (node (ref "IC1") (pin "6") (pinfunction "Q5_6") (pintype "output"))
      (node (ref "IC3") (pin "3") (pinfunction "I3_3") (pintype "input"))
    )
    (net (code "211") (name "Net-(IC2-ADJ)") (class "Default")
      (node (ref "IC2") (pin "1") (pinfunction "ADJ_1") (pintype "input"))
      (node (ref "R11") (pin "1") (pinfunction "1_1") (pintype "passive"))
      (node (ref "R20") (pin "2") (pinfunction "2_2") (pintype "passive"))
      (node (ref "X1") (pin "7") (pinfunction "7_7") (pintype "passive"))
    )
    (net (code "212") (name "Net-(IC2-VI)") (class "Default")
      (node (ref "IC2") (pin "3") (pinfunction "VI_3") (pintype "input"))
      (node (ref "Q7") (pin "2") (pinfunction "C_2") (pintype "passive"))
    )
    (net (code "213") (name "Net-(IC2-VO)") (class "Default")
      (node (ref "IC2") (pin "2") (pinfunction "VO_2") (pintype "passive"))
      (node (ref "R11") (pin "2") (pinfunction "2_2") (pintype "passive"))
    )
    (net (code "214") (name "Net-(IC3-O1)") (class "Default")
      (node (ref "IC3") (pin "16") (pinfunction "O1_16") (pintype "open_collector"))
      (node (ref "Q10") (pin "3") (pinfunction "D_3") (pintype "passive"))
      (node (ref "R62") (pin "1") (pinfunction "1_1") (pintype "passive"))
    )
    (net (code "215") (name "Net-(IC3-O2)") (class "Default")
      (node (ref "IC3") (pin "15") (pinfunction "O2_15") (pintype "open_collector"))
      (node (ref "R35") (pin "1") (pinfunction "1_1") (pintype "passive"))
    )
    (net (code "216") (name "Net-(IC4A-+IN)") (class "Default")
      (node (ref "IC4") (pin "11") (pinfunction "+IN_11") (pintype "input"))
      (node (ref "IC4") (pin "5") (pinfunction "+IN_5") (pintype "input"))
      (node (ref "R24") (pin "1") (pinfunction "1_1") (pintype "passive"))
      (node (ref "R25") (pin "2") (pinfunction "2_2") (pintype "passive"))
      (node (ref "R26") (pin "2") (pinfunction "2_2") (pintype "passive"))
    )
    (net (code "217") (name "Net-(IC4A--IN)") (class "Default")
      (node (ref "C3") (pin "1") (pinfunction "1_1") (pintype "passive"))
      (node (ref "IC4") (pin "10") (pinfunction "-IN_10") (pintype "input"))
      (node (ref "IC4") (pin "4") (pinfunction "-IN_4") (pintype "input"))
      (node (ref "R23") (pin "1") (pinfunction "1_1") (pintype "passive"))
    )
    (net (code "218") (name "Net-(IC4A-OUT)") (class "Default")
      (node (ref "IC4") (pin "2") (pinfunction "OUT_2") (pintype "open_collector"))
      (node (ref "R26") (pin "1") (pinfunction "1_1") (pintype "passive"))
    )
    (net (code "219") (name "Net-(IC4B-+IN)") (class "Default")
      (node (ref "IC4") (pin "7") (pinfunction "+IN_7") (pintype "input"))
      (node (ref "R21") (pin "1") (pinfunction "1_1") (pintype "passive"))
      (node (ref "R38") (pin "1") (pinfunction "1_1") (pintype "passive"))
    )
    (net (code "220") (name "Net-(IC4B--IN)") (class "Default")
      (node (ref "IC4") (pin "6") (pinfunction "-IN_6") (pintype "input"))
      (node (ref "IC4") (pin "8") (pinfunction "-IN_8") (pintype "input"))
      (node (ref "R20") (pin "1") (pinfunction "1_1") (pintype "passive"))
    )
    (net (code "221") (name "Net-(IC4B-OUT)") (class "Default")
      (node (ref "IC4") (pin "1") (pinfunction "OUT_1") (pintype "open_collector"))
      (node (ref "R22") (pin "2") (pinfunction "2_2") (pintype "passive"))
      (node (ref "R27") (pin "2") (pinfunction "2_2") (pintype "passive"))
    )
    (net (code "222") (name "Net-(IC4C-+IN)") (class "Default")
      (node (ref "C6") (pin "1") (pinfunction "1_1") (pintype "passive"))
      (node (ref "IC4") (pin "9") (pinfunction "+IN_9") (pintype "input"))
      (node (ref "R29") (pin "2") (pinfunction "2_2") (pintype "passive"))
      (node (ref "R38") (pin "2") (pinfunction "2_2") (pintype "passive"))
    )
    (net (code "223") (name "Net-(IC4C-OUT)") (class "Default")
      (node (ref "C7") (pin "2") (pinfunction "2_2") (pintype "passive"))
      (node (ref "IC4") (pin "14") (pinfunction "OUT_14") (pintype "open_collector"))
      (node (ref "R28") (pin "2") (pinfunction "2_2") (pintype "passive"))
    )
    (net (code "224") (name "Net-(IC4D-OUT)") (class "Default")
      (node (ref "IC4") (pin "13") (pinfunction "OUT_13") (pintype "open_collector"))
      (node (ref "JP2") (pin "1") (pinfunction "1_1") (pintype "passive"))
      (node (ref "Q9") (pin "1") (pinfunction "G_1") (pintype "passive"))
      (node (ref "R41") (pin "2") (pinfunction "2_2") (pintype "passive"))
    )
    (net (code "225") (name "Net-(IC6-CV)") (class "Default")
      (node (ref "IC6") (pin "5") (pinfunction "CV_5") (pintype "input"))
      (node (ref "R43") (pin "2") (pinfunction "2_2") (pintype "passive"))
    )
    (net (code "226") (name "Net-(IC6-Q)") (class "Default")
      (node (ref "IC6") (pin "3") (pinfunction "Q_3") (pintype "output"))
      (node (ref "IC7") (pin "12") (pinfunction "A_12") (pintype "input"))
      (node (ref "IC7") (pin "4") (pinfunction "A_4") (pintype "input"))
      (node (ref "R43") (pin "1") (pinfunction "1_1") (pintype "passive"))
    )
    (net (code "227") (name "Net-(IC7A-Q)") (class "Default")
      (node (ref "IC7") (pin "6") (pinfunction "Q_6") (pintype "output"))
      (node (ref "Q13") (pin "1") (pinfunction "G_1") (pintype "passive"))
    )
    (net (code "228") (name "Net-(IC7A-T2)") (class "Default")
      (node (ref "C12") (pin "2") (pinfunction "2_2") (pintype "passive"))
      (node (ref "IC7") (pin "2") (pinfunction "T2_2") (pintype "input"))
      (node (ref "R64") (pin "1") (pinfunction "1_1") (pintype "passive"))
    )
    (net (code "229") (name "Net-(IC7B-B)") (class "Default")
      (node (ref "IC7") (pin "11") (pinfunction "B_11") (pintype "input"))
      (node (ref "IC7") (pin "9") (pinfunction "~{Q}_9") (pintype "output"))
      (node (ref "R49") (pin "2") (pinfunction "2_2") (pintype "passive"))
    )
    (net (code "230") (name "Net-(IC7B-T2)") (class "Default")
      (node (ref "C10") (pin "1") (pinfunction "1_1") (pintype "passive"))
      (node (ref "IC7") (pin "14") (pinfunction "T2_14") (pintype "input"))
      (node (ref "R47") (pin "1") (pinfunction "1_1") (pintype "passive"))
    )
    (net (code "231") (name "Net-(IC9A-+IN)") (class "Default")
      (node (ref "C5") (pin "1") (pinfunction "1_1") (pintype "passive"))
      (node (ref "IC9") (pin "3") (pinfunction "+IN_3") (pintype "input"))
      (node (ref "R18") (pin "1") (pinfunction "1_1") (pintype "passive"))
    )
    (net (code "232") (name "Net-(IC9A--IN)") (class "Default")
      (node (ref "IC9") (pin "2") (pinfunction "-IN_2") (pintype "input"))
      (node (ref "R19") (pin "2") (pinfunction "2_2") (pintype "passive"))
    )
    (net (code "233") (name "Net-(IC9A-OUT)") (class "Default")
      (node (ref "IC9") (pin "1") (pinfunction "OUT_1") (pintype "output"))
      (node (ref "R50") (pin "2") (pinfunction "2_2") (pintype "passive"))
    )
    (net (code "234") (name "Net-(IC9B-+IN)") (class "Default")
      (node (ref "IC9") (pin "5") (pinfunction "+IN_5") (pintype "input"))
      (node (ref "Q11") (pin "3") (pinfunction "D_3") (pintype "passive"))
      (node (ref "R51") (pin "2") (pinfunction "2_2") (pintype "passive"))
      (node (ref "R52") (pin "2") (pinfunction "2_2") (pintype "passive"))
    )
    (net (code "235") (name "Net-(IC9B--IN)") (class "Default")
      (node (ref "IC9") (pin "6") (pinfunction "-IN_6") (pintype "input"))
      (node (ref "R53") (pin "1") (pinfunction "1_1") (pintype "passive"))
      (node (ref "R54") (pin "2") (pinfunction "2_2") (pintype "passive"))
    )
    (net (code "236") (name "Net-(IC9B-OUT)") (class "Default")
      (node (ref "IC9") (pin "7") (pinfunction "OUT_7") (pintype "output"))
      (node (ref "R32") (pin "2") (pinfunction "2_2") (pintype "passive"))
      (node (ref "R39") (pin "1") (pinfunction "1_1") (pintype "passive"))
      (node (ref "R52") (pin "1") (pinfunction "1_1") (pintype "passive"))
    )
    (net (code "237") (name "Net-(IC10A-A)") (class "Default")
      (node (ref "IC10") (pin "10") (pinfunction "A_10") (pintype "input"))
      (node (ref "R157") (pin "1") (pinfunction "1_1") (pintype "passive"))
      (node (ref "R157") (pin "2") (pinfunction "2_2") (pintype "passive"))
      (node (ref "R72") (pin "1") (pinfunction "1_1") (pintype "passive"))
      (node (ref "X4") (pin "4") (pinfunction "4_4") (pintype "passive"))
      (node (ref "X5") (pin "2") (pinfunction "S_2") (pintype "passive"))
    )
    (net (code "238") (name "Net-(IC10A-B)") (class "Default")
      (node (ref "IC10") (pin "13") (pinfunction "B_13") (pintype "input"))
      (node (ref "R156") (pin "1") (pinfunction "1_1") (pintype "passive"))
      (node (ref "R156") (pin "2") (pinfunction "2_2") (pintype "passive"))
      (node (ref "R71") (pin "1") (pinfunction "1_1") (pintype "passive"))
      (node (ref "X4") (pin "3") (pinfunction "3_3") (pintype "passive"))
      (node (ref "X5") (pin "3") (pinfunction "S_3") (pintype "passive"))
    )
    (net (code "239") (name "Net-(IC10A-C)") (class "Default")
      (node (ref "IC10") (pin "12") (pinfunction "C_12") (pintype "input"))
      (node (ref "R155") (pin "1") (pinfunction "1_1") (pintype "passive"))
      (node (ref "R155") (pin "2") (pinfunction "2_2") (pintype "passive"))
      (node (ref "R70") (pin "1") (pinfunction "1_1") (pintype "passive"))
      (node (ref "X4") (pin "2") (pinfunction "2_2") (pintype "passive"))
      (node (ref "X5") (pin "4") (pinfunction "S_4") (pintype "passive"))
    )
    (net (code "240") (name "Net-(IC10A-Q0)") (class "Default")
      (node (ref "IC10") (pin "3") (pinfunction "Q0_3") (pintype "output"))
      (node (ref "IC12") (pin "1") (pinfunction "I1_1") (pintype "input"))
      (node (ref "IC12") (pin "2") (pinfunction "I2_2") (pintype "input"))
      (node (ref "Q20") (pin "1") (pinfunction "G_1") (pintype "passive"))
      (node (ref "Q21") (pin "1") (pinfunction "G_1") (pintype "passive"))
    )
    (net (code "241") (name "Net-(IC10A-Q1)") (class "Default")
      (node (ref "IC10") (pin "14") (pinfunction "Q1_14") (pintype "output"))
      (node (ref "IC12") (pin "6") (pinfunction "I6_6") (pintype "input"))
    )
    (net (code "242") (name "Net-(IC10A-Q2)") (class "Default")
      (node (ref "IC10") (pin "2") (pinfunction "Q2_2") (pintype "output"))
      (node (ref "IC12") (pin "7") (pinfunction "I7_7") (pintype "input"))
    )
    (net (code "243") (name "Net-(IC10A-Q3)") (class "Default")
      (node (ref "IC10") (pin "15") (pinfunction "Q3_15") (pintype "output"))
      (node (ref "IC12") (pin "5") (pinfunction "I5_5") (pintype "input"))
    )
    (net (code "244") (name "Net-(IC10A-Q4)") (class "Default")
      (node (ref "IC10") (pin "1") (pinfunction "Q4_1") (pintype "output"))
      (node (ref "IC12") (pin "4") (pinfunction "I4_4") (pintype "input"))
    )
    (net (code "245") (name "Net-(IC10A-Q5)") (class "Default")
      (node (ref "IC10") (pin "6") (pinfunction "Q5_6") (pintype "output"))
      (node (ref "IC12") (pin "3") (pinfunction "I3_3") (pintype "input"))
    )
    (net (code "246") (name "Net-(IC11-ADJ)") (class "Default")
      (node (ref "IC11") (pin "1") (pinfunction "ADJ_1") (pintype "input"))
      (node (ref "R68") (pin "1") (pinfunction "1_1") (pintype "passive"))
      (node (ref "R75") (pin "2") (pinfunction "2_2") (pintype "passive"))
      (node (ref "X4") (pin "7") (pinfunction "7_7") (pintype "passive"))
    )
    (net (code "247") (name "Net-(IC11-VI)") (class "Default")
      (node (ref "IC11") (pin "3") (pinfunction "VI_3") (pintype "input"))
      (node (ref "Q17") (pin "2") (pinfunction "C_2") (pintype "passive"))
    )
    (net (code "248") (name "Net-(IC11-VO)") (class "Default")
      (node (ref "IC11") (pin "2") (pinfunction "VO_2") (pintype "passive"))
      (node (ref "R68") (pin "2") (pinfunction "2_2") (pintype "passive"))
    )
    (net (code "249") (name "Net-(IC12-O1)") (class "Default")
      (node (ref "IC12") (pin "16") (pinfunction "O1_16") (pintype "open_collector"))
      (node (ref "Q20") (pin "3") (pinfunction "D_3") (pintype "passive"))
      (node (ref "R161") (pin "1") (pinfunction "1_1") (pintype "passive"))
    )
    (net (code "250") (name "Net-(IC12-O2)") (class "Default")
      (node (ref "IC12") (pin "15") (pinfunction "O2_15") (pintype "open_collector"))
      (node (ref "R90") (pin "1") (pinfunction "1_1") (pintype "passive"))
    )
    (net (code "251") (name "Net-(IC13A-+IN)") (class "Default")
      (node (ref "IC13") (pin "11") (pinfunction "+IN_11") (pintype "input"))
      (node (ref "IC13") (pin "5") (pinfunction "+IN_5") (pintype "input"))
      (node (ref "R79") (pin "1") (pinfunction "1_1") (pintype "passive"))
      (node (ref "R80") (pin "2") (pinfunction "2_2") (pintype "passive"))
      (node (ref "R81") (pin "2") (pinfunction "2_2") (pintype "passive"))
    )
    (net (code "252") (name "Net-(IC13A--IN)") (class "Default")
      (node (ref "C16") (pin "1") (pinfunction "1_1") (pintype "passive"))
      (node (ref "IC13") (pin "10") (pinfunction "-IN_10") (pintype "input"))
      (node (ref "IC13") (pin "4") (pinfunction "-IN_4") (pintype "input"))
      (node (ref "R78") (pin "1") (pinfunction "1_1") (pintype "passive"))
    )
    (net (code "253") (name "Net-(IC13A-OUT)") (class "Default")
      (node (ref "IC13") (pin "2") (pinfunction "OUT_2") (pintype "open_collector"))
      (node (ref "R81") (pin "1") (pinfunction "1_1") (pintype "passive"))
    )
    (net (code "254") (name "Net-(IC13B-+IN)") (class "Default")
      (node (ref "IC13") (pin "7") (pinfunction "+IN_7") (pintype "input"))
      (node (ref "R76") (pin "1") (pinfunction "1_1") (pintype "passive"))
      (node (ref "R93") (pin "1") (pinfunction "1_1") (pintype "passive"))
    )
    (net (code "255") (name "Net-(IC13B--IN)") (class "Default")
      (node (ref "IC13") (pin "6") (pinfunction "-IN_6") (pintype "input"))
      (node (ref "IC13") (pin "8") (pinfunction "-IN_8") (pintype "input"))
      (node (ref "R75") (pin "1") (pinfunction "1_1") (pintype "passive"))
    )
    (net (code "256") (name "Net-(IC13B-OUT)") (class "Default")
      (node (ref "IC13") (pin "1") (pinfunction "OUT_1") (pintype "open_collector"))
      (node (ref "R77") (pin "2") (pinfunction "2_2") (pintype "passive"))
      (node (ref "R82") (pin "2") (pinfunction "2_2") (pintype "passive"))
    )
    (net (code "257") (name "Net-(IC13C-+IN)") (class "Default")
      (node (ref "C19") (pin "1") (pinfunction "1_1") (pintype "passive"))
      (node (ref "IC13") (pin "9") (pinfunction "+IN_9") (pintype "input"))
      (node (ref "R84") (pin "2") (pinfunction "2_2") (pintype "passive"))
      (node (ref "R93") (pin "2") (pinfunction "2_2") (pintype "passive"))
    )
    (net (code "258") (name "Net-(IC13C-OUT)") (class "Default")
      (node (ref "C20") (pin "2") (pinfunction "2_2") (pintype "passive"))
      (node (ref "IC13") (pin "14") (pinfunction "OUT_14") (pintype "open_collector"))
      (node (ref "R83") (pin "2") (pinfunction "2_2") (pintype "passive"))
    )
    (net (code "259") (name "Net-(IC13D-OUT)") (class "Default")
      (node (ref "IC13") (pin "13") (pinfunction "OUT_13") (pintype "open_collector"))
      (node (ref "JP7") (pin "1") (pinfunction "1_1") (pintype "passive"))
      (node (ref "Q19") (pin "1") (pinfunction "G_1") (pintype "passive"))
      (node (ref "R96") (pin "2") (pinfunction "2_2") (pintype "passive"))
    )
    (net (code "260") (name "Net-(IC15-CV)") (class "Default")
      (node (ref "IC15") (pin "5") (pinfunction "CV_5") (pintype "input"))
      (node (ref "R98") (pin "2") (pinfunction "2_2") (pintype "passive"))
    )
    (net (code "261") (name "Net-(IC15-Q)") (class "Default")
      (node (ref "IC15") (pin "3") (pinfunction "Q_3") (pintype "output"))
      (node (ref "IC16") (pin "12") (pinfunction "A_12") (pintype "input"))
      (node (ref "IC16") (pin "4") (pinfunction "A_4") (pintype "input"))
      (node (ref "R98") (pin "1") (pinfunction "1_1") (pintype "passive"))
    )
    (net (code "262") (name "Net-(IC16A-Q)") (class "Default")
      (node (ref "IC16") (pin "6") (pinfunction "Q_6") (pintype "output"))
      (node (ref "Q23") (pin "1") (pinfunction "G_1") (pintype "passive"))
    )
    (net (code "263") (name "Net-(IC16A-T2)") (class "Default")
      (node (ref "C25") (pin "2") (pinfunction "2_2") (pintype "passive"))
      (node (ref "IC16") (pin "2") (pinfunction "T2_2") (pintype "input"))
      (node (ref "R163") (pin "1") (pinfunction "1_1") (pintype "passive"))
    )
    (net (code "264") (name "Net-(IC16B-B)") (class "Default")
      (node (ref "IC16") (pin "11") (pinfunction "B_11") (pintype "input"))
      (node (ref "IC16") (pin "9") (pinfunction "~{Q}_9") (pintype "output"))
      (node (ref "R148") (pin "2") (pinfunction "2_2") (pintype "passive"))
    )
    (net (code "265") (name "Net-(IC16B-T2)") (class "Default")
      (node (ref "C23") (pin "1") (pinfunction "1_1") (pintype "passive"))
      (node (ref "IC16") (pin "14") (pinfunction "T2_14") (pintype "input"))
      (node (ref "R139") (pin "1") (pinfunction "1_1") (pintype "passive"))
    )
    (net (code "266") (name "Net-(IC18A-+IN)") (class "Default")
      (node (ref "C18") (pin "1") (pinfunction "1_1") (pintype "passive"))
      (node (ref "IC18") (pin "3") (pinfunction "+IN_3") (pintype "input"))
      (node (ref "R73") (pin "1") (pinfunction "1_1") (pintype "passive"))
    )
    (net (code "267") (name "Net-(IC18A--IN)") (class "Default")
      (node (ref "IC18") (pin "2") (pinfunction "-IN_2") (pintype "input"))
      (node (ref "R74") (pin "2") (pinfunction "2_2") (pintype "passive"))
    )
    (net (code "268") (name "Net-(IC18A-OUT)") (class "Default")
      (node (ref "IC18") (pin "1") (pinfunction "OUT_1") (pintype "output"))
      (node (ref "R149") (pin "2") (pinfunction "2_2") (pintype "passive"))
    )
    (net (code "269") (name "Net-(IC18B-+IN)") (class "Default")
      (node (ref "IC18") (pin "5") (pinfunction "+IN_5") (pintype "input"))
      (node (ref "Q21") (pin "3") (pinfunction "D_3") (pintype "passive"))
      (node (ref "R150") (pin "2") (pinfunction "2_2") (pintype "passive"))
      (node (ref "R151") (pin "2") (pinfunction "2_2") (pintype "passive"))
    )
    (net (code "270") (name "Net-(IC18B--IN)") (class "Default")
      (node (ref "IC18") (pin "6") (pinfunction "-IN_6") (pintype "input"))
      (node (ref "R152") (pin "1") (pinfunction "1_1") (pintype "passive"))
      (node (ref "R153") (pin "2") (pinfunction "2_2") (pintype "passive"))
    )
    (net (code "271") (name "Net-(IC18B-OUT)") (class "Default")
      (node (ref "IC18") (pin "7") (pinfunction "OUT_7") (pintype "output"))
      (node (ref "R151") (pin "1") (pinfunction "1_1") (pintype "passive"))
      (node (ref "R87") (pin "2") (pinfunction "2_2") (pintype "passive"))
      (node (ref "R94") (pin "1") (pinfunction "1_1") (pintype "passive"))
    )
    (net (code "272") (name "Net-(IC19A-A)") (class "Default")
      (node (ref "IC19") (pin "10") (pinfunction "A_10") (pintype "input"))
      (node (ref "R171") (pin "1") (pinfunction "1_1") (pintype "passive"))
      (node (ref "R212") (pin "1") (pinfunction "1_1") (pintype "passive"))
      (node (ref "R212") (pin "2") (pinfunction "2_2") (pintype "passive"))
      (node (ref "X7") (pin "4") (pinfunction "4_4") (pintype "passive"))
      (node (ref "X8") (pin "2") (pinfunction "S_2") (pintype "passive"))
    )
    (net (code "273") (name "Net-(IC19A-B)") (class "Default")
      (node (ref "IC19") (pin "13") (pinfunction "B_13") (pintype "input"))
      (node (ref "R170") (pin "1") (pinfunction "1_1") (pintype "passive"))
      (node (ref "R211") (pin "1") (pinfunction "1_1") (pintype "passive"))
      (node (ref "R211") (pin "2") (pinfunction "2_2") (pintype "passive"))
      (node (ref "X7") (pin "3") (pinfunction "3_3") (pintype "passive"))
      (node (ref "X8") (pin "3") (pinfunction "S_3") (pintype "passive"))
    )
    (net (code "274") (name "Net-(IC19A-C)") (class "Default")
      (node (ref "IC19") (pin "12") (pinfunction "C_12") (pintype "input"))
      (node (ref "R169") (pin "1") (pinfunction "1_1") (pintype "passive"))
      (node (ref "R210") (pin "1") (pinfunction "1_1") (pintype "passive"))
      (node (ref "R210") (pin "2") (pinfunction "2_2") (pintype "passive"))
      (node (ref "X7") (pin "2") (pinfunction "2_2") (pintype "passive"))
      (node (ref "X8") (pin "4") (pinfunction "S_4") (pintype "passive"))
    )
    (net (code "275") (name "Net-(IC19A-Q0)") (class "Default")
      (node (ref "IC19") (pin "3") (pinfunction "Q0_3") (pintype "output"))
      (node (ref "IC21") (pin "1") (pinfunction "I1_1") (pintype "input"))
      (node (ref "IC21") (pin "2") (pinfunction "I2_2") (pintype "input"))
      (node (ref "Q30") (pin "1") (pinfunction "G_1") (pintype "passive"))
      (node (ref "Q31") (pin "1") (pinfunction "G_1") (pintype "passive"))
    )
    (net (code "276") (name "Net-(IC19A-Q1)") (class "Default")
      (node (ref "IC19") (pin "14") (pinfunction "Q1_14") (pintype "output"))
      (node (ref "IC21") (pin "6") (pinfunction "I6_6") (pintype "input"))
    )
    (net (code "277") (name "Net-(IC19A-Q2)") (class "Default")
      (node (ref "IC19") (pin "2") (pinfunction "Q2_2") (pintype "output"))
      (node (ref "IC21") (pin "7") (pinfunction "I7_7") (pintype "input"))
    )
    (net (code "278") (name "Net-(IC19A-Q3)") (class "Default")
      (node (ref "IC19") (pin "15") (pinfunction "Q3_15") (pintype "output"))
      (node (ref "IC21") (pin "5") (pinfunction "I5_5") (pintype "input"))
    )
    (net (code "279") (name "Net-(IC19A-Q4)") (class "Default")
      (node (ref "IC19") (pin "1") (pinfunction "Q4_1") (pintype "output"))
      (node (ref "IC21") (pin "4") (pinfunction "I4_4") (pintype "input"))
    )
    (net (code "280") (name "Net-(IC19A-Q5)") (class "Default")
      (node (ref "IC19") (pin "6") (pinfunction "Q5_6") (pintype "output"))
      (node (ref "IC21") (pin "3") (pinfunction "I3_3") (pintype "input"))
    )
    (net (code "281") (name "Net-(IC20-ADJ)") (class "Default")
      (node (ref "IC20") (pin "1") (pinfunction "ADJ_1") (pintype "input"))
      (node (ref "R167") (pin "1") (pinfunction "1_1") (pintype "passive"))
      (node (ref "R174") (pin "2") (pinfunction "2_2") (pintype "passive"))
      (node (ref "X7") (pin "7") (pinfunction "7_7") (pintype "passive"))
    )
    (net (code "282") (name "Net-(IC20-VI)") (class "Default")
      (node (ref "IC20") (pin "3") (pinfunction "VI_3") (pintype "input"))
      (node (ref "Q27") (pin "2") (pinfunction "C_2") (pintype "passive"))
    )
    (net (code "283") (name "Net-(IC20-VO)") (class "Default")
      (node (ref "IC20") (pin "2") (pinfunction "VO_2") (pintype "passive"))
      (node (ref "R167") (pin "2") (pinfunction "2_2") (pintype "passive"))
    )
    (net (code "284") (name "Net-(IC21-O1)") (class "Default")
      (node (ref "IC21") (pin "16") (pinfunction "O1_16") (pintype "open_collector"))
      (node (ref "Q30") (pin "3") (pinfunction "D_3") (pintype "passive"))
      (node (ref "R216") (pin "1") (pinfunction "1_1") (pintype "passive"))
    )
    (net (code "285") (name "Net-(IC21-O2)") (class "Default")
      (node (ref "IC21") (pin "15") (pinfunction "O2_15") (pintype "open_collector"))
      (node (ref "R189") (pin "1") (pinfunction "1_1") (pintype "passive"))
    )
    (net (code "286") (name "Net-(IC22A-+IN)") (class "Default")
      (node (ref "IC22") (pin "11") (pinfunction "+IN_11") (pintype "input"))
      (node (ref "IC22") (pin "5") (pinfunction "+IN_5") (pintype "input"))
      (node (ref "R178") (pin "1") (pinfunction "1_1") (pintype "passive"))
      (node (ref "R179") (pin "2") (pinfunction "2_2") (pintype "passive"))
      (node (ref "R180") (pin "2") (pinfunction "2_2") (pintype "passive"))
    )
    (net (code "287") (name "Net-(IC22A--IN)") (class "Default")
      (node (ref "C28") (pin "1") (pinfunction "1_1") (pintype "passive"))
      (node (ref "IC22") (pin "10") (pinfunction "-IN_10") (pintype "input"))
      (node (ref "IC22") (pin "4") (pinfunction "-IN_4") (pintype "input"))
      (node (ref "R177") (pin "1") (pinfunction "1_1") (pintype "passive"))
    )
    (net (code "288") (name "Net-(IC22A-OUT)") (class "Default")
      (node (ref "IC22") (pin "2") (pinfunction "OUT_2") (pintype "open_collector"))
      (node (ref "R180") (pin "1") (pinfunction "1_1") (pintype "passive"))
    )
    (net (code "289") (name "Net-(IC22B-+IN)") (class "Default")
      (node (ref "IC22") (pin "7") (pinfunction "+IN_7") (pintype "input"))
      (node (ref "R175") (pin "1") (pinfunction "1_1") (pintype "passive"))
      (node (ref "R192") (pin "1") (pinfunction "1_1") (pintype "passive"))
    )
    (net (code "290") (name "Net-(IC22B--IN)") (class "Default")
      (node (ref "IC22") (pin "6") (pinfunction "-IN_6") (pintype "input"))
      (node (ref "IC22") (pin "8") (pinfunction "-IN_8") (pintype "input"))
      (node (ref "R174") (pin "1") (pinfunction "1_1") (pintype "passive"))
    )
    (net (code "291") (name "Net-(IC22B-OUT)") (class "Default")
      (node (ref "IC22") (pin "1") (pinfunction "OUT_1") (pintype "open_collector"))
      (node (ref "R176") (pin "2") (pinfunction "2_2") (pintype "passive"))
      (node (ref "R181") (pin "2") (pinfunction "2_2") (pintype "passive"))
    )
    (net (code "292") (name "Net-(IC22C-+IN)") (class "Default")
      (node (ref "C31") (pin "1") (pinfunction "1_1") (pintype "passive"))
      (node (ref "IC22") (pin "9") (pinfunction "+IN_9") (pintype "input"))
      (node (ref "R183") (pin "2") (pinfunction "2_2") (pintype "passive"))
      (node (ref "R192") (pin "2") (pinfunction "2_2") (pintype "passive"))
    )
    (net (code "293") (name "Net-(IC22C-OUT)") (class "Default")
      (node (ref "C32") (pin "2") (pinfunction "2_2") (pintype "passive"))
      (node (ref "IC22") (pin "14") (pinfunction "OUT_14") (pintype "open_collector"))
      (node (ref "R182") (pin "2") (pinfunction "2_2") (pintype "passive"))
    )
    (net (code "294") (name "Net-(IC22D-OUT)") (class "Default")
      (node (ref "IC22") (pin "13") (pinfunction "OUT_13") (pintype "open_collector"))
      (node (ref "JP12") (pin "1") (pinfunction "1_1") (pintype "passive"))
      (node (ref "Q29") (pin "1") (pinfunction "G_1") (pintype "passive"))
      (node (ref "R195") (pin "2") (pinfunction "2_2") (pintype "passive"))
    )
    (net (code "295") (name "Net-(IC24-CV)") (class "Default")
      (node (ref "IC24") (pin "5") (pinfunction "CV_5") (pintype "input"))
      (node (ref "R197") (pin "2") (pinfunction "2_2") (pintype "passive"))
    )
    (net (code "296") (name "Net-(IC24-Q)") (class "Default")
      (node (ref "IC24") (pin "3") (pinfunction "Q_3") (pintype "output"))
      (node (ref "IC25") (pin "12") (pinfunction "A_12") (pintype "input"))
      (node (ref "IC25") (pin "4") (pinfunction "A_4") (pintype "input"))
      (node (ref "R197") (pin "1") (pinfunction "1_1") (pintype "passive"))
    )
    (net (code "297") (name "Net-(IC25A-Q)") (class "Default")
      (node (ref "IC25") (pin "6") (pinfunction "Q_6") (pintype "output"))
      (node (ref "Q33") (pin "1") (pinfunction "G_1") (pintype "passive"))
    )
    (net (code "298") (name "Net-(IC25A-T2)") (class "Default")
      (node (ref "C37") (pin "2") (pinfunction "2_2") (pintype "passive"))
      (node (ref "IC25") (pin "2") (pinfunction "T2_2") (pintype "input"))
      (node (ref "R218") (pin "1") (pinfunction "1_1") (pintype "passive"))
    )
    (net (code "299") (name "Net-(IC25B-B)") (class "Default")
      (node (ref "IC25") (pin "11") (pinfunction "B_11") (pintype "input"))
      (node (ref "IC25") (pin "9") (pinfunction "~{Q}_9") (pintype "output"))
      (node (ref "R203") (pin "2") (pinfunction "2_2") (pintype "passive"))
    )
    (net (code "300") (name "Net-(IC25B-T2)") (class "Default")
      (node (ref "C35") (pin "1") (pinfunction "1_1") (pintype "passive"))
      (node (ref "IC25") (pin "14") (pinfunction "T2_14") (pintype "input"))
      (node (ref "R201") (pin "1") (pinfunction "1_1") (pintype "passive"))
    )
    (net (code "301") (name "Net-(IC27A-+IN)") (class "Default")
      (node (ref "C30") (pin "1") (pinfunction "1_1") (pintype "passive"))
      (node (ref "IC27") (pin "3") (pinfunction "+IN_3") (pintype "input"))
      (node (ref "R172") (pin "1") (pinfunction "1_1") (pintype "passive"))
    )
    (net (code "302") (name "Net-(IC27A--IN)") (class "Default")
      (node (ref "IC27") (pin "2") (pinfunction "-IN_2") (pintype "input"))
      (node (ref "R173") (pin "2") (pinfunction "2_2") (pintype "passive"))
    )
    (net (code "303") (name "Net-(IC27A-OUT)") (class "Default")
      (node (ref "IC27") (pin "1") (pinfunction "OUT_1") (pintype "output"))
      (node (ref "R204") (pin "2") (pinfunction "2_2") (pintype "passive"))
    )
    (net (code "304") (name "Net-(IC27B-+IN)") (class "Default")
      (node (ref "IC27") (pin "5") (pinfunction "+IN_5") (pintype "input"))
      (node (ref "Q31") (pin "3") (pinfunction "D_3") (pintype "passive"))
      (node (ref "R205") (pin "2") (pinfunction "2_2") (pintype "passive"))
      (node (ref "R206") (pin "2") (pinfunction "2_2") (pintype "passive"))
    )
    (net (code "305") (name "Net-(IC27B--IN)") (class "Default")
      (node (ref "IC27") (pin "6") (pinfunction "-IN_6") (pintype "input"))
      (node (ref "R207") (pin "1") (pinfunction "1_1") (pintype "passive"))
      (node (ref "R208") (pin "2") (pinfunction "2_2") (pintype "passive"))
    )
    (net (code "306") (name "Net-(IC27B-OUT)") (class "Default")
      (node (ref "IC27") (pin "7") (pinfunction "OUT_7") (pintype "output"))
      (node (ref "R186") (pin "2") (pinfunction "2_2") (pintype "passive"))
      (node (ref "R193") (pin "1") (pinfunction "1_1") (pintype "passive"))
      (node (ref "R206") (pin "1") (pinfunction "1_1") (pintype "passive"))
    )
    (net (code "307") (name "Net-(IC28A-A)") (class "Default")
      (node (ref "IC28") (pin "10") (pinfunction "A_10") (pintype "input"))
      (node (ref "R226") (pin "1") (pinfunction "1_1") (pintype "passive"))
      (node (ref "R267") (pin "1") (pinfunction "1_1") (pintype "passive"))
      (node (ref "R267") (pin "2") (pinfunction "2_2") (pintype "passive"))
      (node (ref "X10") (pin "4") (pinfunction "4_4") (pintype "passive"))
      (node (ref "X11") (pin "2") (pinfunction "S_2") (pintype "passive"))
    )
    (net (code "308") (name "Net-(IC28A-B)") (class "Default")
      (node (ref "IC28") (pin "13") (pinfunction "B_13") (pintype "input"))
      (node (ref "R225") (pin "1") (pinfunction "1_1") (pintype "passive"))
      (node (ref "R266") (pin "1") (pinfunction "1_1") (pintype "passive"))
      (node (ref "R266") (pin "2") (pinfunction "2_2") (pintype "passive"))
      (node (ref "X10") (pin "3") (pinfunction "3_3") (pintype "passive"))
      (node (ref "X11") (pin "3") (pinfunction "S_3") (pintype "passive"))
    )
    (net (code "309") (name "Net-(IC28A-C)") (class "Default")
      (node (ref "IC28") (pin "12") (pinfunction "C_12") (pintype "input"))
      (node (ref "R224") (pin "1") (pinfunction "1_1") (pintype "passive"))
      (node (ref "R265") (pin "1") (pinfunction "1_1") (pintype "passive"))
      (node (ref "R265") (pin "2") (pinfunction "2_2") (pintype "passive"))
      (node (ref "X10") (pin "2") (pinfunction "2_2") (pintype "passive"))
      (node (ref "X11") (pin "4") (pinfunction "S_4") (pintype "passive"))
    )
    (net (code "310") (name "Net-(IC28A-Q0)") (class "Default")
      (node (ref "IC28") (pin "3") (pinfunction "Q0_3") (pintype "output"))
      (node (ref "IC30") (pin "1") (pinfunction "I1_1") (pintype "input"))
      (node (ref "IC30") (pin "2") (pinfunction "I2_2") (pintype "input"))
      (node (ref "Q40") (pin "1") (pinfunction "G_1") (pintype "passive"))
      (node (ref "Q41") (pin "1") (pinfunction "G_1") (pintype "passive"))
    )
    (net (code "311") (name "Net-(IC28A-Q1)") (class "Default")
      (node (ref "IC28") (pin "14") (pinfunction "Q1_14") (pintype "output"))
      (node (ref "IC30") (pin "6") (pinfunction "I6_6") (pintype "input"))
    )
    (net (code "312") (name "Net-(IC28A-Q2)") (class "Default")
      (node (ref "IC28") (pin "2") (pinfunction "Q2_2") (pintype "output"))
      (node (ref "IC30") (pin "7") (pinfunction "I7_7") (pintype "input"))
    )
    (net (code "313") (name "Net-(IC28A-Q3)") (class "Default")
      (node (ref "IC28") (pin "15") (pinfunction "Q3_15") (pintype "output"))
      (node (ref "IC30") (pin "5") (pinfunction "I5_5") (pintype "input"))
    )
    (net (code "314") (name "Net-(IC28A-Q4)") (class "Default")
      (node (ref "IC28") (pin "1") (pinfunction "Q4_1") (pintype "output"))
      (node (ref "IC30") (pin "4") (pinfunction "I4_4") (pintype "input"))
    )
    (net (code "315") (name "Net-(IC28A-Q5)") (class "Default")
      (node (ref "IC28") (pin "6") (pinfunction "Q5_6") (pintype "output"))
      (node (ref "IC30") (pin "3") (pinfunction "I3_3") (pintype "input"))
    )
    (net (code "316") (name "Net-(IC29-ADJ)") (class "Default")
      (node (ref "IC29") (pin "1") (pinfunction "ADJ_1") (pintype "input"))
      (node (ref "R222") (pin "1") (pinfunction "1_1") (pintype "passive"))
      (node (ref "R229") (pin "2") (pinfunction "2_2") (pintype "passive"))
      (node (ref "X10") (pin "7") (pinfunction "7_7") (pintype "passive"))
    )
    (net (code "317") (name "Net-(IC29-VI)") (class "Default")
      (node (ref "IC29") (pin "3") (pinfunction "VI_3") (pintype "input"))
      (node (ref "Q37") (pin "2") (pinfunction "C_2") (pintype "passive"))
    )
    (net (code "318") (name "Net-(IC29-VO)") (class "Default")
      (node (ref "IC29") (pin "2") (pinfunction "VO_2") (pintype "passive"))
      (node (ref "R222") (pin "2") (pinfunction "2_2") (pintype "passive"))
    )
    (net (code "319") (name "Net-(IC30-O1)") (class "Default")
      (node (ref "IC30") (pin "16") (pinfunction "O1_16") (pintype "open_collector"))
      (node (ref "Q40") (pin "3") (pinfunction "D_3") (pintype "passive"))
      (node (ref "R271") (pin "1") (pinfunction "1_1") (pintype "passive"))
    )
    (net (code "320") (name "Net-(IC30-O2)") (class "Default")
      (node (ref "IC30") (pin "15") (pinfunction "O2_15") (pintype "open_collector"))
      (node (ref "R244") (pin "1") (pinfunction "1_1") (pintype "passive"))
    )
    (net (code "321") (name "Net-(IC31A-+IN)") (class "Default")
      (node (ref "IC31") (pin "11") (pinfunction "+IN_11") (pintype "input"))
      (node (ref "IC31") (pin "5") (pinfunction "+IN_5") (pintype "input"))
      (node (ref "R233") (pin "1") (pinfunction "1_1") (pintype "passive"))
      (node (ref "R234") (pin "2") (pinfunction "2_2") (pintype "passive"))
      (node (ref "R235") (pin "2") (pinfunction "2_2") (pintype "passive"))
    )
    (net (code "322") (name "Net-(IC31A--IN)") (class "Default")
      (node (ref "C40") (pin "1") (pinfunction "1_1") (pintype "passive"))
      (node (ref "IC31") (pin "10") (pinfunction "-IN_10") (pintype "input"))
      (node (ref "IC31") (pin "4") (pinfunction "-IN_4") (pintype "input"))
      (node (ref "R232") (pin "1") (pinfunction "1_1") (pintype "passive"))
    )
    (net (code "323") (name "Net-(IC31A-OUT)") (class "Default")
      (node (ref "IC31") (pin "2") (pinfunction "OUT_2") (pintype "open_collector"))
      (node (ref "R235") (pin "1") (pinfunction "1_1") (pintype "passive"))
    )
    (net (code "324") (name "Net-(IC31B-+IN)") (class "Default")
      (node (ref "IC31") (pin "7") (pinfunction "+IN_7") (pintype "input"))
      (node (ref "R230") (pin "1") (pinfunction "1_1") (pintype "passive"))
      (node (ref "R247") (pin "1") (pinfunction "1_1") (pintype "passive"))
    )
    (net (code "325") (name "Net-(IC31B--IN)") (class "Default")
      (node (ref "IC31") (pin "6") (pinfunction "-IN_6") (pintype "input"))
      (node (ref "IC31") (pin "8") (pinfunction "-IN_8") (pintype "input"))
      (node (ref "R229") (pin "1") (pinfunction "1_1") (pintype "passive"))
    )
    (net (code "326") (name "Net-(IC31B-OUT)") (class "Default")
      (node (ref "IC31") (pin "1") (pinfunction "OUT_1") (pintype "open_collector"))
      (node (ref "R231") (pin "2") (pinfunction "2_2") (pintype "passive"))
      (node (ref "R236") (pin "2") (pinfunction "2_2") (pintype "passive"))
    )
    (net (code "327") (name "Net-(IC31C-+IN)") (class "Default")
      (node (ref "C43") (pin "1") (pinfunction "1_1") (pintype "passive"))
      (node (ref "IC31") (pin "9") (pinfunction "+IN_9") (pintype "input"))
      (node (ref "R238") (pin "2") (pinfunction "2_2") (pintype "passive"))
      (node (ref "R247") (pin "2") (pinfunction "2_2") (pintype "passive"))
    )
    (net (code "328") (name "Net-(IC31C-OUT)") (class "Default")
      (node (ref "C44") (pin "2") (pinfunction "2_2") (pintype "passive"))
      (node (ref "IC31") (pin "14") (pinfunction "OUT_14") (pintype "open_collector"))
      (node (ref "R237") (pin "2") (pinfunction "2_2") (pintype "passive"))
    )
    (net (code "329") (name "Net-(IC31D-OUT)") (class "Default")
      (node (ref "IC31") (pin "13") (pinfunction "OUT_13") (pintype "open_collector"))
      (node (ref "JP17") (pin "1") (pinfunction "1_1") (pintype "passive"))
      (node (ref "Q39") (pin "1") (pinfunction "G_1") (pintype "passive"))
      (node (ref "R250") (pin "2") (pinfunction "2_2") (pintype "passive"))
    )
    (net (code "330") (name "Net-(IC33-CV)") (class "Default")
      (node (ref "IC33") (pin "5") (pinfunction "CV_5") (pintype "input"))
      (node (ref "R252") (pin "2") (pinfunction "2_2") (pintype "passive"))
    )
    (net (code "331") (name "Net-(IC33-Q)") (class "Default")
      (node (ref "IC33") (pin "3") (pinfunction "Q_3") (pintype "output"))
      (node (ref "IC34") (pin "12") (pinfunction "A_12") (pintype "input"))
      (node (ref "IC34") (pin "4") (pinfunction "A_4") (pintype "input"))
      (node (ref "R252") (pin "1") (pinfunction "1_1") (pintype "passive"))
    )
    (net (code "332") (name "Net-(IC34A-Q)") (class "Default")
      (node (ref "IC34") (pin "6") (pinfunction "Q_6") (pintype "output"))
      (node (ref "Q43") (pin "1") (pinfunction "G_1") (pintype "passive"))
    )
    (net (code "333") (name "Net-(IC34A-T2)") (class "Default")
      (node (ref "C49") (pin "2") (pinfunction "2_2") (pintype "passive"))
      (node (ref "IC34") (pin "2") (pinfunction "T2_2") (pintype "input"))
      (node (ref "R273") (pin "1") (pinfunction "1_1") (pintype "passive"))
    )
    (net (code "334") (name "Net-(IC34B-B)") (class "Default")
      (node (ref "IC34") (pin "11") (pinfunction "B_11") (pintype "input"))
      (node (ref "IC34") (pin "9") (pinfunction "~{Q}_9") (pintype "output"))
      (node (ref "R258") (pin "2") (pinfunction "2_2") (pintype "passive"))
    )
    (net (code "335") (name "Net-(IC34B-T2)") (class "Default")
      (node (ref "C47") (pin "1") (pinfunction "1_1") (pintype "passive"))
      (node (ref "IC34") (pin "14") (pinfunction "T2_14") (pintype "input"))
      (node (ref "R256") (pin "1") (pinfunction "1_1") (pintype "passive"))
    )
    (net (code "336") (name "Net-(IC36A-+IN)") (class "Default")
      (node (ref "C42") (pin "1") (pinfunction "1_1") (pintype "passive"))
      (node (ref "IC36") (pin "3") (pinfunction "+IN_3") (pintype "input"))
      (node (ref "R227") (pin "1") (pinfunction "1_1") (pintype "passive"))
    )
    (net (code "337") (name "Net-(IC36A--IN)") (class "Default")
      (node (ref "IC36") (pin "2") (pinfunction "-IN_2") (pintype "input"))
      (node (ref "R228") (pin "2") (pinfunction "2_2") (pintype "passive"))
    )
    (net (code "338") (name "Net-(IC36A-OUT)") (class "Default")
      (node (ref "IC36") (pin "1") (pinfunction "OUT_1") (pintype "output"))
      (node (ref "R259") (pin "2") (pinfunction "2_2") (pintype "passive"))
    )
    (net (code "339") (name "Net-(IC36B-+IN)") (class "Default")
      (node (ref "IC36") (pin "5") (pinfunction "+IN_5") (pintype "input"))
      (node (ref "Q41") (pin "3") (pinfunction "D_3") (pintype "passive"))
      (node (ref "R260") (pin "2") (pinfunction "2_2") (pintype "passive"))
      (node (ref "R261") (pin "2") (pinfunction "2_2") (pintype "passive"))
    )
    (net (code "340") (name "Net-(IC36B--IN)") (class "Default")
      (node (ref "IC36") (pin "6") (pinfunction "-IN_6") (pintype "input"))
      (node (ref "R262") (pin "1") (pinfunction "1_1") (pintype "passive"))
      (node (ref "R263") (pin "2") (pinfunction "2_2") (pintype "passive"))
    )
    (net (code "341") (name "Net-(IC36B-OUT)") (class "Default")
      (node (ref "IC36") (pin "7") (pinfunction "OUT_7") (pintype "output"))
      (node (ref "R241") (pin "2") (pinfunction "2_2") (pintype "passive"))
      (node (ref "R248") (pin "1") (pinfunction "1_1") (pintype "passive"))
      (node (ref "R261") (pin "1") (pinfunction "1_1") (pintype "passive"))
    )
    (net (code "342") (name "Net-(IC37A-A)") (class "Default")
      (node (ref "IC37") (pin "10") (pinfunction "A_10") (pintype "input"))
      (node (ref "R281") (pin "1") (pinfunction "1_1") (pintype "passive"))
      (node (ref "R322") (pin "1") (pinfunction "1_1") (pintype "passive"))
      (node (ref "R322") (pin "2") (pinfunction "2_2") (pintype "passive"))
      (node (ref "X13") (pin "4") (pinfunction "4_4") (pintype "passive"))
      (node (ref "X14") (pin "2") (pinfunction "S_2") (pintype "passive"))
    )
    (net (code "343") (name "Net-(IC37A-B)") (class "Default")
      (node (ref "IC37") (pin "13") (pinfunction "B_13") (pintype "input"))
      (node (ref "R280") (pin "1") (pinfunction "1_1") (pintype "passive"))
      (node (ref "R321") (pin "1") (pinfunction "1_1") (pintype "passive"))
      (node (ref "R321") (pin "2") (pinfunction "2_2") (pintype "passive"))
      (node (ref "X13") (pin "3") (pinfunction "3_3") (pintype "passive"))
      (node (ref "X14") (pin "3") (pinfunction "S_3") (pintype "passive"))
    )
    (net (code "344") (name "Net-(IC37A-C)") (class "Default")
      (node (ref "IC37") (pin "12") (pinfunction "C_12") (pintype "input"))
      (node (ref "R279") (pin "1") (pinfunction "1_1") (pintype "passive"))
      (node (ref "R320") (pin "1") (pinfunction "1_1") (pintype "passive"))
      (node (ref "R320") (pin "2") (pinfunction "2_2") (pintype "passive"))
      (node (ref "X13") (pin "2") (pinfunction "2_2") (pintype "passive"))
      (node (ref "X14") (pin "4") (pinfunction "S_4") (pintype "passive"))
    )
    (net (code "345") (name "Net-(IC37A-Q0)") (class "Default")
      (node (ref "IC37") (pin "3") (pinfunction "Q0_3") (pintype "output"))
      (node (ref "IC39") (pin "1") (pinfunction "I1_1") (pintype "input"))
      (node (ref "IC39") (pin "2") (pinfunction "I2_2") (pintype "input"))
      (node (ref "Q50") (pin "1") (pinfunction "G_1") (pintype "passive"))
      (node (ref "Q51") (pin "1") (pinfunction "G_1") (pintype "passive"))
    )
    (net (code "346") (name "Net-(IC37A-Q1)") (class "Default")
      (node (ref "IC37") (pin "14") (pinfunction "Q1_14") (pintype "output"))
      (node (ref "IC39") (pin "6") (pinfunction "I6_6") (pintype "input"))
    )
    (net (code "347") (name "Net-(IC37A-Q2)") (class "Default")
      (node (ref "IC37") (pin "2") (pinfunction "Q2_2") (pintype "output"))
      (node (ref "IC39") (pin "7") (pinfunction "I7_7") (pintype "input"))
    )
    (net (code "348") (name "Net-(IC37A-Q3)") (class "Default")
      (node (ref "IC37") (pin "15") (pinfunction "Q3_15") (pintype "output"))
      (node (ref "IC39") (pin "5") (pinfunction "I5_5") (pintype "input"))
    )
    (net (code "349") (name "Net-(IC37A-Q4)") (class "Default")
      (node (ref "IC37") (pin "1") (pinfunction "Q4_1") (pintype "output"))
      (node (ref "IC39") (pin "4") (pinfunction "I4_4") (pintype "input"))
    )
    (net (code "350") (name "Net-(IC37A-Q5)") (class "Default")
      (node (ref "IC37") (pin "6") (pinfunction "Q5_6") (pintype "output"))
      (node (ref "IC39") (pin "3") (pinfunction "I3_3") (pintype "input"))
    )
    (net (code "351") (name "Net-(IC38-ADJ)") (class "Default")
      (node (ref "IC38") (pin "1") (pinfunction "ADJ_1") (pintype "input"))
      (node (ref "R277") (pin "1") (pinfunction "1_1") (pintype "passive"))
      (node (ref "R284") (pin "2") (pinfunction "2_2") (pintype "passive"))
      (node (ref "X13") (pin "7") (pinfunction "7_7") (pintype "passive"))
    )
    (net (code "352") (name "Net-(IC38-VI)") (class "Default")
      (node (ref "IC38") (pin "3") (pinfunction "VI_3") (pintype "input"))
      (node (ref "Q47") (pin "2") (pinfunction "C_2") (pintype "passive"))
    )
    (net (code "353") (name "Net-(IC38-VO)") (class "Default")
      (node (ref "IC38") (pin "2") (pinfunction "VO_2") (pintype "passive"))
      (node (ref "R277") (pin "2") (pinfunction "2_2") (pintype "passive"))
    )
    (net (code "354") (name "Net-(IC39-O1)") (class "Default")
      (node (ref "IC39") (pin "16") (pinfunction "O1_16") (pintype "open_collector"))
      (node (ref "Q50") (pin "3") (pinfunction "D_3") (pintype "passive"))
      (node (ref "R326") (pin "1") (pinfunction "1_1") (pintype "passive"))
    )
    (net (code "355") (name "Net-(IC39-O2)") (class "Default")
      (node (ref "IC39") (pin "15") (pinfunction "O2_15") (pintype "open_collector"))
      (node (ref "R299") (pin "1") (pinfunction "1_1") (pintype "passive"))
    )
    (net (code "356") (name "Net-(IC40A-+IN)") (class "Default")
      (node (ref "IC40") (pin "11") (pinfunction "+IN_11") (pintype "input"))
      (node (ref "IC40") (pin "5") (pinfunction "+IN_5") (pintype "input"))
      (node (ref "R288") (pin "1") (pinfunction "1_1") (pintype "passive"))
      (node (ref "R289") (pin "2") (pinfunction "2_2") (pintype "passive"))
      (node (ref "R290") (pin "2") (pinfunction "2_2") (pintype "passive"))
    )
    (net (code "357") (name "Net-(IC40A--IN)") (class "Default")
      (node (ref "C52") (pin "1") (pinfunction "1_1") (pintype "passive"))
      (node (ref "IC40") (pin "10") (pinfunction "-IN_10") (pintype "input"))
      (node (ref "IC40") (pin "4") (pinfunction "-IN_4") (pintype "input"))
      (node (ref "R287") (pin "1") (pinfunction "1_1") (pintype "passive"))
    )
    (net (code "358") (name "Net-(IC40A-OUT)") (class "Default")
      (node (ref "IC40") (pin "2") (pinfunction "OUT_2") (pintype "open_collector"))
      (node (ref "R290") (pin "1") (pinfunction "1_1") (pintype "passive"))
    )
    (net (code "359") (name "Net-(IC40B-+IN)") (class "Default")
      (node (ref "IC40") (pin "7") (pinfunction "+IN_7") (pintype "input"))
      (node (ref "R285") (pin "1") (pinfunction "1_1") (pintype "passive"))
      (node (ref "R302") (pin "1") (pinfunction "1_1") (pintype "passive"))
    )
    (net (code "360") (name "Net-(IC40B--IN)") (class "Default")
      (node (ref "IC40") (pin "6") (pinfunction "-IN_6") (pintype "input"))
      (node (ref "IC40") (pin "8") (pinfunction "-IN_8") (pintype "input"))
      (node (ref "R284") (pin "1") (pinfunction "1_1") (pintype "passive"))
    )
    (net (code "361") (name "Net-(IC40B-OUT)") (class "Default")
      (node (ref "IC40") (pin "1") (pinfunction "OUT_1") (pintype "open_collector"))
      (node (ref "R286") (pin "2") (pinfunction "2_2") (pintype "passive"))
      (node (ref "R291") (pin "2") (pinfunction "2_2") (pintype "passive"))
    )
    (net (code "362") (name "Net-(IC40C-+IN)") (class "Default")
      (node (ref "C55") (pin "1") (pinfunction "1_1") (pintype "passive"))
      (node (ref "IC40") (pin "9") (pinfunction "+IN_9") (pintype "input"))
      (node (ref "R293") (pin "2") (pinfunction "2_2") (pintype "passive"))
      (node (ref "R302") (pin "2") (pinfunction "2_2") (pintype "passive"))
    )
    (net (code "363") (name "Net-(IC40C-OUT)") (class "Default")
      (node (ref "C56") (pin "2") (pinfunction "2_2") (pintype "passive"))
      (node (ref "IC40") (pin "14") (pinfunction "OUT_14") (pintype "open_collector"))
      (node (ref "R292") (pin "2") (pinfunction "2_2") (pintype "passive"))
    )
    (net (code "364") (name "Net-(IC40D-OUT)") (class "Default")
      (node (ref "IC40") (pin "13") (pinfunction "OUT_13") (pintype "open_collector"))
      (node (ref "JP22") (pin "1") (pinfunction "1_1") (pintype "passive"))
      (node (ref "Q49") (pin "1") (pinfunction "G_1") (pintype "passive"))
      (node (ref "R305") (pin "2") (pinfunction "2_2") (pintype "passive"))
    )
    (net (code "365") (name "Net-(IC42-CV)") (class "Default")
      (node (ref "IC42") (pin "5") (pinfunction "CV_5") (pintype "input"))
      (node (ref "R307") (pin "2") (pinfunction "2_2") (pintype "passive"))
    )
    (net (code "366") (name "Net-(IC42-Q)") (class "Default")
      (node (ref "IC42") (pin "3") (pinfunction "Q_3") (pintype "output"))
      (node (ref "IC43") (pin "12") (pinfunction "A_12") (pintype "input"))
      (node (ref "IC43") (pin "4") (pinfunction "A_4") (pintype "input"))
      (node (ref "R307") (pin "1") (pinfunction "1_1") (pintype "passive"))
    )
    (net (code "367") (name "Net-(IC43A-Q)") (class "Default")
      (node (ref "IC43") (pin "6") (pinfunction "Q_6") (pintype "output"))
      (node (ref "Q53") (pin "1") (pinfunction "G_1") (pintype "passive"))
    )
    (net (code "368") (name "Net-(IC43A-T2)") (class "Default")
      (node (ref "C61") (pin "2") (pinfunction "2_2") (pintype "passive"))
      (node (ref "IC43") (pin "2") (pinfunction "T2_2") (pintype "input"))
      (node (ref "R328") (pin "1") (pinfunction "1_1") (pintype "passive"))
    )
    (net (code "369") (name "Net-(IC43B-B)") (class "Default")
      (node (ref "IC43") (pin "11") (pinfunction "B_11") (pintype "input"))
      (node (ref "IC43") (pin "9") (pinfunction "~{Q}_9") (pintype "output"))
      (node (ref "R313") (pin "2") (pinfunction "2_2") (pintype "passive"))
    )
    (net (code "370") (name "Net-(IC43B-T2)") (class "Default")
      (node (ref "C59") (pin "1") (pinfunction "1_1") (pintype "passive"))
      (node (ref "IC43") (pin "14") (pinfunction "T2_14") (pintype "input"))
      (node (ref "R311") (pin "1") (pinfunction "1_1") (pintype "passive"))
    )
    (net (code "371") (name "Net-(IC45A-+IN)") (class "Default")
      (node (ref "C54") (pin "1") (pinfunction "1_1") (pintype "passive"))
      (node (ref "IC45") (pin "3") (pinfunction "+IN_3") (pintype "input"))
      (node (ref "R282") (pin "1") (pinfunction "1_1") (pintype "passive"))
    )
    (net (code "372") (name "Net-(IC45A--IN)") (class "Default")
      (node (ref "IC45") (pin "2") (pinfunction "-IN_2") (pintype "input"))
      (node (ref "R283") (pin "2") (pinfunction "2_2") (pintype "passive"))
    )
    (net (code "373") (name "Net-(IC45A-OUT)") (class "Default")
      (node (ref "IC45") (pin "1") (pinfunction "OUT_1") (pintype "output"))
      (node (ref "R314") (pin "2") (pinfunction "2_2") (pintype "passive"))
    )
    (net (code "374") (name "Net-(IC45B-+IN)") (class "Default")
      (node (ref "IC45") (pin "5") (pinfunction "+IN_5") (pintype "input"))
      (node (ref "Q51") (pin "3") (pinfunction "D_3") (pintype "passive"))
      (node (ref "R315") (pin "2") (pinfunction "2_2") (pintype "passive"))
      (node (ref "R316") (pin "2") (pinfunction "2_2") (pintype "passive"))
    )
    (net (code "375") (name "Net-(IC45B--IN)") (class "Default")
      (node (ref "IC45") (pin "6") (pinfunction "-IN_6") (pintype "input"))
      (node (ref "R317") (pin "1") (pinfunction "1_1") (pintype "passive"))
      (node (ref "R318") (pin "2") (pinfunction "2_2") (pintype "passive"))
    )
    (net (code "376") (name "Net-(IC45B-OUT)") (class "Default")
      (node (ref "IC45") (pin "7") (pinfunction "OUT_7") (pintype "output"))
      (node (ref "R296") (pin "2") (pinfunction "2_2") (pintype "passive"))
      (node (ref "R303") (pin "1") (pinfunction "1_1") (pintype "passive"))
      (node (ref "R316") (pin "1") (pinfunction "1_1") (pintype "passive"))
    )
    (net (code "377") (name "Net-(IC101A-+IN)") (class "Default")
      (node (ref "C101") (pin "1") (pinfunction "1_1") (pintype "passive"))
      (node (ref "IC101") (pin "3") (pinfunction "+IN_3") (pintype "input"))
      (node (ref "R105") (pin "1") (pinfunction "1_1") (pintype "passive"))
    )
    (net (code "378") (name "Net-(IC101A--IN)") (class "Default")
      (node (ref "IC101") (pin "2") (pinfunction "-IN_2") (pintype "input"))
      (node (ref "R107") (pin "2") (pinfunction "2_2") (pintype "passive"))
    )
    (net (code "379") (name "Net-(IC101A-OUT)") (class "Default")
      (node (ref "IC101") (pin "1") (pinfunction "OUT_1") (pintype "output"))
      (node (ref "R108") (pin "2") (pinfunction "2_2") (pintype "passive"))
    )
    (net (code "380") (name "Net-(IC101B-+IN)") (class "Default")
      (node (ref "IC101") (pin "5") (pinfunction "+IN_5") (pintype "input"))
      (node (ref "Q1") (pin "3") (pinfunction "D_3") (pintype "passive"))
      (node (ref "R112") (pin "2") (pinfunction "2_2") (pintype "passive"))
      (node (ref "R117") (pin "2") (pinfunction "2_2") (pintype "passive"))
    )
    (net (code "381") (name "Net-(IC101B--IN)") (class "Default")
      (node (ref "IC101") (pin "6") (pinfunction "-IN_6") (pintype "input"))
      (node (ref "R113") (pin "1") (pinfunction "1_1") (pintype "passive"))
      (node (ref "R114") (pin "2") (pinfunction "2_2") (pintype "passive"))
    )
    (net (code "382") (name "Net-(IC101B-OUT)") (class "Default")
      (node (ref "IC101") (pin "7") (pinfunction "OUT_7") (pintype "output"))
      (node (ref "R115") (pin "2") (pinfunction "2_2") (pintype "passive"))
      (node (ref "R116") (pin "1") (pinfunction "1_1") (pintype "passive"))
      (node (ref "R117") (pin "1") (pinfunction "1_1") (pintype "passive"))
    )
    (net (code "383") (name "Net-(IC105A-A)") (class "Default")
      (node (ref "IC105") (pin "10") (pinfunction "A_10") (pintype "input"))
      (node (ref "R111") (pin "1") (pinfunction "1_1") (pintype "passive"))
      (node (ref "R3") (pin "1") (pinfunction "1_1") (pintype "passive"))
      (node (ref "R3") (pin "2") (pinfunction "2_2") (pintype "passive"))
      (node (ref "X101") (pin "4") (pinfunction "4_4") (pintype "passive"))
      (node (ref "X103") (pin "2") (pinfunction "S_2") (pintype "passive"))
    )
    (net (code "384") (name "Net-(IC105A-B)") (class "Default")
      (node (ref "IC105") (pin "13") (pinfunction "B_13") (pintype "input"))
      (node (ref "R110") (pin "1") (pinfunction "1_1") (pintype "passive"))
      (node (ref "R2") (pin "1") (pinfunction "1_1") (pintype "passive"))
      (node (ref "R2") (pin "2") (pinfunction "2_2") (pintype "passive"))
      (node (ref "X101") (pin "3") (pinfunction "3_3") (pintype "passive"))
      (node (ref "X103") (pin "3") (pinfunction "S_3") (pintype "passive"))
    )
    (net (code "385") (name "Net-(IC105A-C)") (class "Default")
      (node (ref "IC105") (pin "12") (pinfunction "C_12") (pintype "input"))
      (node (ref "R1") (pin "1") (pinfunction "1_1") (pintype "passive"))
      (node (ref "R1") (pin "2") (pinfunction "2_2") (pintype "passive"))
      (node (ref "R109") (pin "1") (pinfunction "1_1") (pintype "passive"))
      (node (ref "X101") (pin "2") (pinfunction "2_2") (pintype "passive"))
      (node (ref "X103") (pin "4") (pinfunction "S_4") (pintype "passive"))
    )
    (net (code "386") (name "Net-(IC105A-Q0)") (class "Default")
      (node (ref "IC105") (pin "3") (pinfunction "Q0_3") (pintype "output"))
      (node (ref "IC107") (pin "1") (pinfunction "I1_1") (pintype "input"))
      (node (ref "IC107") (pin "2") (pinfunction "I2_2") (pintype "input"))
      (node (ref "Q1") (pin "1") (pinfunction "G_1") (pintype "passive"))
      (node (ref "Q106") (pin "1") (pinfunction "G_1") (pintype "passive"))
    )
    (net (code "387") (name "Net-(IC105A-Q1)") (class "Default")
      (node (ref "IC105") (pin "14") (pinfunction "Q1_14") (pintype "output"))
      (node (ref "IC107") (pin "6") (pinfunction "I6_6") (pintype "input"))
    )
    (net (code "388") (name "Net-(IC105A-Q2)") (class "Default")
      (node (ref "IC105") (pin "2") (pinfunction "Q2_2") (pintype "output"))
      (node (ref "IC107") (pin "7") (pinfunction "I7_7") (pintype "input"))
    )
    (net (code "389") (name "Net-(IC105A-Q3)") (class "Default")
      (node (ref "IC105") (pin "15") (pinfunction "Q3_15") (pintype "output"))
      (node (ref "IC107") (pin "5") (pinfunction "I5_5") (pintype "input"))
    )
    (net (code "390") (name "Net-(IC105A-Q4)") (class "Default")
      (node (ref "IC105") (pin "1") (pinfunction "Q4_1") (pintype "output"))
      (node (ref "IC107") (pin "4") (pinfunction "I4_4") (pintype "input"))
    )
    (net (code "391") (name "Net-(IC105A-Q5)") (class "Default")
      (node (ref "IC105") (pin "6") (pinfunction "Q5_6") (pintype "output"))
      (node (ref "IC107") (pin "3") (pinfunction "I3_3") (pintype "input"))
    )
    (net (code "392") (name "Net-(IC107-O1)") (class "Default")
      (node (ref "IC107") (pin "16") (pinfunction "O1_16") (pintype "open_collector"))
      (node (ref "Q106") (pin "3") (pinfunction "D_3") (pintype "passive"))
      (node (ref "R9") (pin "1") (pinfunction "1_1") (pintype "passive"))
    )
    (net (code "393") (name "Net-(IC107-O2)") (class "Default")
      (node (ref "IC107") (pin "15") (pinfunction "O2_15") (pintype "open_collector"))
      (node (ref "R128") (pin "1") (pinfunction "1_1") (pintype "passive"))
    )
    (net (code "394") (name "Net-(IC108A-+IN)") (class "Default")
      (node (ref "IC108") (pin "11") (pinfunction "+IN_11") (pintype "input"))
      (node (ref "IC108") (pin "5") (pinfunction "+IN_5") (pintype "input"))
      (node (ref "R131") (pin "1") (pinfunction "1_1") (pintype "passive"))
      (node (ref "R132") (pin "2") (pinfunction "2_2") (pintype "passive"))
      (node (ref "R133") (pin "2") (pinfunction "2_2") (pintype "passive"))
    )
    (net (code "395") (name "Net-(IC108A--IN)") (class "Default")
      (node (ref "C108") (pin "1") (pinfunction "1_1") (pintype "passive"))
      (node (ref "IC108") (pin "10") (pinfunction "-IN_10") (pintype "input"))
      (node (ref "IC108") (pin "4") (pinfunction "-IN_4") (pintype "input"))
      (node (ref "R130") (pin "1") (pinfunction "1_1") (pintype "passive"))
    )
    (net (code "396") (name "Net-(IC108A-OUT)") (class "Default")
      (node (ref "IC108") (pin "2") (pinfunction "OUT_2") (pintype "open_collector"))
      (node (ref "R133") (pin "1") (pinfunction "1_1") (pintype "passive"))
    )
    (net (code "397") (name "Net-(IC108B-+IN)") (class "Default")
      (node (ref "IC108") (pin "7") (pinfunction "+IN_7") (pintype "input"))
      (node (ref "R121") (pin "1") (pinfunction "1_1") (pintype "passive"))
      (node (ref "R122") (pin "1") (pinfunction "1_1") (pintype "passive"))
    )
    (net (code "398") (name "Net-(IC108B--IN)") (class "Default")
      (node (ref "IC108") (pin "6") (pinfunction "-IN_6") (pintype "input"))
      (node (ref "IC108") (pin "8") (pinfunction "-IN_8") (pintype "input"))
      (node (ref "R120") (pin "1") (pinfunction "1_1") (pintype "passive"))
    )
    (net (code "399") (name "Net-(IC108B-OUT)") (class "Default")
      (node (ref "IC108") (pin "1") (pinfunction "OUT_1") (pintype "open_collector"))
      (node (ref "R124") (pin "2") (pinfunction "2_2") (pintype "passive"))
      (node (ref "R125") (pin "2") (pinfunction "2_2") (pintype "passive"))
    )
    (net (code "400") (name "Net-(IC108C-+IN)") (class "Default")
      (node (ref "C105") (pin "1") (pinfunction "1_1") (pintype "passive"))
      (node (ref "IC108") (pin "9") (pinfunction "+IN_9") (pintype "input"))
      (node (ref "R122") (pin "2") (pinfunction "2_2") (pintype "passive"))
      (node (ref "R123") (pin "2") (pinfunction "2_2") (pintype "passive"))
    )
    (net (code "401") (name "Net-(IC108C-OUT)") (class "Default")
      (node (ref "C106") (pin "2") (pinfunction "2_2") (pintype "passive"))
      (node (ref "IC108") (pin "14") (pinfunction "OUT_14") (pintype "open_collector"))
      (node (ref "R126") (pin "2") (pinfunction "2_2") (pintype "passive"))
    )
    (net (code "402") (name "Net-(IC108D-OUT)") (class "Default")
      (node (ref "IC108") (pin "13") (pinfunction "OUT_13") (pintype "open_collector"))
      (node (ref "JP105") (pin "1") (pinfunction "1_1") (pintype "passive"))
      (node (ref "Q107") (pin "1") (pinfunction "G_1") (pintype "passive"))
      (node (ref "R135") (pin "2") (pinfunction "2_2") (pintype "passive"))
    )
    (net (code "403") (name "Net-(IC109-ADJ)") (class "Default")
      (node (ref "IC109") (pin "1") (pinfunction "ADJ_1") (pintype "input"))
      (node (ref "R120") (pin "2") (pinfunction "2_2") (pintype "passive"))
      (node (ref "R134") (pin "1") (pinfunction "1_1") (pintype "passive"))
      (node (ref "X101") (pin "7") (pinfunction "7_7") (pintype "passive"))
    )
    (net (code "404") (name "Net-(IC109-VI)") (class "Default")
      (node (ref "IC109") (pin "3") (pinfunction "VI_3") (pintype "input"))
      (node (ref "Q105") (pin "2") (pinfunction "C_2") (pintype "passive"))
    )
    (net (code "405") (name "Net-(IC109-VO)") (class "Default")
      (node (ref "IC109") (pin "2") (pinfunction "VO_2") (pintype "passive"))
      (node (ref "R134") (pin "2") (pinfunction "2_2") (pintype "passive"))
    )
    (net (code "406") (name "Net-(IC110-CV)") (class "Default")
      (node (ref "IC110") (pin "5") (pinfunction "CV_5") (pintype "input"))
      (node (ref "R144") (pin "2") (pinfunction "2_2") (pintype "passive"))
    )
    (net (code "407") (name "Net-(IC110-Q)") (class "Default")
      (node (ref "IC110") (pin "3") (pinfunction "Q_3") (pintype "output"))
      (node (ref "IC111") (pin "12") (pinfunction "A_12") (pintype "input"))
      (node (ref "IC111") (pin "4") (pinfunction "A_4") (pintype "input"))
      (node (ref "R144") (pin "1") (pinfunction "1_1") (pintype "passive"))
    )
    (net (code "408") (name "Net-(IC111A-Q)") (class "Default")
      (node (ref "IC111") (pin "6") (pinfunction "Q_6") (pintype "output"))
      (node (ref "Q3") (pin "1") (pinfunction "G_1") (pintype "passive"))
    )
    (net (code "409") (name "Net-(IC111A-T2)") (class "Default")
      (node (ref "C15") (pin "2") (pinfunction "2_2") (pintype "passive"))
      (node (ref "IC111") (pin "2") (pinfunction "T2_2") (pintype "input"))
      (node (ref "R10") (pin "1") (pinfunction "1_1") (pintype "passive"))
    )
    (net (code "410") (name "Net-(IC111B-B)") (class "Default")
      (node (ref "IC111") (pin "11") (pinfunction "B_11") (pintype "input"))
      (node (ref "IC111") (pin "9") (pinfunction "~{Q}_9") (pintype "output"))
      (node (ref "R146") (pin "2") (pinfunction "2_2") (pintype "passive"))
    )
    (net (code "411") (name "Net-(IC111B-T2)") (class "Default")
      (node (ref "C110") (pin "1") (pinfunction "1_1") (pintype "passive"))
      (node (ref "IC111") (pin "14") (pinfunction "T2_14") (pintype "input"))
      (node (ref "R145") (pin "1") (pinfunction "1_1") (pintype "passive"))
    )
    (net (code "412") (name "Net-(JP1-Pad1)") (class "Default")
      (node (ref "JP1") (pin "1") (pinfunction "1_1") (pintype "passive"))
      (node (ref "R48") (pin "2") (pinfunction "2_2") (pintype "passive"))
    )
    (net (code "413") (name "Net-(JP2-Pad3)") (class "Default")
      (node (ref "JP2") (pin "3") (pinfunction "3_3") (pintype "passive"))
      (node (ref "R40") (pin "1") (pinfunction "1_1") (pintype "passive"))
    )
    (net (code "414") (name "Net-(JP5-Pad2)") (class "Default")
      (node (ref "JP5") (pin "2") (pinfunction "2_2") (pintype "passive"))
      (node (ref "R45") (pin "2") (pinfunction "2_2") (pintype "passive"))
      (node (ref "R46") (pin "2") (pinfunction "2_2") (pintype "passive"))
      (node (ref "SJ1") (pin "2") (pinfunction "2_2") (pintype "passive"))
    )
    (net (code "415") (name "Net-(JP6-Pad1)") (class "Default")
      (node (ref "JP6") (pin "1") (pinfunction "1_1") (pintype "passive"))
      (node (ref "R147") (pin "2") (pinfunction "2_2") (pintype "passive"))
    )
    (net (code "416") (name "Net-(JP7-Pad3)") (class "Default")
      (node (ref "JP7") (pin "3") (pinfunction "3_3") (pintype "passive"))
      (node (ref "R95") (pin "1") (pinfunction "1_1") (pintype "passive"))
    )
    (net (code "417") (name "Net-(JP10-Pad2)") (class "Default")
      (node (ref "JP10") (pin "2") (pinfunction "2_2") (pintype "passive"))
      (node (ref "R100") (pin "2") (pinfunction "2_2") (pintype "passive"))
      (node (ref "R118") (pin "2") (pinfunction "2_2") (pintype "passive"))
      (node (ref "SJ2") (pin "2") (pinfunction "2_2") (pintype "passive"))
    )
    (net (code "418") (name "Net-(JP11-Pad1)") (class "Default")
      (node (ref "JP11") (pin "1") (pinfunction "1_1") (pintype "passive"))
      (node (ref "R202") (pin "2") (pinfunction "2_2") (pintype "passive"))
    )
    (net (code "419") (name "Net-(JP12-Pad3)") (class "Default")
      (node (ref "JP12") (pin "3") (pinfunction "3_3") (pintype "passive"))
      (node (ref "R194") (pin "1") (pinfunction "1_1") (pintype "passive"))
    )
    (net (code "420") (name "Net-(JP15-Pad2)") (class "Default")
      (node (ref "JP15") (pin "2") (pinfunction "2_2") (pintype "passive"))
      (node (ref "R199") (pin "2") (pinfunction "2_2") (pintype "passive"))
      (node (ref "R200") (pin "2") (pinfunction "2_2") (pintype "passive"))
      (node (ref "SJ3") (pin "2") (pinfunction "2_2") (pintype "passive"))
    )
    (net (code "421") (name "Net-(JP16-Pad1)") (class "Default")
      (node (ref "JP16") (pin "1") (pinfunction "1_1") (pintype "passive"))
      (node (ref "R257") (pin "2") (pinfunction "2_2") (pintype "passive"))
    )
    (net (code "422") (name "Net-(JP17-Pad3)") (class "Default")
      (node (ref "JP17") (pin "3") (pinfunction "3_3") (pintype "passive"))
      (node (ref "R249") (pin "1") (pinfunction "1_1") (pintype "passive"))
    )
    (net (code "423") (name "Net-(JP20-Pad2)") (class "Default")
      (node (ref "JP20") (pin "2") (pinfunction "2_2") (pintype "passive"))
      (node (ref "R254") (pin "2") (pinfunction "2_2") (pintype "passive"))
      (node (ref "R255") (pin "2") (pinfunction "2_2") (pintype "passive"))
      (node (ref "SJ4") (pin "2") (pinfunction "2_2") (pintype "passive"))
    )
    (net (code "424") (name "Net-(JP21-Pad1)") (class "Default")
      (node (ref "JP21") (pin "1") (pinfunction "1_1") (pintype "passive"))
      (node (ref "R312") (pin "2") (pinfunction "2_2") (pintype "passive"))
    )
    (net (code "425") (name "Net-(JP22-Pad3)") (class "Default")
      (node (ref "JP22") (pin "3") (pinfunction "3_3") (pintype "passive"))
      (node (ref "R304") (pin "1") (pinfunction "1_1") (pintype "passive"))
    )
    (net (code "426") (name "Net-(JP25-Pad2)") (class "Default")
      (node (ref "JP25") (pin "2") (pinfunction "2_2") (pintype "passive"))
      (node (ref "R309") (pin "2") (pinfunction "2_2") (pintype "passive"))
      (node (ref "R310") (pin "2") (pinfunction "2_2") (pintype "passive"))
      (node (ref "SJ5") (pin "2") (pinfunction "2_2") (pintype "passive"))
    )
    (net (code "427") (name "Net-(JP101-Pad1)") (class "Default")
      (node (ref "JP101") (pin "1") (pinfunction "1_1") (pintype "passive"))
      (node (ref "R119") (pin "2") (pinfunction "2_2") (pintype "passive"))
    )
    (net (code "428") (name "Net-(JP104-Pad2)") (class "Default")
      (node (ref "JP104") (pin "2") (pinfunction "2_2") (pintype "passive"))
      (node (ref "R136") (pin "2") (pinfunction "2_2") (pintype "passive"))
      (node (ref "R137") (pin "2") (pinfunction "2_2") (pintype "passive"))
      (node (ref "SJ101") (pin "2") (pinfunction "2_2") (pintype "passive"))
    )
    (net (code "429") (name "Net-(JP105-Pad3)") (class "Default")
      (node (ref "JP105") (pin "3") (pinfunction "3_3") (pintype "passive"))
      (node (ref "R138") (pin "1") (pinfunction "1_1") (pintype "passive"))
    )
    (net (code "430") (name "Net-(LED1-PadA)") (class "Default")
      (node (ref "LED1") (pin "A") (pinfunction "A_A") (pintype "passive"))
      (node (ref "LED2") (pin "A") (pinfunction "A_A") (pintype "passive"))
      (node (ref "LED3") (pin "A") (pinfunction "A_A") (pintype "passive"))
      (node (ref "LED4") (pin "A") (pinfunction "A_A") (pintype "passive"))
      (node (ref "LED6") (pin "A") (pinfunction "A_A") (pintype "passive"))
      (node (ref "R34") (pin "1") (pinfunction "1_1") (pintype "passive"))
    )
    (net (code "431") (name "Net-(LED5-C)") (class "Default")
      (node (ref "LED5") (pin "K") (pinfunction "C_K") (pintype "passive"))
      (node (ref "R33") (pin "1") (pinfunction "1_1") (pintype "passive"))
    )
    (net (code "432") (name "Net-(LED10-PadA)") (class "Default")
      (node (ref "LED10") (pin "A") (pinfunction "A_A") (pintype "passive"))
      (node (ref "LED12") (pin "A") (pinfunction "A_A") (pintype "passive"))
      (node (ref "LED7") (pin "A") (pinfunction "A_A") (pintype "passive"))
      (node (ref "LED8") (pin "A") (pinfunction "A_A") (pintype "passive"))
      (node (ref "LED9") (pin "A") (pinfunction "A_A") (pintype "passive"))
      (node (ref "R89") (pin "1") (pinfunction "1_1") (pintype "passive"))
    )
    (net (code "433") (name "Net-(LED11-C)") (class "Default")
      (node (ref "LED11") (pin "K") (pinfunction "C_K") (pintype "passive"))
      (node (ref "R88") (pin "1") (pinfunction "1_1") (pintype "passive"))
    )
    (net (code "434") (name "Net-(LED13-PadA)") (class "Default")
      (node (ref "LED13") (pin "A") (pinfunction "A_A") (pintype "passive"))
      (node (ref "LED14") (pin "A") (pinfunction "A_A") (pintype "passive"))
      (node (ref "LED15") (pin "A") (pinfunction "A_A") (pintype "passive"))
      (node (ref "LED16") (pin "A") (pinfunction "A_A") (pintype "passive"))
      (node (ref "LED18") (pin "A") (pinfunction "A_A") (pintype "passive"))
      (node (ref "R188") (pin "1") (pinfunction "1_1") (pintype "passive"))
    )
    (net (code "435") (name "Net-(LED17-C)") (class "Default")
      (node (ref "LED17") (pin "K") (pinfunction "C_K") (pintype "passive"))
      (node (ref "R187") (pin "1") (pinfunction "1_1") (pintype "passive"))
    )
    (net (code "436") (name "Net-(LED19-PadA)") (class "Default")
      (node (ref "LED19") (pin "A") (pinfunction "A_A") (pintype "passive"))
      (node (ref "LED20") (pin "A") (pinfunction "A_A") (pintype "passive"))
      (node (ref "LED21") (pin "A") (pinfunction "A_A") (pintype "passive"))
      (node (ref "LED22") (pin "A") (pinfunction "A_A") (pintype "passive"))
      (node (ref "LED24") (pin "A") (pinfunction "A_A") (pintype "passive"))
      (node (ref "R243") (pin "1") (pinfunction "1_1") (pintype "passive"))
    )
    (net (code "437") (name "Net-(LED23-C)") (class "Default")
      (node (ref "LED23") (pin "K") (pinfunction "C_K") (pintype "passive"))
      (node (ref "R242") (pin "1") (pinfunction "1_1") (pintype "passive"))
    )
    (net (code "438") (name "Net-(LED25-PadA)") (class "Default")
      (node (ref "LED25") (pin "A") (pinfunction "A_A") (pintype "passive"))
      (node (ref "LED26") (pin "A") (pinfunction "A_A") (pintype "passive"))
      (node (ref "LED27") (pin "A") (pinfunction "A_A") (pintype "passive"))
      (node (ref "LED28") (pin "A") (pinfunction "A_A") (pintype "passive"))
      (node (ref "LED30") (pin "A") (pinfunction "A_A") (pintype "passive"))
      (node (ref "R298") (pin "1") (pinfunction "1_1") (pintype "passive"))
    )
    (net (code "439") (name "Net-(LED29-C)") (class "Default")
      (node (ref "LED29") (pin "K") (pinfunction "C_K") (pintype "passive"))
      (node (ref "R297") (pin "1") (pinfunction "1_1") (pintype "passive"))
    )
    (net (code "440") (name "Net-(LED101-C)") (class "Default")
      (node (ref "LED101") (pin "K") (pinfunction "C_K") (pintype "passive"))
      (node (ref "R143") (pin "1") (pinfunction "1_1") (pintype "passive"))
    )
    (net (code "441") (name "Net-(LED102-PadA)") (class "Default")
      (node (ref "LED102") (pin "A") (pinfunction "A_A") (pintype "passive"))
      (node (ref "LED103") (pin "A") (pinfunction "A_A") (pintype "passive"))
      (node (ref "LED104") (pin "A") (pinfunction "A_A") (pintype "passive"))
      (node (ref "LED105") (pin "A") (pinfunction "A_A") (pintype "passive"))
      (node (ref "LED106") (pin "A") (pinfunction "A_A") (pintype "passive"))
      (node (ref "R142") (pin "1") (pinfunction "1_1") (pintype "passive"))
    )
    (net (code "442") (name "Net-(Q2-B)") (class "Default")
      (node (ref "Q2") (pin "1") (pinfunction "B_1") (pintype "passive"))
      (node (ref "R8") (pin "1") (pinfunction "1_1") (pintype "passive"))
    )
    (net (code "443") (name "Net-(Q2-C)") (class "Default")
      (node (ref "Q2") (pin "2") (pinfunction "C_2") (pintype "passive"))
      (node (ref "R129") (pin "2") (pinfunction "2_2") (pintype "passive"))
      (node (ref "SJMP") (pin "2") (pinfunction "2_2") (pintype "passive"))
    )
    (net (code "444") (name "Net-(Q3-D)") (class "Default")
      (node (ref "Q3") (pin "3") (pinfunction "D_3") (pintype "passive"))
      (node (ref "R8") (pin "2") (pinfunction "2_2") (pintype "passive"))
    )
    (net (code "445") (name "Net-(Q4-B)") (class "Default")
      (node (ref "Q4") (pin "1") (pinfunction "B_1") (pintype "passive"))
      (node (ref "R35") (pin "2") (pinfunction "2_2") (pintype "passive"))
    )
    (net (code "446") (name "Net-(Q5-B)") (class "Default")
      (node (ref "Q5") (pin "1") (pinfunction "B_1") (pintype "passive"))
      (node (ref "Q5") (pin "2") (pinfunction "C_2") (pintype "passive"))
      (node (ref "Q6") (pin "1") (pinfunction "B_1") (pintype "passive"))
      (node (ref "R30") (pin "1") (pinfunction "1_1") (pintype "passive"))
      (node (ref "R31") (pin "1") (pinfunction "1_1") (pintype "passive"))
      (node (ref "R55") (pin "1") (pinfunction "1_1") (pintype "passive"))
      (node (ref "X3") (pin "2") (pinfunction "S_2") (pintype "passive"))
    )
    (net (code "447") (name "Net-(Q5-E)") (class "Default")
      (node (ref "Q5") (pin "3") (pinfunction "E_3") (pintype "passive"))
      (node (ref "R36") (pin "2") (pinfunction "2_2") (pintype "passive"))
    )
    (net (code "448") (name "Net-(Q6-E)") (class "Default")
      (node (ref "Q6") (pin "3") (pinfunction "E_3") (pintype "passive"))
      (node (ref "R37") (pin "2") (pinfunction "2_2") (pintype "passive"))
    )
    (net (code "449") (name "Net-(Q7-B)") (class "Default")
      (node (ref "Q7") (pin "1") (pinfunction "B_1") (pintype "passive"))
      (node (ref "R28") (pin "1") (pinfunction "1_1") (pintype "passive"))
    )
    (net (code "450") (name "Net-(Q8-B)") (class "Default")
      (node (ref "Q8") (pin "1") (pinfunction "B_1") (pintype "passive"))
      (node (ref "R39") (pin "2") (pinfunction "2_2") (pintype "passive"))
      (node (ref "R60") (pin "1") (pinfunction "1_1") (pintype "passive"))
    )
    (net (code "451") (name "Net-(Q8-E)") (class "Default")
      (node (ref "Q8") (pin "3") (pinfunction "E_3") (pintype "passive"))
      (node (ref "R59") (pin "1") (pinfunction "1_1") (pintype "passive"))
    )
    (net (code "452") (name "Net-(Q9-D)") (class "Default")
      (node (ref "Q9") (pin "3") (pinfunction "D_3") (pintype "passive"))
      (node (ref "R40") (pin "2") (pinfunction "2_2") (pintype "passive"))
    )
    (net (code "453") (name "Net-(Q10-S)") (class "Default")
      (node (ref "Q10") (pin "2") (pinfunction "S_2") (pintype "passive"))
      (node (ref "R61") (pin "2") (pinfunction "2_2") (pintype "passive"))
    )
    (net (code "454") (name "Net-(Q12-B)") (class "Default")
      (node (ref "Q12") (pin "1") (pinfunction "B_1") (pintype "passive"))
      (node (ref "R63") (pin "1") (pinfunction "1_1") (pintype "passive"))
    )
    (net (code "455") (name "Net-(Q12-C)") (class "Default")
      (node (ref "Q12") (pin "2") (pinfunction "C_2") (pintype "passive"))
      (node (ref "R14") (pin "2") (pinfunction "2_2") (pintype "passive"))
      (node (ref "SJMP1") (pin "2") (pinfunction "2_2") (pintype "passive"))
    )
    (net (code "456") (name "Net-(Q13-D)") (class "Default")
      (node (ref "Q13") (pin "3") (pinfunction "D_3") (pintype "passive"))
      (node (ref "R63") (pin "2") (pinfunction "2_2") (pintype "passive"))
    )
    (net (code "457") (name "Net-(Q14-B)") (class "Default")
      (node (ref "Q14") (pin "1") (pinfunction "B_1") (pintype "passive"))
      (node (ref "R90") (pin "2") (pinfunction "2_2") (pintype "passive"))
    )
    (net (code "458") (name "Net-(Q15-B)") (class "Default")
      (node (ref "Q15") (pin "1") (pinfunction "B_1") (pintype "passive"))
      (node (ref "Q15") (pin "2") (pinfunction "C_2") (pintype "passive"))
      (node (ref "Q16") (pin "1") (pinfunction "B_1") (pintype "passive"))
      (node (ref "R154") (pin "1") (pinfunction "1_1") (pintype "passive"))
      (node (ref "R85") (pin "1") (pinfunction "1_1") (pintype "passive"))
      (node (ref "R86") (pin "1") (pinfunction "1_1") (pintype "passive"))
      (node (ref "X6") (pin "2") (pinfunction "S_2") (pintype "passive"))
    )
    (net (code "459") (name "Net-(Q15-E)") (class "Default")
      (node (ref "Q15") (pin "3") (pinfunction "E_3") (pintype "passive"))
      (node (ref "R91") (pin "2") (pinfunction "2_2") (pintype "passive"))
    )
    (net (code "460") (name "Net-(Q16-E)") (class "Default")
      (node (ref "Q16") (pin "3") (pinfunction "E_3") (pintype "passive"))
      (node (ref "R92") (pin "2") (pinfunction "2_2") (pintype "passive"))
    )
    (net (code "461") (name "Net-(Q17-B)") (class "Default")
      (node (ref "Q17") (pin "1") (pinfunction "B_1") (pintype "passive"))
      (node (ref "R83") (pin "1") (pinfunction "1_1") (pintype "passive"))
    )
    (net (code "462") (name "Net-(Q18-B)") (class "Default")
      (node (ref "Q18") (pin "1") (pinfunction "B_1") (pintype "passive"))
      (node (ref "R159") (pin "1") (pinfunction "1_1") (pintype "passive"))
      (node (ref "R94") (pin "2") (pinfunction "2_2") (pintype "passive"))
    )
    (net (code "463") (name "Net-(Q18-E)") (class "Default")
      (node (ref "Q18") (pin "3") (pinfunction "E_3") (pintype "passive"))
      (node (ref "R158") (pin "1") (pinfunction "1_1") (pintype "passive"))
    )
    (net (code "464") (name "Net-(Q19-D)") (class "Default")
      (node (ref "Q19") (pin "3") (pinfunction "D_3") (pintype "passive"))
      (node (ref "R95") (pin "2") (pinfunction "2_2") (pintype "passive"))
    )
    (net (code "465") (name "Net-(Q20-S)") (class "Default")
      (node (ref "Q20") (pin "2") (pinfunction "S_2") (pintype "passive"))
      (node (ref "R160") (pin "2") (pinfunction "2_2") (pintype "passive"))
    )
    (net (code "466") (name "Net-(Q22-B)") (class "Default")
      (node (ref "Q22") (pin "1") (pinfunction "B_1") (pintype "passive"))
      (node (ref "R162") (pin "1") (pinfunction "1_1") (pintype "passive"))
    )
    (net (code "467") (name "Net-(Q22-C)") (class "Default")
      (node (ref "Q22") (pin "2") (pinfunction "C_2") (pintype "passive"))
      (node (ref "R69") (pin "2") (pinfunction "2_2") (pintype "passive"))
      (node (ref "SJMP2") (pin "2") (pinfunction "2_2") (pintype "passive"))
    )
    (net (code "468") (name "Net-(Q23-D)") (class "Default")
      (node (ref "Q23") (pin "3") (pinfunction "D_3") (pintype "passive"))
      (node (ref "R162") (pin "2") (pinfunction "2_2") (pintype "passive"))
    )
    (net (code "469") (name "Net-(Q24-B)") (class "Default")
      (node (ref "Q24") (pin "1") (pinfunction "B_1") (pintype "passive"))
      (node (ref "R189") (pin "2") (pinfunction "2_2") (pintype "passive"))
    )
    (net (code "470") (name "Net-(Q25-B)") (class "Default")
      (node (ref "Q25") (pin "1") (pinfunction "B_1") (pintype "passive"))
      (node (ref "Q25") (pin "2") (pinfunction "C_2") (pintype "passive"))
      (node (ref "Q26") (pin "1") (pinfunction "B_1") (pintype "passive"))
      (node (ref "R184") (pin "1") (pinfunction "1_1") (pintype "passive"))
      (node (ref "R185") (pin "1") (pinfunction "1_1") (pintype "passive"))
      (node (ref "R209") (pin "1") (pinfunction "1_1") (pintype "passive"))
      (node (ref "X9") (pin "2") (pinfunction "S_2") (pintype "passive"))
    )
    (net (code "471") (name "Net-(Q25-E)") (class "Default")
      (node (ref "Q25") (pin "3") (pinfunction "E_3") (pintype "passive"))
      (node (ref "R190") (pin "2") (pinfunction "2_2") (pintype "passive"))
    )
    (net (code "472") (name "Net-(Q26-E)") (class "Default")
      (node (ref "Q26") (pin "3") (pinfunction "E_3") (pintype "passive"))
      (node (ref "R191") (pin "2") (pinfunction "2_2") (pintype "passive"))
    )
    (net (code "473") (name "Net-(Q27-B)") (class "Default")
      (node (ref "Q27") (pin "1") (pinfunction "B_1") (pintype "passive"))
      (node (ref "R182") (pin "1") (pinfunction "1_1") (pintype "passive"))
    )
    (net (code "474") (name "Net-(Q28-B)") (class "Default")
      (node (ref "Q28") (pin "1") (pinfunction "B_1") (pintype "passive"))
      (node (ref "R193") (pin "2") (pinfunction "2_2") (pintype "passive"))
      (node (ref "R214") (pin "1") (pinfunction "1_1") (pintype "passive"))
    )
    (net (code "475") (name "Net-(Q28-E)") (class "Default")
      (node (ref "Q28") (pin "3") (pinfunction "E_3") (pintype "passive"))
      (node (ref "R213") (pin "1") (pinfunction "1_1") (pintype "passive"))
    )
    (net (code "476") (name "Net-(Q29-D)") (class "Default")
      (node (ref "Q29") (pin "3") (pinfunction "D_3") (pintype "passive"))
      (node (ref "R194") (pin "2") (pinfunction "2_2") (pintype "passive"))
    )
    (net (code "477") (name "Net-(Q30-S)") (class "Default")
      (node (ref "Q30") (pin "2") (pinfunction "S_2") (pintype "passive"))
      (node (ref "R215") (pin "2") (pinfunction "2_2") (pintype "passive"))
    )
    (net (code "478") (name "Net-(Q32-B)") (class "Default")
      (node (ref "Q32") (pin "1") (pinfunction "B_1") (pintype "passive"))
      (node (ref "R217") (pin "1") (pinfunction "1_1") (pintype "passive"))
    )
    (net (code "479") (name "Net-(Q32-C)") (class "Default")
      (node (ref "Q32") (pin "2") (pinfunction "C_2") (pintype "passive"))
      (node (ref "R168") (pin "2") (pinfunction "2_2") (pintype "passive"))
      (node (ref "SJMP3") (pin "2") (pinfunction "2_2") (pintype "passive"))
    )
    (net (code "480") (name "Net-(Q33-D)") (class "Default")
      (node (ref "Q33") (pin "3") (pinfunction "D_3") (pintype "passive"))
      (node (ref "R217") (pin "2") (pinfunction "2_2") (pintype "passive"))
    )
    (net (code "481") (name "Net-(Q34-B)") (class "Default")
      (node (ref "Q34") (pin "1") (pinfunction "B_1") (pintype "passive"))
      (node (ref "R244") (pin "2") (pinfunction "2_2") (pintype "passive"))
    )
    (net (code "482") (name "Net-(Q35-B)") (class "Default")
      (node (ref "Q35") (pin "1") (pinfunction "B_1") (pintype "passive"))
      (node (ref "Q35") (pin "2") (pinfunction "C_2") (pintype "passive"))
      (node (ref "Q36") (pin "1") (pinfunction "B_1") (pintype "passive"))
      (node (ref "R239") (pin "1") (pinfunction "1_1") (pintype "passive"))
      (node (ref "R240") (pin "1") (pinfunction "1_1") (pintype "passive"))
      (node (ref "R264") (pin "1") (pinfunction "1_1") (pintype "passive"))
      (node (ref "X12") (pin "2") (pinfunction "S_2") (pintype "passive"))
    )
    (net (code "483") (name "Net-(Q35-E)") (class "Default")
      (node (ref "Q35") (pin "3") (pinfunction "E_3") (pintype "passive"))
      (node (ref "R245") (pin "2") (pinfunction "2_2") (pintype "passive"))
    )
    (net (code "484") (name "Net-(Q36-E)") (class "Default")
      (node (ref "Q36") (pin "3") (pinfunction "E_3") (pintype "passive"))
      (node (ref "R246") (pin "2") (pinfunction "2_2") (pintype "passive"))
    )
    (net (code "485") (name "Net-(Q37-B)") (class "Default")
      (node (ref "Q37") (pin "1") (pinfunction "B_1") (pintype "passive"))
      (node (ref "R237") (pin "1") (pinfunction "1_1") (pintype "passive"))
    )
    (net (code "486") (name "Net-(Q38-B)") (class "Default")
      (node (ref "Q38") (pin "1") (pinfunction "B_1") (pintype "passive"))
      (node (ref "R248") (pin "2") (pinfunction "2_2") (pintype "passive"))
      (node (ref "R269") (pin "1") (pinfunction "1_1") (pintype "passive"))
    )
    (net (code "487") (name "Net-(Q38-E)") (class "Default")
      (node (ref "Q38") (pin "3") (pinfunction "E_3") (pintype "passive"))
      (node (ref "R268") (pin "1") (pinfunction "1_1") (pintype "passive"))
    )
    (net (code "488") (name "Net-(Q39-D)") (class "Default")
      (node (ref "Q39") (pin "3") (pinfunction "D_3") (pintype "passive"))
      (node (ref "R249") (pin "2") (pinfunction "2_2") (pintype "passive"))
    )
    (net (code "489") (name "Net-(Q40-S)") (class "Default")
      (node (ref "Q40") (pin "2") (pinfunction "S_2") (pintype "passive"))
      (node (ref "R270") (pin "2") (pinfunction "2_2") (pintype "passive"))
    )
    (net (code "490") (name "Net-(Q42-B)") (class "Default")
      (node (ref "Q42") (pin "1") (pinfunction "B_1") (pintype "passive"))
      (node (ref "R272") (pin "1") (pinfunction "1_1") (pintype "passive"))
    )
    (net (code "491") (name "Net-(Q42-C)") (class "Default")
      (node (ref "Q42") (pin "2") (pinfunction "C_2") (pintype "passive"))
      (node (ref "R223") (pin "2") (pinfunction "2_2") (pintype "passive"))
      (node (ref "SJMP4") (pin "2") (pinfunction "2_2") (pintype "passive"))
    )
    (net (code "492") (name "Net-(Q43-D)") (class "Default")
      (node (ref "Q43") (pin "3") (pinfunction "D_3") (pintype "passive"))
      (node (ref "R272") (pin "2") (pinfunction "2_2") (pintype "passive"))
    )
    (net (code "493") (name "Net-(Q44-B)") (class "Default")
      (node (ref "Q44") (pin "1") (pinfunction "B_1") (pintype "passive"))
      (node (ref "R299") (pin "2") (pinfunction "2_2") (pintype "passive"))
    )
    (net (code "494") (name "Net-(Q45-B)") (class "Default")
      (node (ref "Q45") (pin "1") (pinfunction "B_1") (pintype "passive"))
      (node (ref "Q45") (pin "2") (pinfunction "C_2") (pintype "passive"))
      (node (ref "Q46") (pin "1") (pinfunction "B_1") (pintype "passive"))
      (node (ref "R294") (pin "1") (pinfunction "1_1") (pintype "passive"))
      (node (ref "R295") (pin "1") (pinfunction "1_1") (pintype "passive"))
      (node (ref "R319") (pin "1") (pinfunction "1_1") (pintype "passive"))
      (node (ref "X15") (pin "2") (pinfunction "S_2") (pintype "passive"))
    )
    (net (code "495") (name "Net-(Q45-E)") (class "Default")
      (node (ref "Q45") (pin "3") (pinfunction "E_3") (pintype "passive"))
      (node (ref "R300") (pin "2") (pinfunction "2_2") (pintype "passive"))
    )
    (net (code "496") (name "Net-(Q46-E)") (class "Default")
      (node (ref "Q46") (pin "3") (pinfunction "E_3") (pintype "passive"))
      (node (ref "R301") (pin "2") (pinfunction "2_2") (pintype "passive"))
    )
    (net (code "497") (name "Net-(Q47-B)") (class "Default")
      (node (ref "Q47") (pin "1") (pinfunction "B_1") (pintype "passive"))
      (node (ref "R292") (pin "1") (pinfunction "1_1") (pintype "passive"))
    )
    (net (code "498") (name "Net-(Q48-B)") (class "Default")
      (node (ref "Q48") (pin "1") (pinfunction "B_1") (pintype "passive"))
      (node (ref "R303") (pin "2") (pinfunction "2_2") (pintype "passive"))
      (node (ref "R324") (pin "1") (pinfunction "1_1") (pintype "passive"))
    )
    (net (code "499") (name "Net-(Q48-E)") (class "Default")
      (node (ref "Q48") (pin "3") (pinfunction "E_3") (pintype "passive"))
      (node (ref "R323") (pin "1") (pinfunction "1_1") (pintype "passive"))
    )
    (net (code "500") (name "Net-(Q49-D)") (class "Default")
      (node (ref "Q49") (pin "3") (pinfunction "D_3") (pintype "passive"))
      (node (ref "R304") (pin "2") (pinfunction "2_2") (pintype "passive"))
    )
    (net (code "501") (name "Net-(Q50-S)") (class "Default")
      (node (ref "Q50") (pin "2") (pinfunction "S_2") (pintype "passive"))
      (node (ref "R325") (pin "2") (pinfunction "2_2") (pintype "passive"))
    )
    (net (code "502") (name "Net-(Q52-B)") (class "Default")
      (node (ref "Q52") (pin "1") (pinfunction "B_1") (pintype "passive"))
      (node (ref "R327") (pin "1") (pinfunction "1_1") (pintype "passive"))
    )
    (net (code "503") (name "Net-(Q52-C)") (class "Default")
      (node (ref "Q52") (pin "2") (pinfunction "C_2") (pintype "passive"))
      (node (ref "R278") (pin "2") (pinfunction "2_2") (pintype "passive"))
      (node (ref "SJMP5") (pin "2") (pinfunction "2_2") (pintype "passive"))
    )
    (net (code "504") (name "Net-(Q53-D)") (class "Default")
      (node (ref "Q53") (pin "3") (pinfunction "D_3") (pintype "passive"))
      (node (ref "R327") (pin "2") (pinfunction "2_2") (pintype "passive"))
    )
    (net (code "505") (name "Net-(Q101-B)") (class "Default")
      (node (ref "Q101") (pin "1") (pinfunction "B_1") (pintype "passive"))
      (node (ref "Q102") (pin "1") (pinfunction "B_1") (pintype "passive"))
      (node (ref "Q102") (pin "2") (pinfunction "C_2") (pintype "passive"))
      (node (ref "R101") (pin "1") (pinfunction "1_1") (pintype "passive"))
      (node (ref "R103") (pin "1") (pinfunction "1_1") (pintype "passive"))
      (node (ref "R104") (pin "1") (pinfunction "1_1") (pintype "passive"))
      (node (ref "X102") (pin "2") (pinfunction "S_2") (pintype "passive"))
    )
    (net (code "506") (name "Net-(Q101-E)") (class "Default")
      (node (ref "Q101") (pin "3") (pinfunction "E_3") (pintype "passive"))
      (node (ref "R102") (pin "2") (pinfunction "2_2") (pintype "passive"))
    )
    (net (code "507") (name "Net-(Q102-E)") (class "Default")
      (node (ref "Q102") (pin "3") (pinfunction "E_3") (pintype "passive"))
      (node (ref "R106") (pin "2") (pinfunction "2_2") (pintype "passive"))
    )
    (net (code "508") (name "Net-(Q103-B)") (class "Default")
      (node (ref "Q103") (pin "1") (pinfunction "B_1") (pintype "passive"))
      (node (ref "R116") (pin "2") (pinfunction "2_2") (pintype "passive"))
      (node (ref "R6") (pin "1") (pinfunction "1_1") (pintype "passive"))
    )
    (net (code "509") (name "Net-(Q103-E)") (class "Default")
      (node (ref "Q103") (pin "3") (pinfunction "E_3") (pintype "passive"))
      (node (ref "R5") (pin "1") (pinfunction "1_1") (pintype "passive"))
    )
    (net (code "510") (name "Net-(Q104-B)") (class "Default")
      (node (ref "Q104") (pin "1") (pinfunction "B_1") (pintype "passive"))
      (node (ref "R128") (pin "2") (pinfunction "2_2") (pintype "passive"))
    )
    (net (code "511") (name "Net-(Q105-B)") (class "Default")
      (node (ref "Q105") (pin "1") (pinfunction "B_1") (pintype "passive"))
      (node (ref "R126") (pin "1") (pinfunction "1_1") (pintype "passive"))
    )
    (net (code "512") (name "Net-(Q106-S)") (class "Default")
      (node (ref "Q106") (pin "2") (pinfunction "S_2") (pintype "passive"))
      (node (ref "R4") (pin "2") (pinfunction "2_2") (pintype "passive"))
    )
    (net (code "513") (name "Net-(Q107-D)") (class "Default")
      (node (ref "Q107") (pin "3") (pinfunction "D_3") (pintype "passive"))
      (node (ref "R138") (pin "2") (pinfunction "2_2") (pintype "passive"))
    )
    (net (code "514") (name "Net-(R14-Pad1)") (class "Default")
      (node (ref "R14") (pin "1") (pinfunction "1_1") (pintype "passive"))
      (node (ref "R7") (pin "2") (pinfunction "2_2") (pintype "passive"))
    )
    (net (code "515") (name "Net-(R32-Pad1)") (class "Default")
      (node (ref "R32") (pin "1") (pinfunction "1_1") (pintype "passive"))
      (node (ref "X1") (pin "21") (pinfunction "21_21") (pintype "passive"))
    )
    (net (code "516") (name "Net-(R44-Pad2)") (class "Default")
      (node (ref "R44") (pin "2") (pinfunction "2_2") (pintype "passive"))
      (node (ref "X1") (pin "16") (pinfunction "16_16") (pintype "passive"))
    )
    (net (code "517") (name "Net-(R67-Pad2)") (class "Default")
      (node (ref "R67") (pin "2") (pinfunction "2_2") (pintype "passive"))
      (node (ref "R69") (pin "1") (pinfunction "1_1") (pintype "passive"))
    )
    (net (code "518") (name "Net-(R87-Pad1)") (class "Default")
      (node (ref "R87") (pin "1") (pinfunction "1_1") (pintype "passive"))
      (node (ref "X4") (pin "21") (pinfunction "21_21") (pintype "passive"))
    )
    (net (code "519") (name "Net-(R99-Pad2)") (class "Default")
      (node (ref "R99") (pin "2") (pinfunction "2_2") (pintype "passive"))
      (node (ref "X4") (pin "16") (pinfunction "16_16") (pintype "passive"))
    )
    (net (code "520") (name "Net-(R115-Pad1)") (class "Default")
      (node (ref "R115") (pin "1") (pinfunction "1_1") (pintype "passive"))
      (node (ref "X101") (pin "21") (pinfunction "21_21") (pintype "passive"))
    )
    (net (code "521") (name "Net-(R127-Pad2)") (class "Default")
      (node (ref "R127") (pin "2") (pinfunction "2_2") (pintype "passive"))
      (node (ref "R129") (pin "1") (pinfunction "1_1") (pintype "passive"))
    )
    (net (code "522") (name "Net-(R140-Pad2)") (class "Default")
      (node (ref "R140") (pin "2") (pinfunction "2_2") (pintype "passive"))
      (node (ref "X101") (pin "16") (pinfunction "16_16") (pintype "passive"))
    )
    (net (code "523") (name "Net-(R166-Pad2)") (class "Default")
      (node (ref "R166") (pin "2") (pinfunction "2_2") (pintype "passive"))
      (node (ref "R168") (pin "1") (pinfunction "1_1") (pintype "passive"))
    )
    (net (code "524") (name "Net-(R186-Pad1)") (class "Default")
      (node (ref "R186") (pin "1") (pinfunction "1_1") (pintype "passive"))
      (node (ref "X7") (pin "21") (pinfunction "21_21") (pintype "passive"))
    )
    (net (code "525") (name "Net-(R198-Pad2)") (class "Default")
      (node (ref "R198") (pin "2") (pinfunction "2_2") (pintype "passive"))
      (node (ref "X7") (pin "16") (pinfunction "16_16") (pintype "passive"))
    )
    (net (code "526") (name "Net-(R221-Pad2)") (class "Default")
      (node (ref "R221") (pin "2") (pinfunction "2_2") (pintype "passive"))
      (node (ref "R223") (pin "1") (pinfunction "1_1") (pintype "passive"))
    )
    (net (code "527") (name "Net-(R241-Pad1)") (class "Default")
      (node (ref "R241") (pin "1") (pinfunction "1_1") (pintype "passive"))
      (node (ref "X10") (pin "21") (pinfunction "21_21") (pintype "passive"))
    )
    (net (code "528") (name "Net-(R253-Pad2)") (class "Default")
      (node (ref "R253") (pin "2") (pinfunction "2_2") (pintype "passive"))
      (node (ref "X10") (pin "16") (pinfunction "16_16") (pintype "passive"))
    )
    (net (code "529") (name "Net-(R276-Pad2)") (class "Default")
      (node (ref "R276") (pin "2") (pinfunction "2_2") (pintype "passive"))
      (node (ref "R278") (pin "1") (pinfunction "1_1") (pintype "passive"))
    )
    (net (code "530") (name "Net-(R296-Pad1)") (class "Default")
      (node (ref "R296") (pin "1") (pinfunction "1_1") (pintype "passive"))
      (node (ref "X13") (pin "21") (pinfunction "21_21") (pintype "passive"))
    )
    (net (code "531") (name "Net-(R308-Pad2)") (class "Default")
      (node (ref "R308") (pin "2") (pinfunction "2_2") (pintype "passive"))
      (node (ref "X13") (pin "16") (pinfunction "16_16") (pintype "passive"))
    )
    (net (code "532") (name "V+") (class "Default")
      (node (ref "D1") (pin "1") (pinfunction "+_1") (pintype "passive"))
      (node (ref "D15") (pin "1") (pinfunction "+_1") (pintype "passive"))
      (node (ref "D29") (pin "1") (pinfunction "+_1") (pintype "passive"))
      (node (ref "D43") (pin "1") (pinfunction "+_1") (pintype "passive"))
      (node (ref "D57") (pin "1") (pinfunction "+_1") (pintype "passive"))
      (node (ref "D71") (pin "1") (pinfunction "+_1") (pintype "passive"))
      (node (ref "Q104") (pin "3") (pinfunction "E_3") (pintype "passive"))
      (node (ref "Q105") (pin "3") (pinfunction "E_3") (pintype "passive"))
      (node (ref "Q12") (pin "3") (pinfunction "E_3") (pintype "passive"))
      (node (ref "Q14") (pin "3") (pinfunction "E_3") (pintype "passive"))
      (node (ref "Q17") (pin "3") (pinfunction "E_3") (pintype "passive"))
      (node (ref "Q2") (pin "3") (pinfunction "E_3") (pintype "passive"))
      (node (ref "Q22") (pin "3") (pinfunction "E_3") (pintype "passive"))
      (node (ref "Q24") (pin "3") (pinfunction "E_3") (pintype "passive"))
      (node (ref "Q27") (pin "3") (pinfunction "E_3") (pintype "passive"))
      (node (ref "Q32") (pin "3") (pinfunction "E_3") (pintype "passive"))
      (node (ref "Q34") (pin "3") (pinfunction "E_3") (pintype "passive"))
      (node (ref "Q37") (pin "3") (pinfunction "E_3") (pintype "passive"))
      (node (ref "Q4") (pin "3") (pinfunction "E_3") (pintype "passive"))
      (node (ref "Q42") (pin "3") (pinfunction "E_3") (pintype "passive"))
      (node (ref "Q44") (pin "3") (pinfunction "E_3") (pintype "passive"))
      (node (ref "Q47") (pin "3") (pinfunction "E_3") (pintype "passive"))
      (node (ref "Q52") (pin "3") (pinfunction "E_3") (pintype "passive"))
      (node (ref "Q7") (pin "3") (pinfunction "E_3") (pintype "passive"))
      (node (ref "SJMP") (pin "1") (pinfunction "1_1") (pintype "passive"))
      (node (ref "SJMP1") (pin "1") (pinfunction "1_1") (pintype "passive"))
      (node (ref "SJMP2") (pin "1") (pinfunction "1_1") (pintype "passive"))
      (node (ref "SJMP3") (pin "1") (pinfunction "1_1") (pintype "passive"))
      (node (ref "SJMP4") (pin "1") (pinfunction "1_1") (pintype "passive"))
      (node (ref "SJMP5") (pin "1") (pinfunction "1_1") (pintype "passive"))
      (node (ref "X1") (pin "6") (pinfunction "6_6") (pintype "passive"))
      (node (ref "X10") (pin "6") (pinfunction "6_6") (pintype "passive"))
      (node (ref "X101") (pin "6") (pinfunction "6_6") (pintype "passive"))
      (node (ref "X13") (pin "6") (pinfunction "6_6") (pintype "passive"))
      (node (ref "X4") (pin "6") (pinfunction "6_6") (pintype "passive"))
      (node (ref "X7") (pin "6") (pinfunction "6_6") (pintype "passive"))
    )
    (net (code "533") (name "VCC") (class "Default")
      (node (ref "6V") (pin "TP") (pinfunction "PP_TP") (pintype "input"))
      (node (ref "6V1") (pin "TP") (pinfunction "PP_TP") (pintype "input"))
      (node (ref "6V2") (pin "TP") (pinfunction "PP_TP") (pintype "input"))
      (node (ref "6V3") (pin "TP") (pinfunction "PP_TP") (pintype "input"))
      (node (ref "6V4") (pin "TP") (pinfunction "PP_TP") (pintype "input"))
      (node (ref "6V5") (pin "TP") (pinfunction "PP_TP") (pintype "input"))
      (node (ref "C104") (pin "1") (pinfunction "1_1") (pintype "passive"))
      (node (ref "C17") (pin "1") (pinfunction "1_1") (pintype "passive"))
      (node (ref "C29") (pin "1") (pinfunction "1_1") (pintype "passive"))
      (node (ref "C4") (pin "1") (pinfunction "1_1") (pintype "passive"))
      (node (ref "C41") (pin "1") (pinfunction "1_1") (pintype "passive"))
      (node (ref "C53") (pin "1") (pinfunction "1_1") (pintype "passive"))
      (node (ref "IC101") (pin "8") (pinfunction "V+_8") (pintype "power_in"))
      (node (ref "IC102") (pin "1") (pinfunction "OUT_1") (pintype "passive"))
      (node (ref "IC108") (pin "3") (pinfunction "V+_3") (pintype "power_in"))
      (node (ref "IC13") (pin "3") (pinfunction "V+_3") (pintype "power_in"))
      (node (ref "IC14") (pin "1") (pinfunction "OUT_1") (pintype "passive"))
      (node (ref "IC18") (pin "8") (pinfunction "V+_8") (pintype "power_in"))
      (node (ref "IC22") (pin "3") (pinfunction "V+_3") (pintype "power_in"))
      (node (ref "IC23") (pin "1") (pinfunction "OUT_1") (pintype "passive"))
      (node (ref "IC27") (pin "8") (pinfunction "V+_8") (pintype "power_in"))
      (node (ref "IC31") (pin "3") (pinfunction "V+_3") (pintype "power_in"))
      (node (ref "IC32") (pin "1") (pinfunction "OUT_1") (pintype "passive"))
      (node (ref "IC36") (pin "8") (pinfunction "V+_8") (pintype "power_in"))
      (node (ref "IC4") (pin "3") (pinfunction "V+_3") (pintype "power_in"))
      (node (ref "IC40") (pin "3") (pinfunction "V+_3") (pintype "power_in"))
      (node (ref "IC41") (pin "1") (pinfunction "OUT_1") (pintype "passive"))
      (node (ref "IC45") (pin "8") (pinfunction "V+_8") (pintype "power_in"))
      (node (ref "IC5") (pin "1") (pinfunction "OUT_1") (pintype "passive"))
      (node (ref "IC9") (pin "8") (pinfunction "V+_8") (pintype "power_in"))
      (node (ref "R113") (pin "2") (pinfunction "2_2") (pintype "passive"))
      (node (ref "R121") (pin "2") (pinfunction "2_2") (pintype "passive"))
      (node (ref "R124") (pin "1") (pinfunction "1_1") (pintype "passive"))
      (node (ref "R131") (pin "2") (pinfunction "2_2") (pintype "passive"))
      (node (ref "R142") (pin "2") (pinfunction "2_2") (pintype "passive"))
      (node (ref "R152") (pin "2") (pinfunction "2_2") (pintype "passive"))
      (node (ref "R175") (pin "2") (pinfunction "2_2") (pintype "passive"))
      (node (ref "R178") (pin "2") (pinfunction "2_2") (pintype "passive"))
      (node (ref "R181") (pin "1") (pinfunction "1_1") (pintype "passive"))
      (node (ref "R188") (pin "2") (pinfunction "2_2") (pintype "passive"))
      (node (ref "R207") (pin "2") (pinfunction "2_2") (pintype "passive"))
      (node (ref "R21") (pin "2") (pinfunction "2_2") (pintype "passive"))
      (node (ref "R230") (pin "2") (pinfunction "2_2") (pintype "passive"))
      (node (ref "R233") (pin "2") (pinfunction "2_2") (pintype "passive"))
      (node (ref "R236") (pin "1") (pinfunction "1_1") (pintype "passive"))
      (node (ref "R24") (pin "2") (pinfunction "2_2") (pintype "passive"))
      (node (ref "R243") (pin "2") (pinfunction "2_2") (pintype "passive"))
      (node (ref "R262") (pin "2") (pinfunction "2_2") (pintype "passive"))
      (node (ref "R27") (pin "1") (pinfunction "1_1") (pintype "passive"))
      (node (ref "R285") (pin "2") (pinfunction "2_2") (pintype "passive"))
      (node (ref "R288") (pin "2") (pinfunction "2_2") (pintype "passive"))
      (node (ref "R291") (pin "1") (pinfunction "1_1") (pintype "passive"))
      (node (ref "R298") (pin "2") (pinfunction "2_2") (pintype "passive"))
      (node (ref "R317") (pin "2") (pinfunction "2_2") (pintype "passive"))
      (node (ref "R34") (pin "2") (pinfunction "2_2") (pintype "passive"))
      (node (ref "R53") (pin "2") (pinfunction "2_2") (pintype "passive"))
      (node (ref "R76") (pin "2") (pinfunction "2_2") (pintype "passive"))
      (node (ref "R79") (pin "2") (pinfunction "2_2") (pintype "passive"))
      (node (ref "R82") (pin "1") (pinfunction "1_1") (pintype "passive"))
      (node (ref "R89") (pin "2") (pinfunction "2_2") (pintype "passive"))
    )
    (net (code "534") (name "unconnected-(IC1A-Q6-Pad7)") (class "Default")
      (node (ref "IC1") (pin "7") (pinfunction "Q6_7") (pintype "output"))
    )
    (net (code "535") (name "unconnected-(IC1A-Q7-Pad4)") (class "Default")
      (node (ref "IC1") (pin "4") (pinfunction "Q7_4") (pintype "output"))
    )
    (net (code "536") (name "unconnected-(IC1A-Q8-Pad9)") (class "Default")
      (node (ref "IC1") (pin "9") (pinfunction "Q8_9") (pintype "output"))
    )
    (net (code "537") (name "unconnected-(IC1A-Q9-Pad5)") (class "Default")
      (node (ref "IC1") (pin "5") (pinfunction "Q9_5") (pintype "output"))
    )
    (net (code "538") (name "unconnected-(IC6-DIS-Pad7)") (class "Default")
      (node (ref "IC6") (pin "7") (pinfunction "DIS_7") (pintype "input"))
    )
    (net (code "539") (name "unconnected-(IC7A-~{Q}-Pad7)") (class "Default")
      (node (ref "IC7") (pin "7") (pinfunction "~{Q}_7") (pintype "output"))
    )
    (net (code "540") (name "unconnected-(IC7B-Q-Pad10)") (class "Default")
      (node (ref "IC7") (pin "10") (pinfunction "Q_10") (pintype "output"))
    )
    (net (code "541") (name "unconnected-(IC10A-Q6-Pad7)") (class "Default")
      (node (ref "IC10") (pin "7") (pinfunction "Q6_7") (pintype "output"))
    )
    (net (code "542") (name "unconnected-(IC10A-Q7-Pad4)") (class "Default")
      (node (ref "IC10") (pin "4") (pinfunction "Q7_4") (pintype "output"))
    )
    (net (code "543") (name "unconnected-(IC10A-Q8-Pad9)") (class "Default")
      (node (ref "IC10") (pin "9") (pinfunction "Q8_9") (pintype "output"))
    )
    (net (code "544") (name "unconnected-(IC10A-Q9-Pad5)") (class "Default")
      (node (ref "IC10") (pin "5") (pinfunction "Q9_5") (pintype "output"))
    )
    (net (code "545") (name "unconnected-(IC15-DIS-Pad7)") (class "Default")
      (node (ref "IC15") (pin "7") (pinfunction "DIS_7") (pintype "input"))
    )
    (net (code "546") (name "unconnected-(IC16A-~{Q}-Pad7)") (class "Default")
      (node (ref "IC16") (pin "7") (pinfunction "~{Q}_7") (pintype "output"))
    )
    (net (code "547") (name "unconnected-(IC16B-Q-Pad10)") (class "Default")
      (node (ref "IC16") (pin "10") (pinfunction "Q_10") (pintype "output"))
    )
    (net (code "548") (name "unconnected-(IC19A-Q6-Pad7)") (class "Default")
      (node (ref "IC19") (pin "7") (pinfunction "Q6_7") (pintype "output"))
    )
    (net (code "549") (name "unconnected-(IC19A-Q7-Pad4)") (class "Default")
      (node (ref "IC19") (pin "4") (pinfunction "Q7_4") (pintype "output"))
    )
    (net (code "550") (name "unconnected-(IC19A-Q8-Pad9)") (class "Default")
      (node (ref "IC19") (pin "9") (pinfunction "Q8_9") (pintype "output"))
    )
    (net (code "551") (name "unconnected-(IC19A-Q9-Pad5)") (class "Default")
      (node (ref "IC19") (pin "5") (pinfunction "Q9_5") (pintype "output"))
    )
    (net (code "552") (name "unconnected-(IC24-DIS-Pad7)") (class "Default")
      (node (ref "IC24") (pin "7") (pinfunction "DIS_7") (pintype "input"))
    )
    (net (code "553") (name "unconnected-(IC25A-~{Q}-Pad7)") (class "Default")
      (node (ref "IC25") (pin "7") (pinfunction "~{Q}_7") (pintype "output"))
    )
    (net (code "554") (name "unconnected-(IC25B-Q-Pad10)") (class "Default")
      (node (ref "IC25") (pin "10") (pinfunction "Q_10") (pintype "output"))
    )
    (net (code "555") (name "unconnected-(IC28A-Q6-Pad7)") (class "Default")
      (node (ref "IC28") (pin "7") (pinfunction "Q6_7") (pintype "output"))
    )
    (net (code "556") (name "unconnected-(IC28A-Q7-Pad4)") (class "Default")
      (node (ref "IC28") (pin "4") (pinfunction "Q7_4") (pintype "output"))
    )
    (net (code "557") (name "unconnected-(IC28A-Q8-Pad9)") (class "Default")
      (node (ref "IC28") (pin "9") (pinfunction "Q8_9") (pintype "output"))
    )
    (net (code "558") (name "unconnected-(IC28A-Q9-Pad5)") (class "Default")
      (node (ref "IC28") (pin "5") (pinfunction "Q9_5") (pintype "output"))
    )
    (net (code "559") (name "unconnected-(IC33-DIS-Pad7)") (class "Default")
      (node (ref "IC33") (pin "7") (pinfunction "DIS_7") (pintype "input"))
    )
    (net (code "560") (name "unconnected-(IC34A-~{Q}-Pad7)") (class "Default")
      (node (ref "IC34") (pin "7") (pinfunction "~{Q}_7") (pintype "output"))
    )
    (net (code "561") (name "unconnected-(IC34B-Q-Pad10)") (class "Default")
      (node (ref "IC34") (pin "10") (pinfunction "Q_10") (pintype "output"))
    )
    (net (code "562") (name "unconnected-(IC37A-Q6-Pad7)") (class "Default")
      (node (ref "IC37") (pin "7") (pinfunction "Q6_7") (pintype "output"))
    )
    (net (code "563") (name "unconnected-(IC37A-Q7-Pad4)") (class "Default")
      (node (ref "IC37") (pin "4") (pinfunction "Q7_4") (pintype "output"))
    )
    (net (code "564") (name "unconnected-(IC37A-Q8-Pad9)") (class "Default")
      (node (ref "IC37") (pin "9") (pinfunction "Q8_9") (pintype "output"))
    )
    (net (code "565") (name "unconnected-(IC37A-Q9-Pad5)") (class "Default")
      (node (ref "IC37") (pin "5") (pinfunction "Q9_5") (pintype "output"))
    )
    (net (code "566") (name "unconnected-(IC42-DIS-Pad7)") (class "Default")
      (node (ref "IC42") (pin "7") (pinfunction "DIS_7") (pintype "input"))
    )
    (net (code "567") (name "unconnected-(IC43A-~{Q}-Pad7)") (class "Default")
      (node (ref "IC43") (pin "7") (pinfunction "~{Q}_7") (pintype "output"))
    )
    (net (code "568") (name "unconnected-(IC43B-Q-Pad10)") (class "Default")
      (node (ref "IC43") (pin "10") (pinfunction "Q_10") (pintype "output"))
    )
    (net (code "569") (name "unconnected-(IC105A-Q6-Pad7)") (class "Default")
      (node (ref "IC105") (pin "7") (pinfunction "Q6_7") (pintype "output"))
    )
    (net (code "570") (name "unconnected-(IC105A-Q7-Pad4)") (class "Default")
      (node (ref "IC105") (pin "4") (pinfunction "Q7_4") (pintype "output"))
    )
    (net (code "571") (name "unconnected-(IC105A-Q8-Pad9)") (class "Default")
      (node (ref "IC105") (pin "9") (pinfunction "Q8_9") (pintype "output"))
    )
    (net (code "572") (name "unconnected-(IC105A-Q9-Pad5)") (class "Default")
      (node (ref "IC105") (pin "5") (pinfunction "Q9_5") (pintype "output"))
    )
    (net (code "573") (name "unconnected-(IC110-DIS-Pad7)") (class "Default")
      (node (ref "IC110") (pin "7") (pinfunction "DIS_7") (pintype "input"))
    )
    (net (code "574") (name "unconnected-(IC111A-~{Q}-Pad7)") (class "Default")
      (node (ref "IC111") (pin "7") (pinfunction "~{Q}_7") (pintype "output"))
    )
    (net (code "575") (name "unconnected-(IC111B-Q-Pad10)") (class "Default")
      (node (ref "IC111") (pin "10") (pinfunction "Q_10") (pintype "output"))
    )
    (net (code "576") (name "unconnected-(X1-Pad20)") (class "Default")
      (node (ref "X1") (pin "20") (pinfunction "20_20") (pintype "passive"))
    )
    (net (code "577") (name "unconnected-(X1-Pad24)") (class "Default")
      (node (ref "X1") (pin "24") (pinfunction "24_24") (pintype "passive"))
    )
    (net (code "578") (name "unconnected-(X4-Pad20)") (class "Default")
      (node (ref "X4") (pin "20") (pinfunction "20_20") (pintype "passive"))
    )
    (net (code "579") (name "unconnected-(X4-Pad24)") (class "Default")
      (node (ref "X4") (pin "24") (pinfunction "24_24") (pintype "passive"))
    )
    (net (code "580") (name "unconnected-(X7-Pad20)") (class "Default")
      (node (ref "X7") (pin "20") (pinfunction "20_20") (pintype "passive"))
    )
    (net (code "581") (name "unconnected-(X7-Pad24)") (class "Default")
      (node (ref "X7") (pin "24") (pinfunction "24_24") (pintype "passive"))
    )
    (net (code "582") (name "unconnected-(X10-Pad20)") (class "Default")
      (node (ref "X10") (pin "20") (pinfunction "20_20") (pintype "passive"))
    )
    (net (code "583") (name "unconnected-(X10-Pad24)") (class "Default")
      (node (ref "X10") (pin "24") (pinfunction "24_24") (pintype "passive"))
    )
    (net (code "584") (name "unconnected-(X13-Pad20)") (class "Default")
      (node (ref "X13") (pin "20") (pinfunction "20_20") (pintype "passive"))
    )
    (net (code "585") (name "unconnected-(X13-Pad24)") (class "Default")
      (node (ref "X13") (pin "24") (pinfunction "24_24") (pintype "passive"))
    )
    (net (code "586") (name "unconnected-(X101-Pad20)") (class "Default")
      (node (ref "X101") (pin "20") (pinfunction "20_20") (pintype "passive"))
    )
    (net (code "587") (name "unconnected-(X101-Pad24)") (class "Default")
      (node (ref "X101") (pin "24") (pinfunction "24_24") (pintype "passive"))
    )
  )
)
